# icyradio.net
KiCad netlist of a schematic drawn in EAGLE
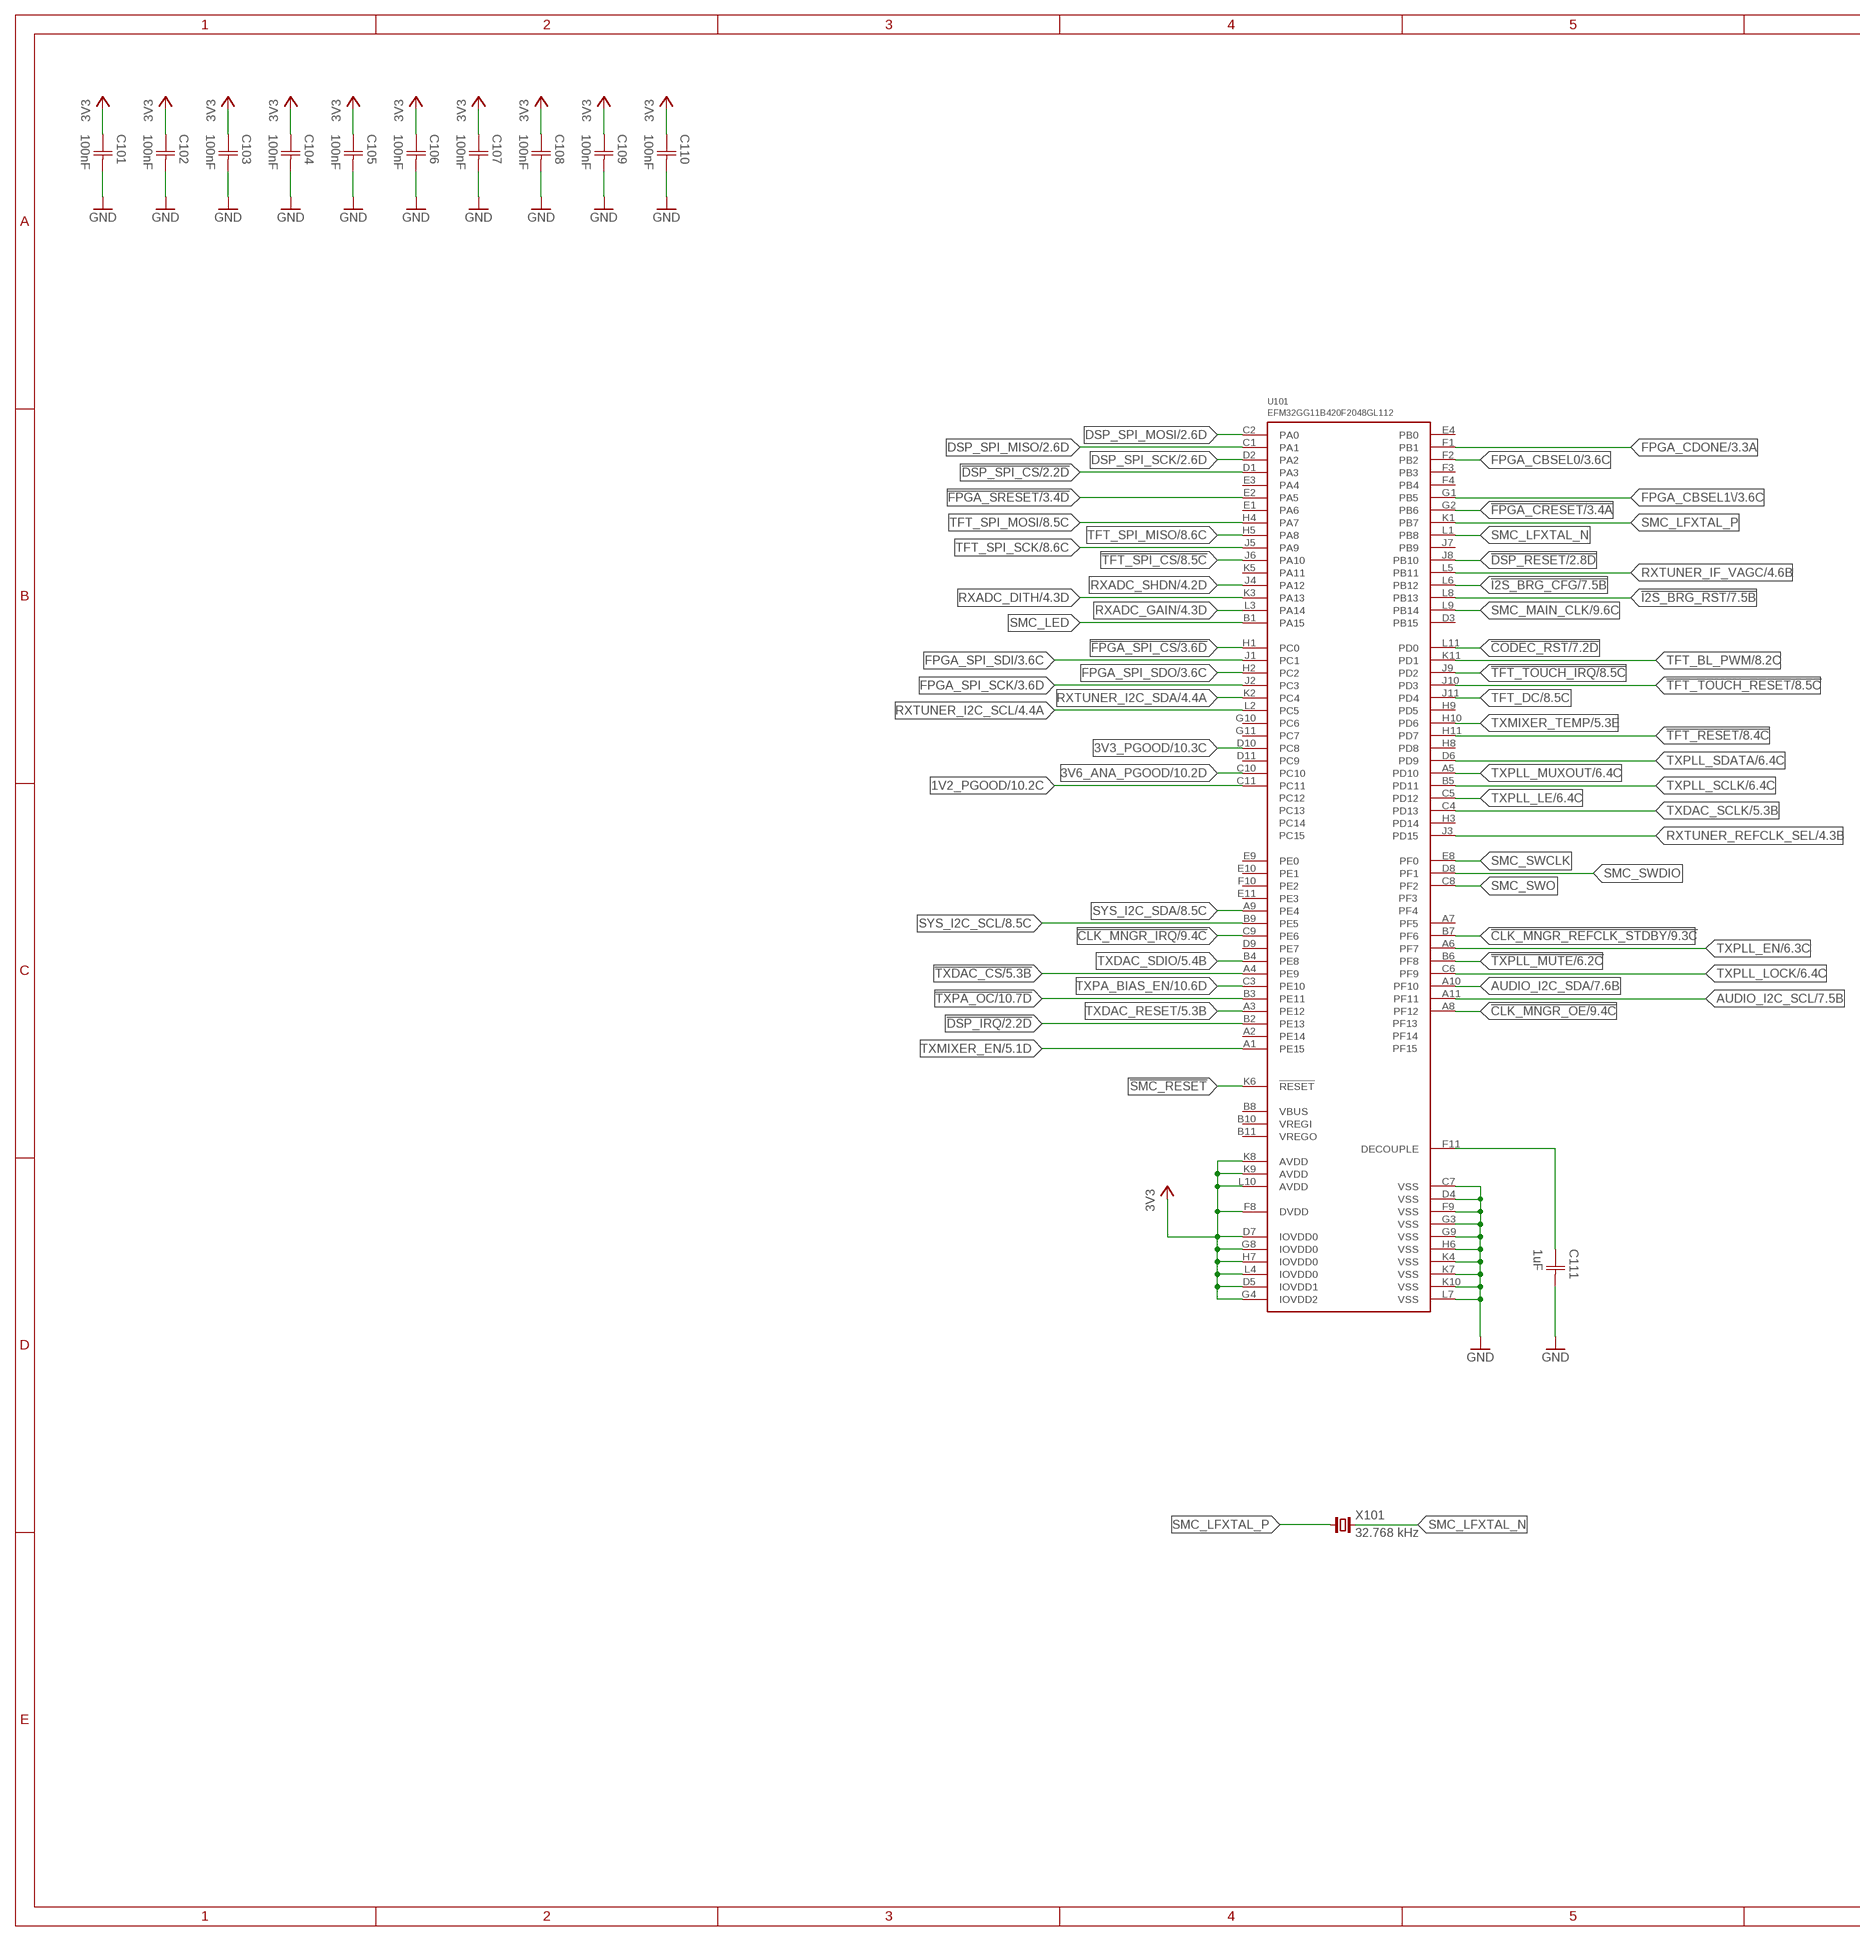
[diagram p0: schematic, sheet 1, part 1 of 2]
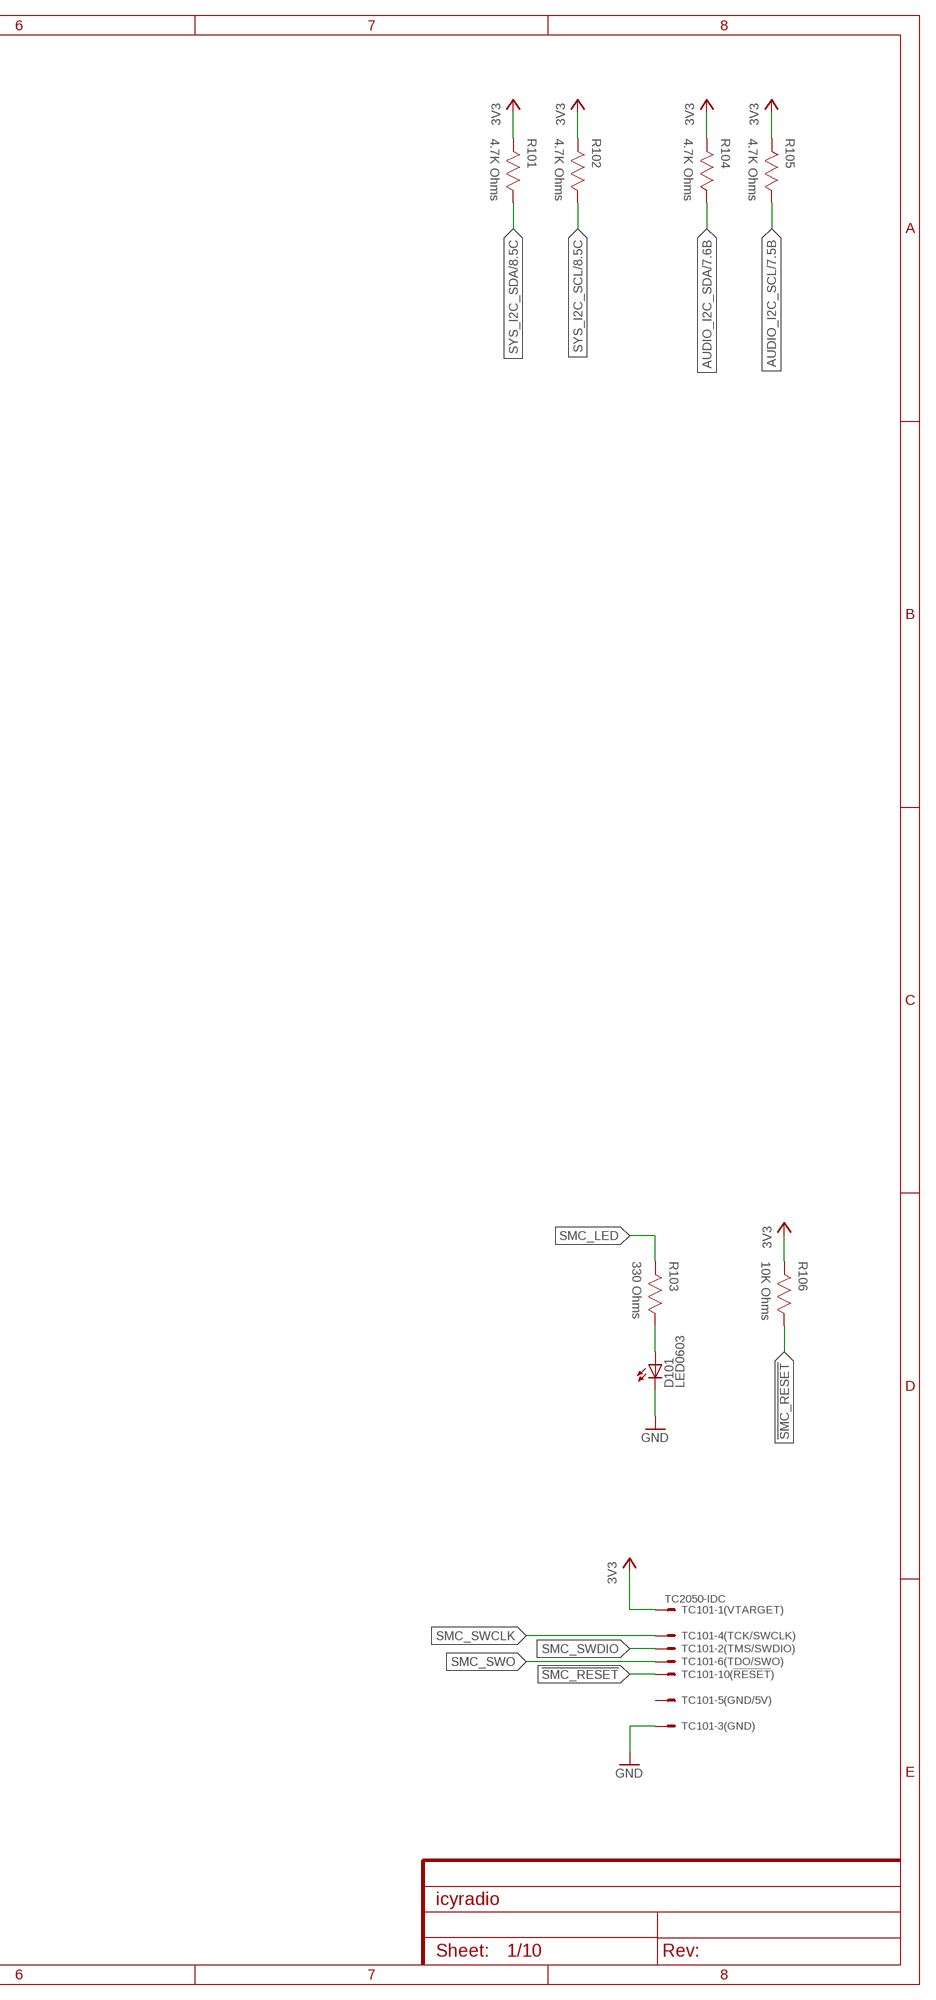
[diagram p1: schematic, sheet 1, part 2 of 2]
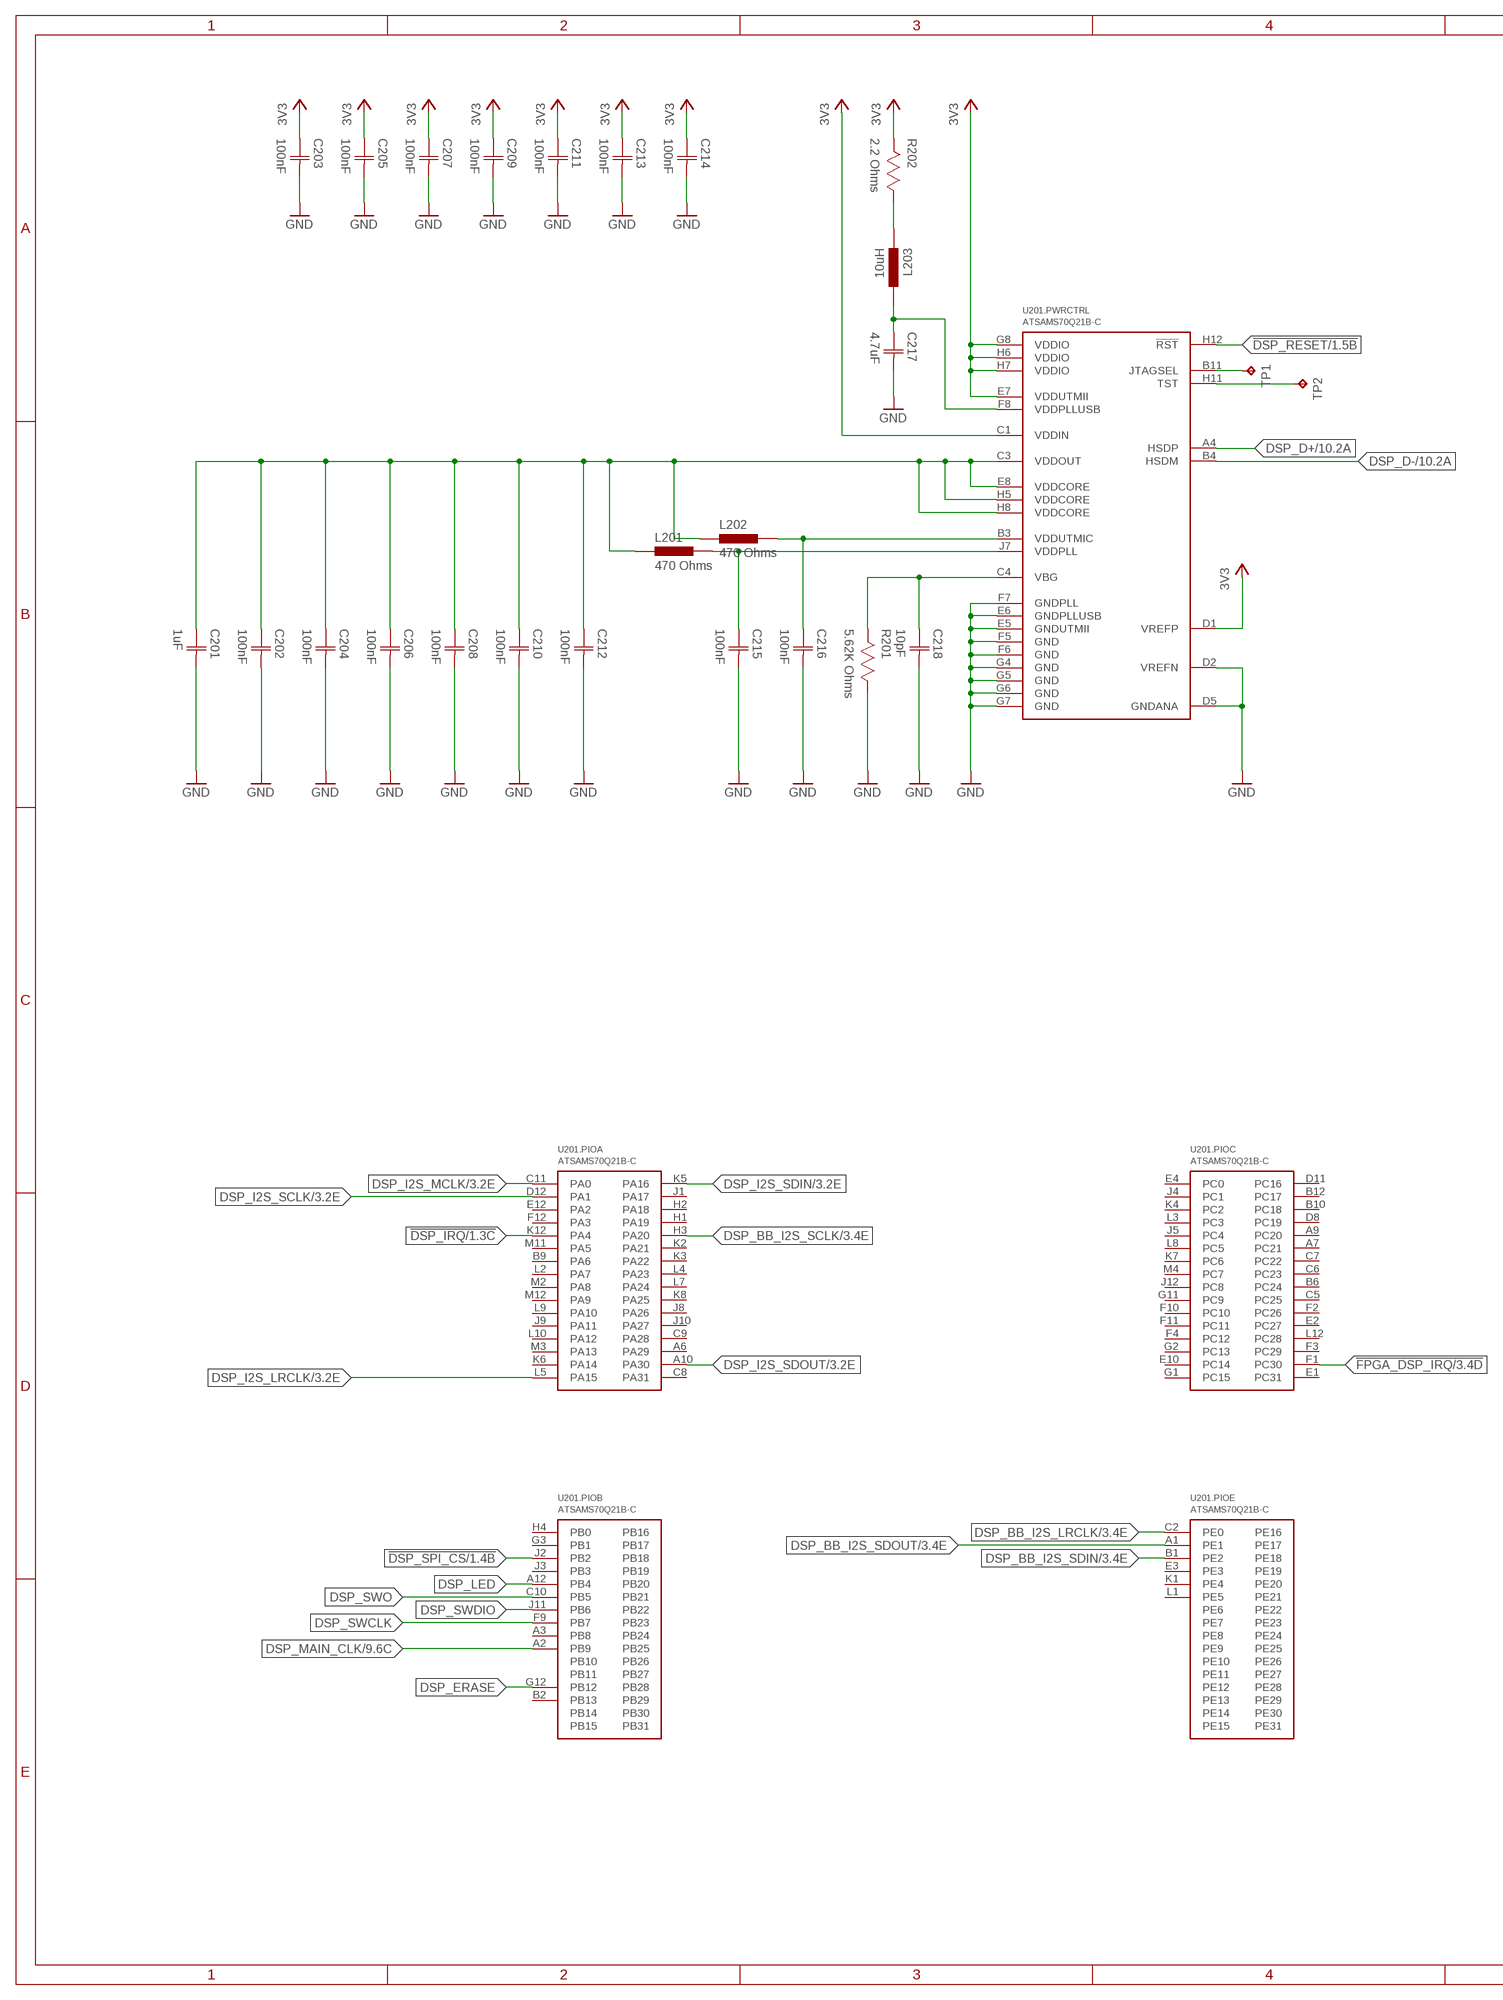
[diagram p2: schematic, sheet 2, part 1 of 2]
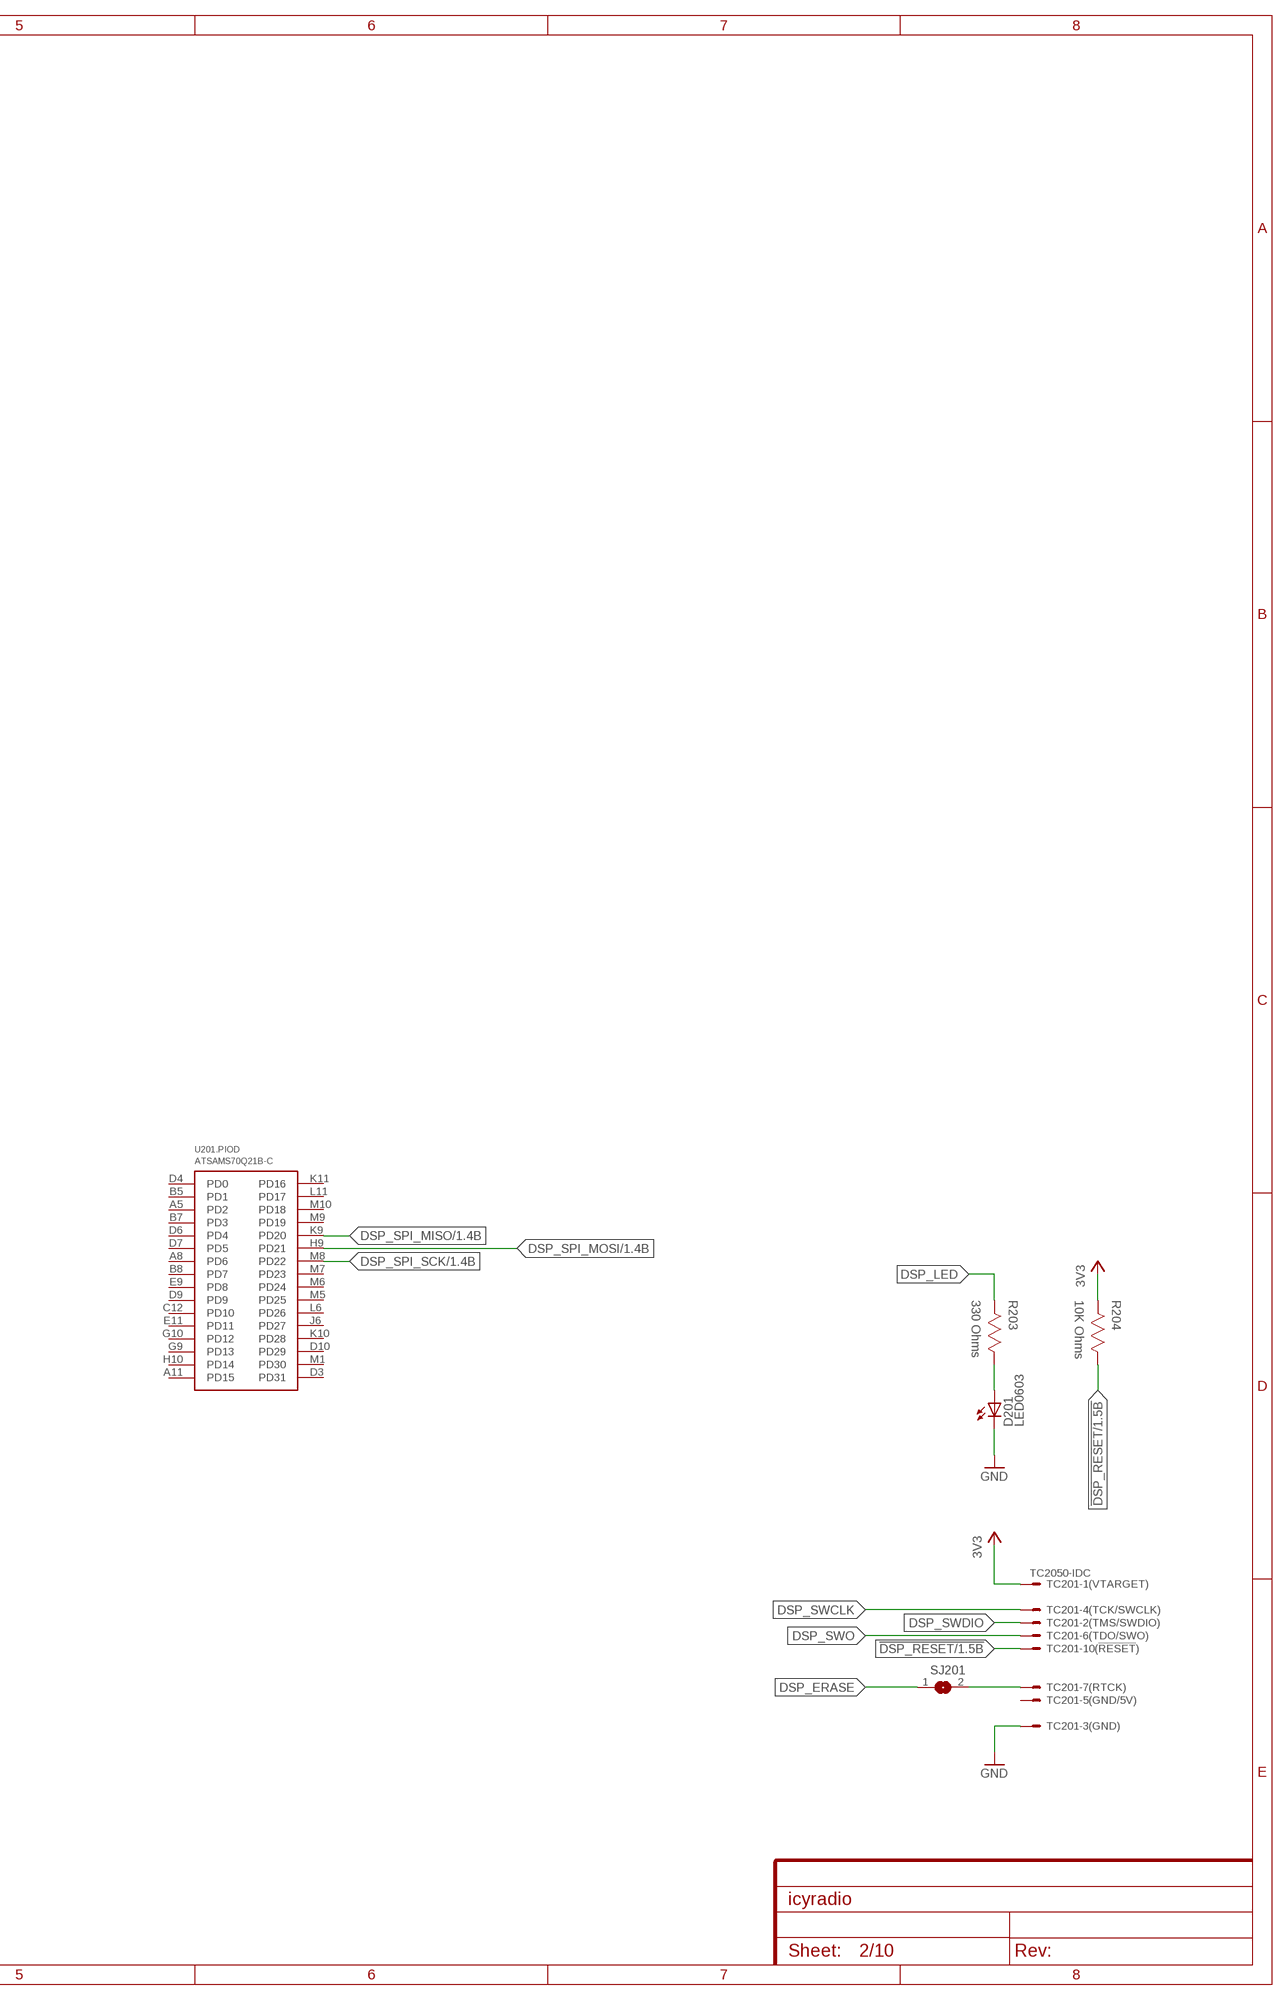
[diagram p3: schematic, sheet 2, part 2 of 2]
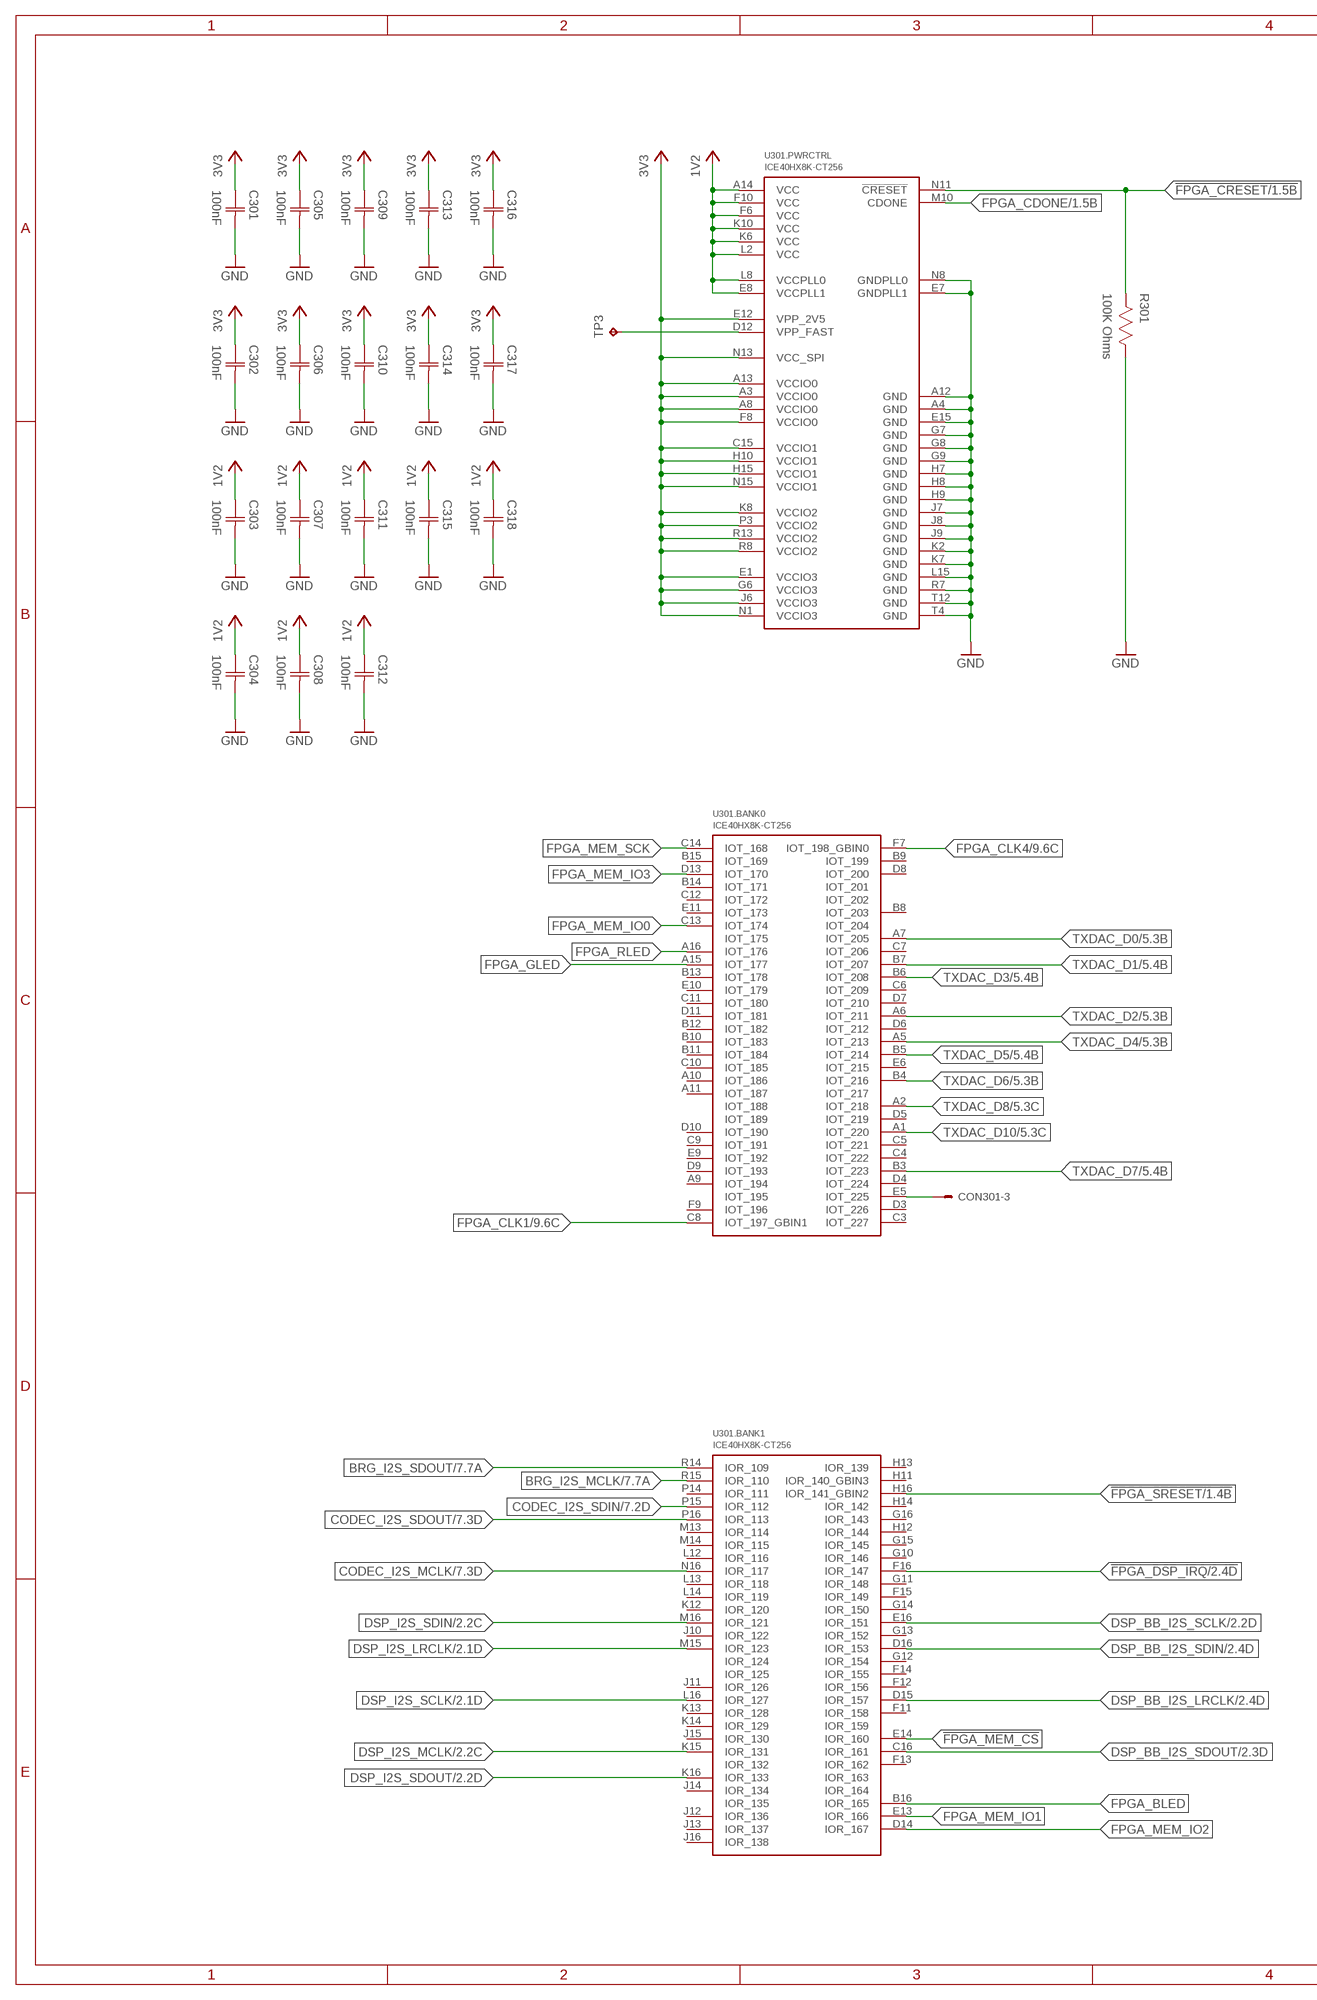
[diagram p4: schematic, sheet 3, part 1 of 2]
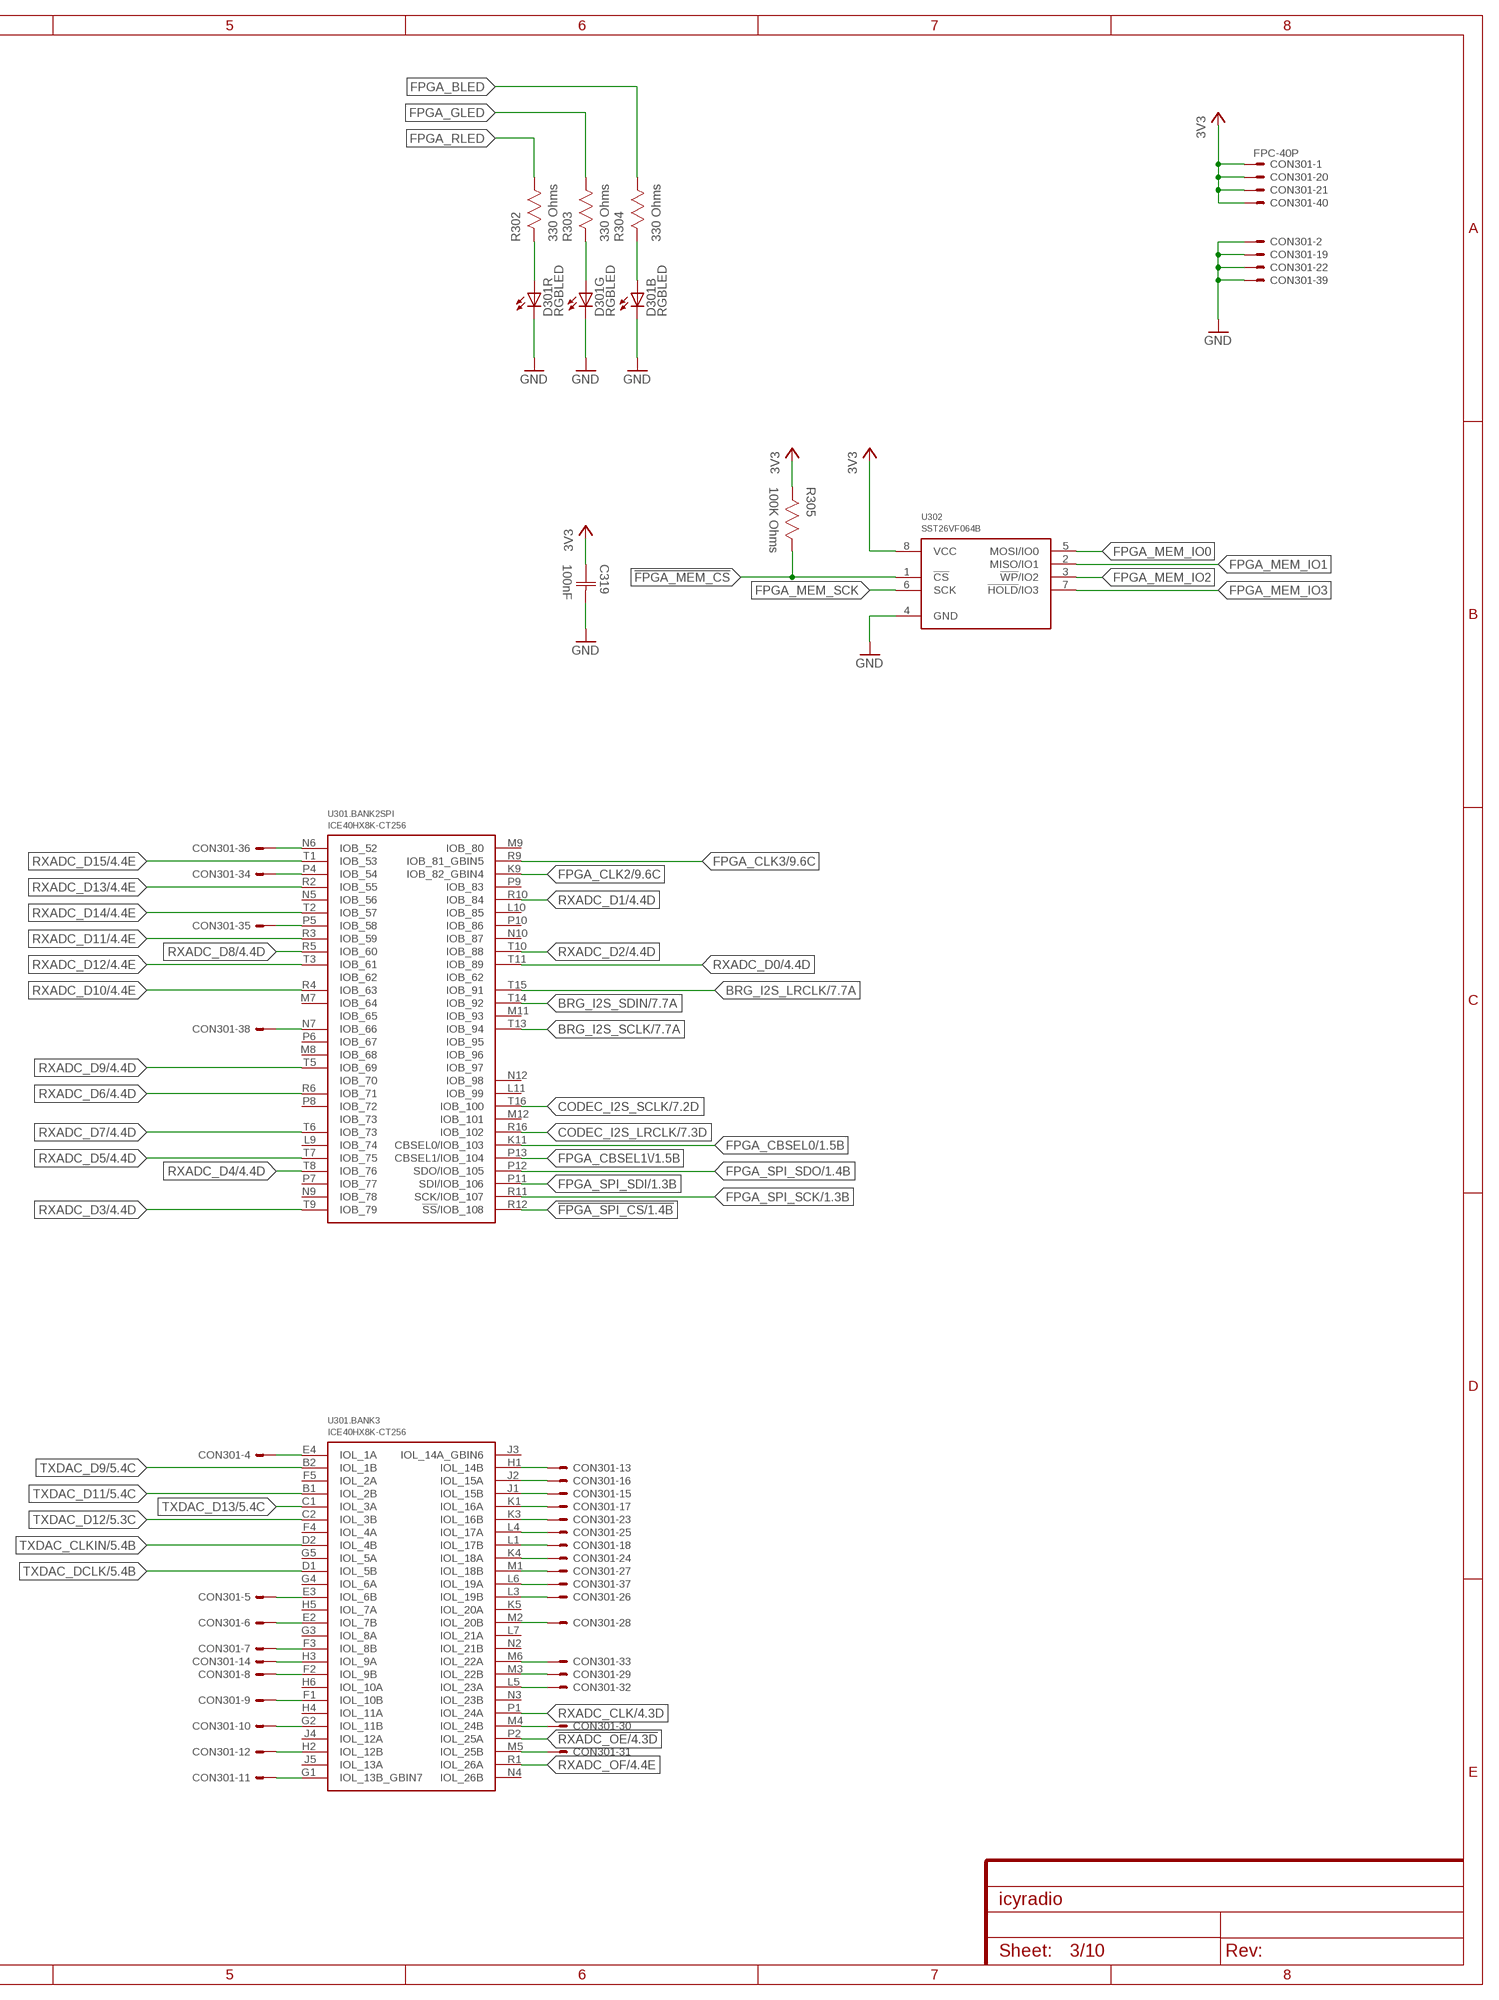
[diagram p5: schematic, sheet 3, part 2 of 2]
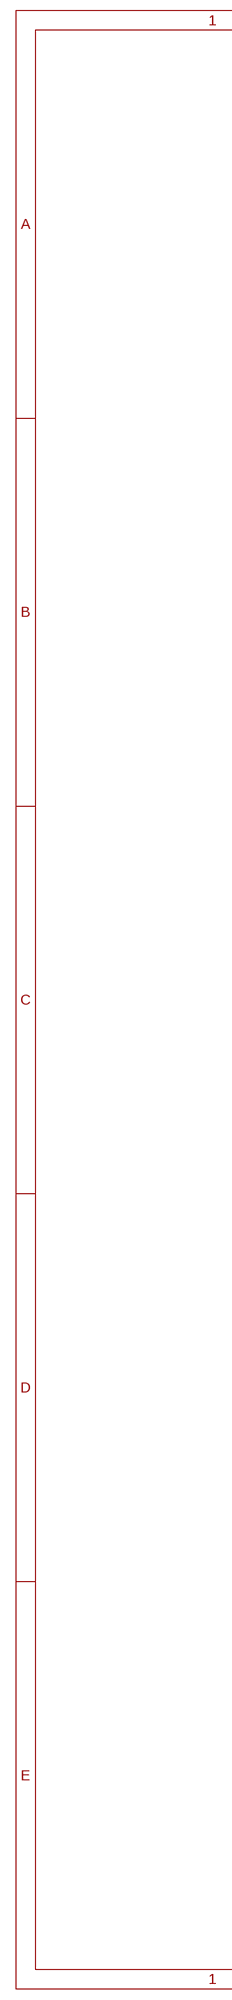
[diagram p6: schematic, sheet 4, part 1 of 2]
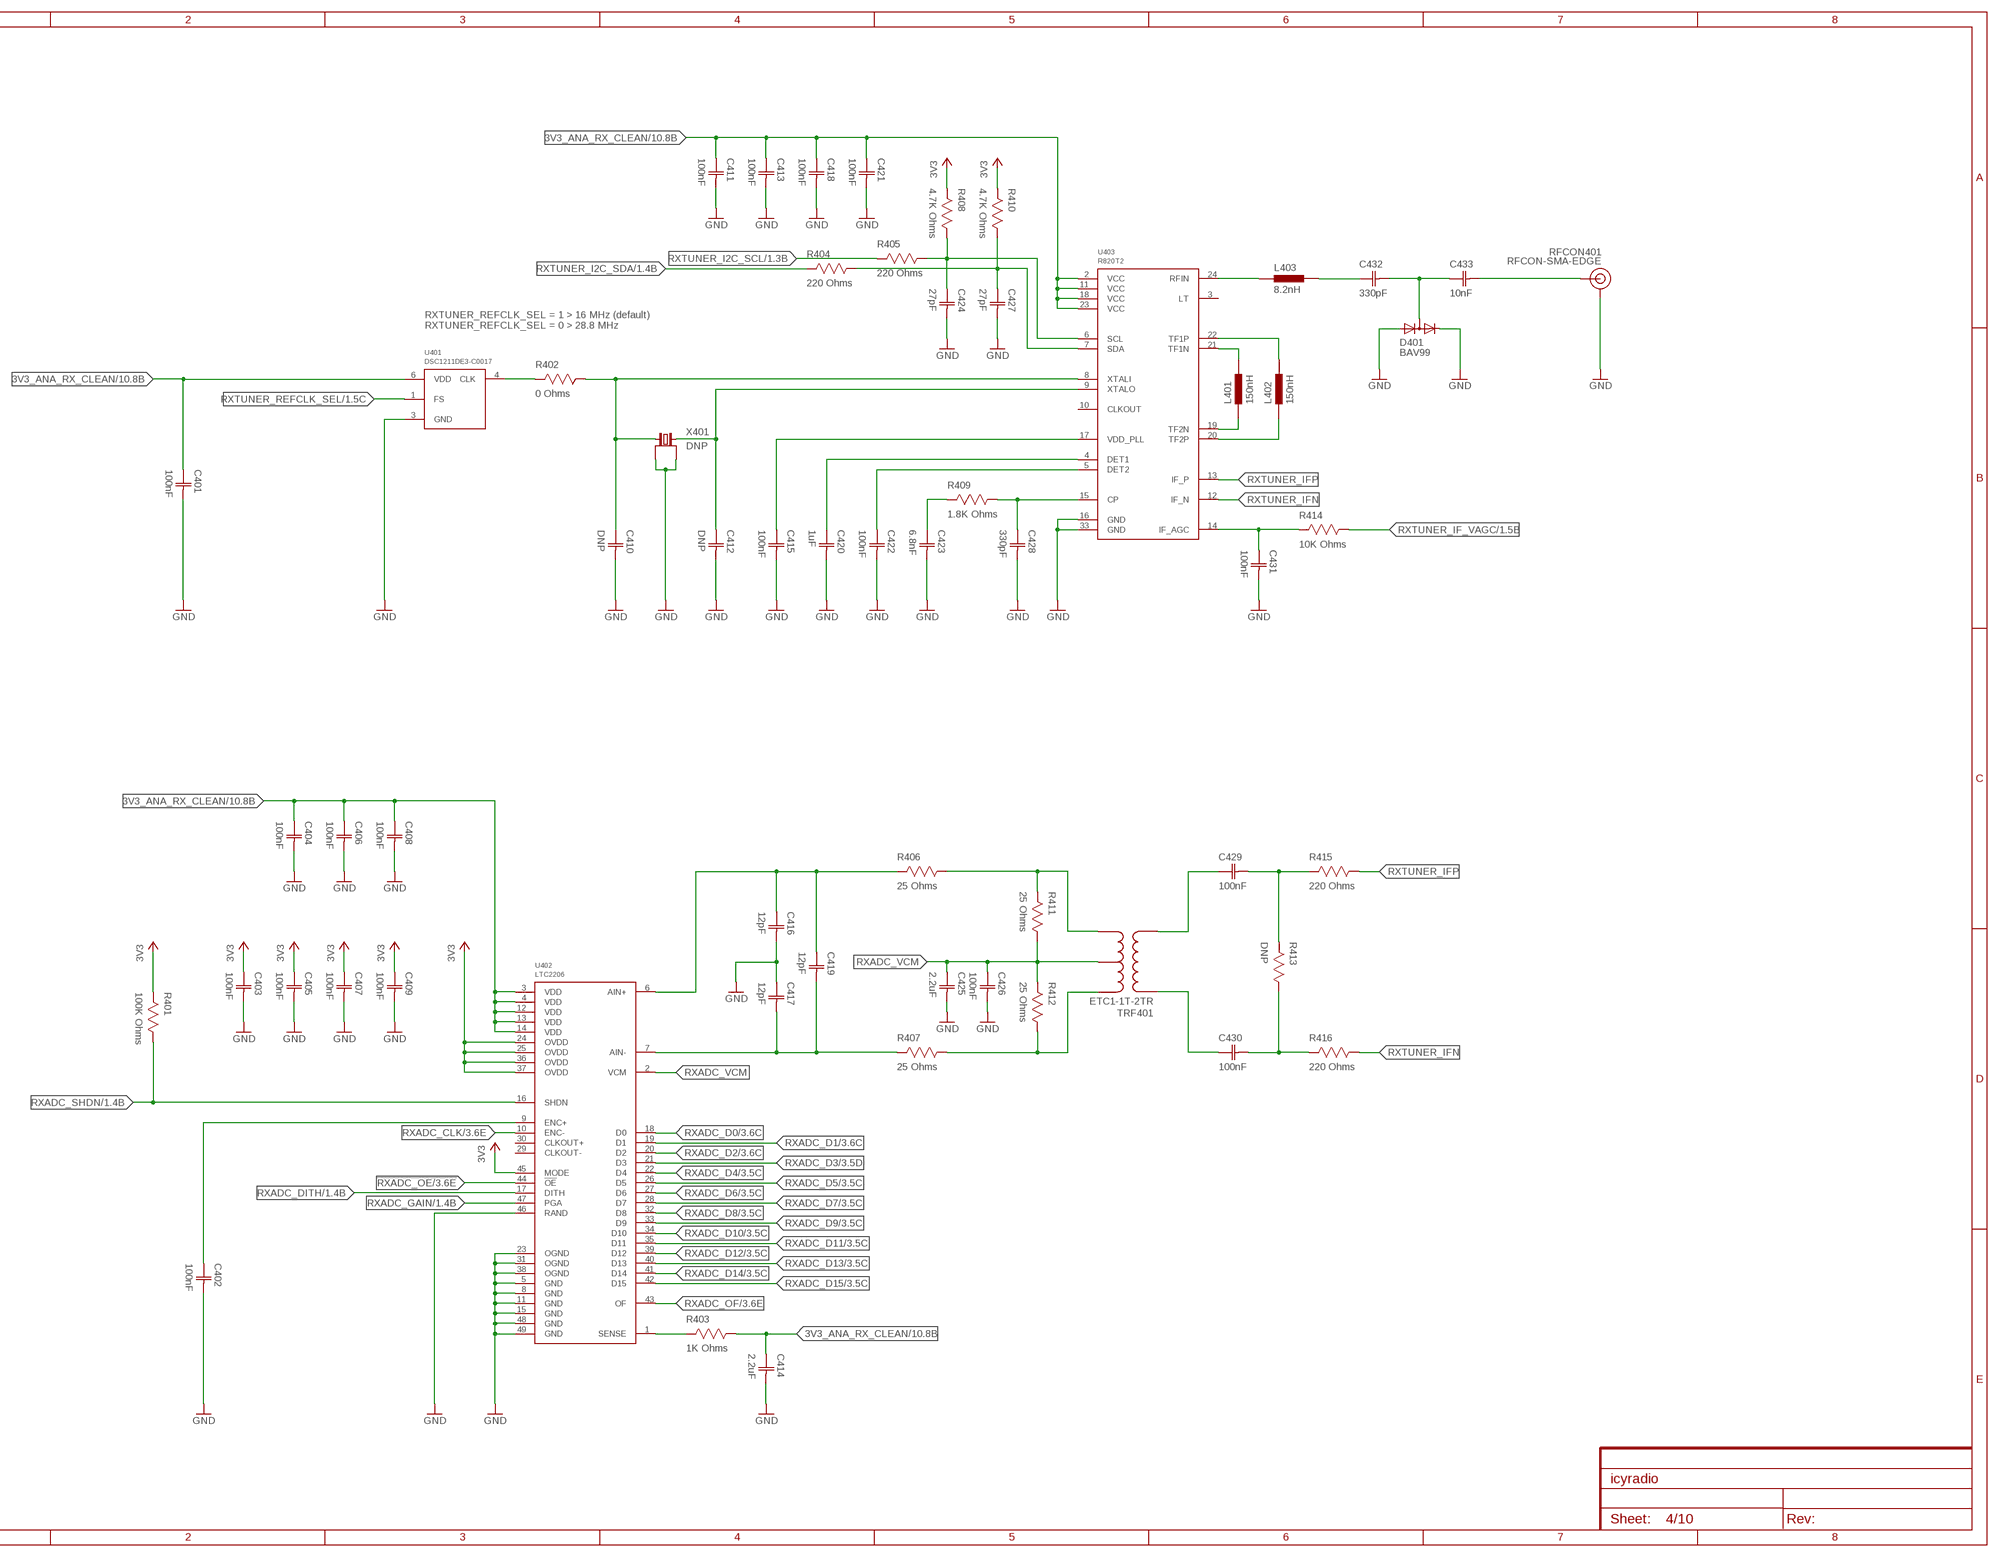
[diagram p7: schematic, sheet 4, part 2 of 2]
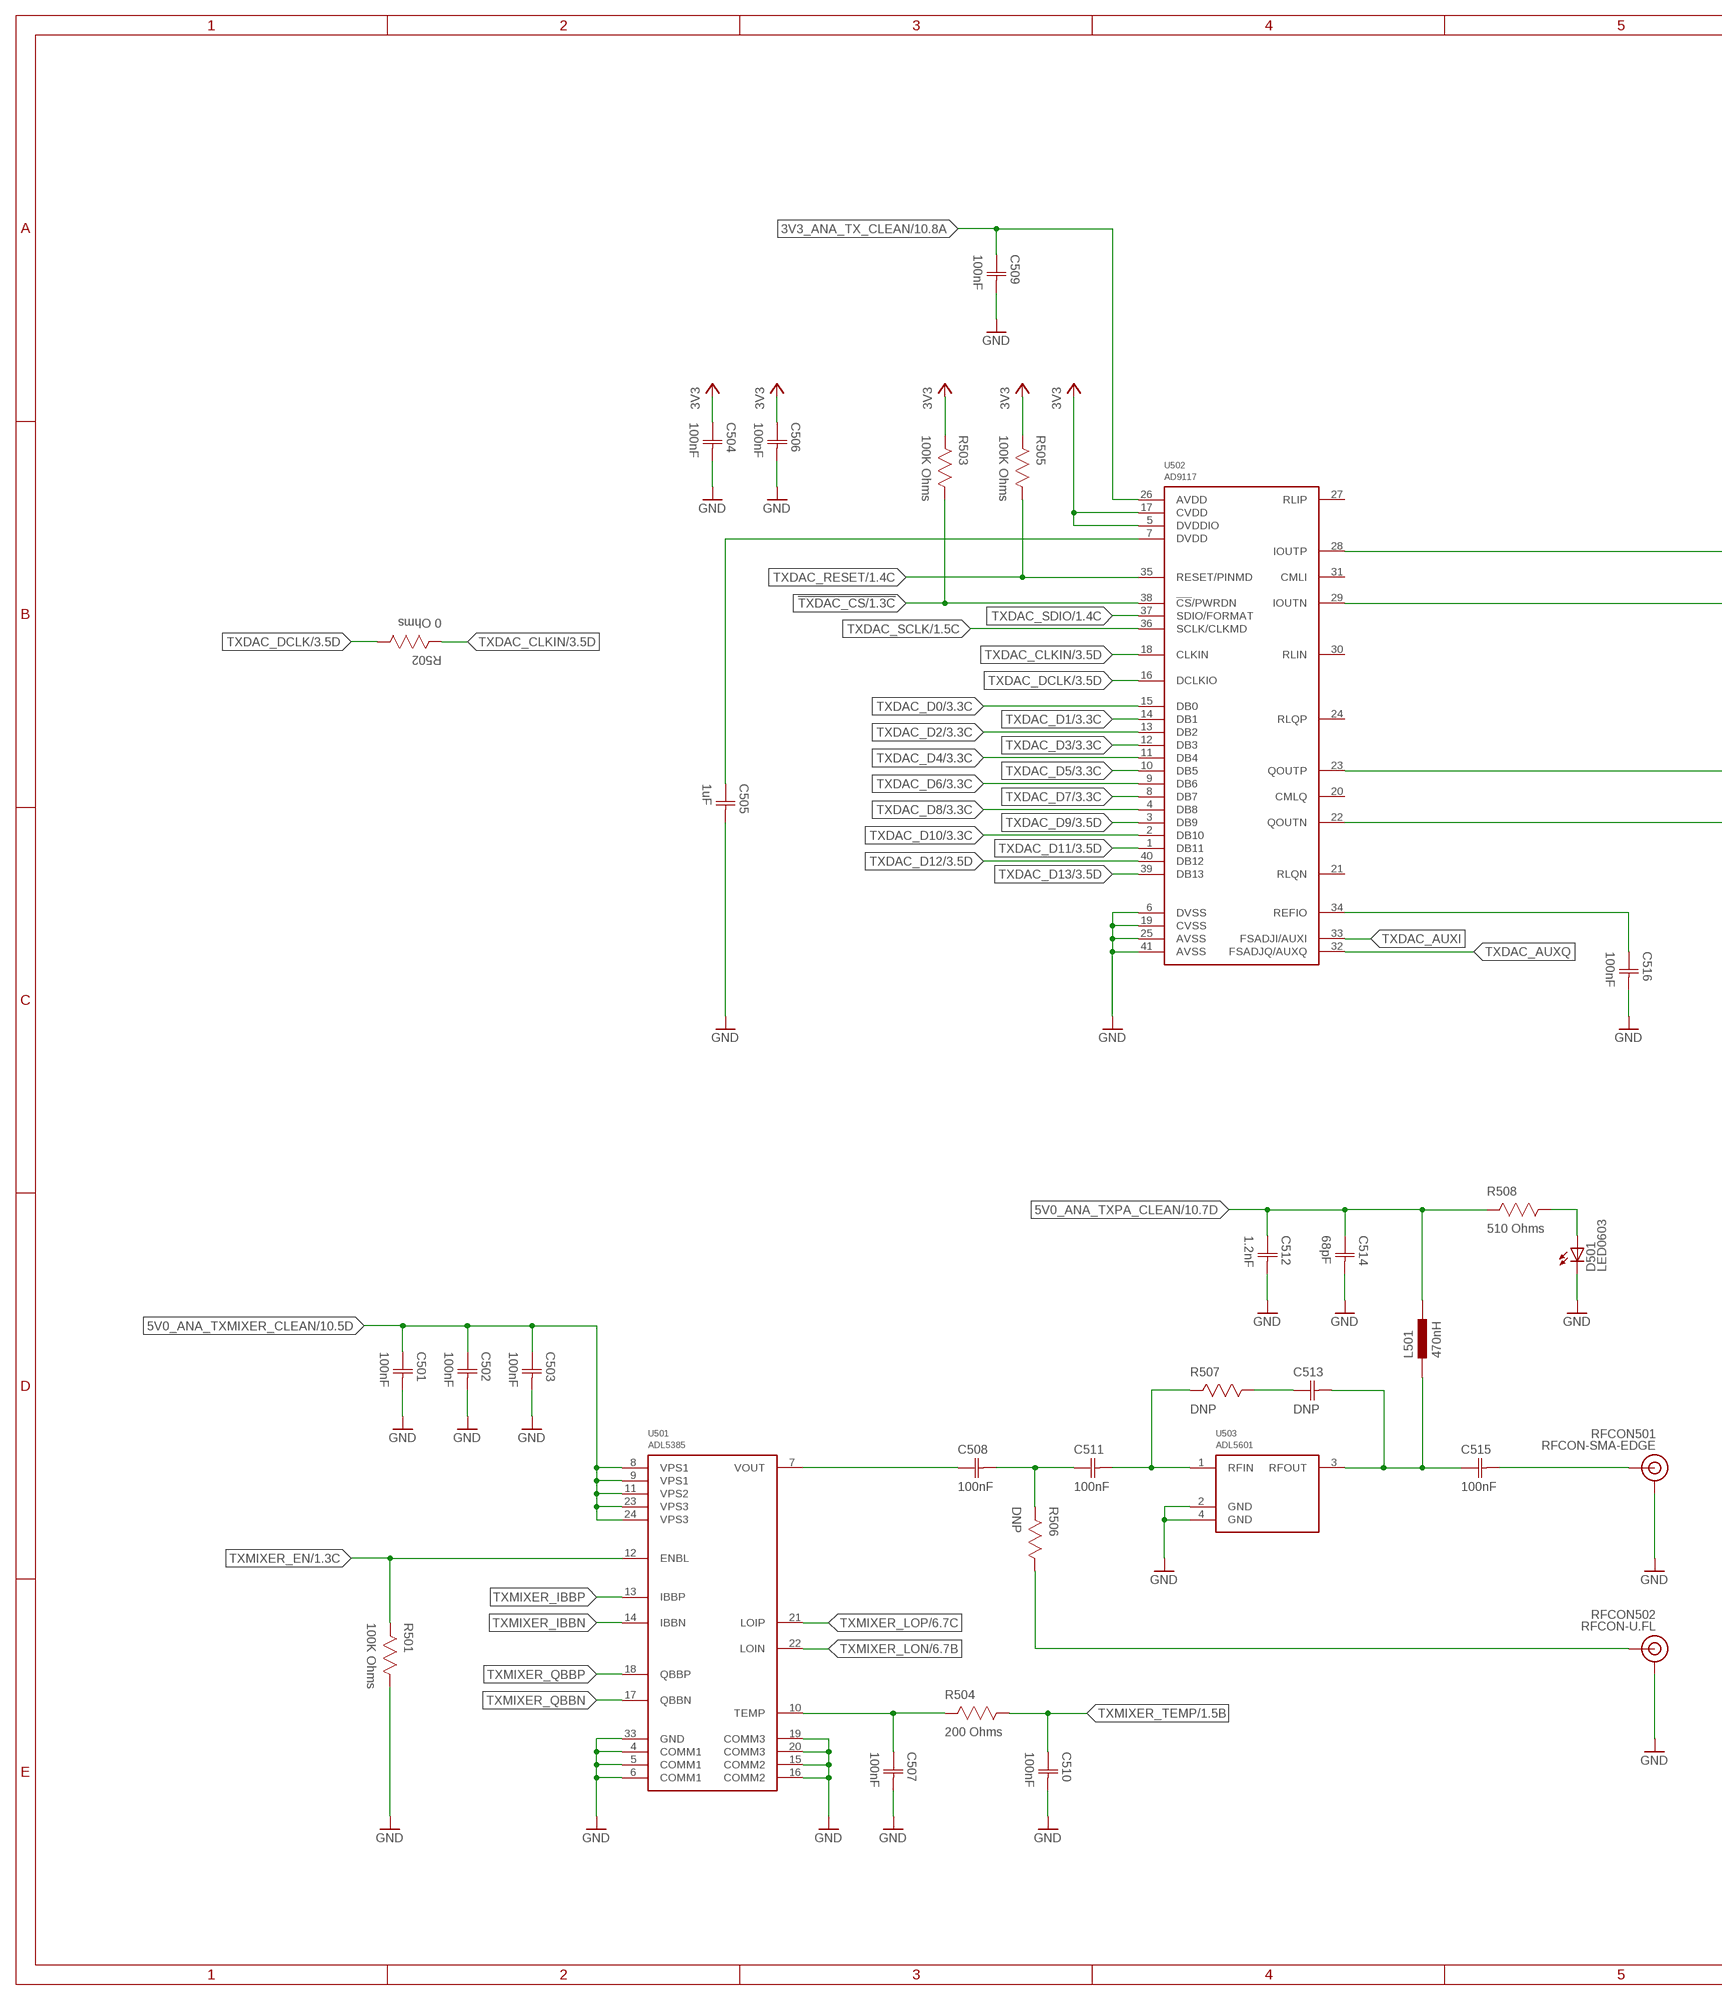
[diagram p8: schematic, sheet 5, part 1 of 2]
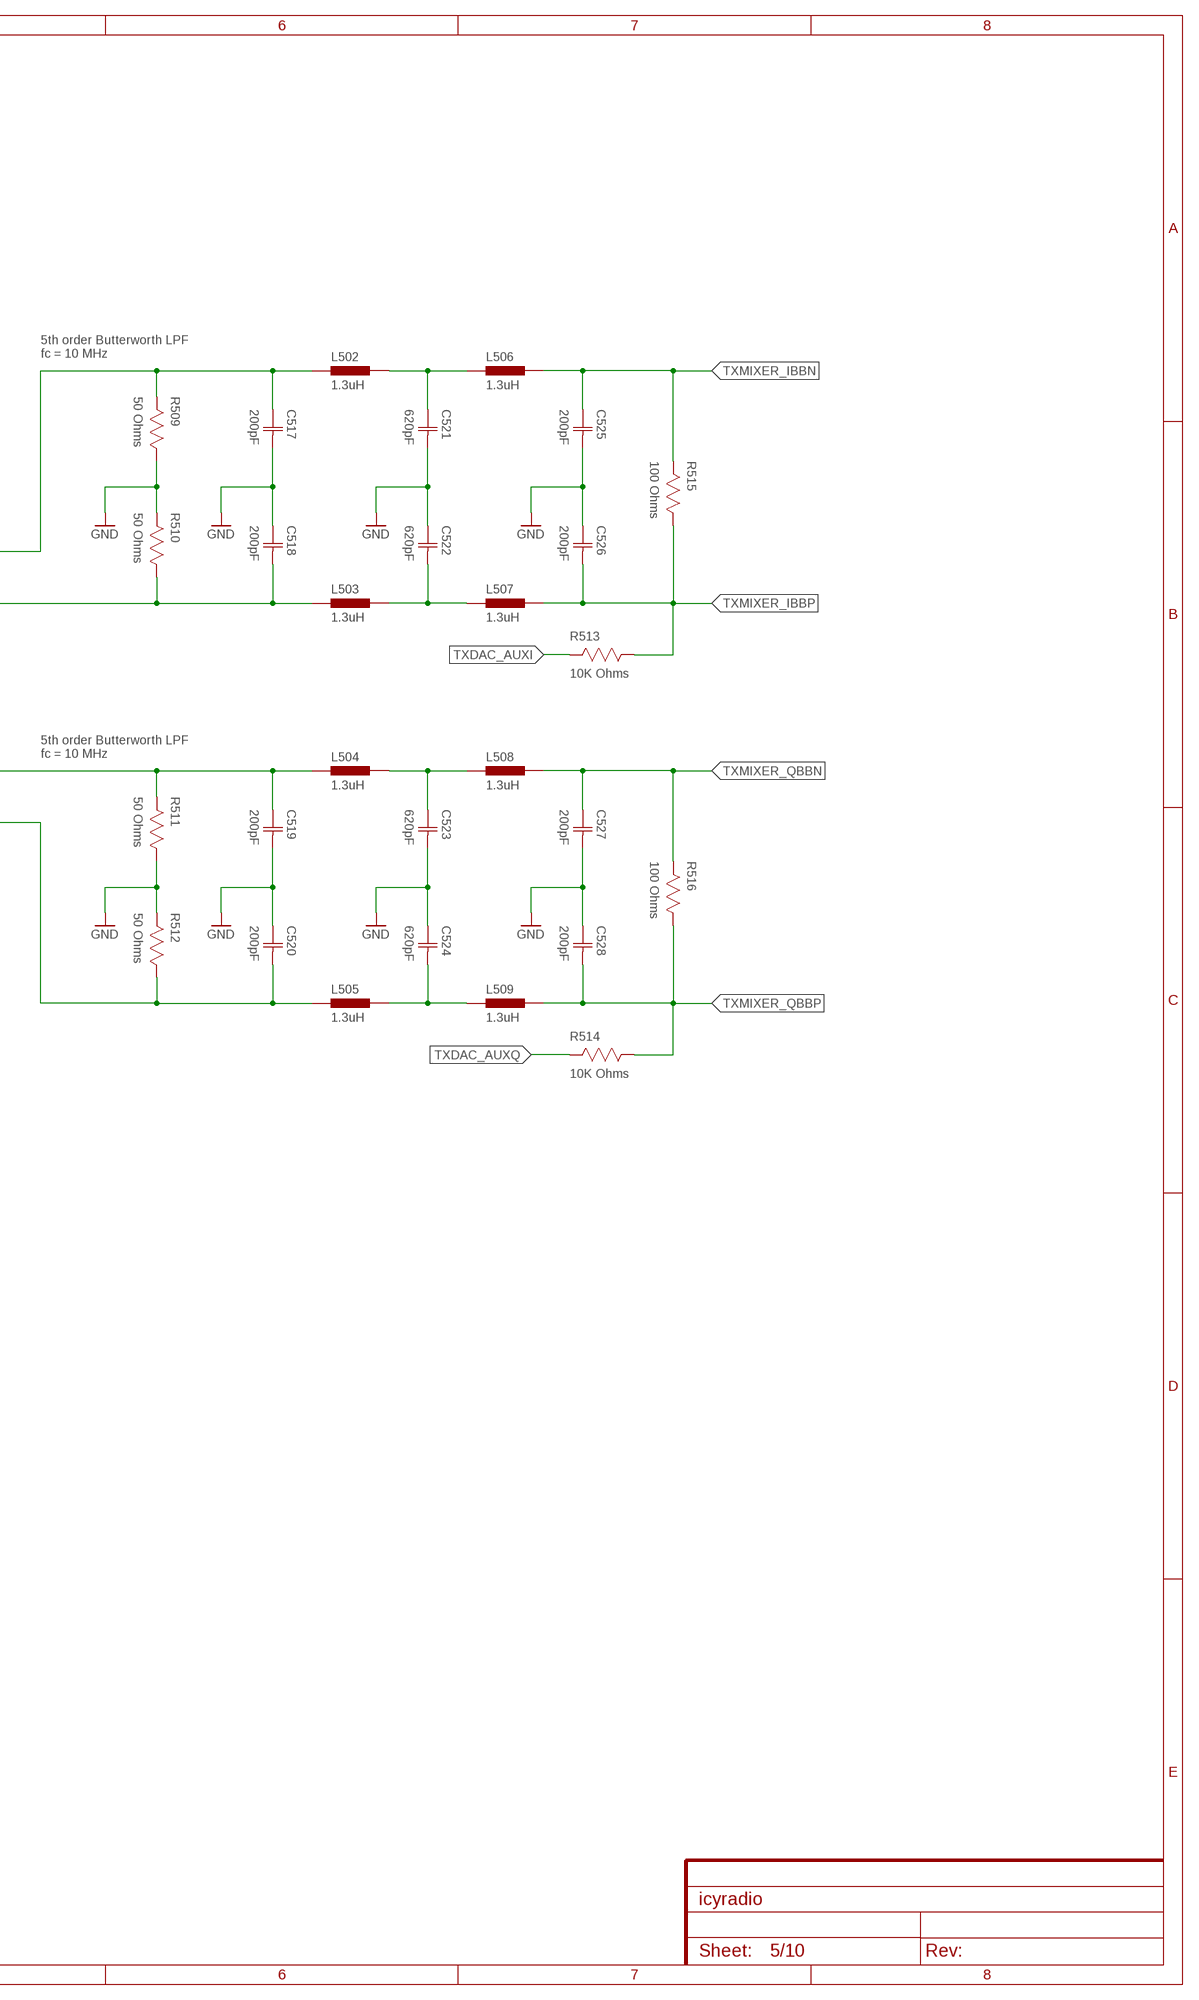
[diagram p9: schematic, sheet 5, part 2 of 2]
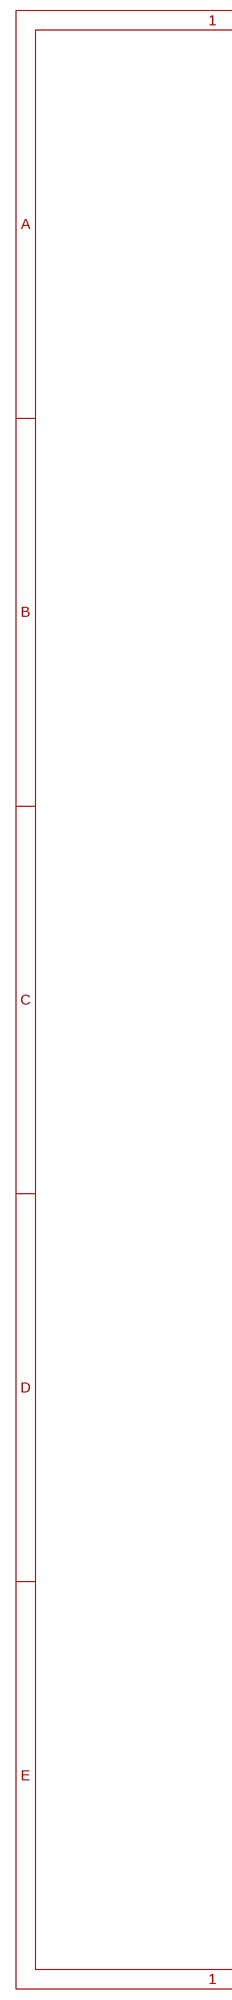
[diagram p10: schematic, sheet 6, part 1 of 2]
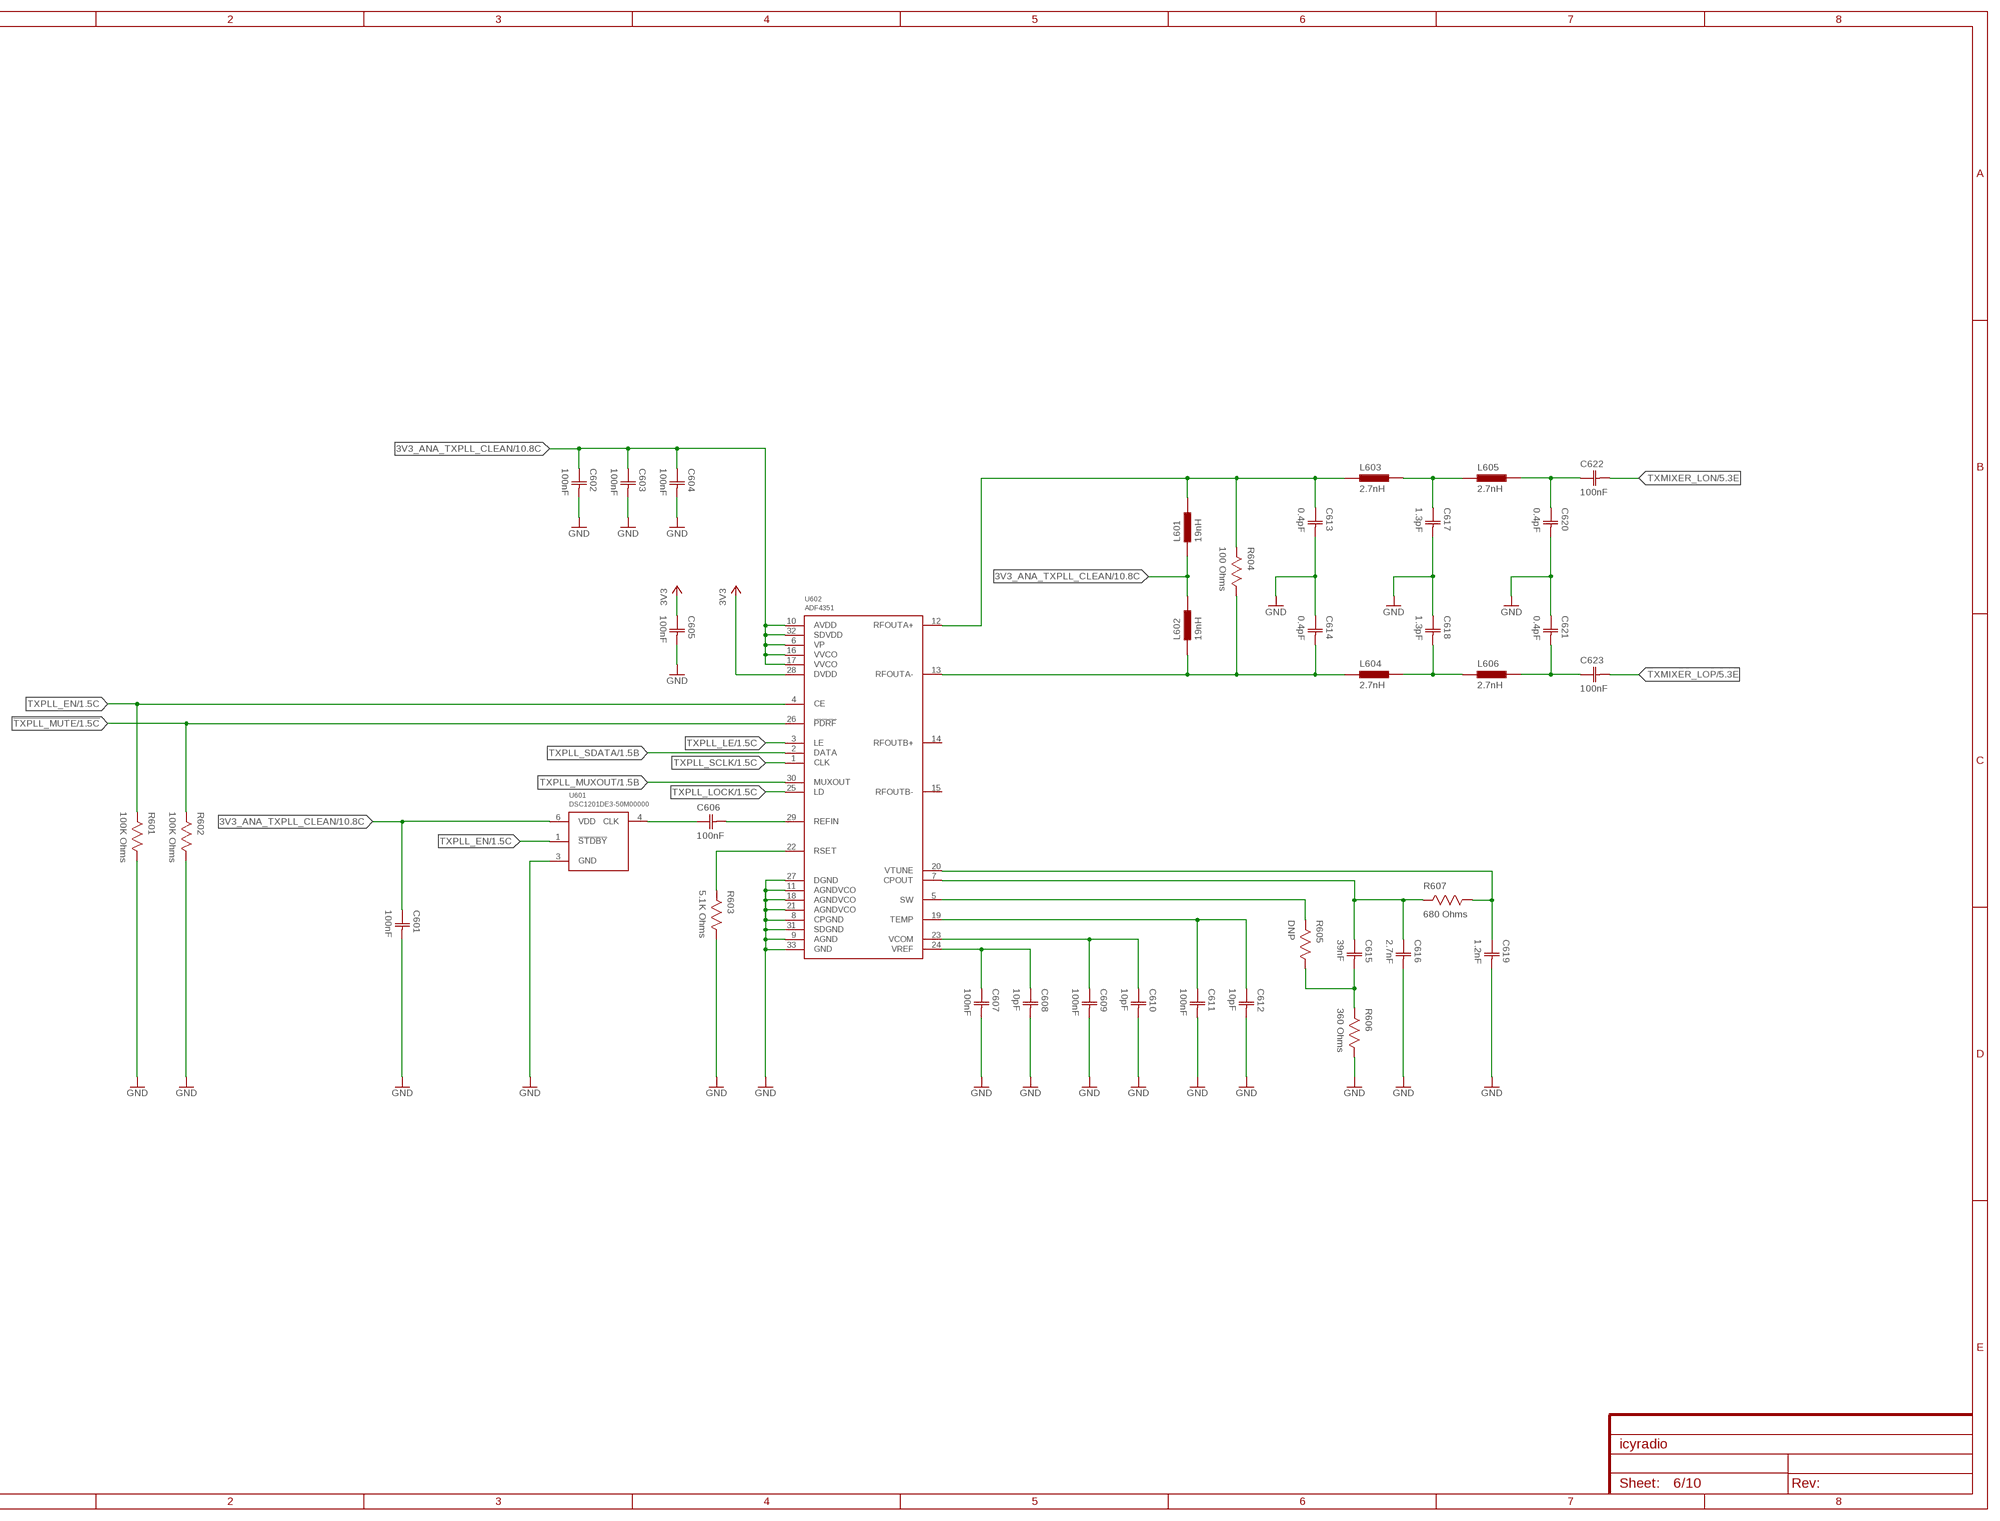
[diagram p11: schematic, sheet 6, part 2 of 2]
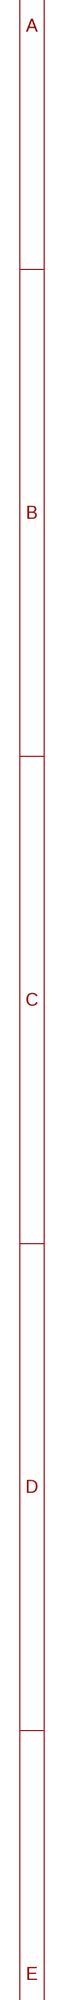
[diagram p12: schematic, sheet 7, part 1 of 2]
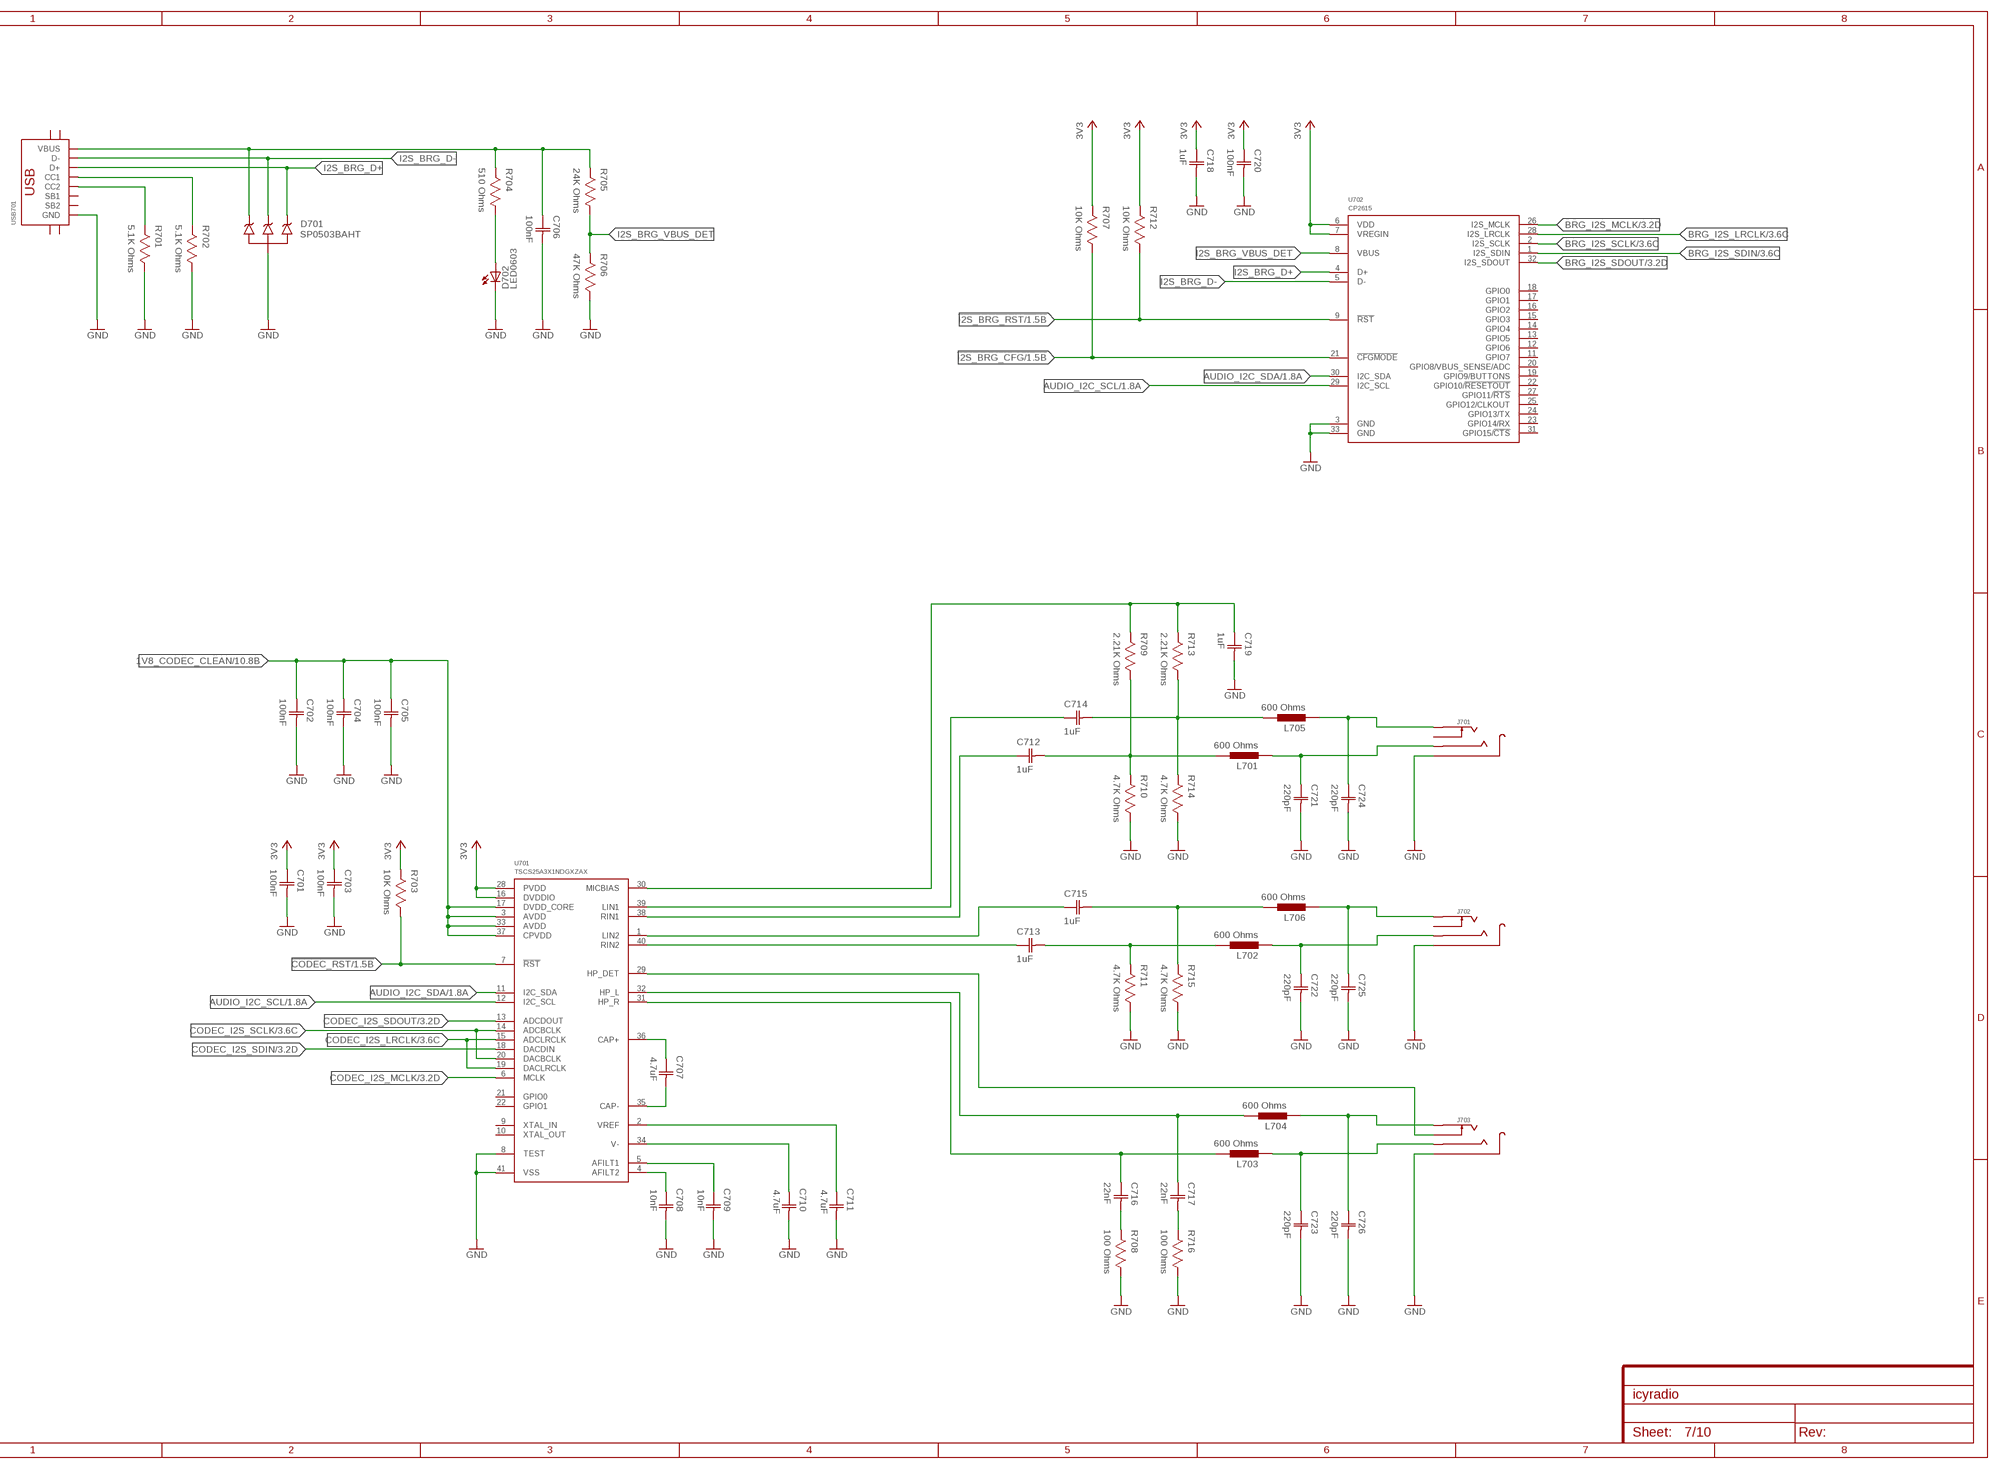
[diagram p13: schematic, sheet 7, part 2 of 2]
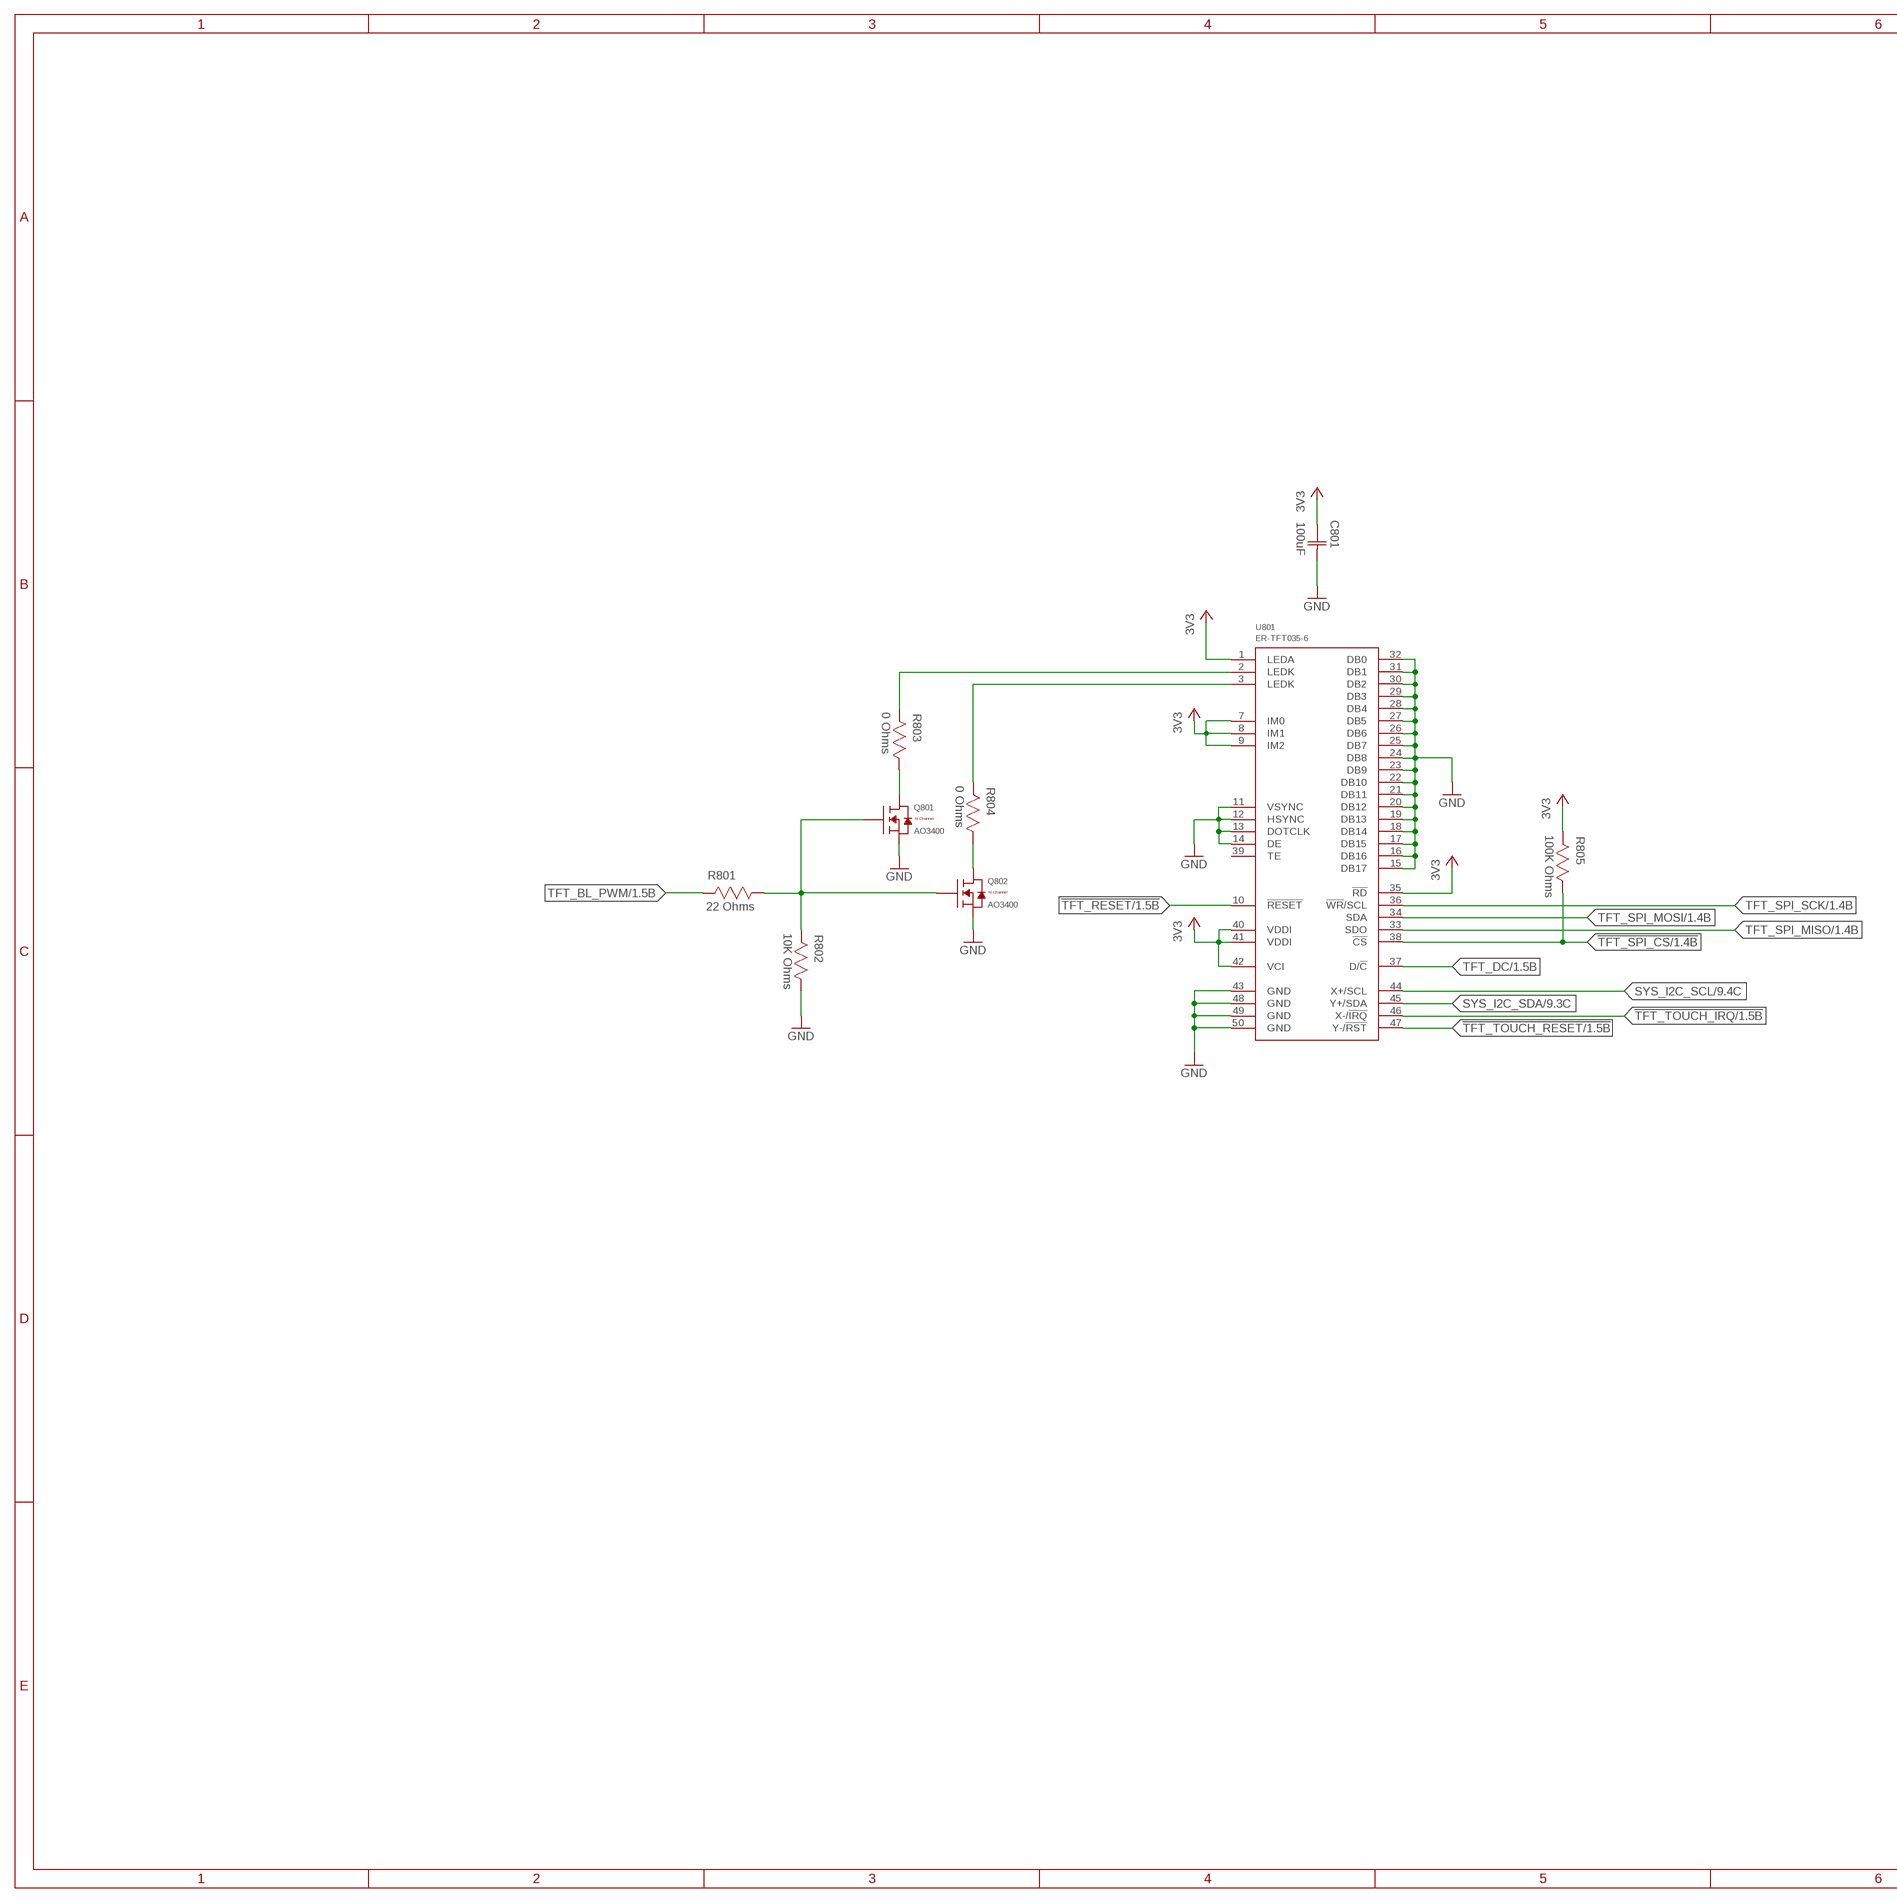
[diagram p14: schematic, sheet 8, part 1 of 2]
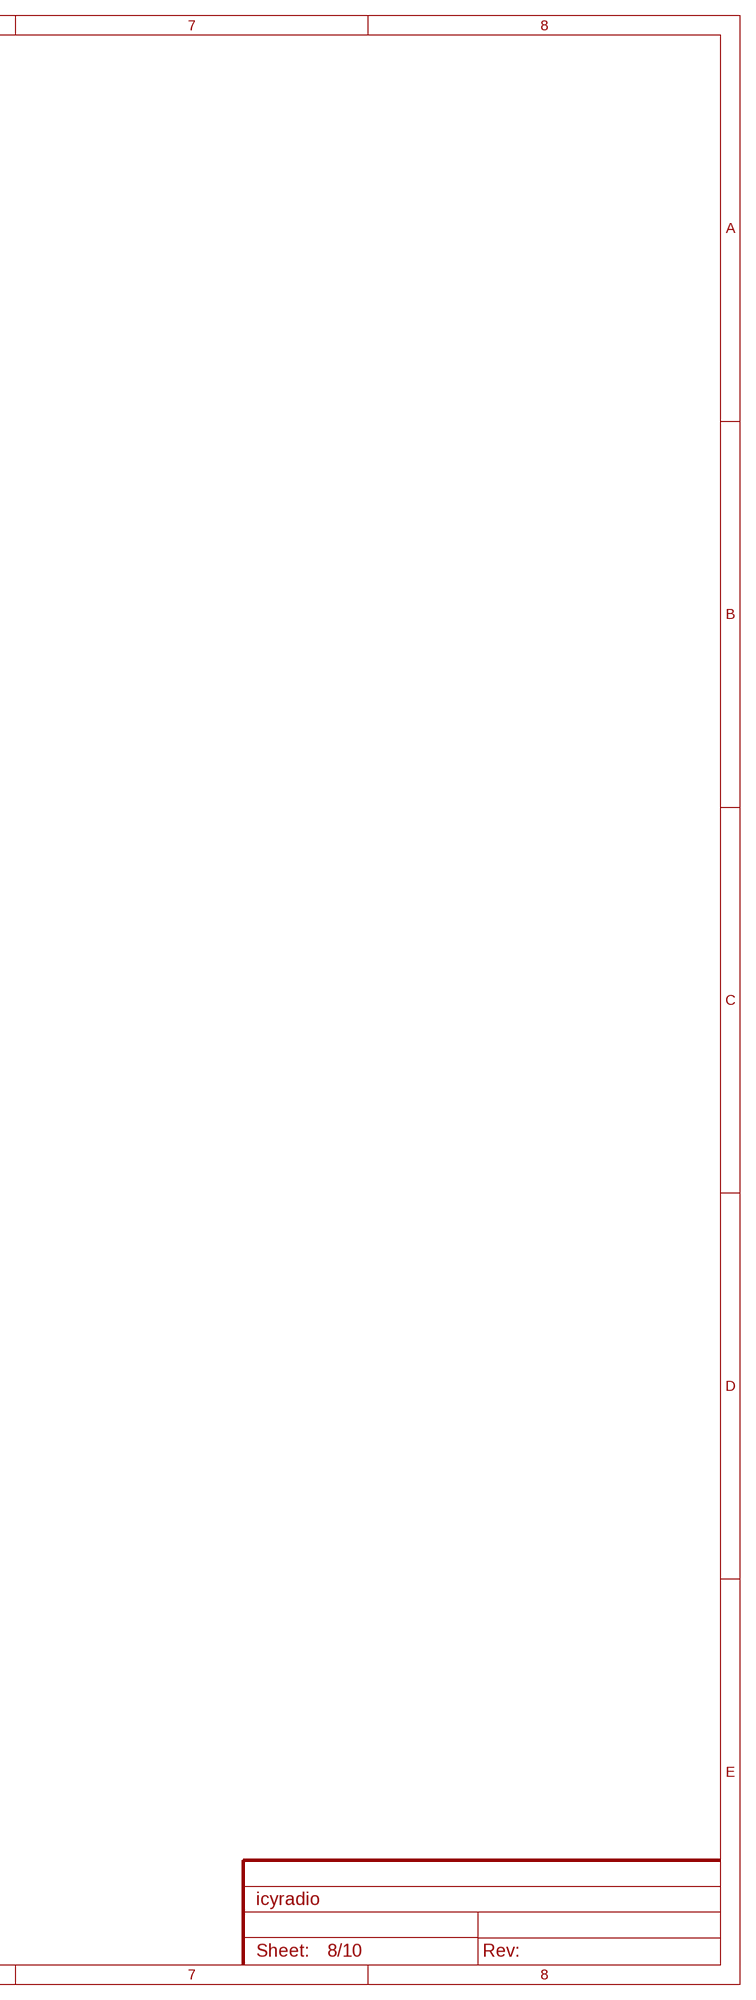
[diagram p15: schematic, sheet 8, part 2 of 2]
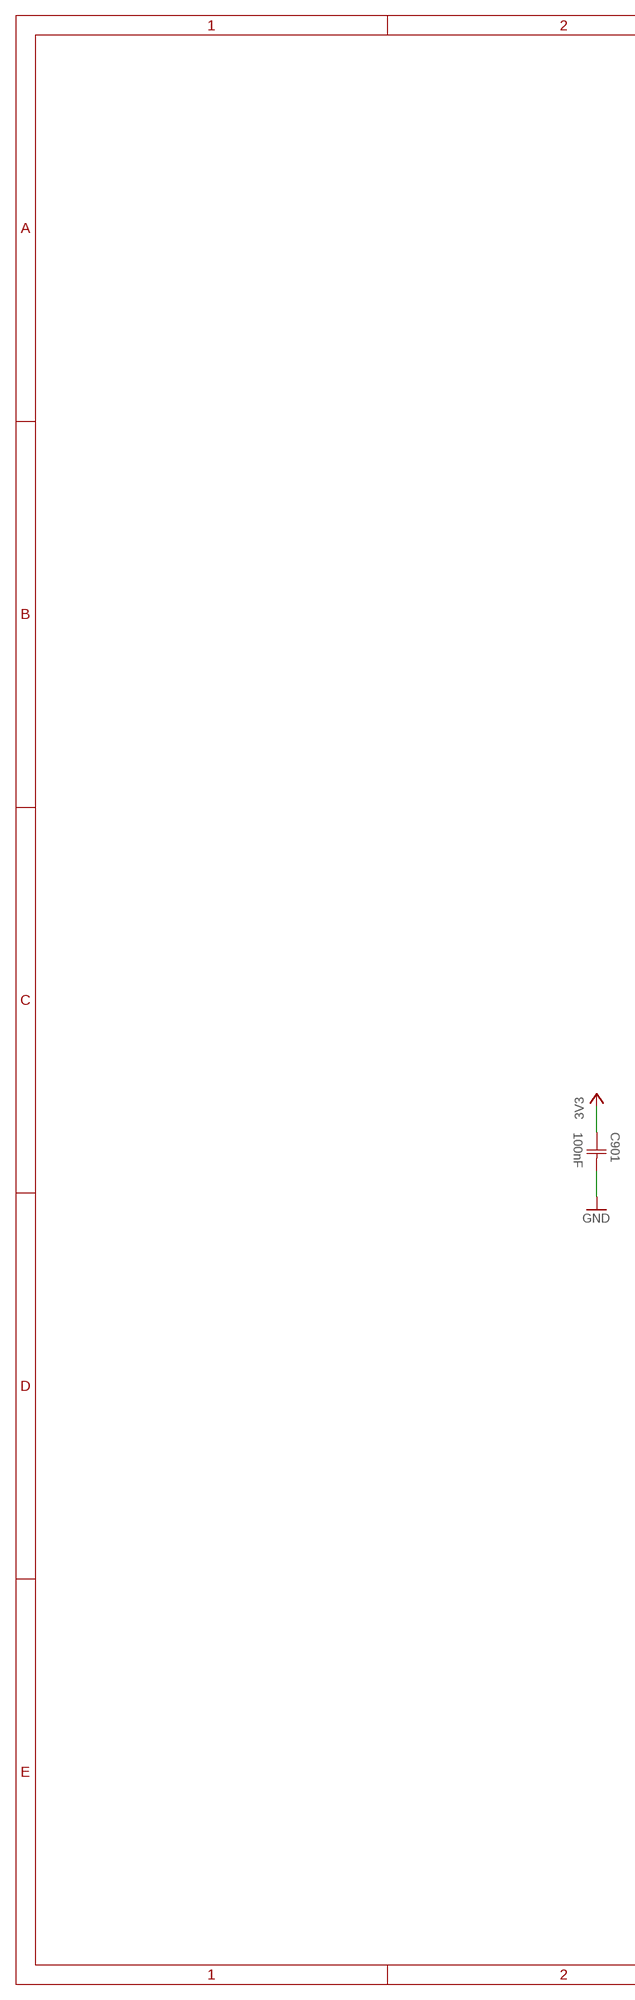
[diagram p16: schematic, sheet 9, part 1 of 2]
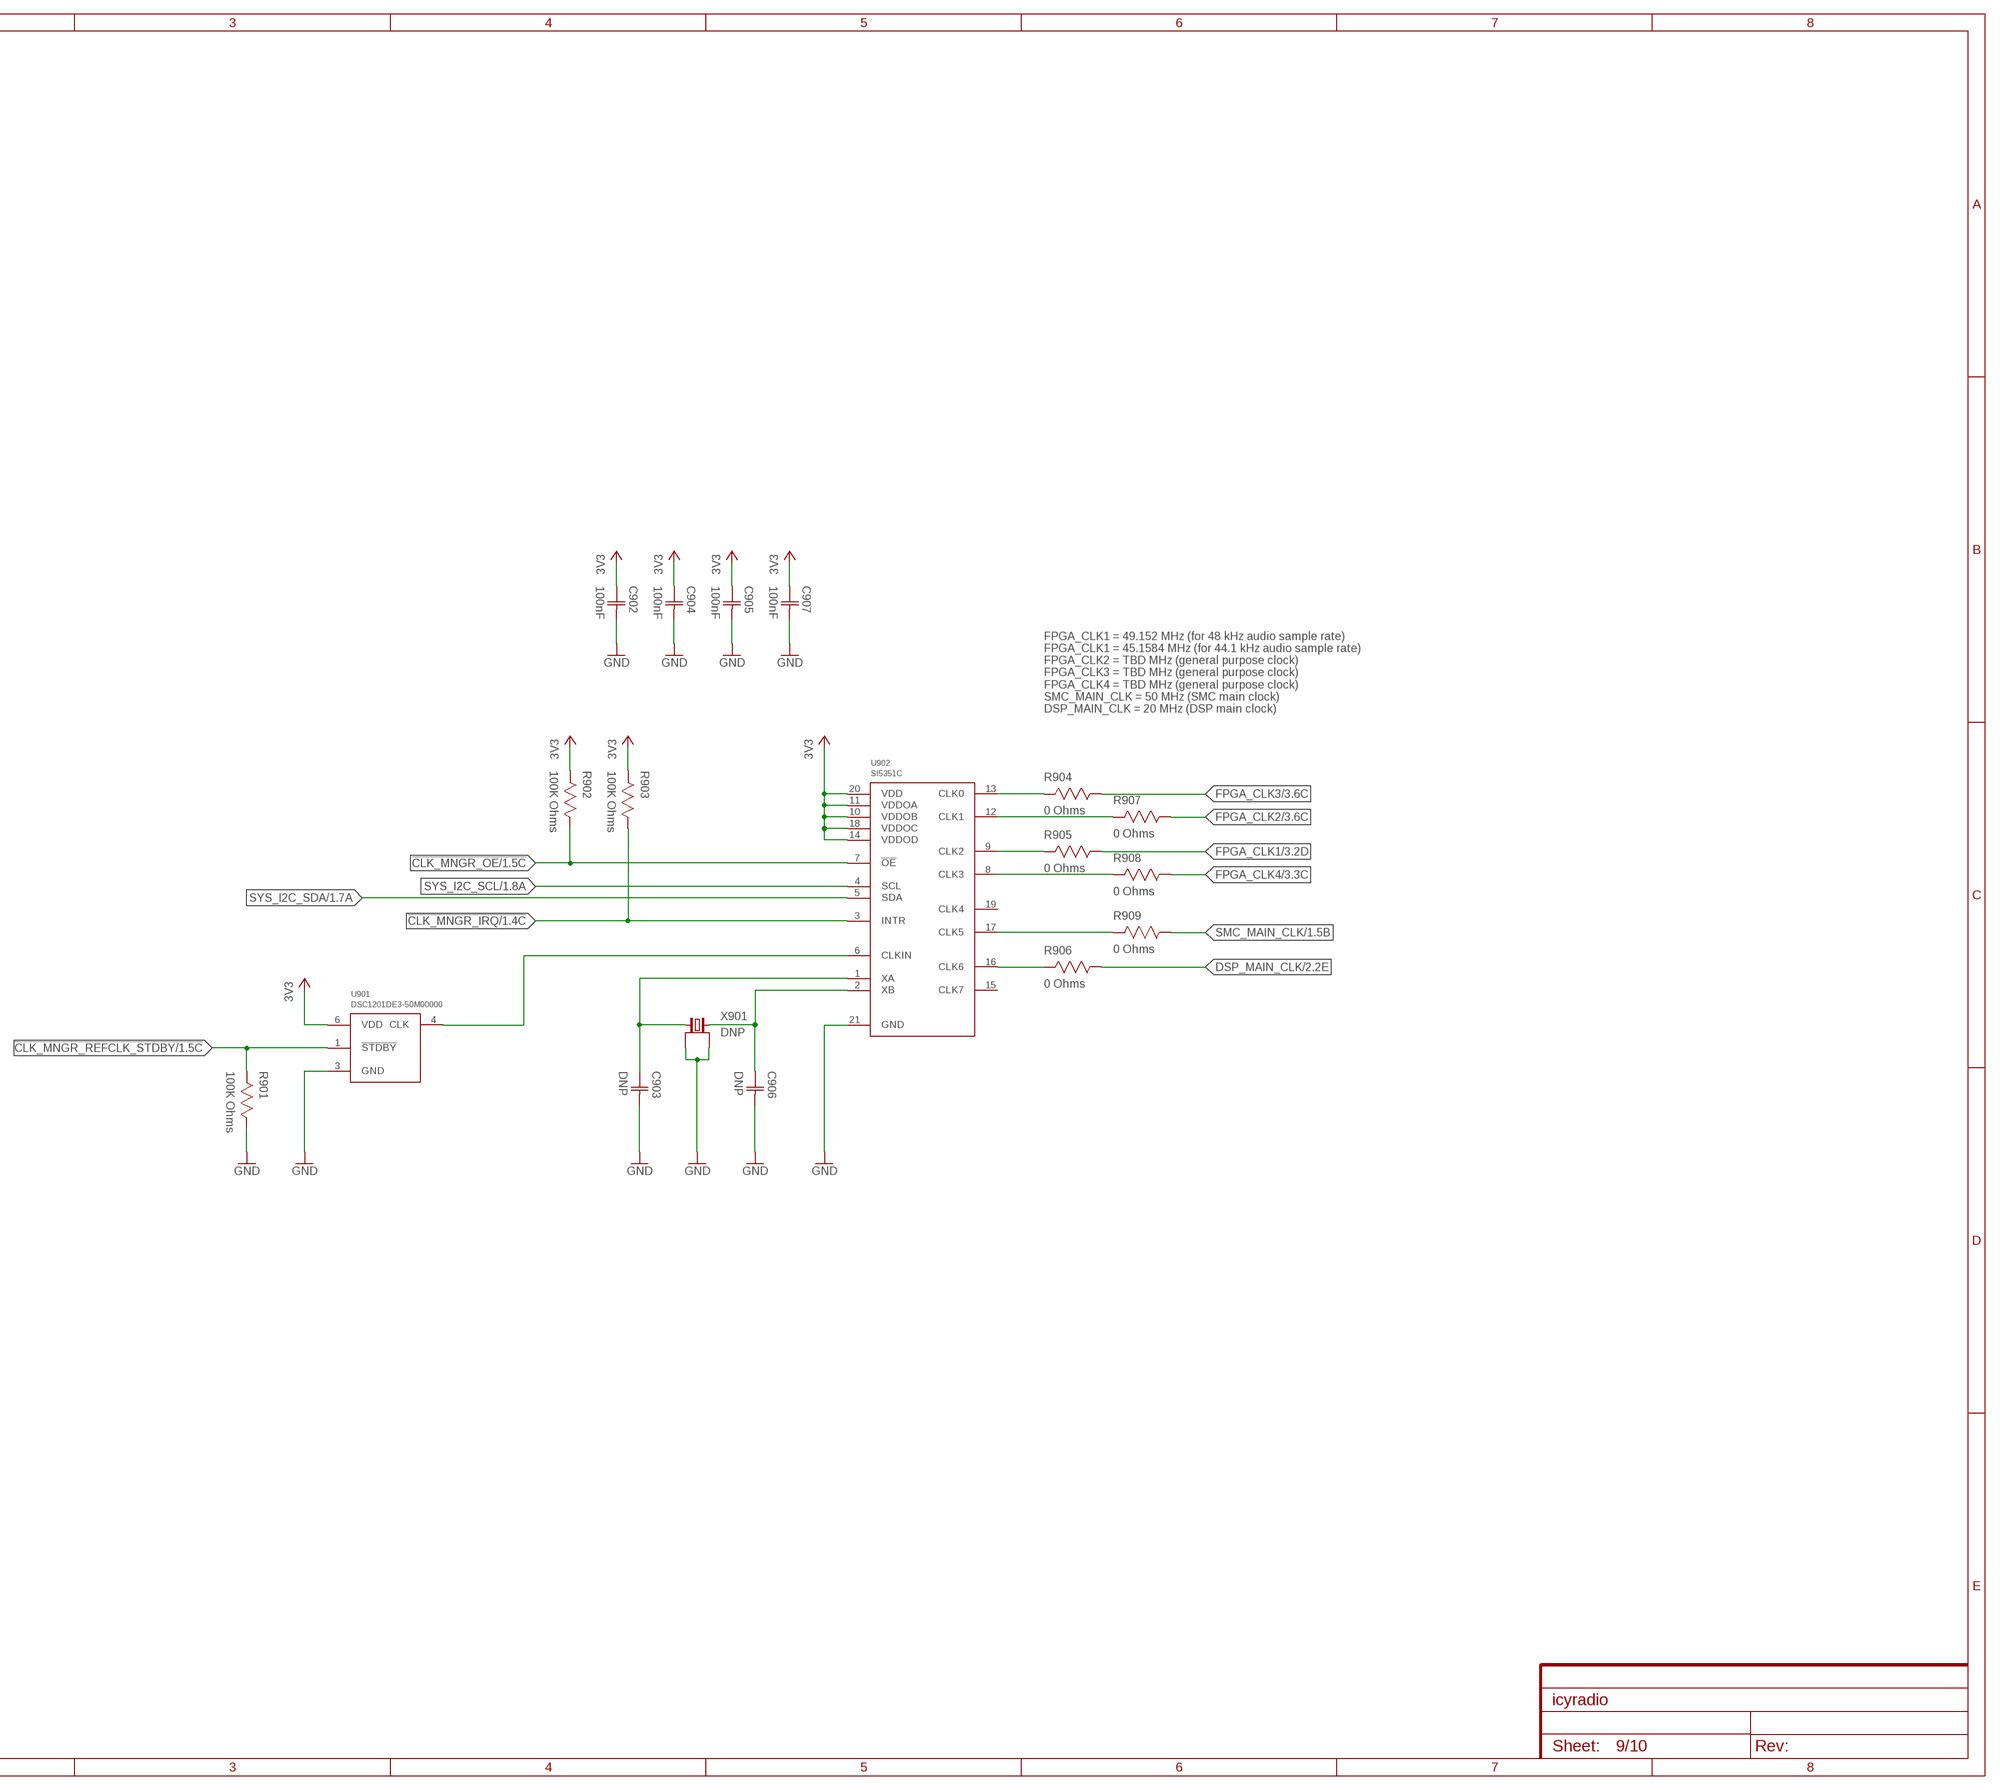
[diagram p17: schematic, sheet 9, part 2 of 2]
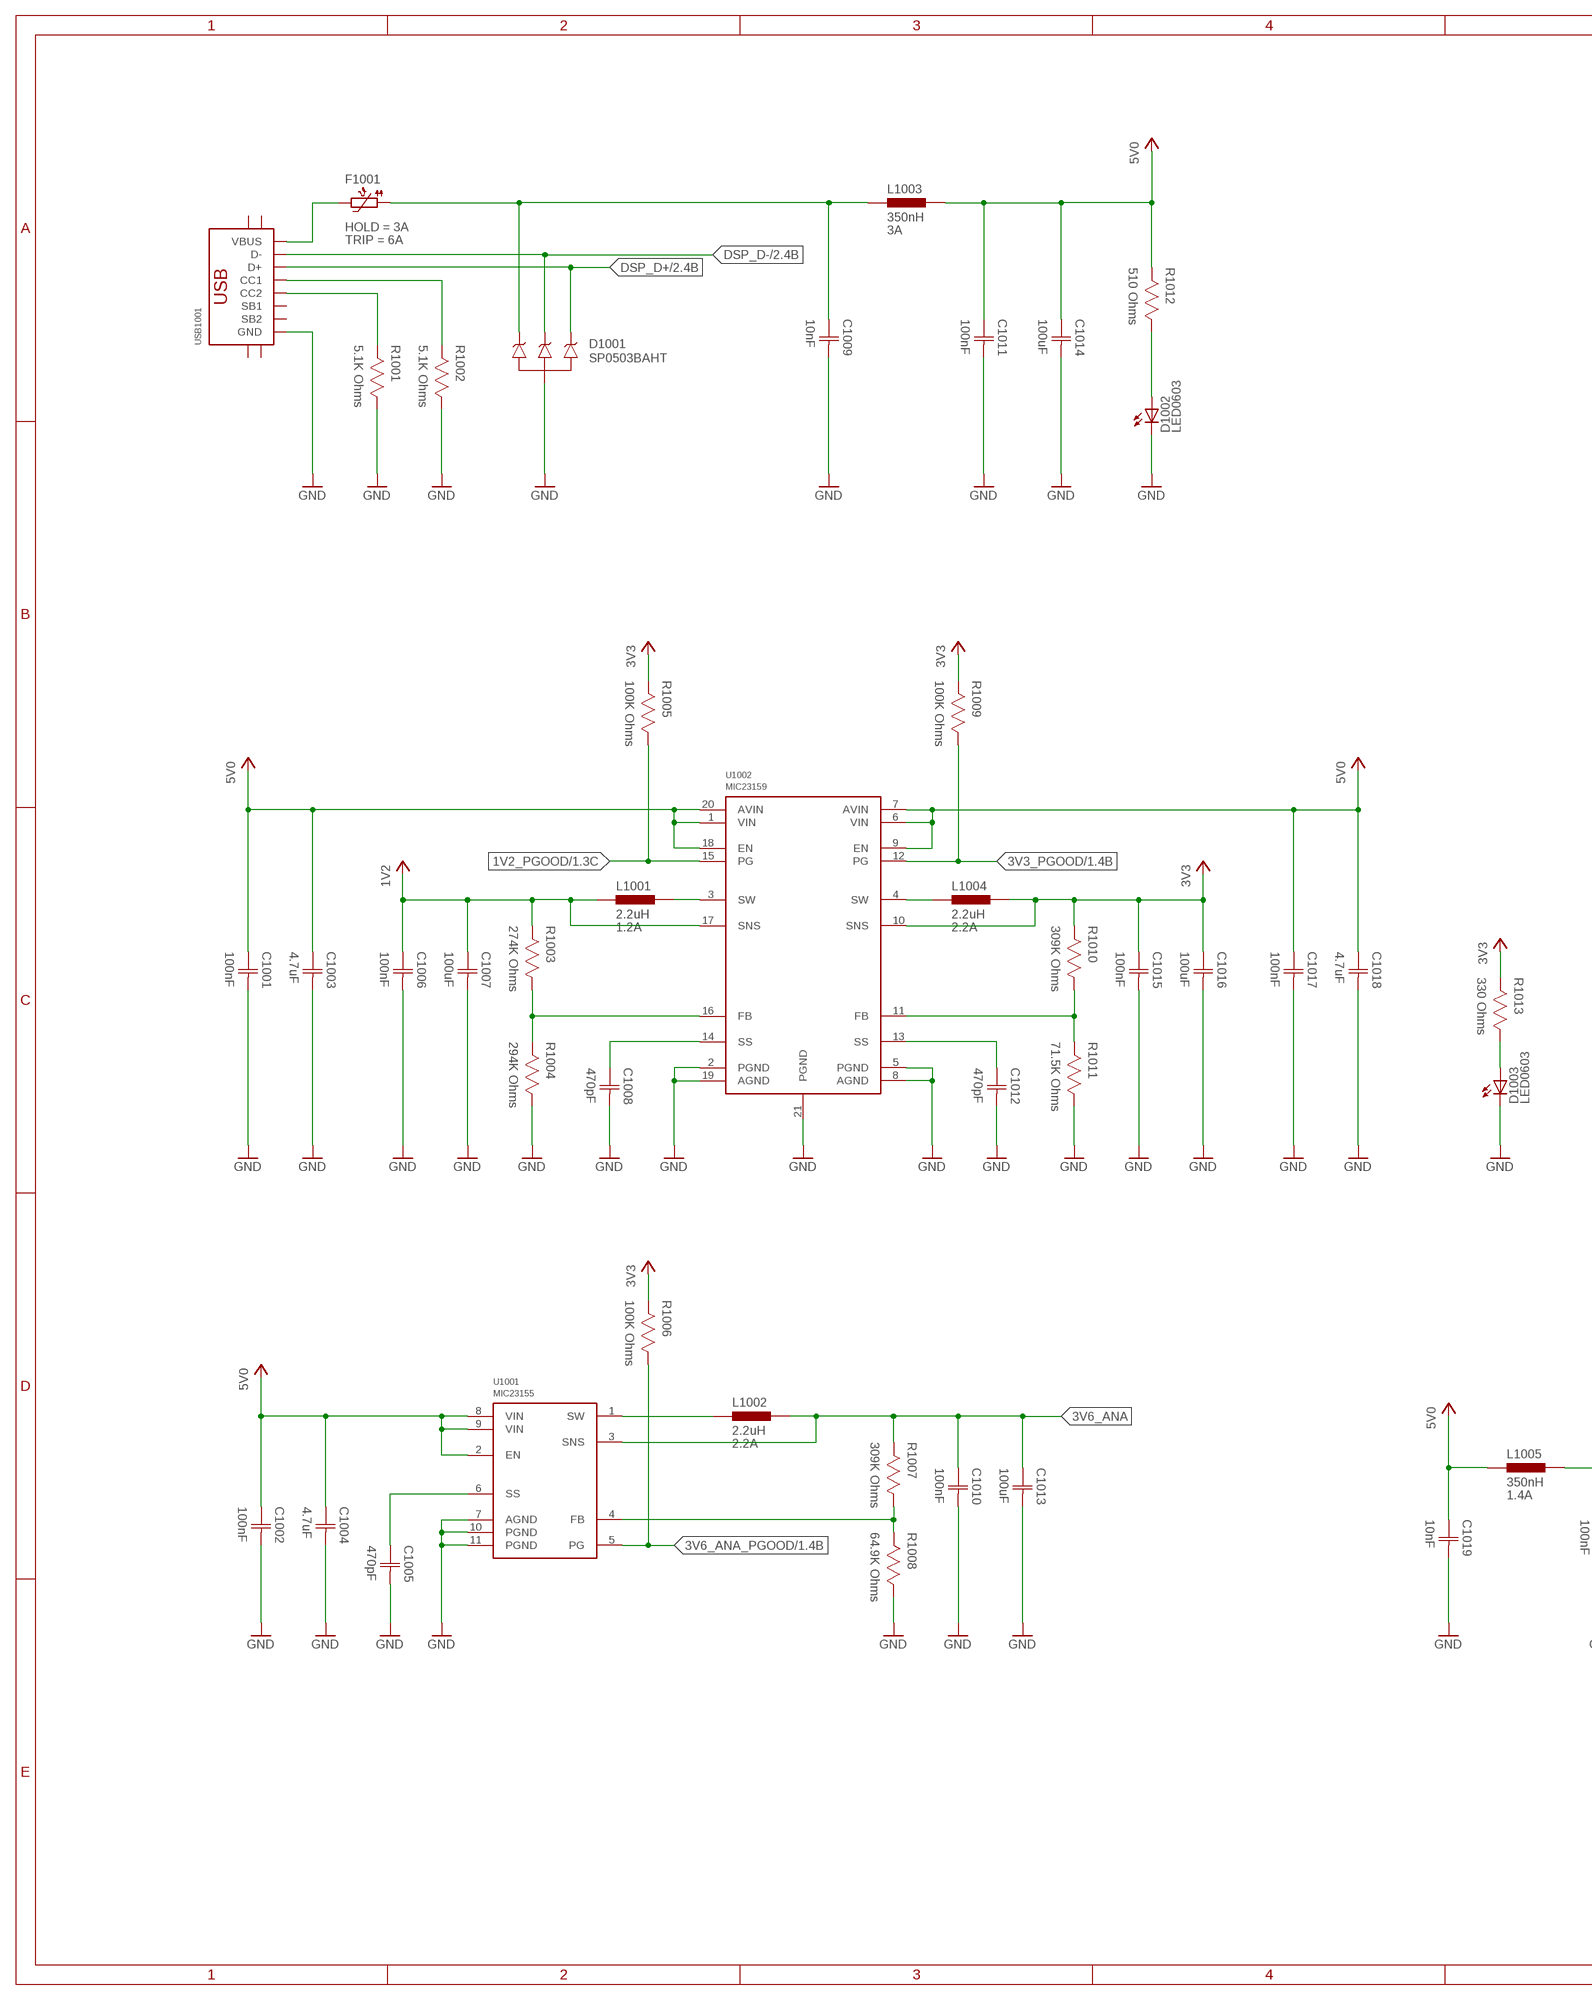
[diagram p18: schematic, sheet 10, part 1 of 2]
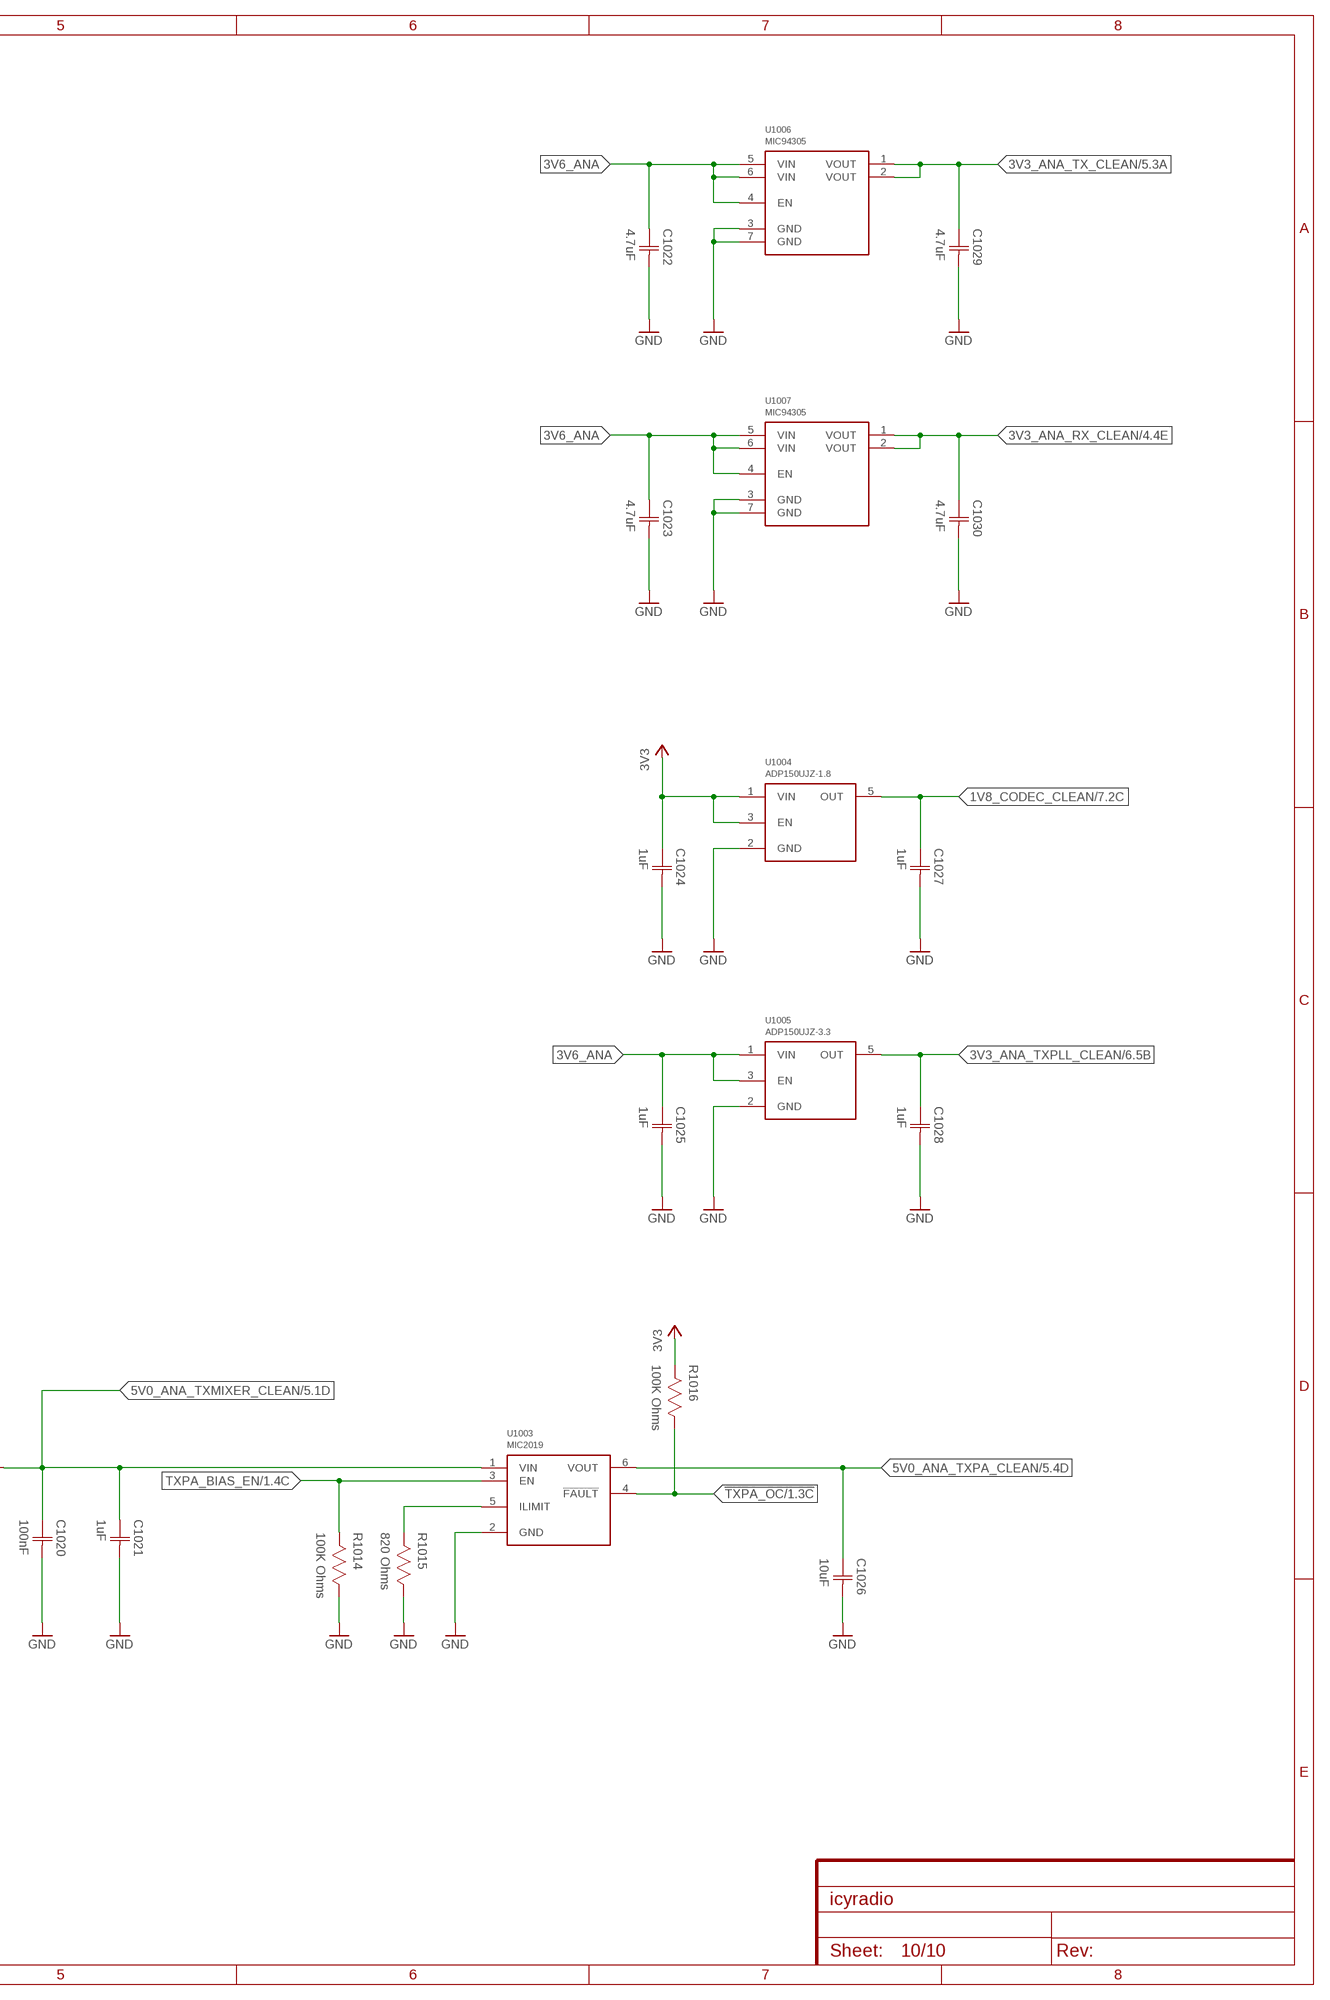
[diagram p19: schematic, sheet 10, part 2 of 2]

(export (version "E")
  (design (tool "Eeschema 10.0.6"))
  (components
    (comp (ref "C101")
      (value "100nF")
      (footprint "eagle-import:CAP0603")
      (libsource (lib "eagle-import") (part "CAPACITOR-0603"))
    )
    (comp (ref "C102")
      (value "100nF")
      (footprint "eagle-import:CAP0603")
      (libsource (lib "eagle-import") (part "CAPACITOR-0603"))
    )
    (comp (ref "C103")
      (value "100nF")
      (footprint "eagle-import:CAP0603")
      (libsource (lib "eagle-import") (part "CAPACITOR-0603"))
    )
    (comp (ref "C104")
      (value "100nF")
      (footprint "eagle-import:CAP0603")
      (libsource (lib "eagle-import") (part "CAPACITOR-0603"))
    )
    (comp (ref "C105")
      (value "100nF")
      (footprint "eagle-import:CAP0603")
      (libsource (lib "eagle-import") (part "CAPACITOR-0603"))
    )
    (comp (ref "C106")
      (value "100nF")
      (footprint "eagle-import:CAP0603")
      (libsource (lib "eagle-import") (part "CAPACITOR-0603"))
    )
    (comp (ref "C107")
      (value "100nF")
      (footprint "eagle-import:CAP0603")
      (libsource (lib "eagle-import") (part "CAPACITOR-0603"))
    )
    (comp (ref "C108")
      (value "100nF")
      (footprint "eagle-import:CAP0603")
      (libsource (lib "eagle-import") (part "CAPACITOR-0603"))
    )
    (comp (ref "C109")
      (value "100nF")
      (footprint "eagle-import:CAP0603")
      (libsource (lib "eagle-import") (part "CAPACITOR-0603"))
    )
    (comp (ref "C110")
      (value "100nF")
      (footprint "eagle-import:CAP0603")
      (libsource (lib "eagle-import") (part "CAPACITOR-0603"))
    )
    (comp (ref "C111")
      (value "1uF")
      (footprint "eagle-import:CAP0603")
      (libsource (lib "eagle-import") (part "CAPACITOR-0603"))
    )
    (comp (ref "D101")
      (value "LED0603")
      (footprint "eagle-import:0603")
      (libsource (lib "eagle-import") (part "LED0603"))
    )
    (comp (ref "R101")
      (value "4.7K Ohms")
      (footprint "eagle-import:RES0603")
      (libsource (lib "eagle-import") (part "RESISTOR-0603"))
    )
    (comp (ref "R102")
      (value "4.7K Ohms")
      (footprint "eagle-import:RES0603")
      (libsource (lib "eagle-import") (part "RESISTOR-0603"))
    )
    (comp (ref "R103")
      (value "330 Ohms")
      (footprint "eagle-import:RES0603")
      (libsource (lib "eagle-import") (part "RESISTOR-0603"))
    )
    (comp (ref "R104")
      (value "4.7K Ohms")
      (footprint "eagle-import:RES0603")
      (libsource (lib "eagle-import") (part "RESISTOR-0603"))
    )
    (comp (ref "R105")
      (value "4.7K Ohms")
      (footprint "eagle-import:RES0603")
      (libsource (lib "eagle-import") (part "RESISTOR-0603"))
    )
    (comp (ref "R106")
      (value "10K Ohms")
      (footprint "eagle-import:RES0603")
      (libsource (lib "eagle-import") (part "RESISTOR-0603"))
    )
    (comp (ref "TC101")
      (value "TC2050-IDC")
      (footprint "eagle-import:TC2050-IDC")
      (libsource (lib "eagle-import") (part "TC2050-IDC"))
    )
    (comp (ref "U101")
      (value "EFM32GG11B420F2048GL112")
      (footprint "eagle-import:BGA112")
      (libsource (lib "eagle-import") (part "EFM32GG11B4L11220F2048G"))
    )
    (comp (ref "X101")
      (value "32.768 kHz")
      (footprint "eagle-import:2-SMD-3215")
      (libsource (lib "eagle-import") (part "CRYSTAL2-SMD-3215"))
    )
    (comp (ref "C1001")
      (value "100nF")
      (footprint "eagle-import:CAP0603")
      (libsource (lib "eagle-import") (part "CAPACITOR-0603"))
    )
    (comp (ref "C1002")
      (value "100nF")
      (footprint "eagle-import:CAP0603")
      (libsource (lib "eagle-import") (part "CAPACITOR-0603"))
    )
    (comp (ref "C1003")
      (value "4.7uF")
      (footprint "eagle-import:CAP0603")
      (libsource (lib "eagle-import") (part "CAPACITOR-0603"))
    )
    (comp (ref "C1004")
      (value "4.7uF")
      (footprint "eagle-import:CAP0603")
      (libsource (lib "eagle-import") (part "CAPACITOR-0603"))
    )
    (comp (ref "C1005")
      (value "470pF")
      (footprint "eagle-import:CAP0603")
      (libsource (lib "eagle-import") (part "CAPACITOR-0603"))
    )
    (comp (ref "C1006")
      (value "100nF")
      (footprint "eagle-import:CAP0603")
      (libsource (lib "eagle-import") (part "CAPACITOR-0603"))
    )
    (comp (ref "C1007")
      (value "100uF")
      (footprint "eagle-import:CAP1206")
      (libsource (lib "eagle-import") (part "CAPACITOR-1206"))
    )
    (comp (ref "C1008")
      (value "470pF")
      (footprint "eagle-import:CAP0603")
      (libsource (lib "eagle-import") (part "CAPACITOR-0603"))
    )
    (comp (ref "C1009")
      (value "10nF")
      (footprint "eagle-import:CAP0603")
      (libsource (lib "eagle-import") (part "CAPACITOR-0603"))
    )
    (comp (ref "C1010")
      (value "100nF")
      (footprint "eagle-import:CAP0603")
      (libsource (lib "eagle-import") (part "CAPACITOR-0603"))
    )
    (comp (ref "C1011")
      (value "100nF")
      (footprint "eagle-import:CAP0603")
      (libsource (lib "eagle-import") (part "CAPACITOR-0603"))
    )
    (comp (ref "C1012")
      (value "470pF")
      (footprint "eagle-import:CAP0603")
      (libsource (lib "eagle-import") (part "CAPACITOR-0603"))
    )
    (comp (ref "C1013")
      (value "100uF")
      (footprint "eagle-import:CAP1206")
      (libsource (lib "eagle-import") (part "CAPACITOR-1206"))
    )
    (comp (ref "C1014")
      (value "100uF")
      (footprint "eagle-import:CAP1206")
      (libsource (lib "eagle-import") (part "CAPACITOR-1206"))
    )
    (comp (ref "C1015")
      (value "100nF")
      (footprint "eagle-import:CAP0603")
      (libsource (lib "eagle-import") (part "CAPACITOR-0603"))
    )
    (comp (ref "C1016")
      (value "100uF")
      (footprint "eagle-import:CAP1206")
      (libsource (lib "eagle-import") (part "CAPACITOR-1206"))
    )
    (comp (ref "C1017")
      (value "100nF")
      (footprint "eagle-import:CAP0603")
      (libsource (lib "eagle-import") (part "CAPACITOR-0603"))
    )
    (comp (ref "C1018")
      (value "4.7uF")
      (footprint "eagle-import:CAP0603")
      (libsource (lib "eagle-import") (part "CAPACITOR-0603"))
    )
    (comp (ref "C1019")
      (value "10nF")
      (footprint "eagle-import:CAP0603")
      (libsource (lib "eagle-import") (part "CAPACITOR-0603"))
    )
    (comp (ref "C1020")
      (value "100nF")
      (footprint "eagle-import:CAP0603")
      (libsource (lib "eagle-import") (part "CAPACITOR-0603"))
    )
    (comp (ref "C1021")
      (value "1uF")
      (footprint "eagle-import:CAP0603")
      (libsource (lib "eagle-import") (part "CAPACITOR-0603"))
    )
    (comp (ref "C1022")
      (value "4.7uF")
      (footprint "eagle-import:CAP0603")
      (libsource (lib "eagle-import") (part "CAPACITOR-0603"))
    )
    (comp (ref "C1023")
      (value "4.7uF")
      (footprint "eagle-import:CAP0603")
      (libsource (lib "eagle-import") (part "CAPACITOR-0603"))
    )
    (comp (ref "C1024")
      (value "1uF")
      (footprint "eagle-import:CAP0603")
      (libsource (lib "eagle-import") (part "CAPACITOR-0603"))
    )
    (comp (ref "C1025")
      (value "1uF")
      (footprint "eagle-import:CAP0603")
      (libsource (lib "eagle-import") (part "CAPACITOR-0603"))
    )
    (comp (ref "C1026")
      (value "10uF")
      (footprint "eagle-import:CAP0603")
      (libsource (lib "eagle-import") (part "CAPACITOR-0603"))
    )
    (comp (ref "C1027")
      (value "1uF")
      (footprint "eagle-import:CAP0603")
      (libsource (lib "eagle-import") (part "CAPACITOR-0603"))
    )
    (comp (ref "C1028")
      (value "1uF")
      (footprint "eagle-import:CAP0603")
      (libsource (lib "eagle-import") (part "CAPACITOR-0603"))
    )
    (comp (ref "C1029")
      (value "4.7uF")
      (footprint "eagle-import:CAP0603")
      (libsource (lib "eagle-import") (part "CAPACITOR-0603"))
    )
    (comp (ref "C1030")
      (value "4.7uF")
      (footprint "eagle-import:CAP0603")
      (libsource (lib "eagle-import") (part "CAPACITOR-0603"))
    )
    (comp (ref "D1001")
      (value "SP0503BAHT")
      (footprint "eagle-import:SOT143")
      (libsource (lib "eagle-import") (part "SP0503BAHT"))
    )
    (comp (ref "D1002")
      (value "LED0603")
      (footprint "eagle-import:0603")
      (libsource (lib "eagle-import") (part "LED0603"))
    )
    (comp (ref "D1003")
      (value "LED0603")
      (footprint "eagle-import:0603")
      (libsource (lib "eagle-import") (part "LED0603"))
    )
    (comp (ref "F1001")
      (value "PTC1206")
      (footprint "eagle-import:1206")
      (fields (field (name "HOLD") "3A") (field (name "TRIP") "6A"))
      (libsource (lib "eagle-import") (part "PTC1206"))
    )
    (comp (ref "L1001")
      (value "2.2uH")
      (footprint "eagle-import:IND0805")
      (fields (field (name "CURRENT") "1.2A"))
      (libsource (lib "eagle-import") (part "INDUCTOR-0805"))
    )
    (comp (ref "L1002")
      (value "2.2uH")
      (footprint "eagle-import:IND2520")
      (fields (field (name "CURRENT") "2.2A"))
      (libsource (lib "eagle-import") (part "INDUCTOR-2.5X2X1.2MM"))
    )
    (comp (ref "L1003")
      (value "350nH")
      (footprint "eagle-import:IND0805")
      (fields (field (name "CURRENT") "3A"))
      (libsource (lib "eagle-import") (part "INDUCTOR-0805"))
    )
    (comp (ref "L1004")
      (value "2.2uH")
      (footprint "eagle-import:IND2520")
      (fields (field (name "CURRENT") "2.2A"))
      (libsource (lib "eagle-import") (part "INDUCTOR-2.5X2X1.2MM"))
    )
    (comp (ref "L1005")
      (value "350nH")
      (footprint "eagle-import:IND0603")
      (fields (field (name "CURRENT") "1.4A"))
      (libsource (lib "eagle-import") (part "INDUCTOR-0603"))
    )
    (comp (ref "R1001")
      (value "5.1K Ohms")
      (footprint "eagle-import:RES0603")
      (libsource (lib "eagle-import") (part "RESISTOR-0603"))
    )
    (comp (ref "R1002")
      (value "5.1K Ohms")
      (footprint "eagle-import:RES0603")
      (libsource (lib "eagle-import") (part "RESISTOR-0603"))
    )
    (comp (ref "R1003")
      (value "274K Ohms")
      (footprint "eagle-import:RES0603")
      (libsource (lib "eagle-import") (part "RESISTOR-0603"))
    )
    (comp (ref "R1004")
      (value "294K Ohms")
      (footprint "eagle-import:RES0603")
      (libsource (lib "eagle-import") (part "RESISTOR-0603"))
    )
    (comp (ref "R1005")
      (value "100K Ohms")
      (footprint "eagle-import:RES0603")
      (libsource (lib "eagle-import") (part "RESISTOR-0603"))
    )
    (comp (ref "R1006")
      (value "100K Ohms")
      (footprint "eagle-import:RES0603")
      (libsource (lib "eagle-import") (part "RESISTOR-0603"))
    )
    (comp (ref "R1007")
      (value "309K Ohms")
      (footprint "eagle-import:RES0603")
      (libsource (lib "eagle-import") (part "RESISTOR-0603"))
    )
    (comp (ref "R1008")
      (value "64.9K Ohms")
      (footprint "eagle-import:RES0603")
      (libsource (lib "eagle-import") (part "RESISTOR-0603"))
    )
    (comp (ref "R1009")
      (value "100K Ohms")
      (footprint "eagle-import:RES0603")
      (libsource (lib "eagle-import") (part "RESISTOR-0603"))
    )
    (comp (ref "R1010")
      (value "309K Ohms")
      (footprint "eagle-import:RES0603")
      (libsource (lib "eagle-import") (part "RESISTOR-0603"))
    )
    (comp (ref "R1011")
      (value "71.5K Ohms")
      (footprint "eagle-import:RES0603")
      (libsource (lib "eagle-import") (part "RESISTOR-0603"))
    )
    (comp (ref "R1012")
      (value "510 Ohms")
      (footprint "eagle-import:RES0603")
      (libsource (lib "eagle-import") (part "RESISTOR-0603"))
    )
    (comp (ref "R1013")
      (value "330 Ohms")
      (footprint "eagle-import:RES0603")
      (libsource (lib "eagle-import") (part "RESISTOR-0603"))
    )
    (comp (ref "R1014")
      (value "100K Ohms")
      (footprint "eagle-import:RES0603")
      (libsource (lib "eagle-import") (part "RESISTOR-0603"))
    )
    (comp (ref "R1015")
      (value "820 Ohms")
      (footprint "eagle-import:RES0603")
      (libsource (lib "eagle-import") (part "RESISTOR-0603"))
    )
    (comp (ref "R1016")
      (value "100K Ohms")
      (footprint "eagle-import:RES0603")
      (libsource (lib "eagle-import") (part "RESISTOR-0603"))
    )
    (comp (ref "U1001")
      (value "MIC23155")
      (footprint "eagle-import:DFN10")
      (libsource (lib "eagle-import") (part "MIC23155"))
    )
    (comp (ref "U1002")
      (value "MIC23159")
      (footprint "eagle-import:VQFN20")
      (libsource (lib "eagle-import") (part "MIC23159"))
    )
    (comp (ref "U1003")
      (value "MIC2019")
      (footprint "eagle-import:SOT23-6")
      (libsource (lib "eagle-import") (part "MIC2091"))
    )
    (comp (ref "U1004")
      (value "ADP150UJZ-1.8")
      (footprint "eagle-import:SOT23-5")
      (libsource (lib "eagle-import") (part "ADP150UJZ-1.8"))
    )
    (comp (ref "U1005")
      (value "ADP150UJZ-3.3")
      (footprint "eagle-import:SOT23-5")
      (libsource (lib "eagle-import") (part "ADP150UJZ-3.3"))
    )
    (comp (ref "U1006")
      (value "MIC94305")
      (footprint "eagle-import:DFN6")
      (libsource (lib "eagle-import") (part "MIC94305"))
    )
    (comp (ref "U1007")
      (value "MIC94305")
      (footprint "eagle-import:DFN6")
      (libsource (lib "eagle-import") (part "MIC94305"))
    )
    (comp (ref "USB1001")
      (value "USB-C-16P-SMD-FLAT-SIDE-TYPE-2")
      (footprint "eagle-import:USB-C-16P-SMD-FLAT-SIDE-TYPE-2")
      (libsource (lib "eagle-import") (part "USB-C-16P-SMD-FLAT-SIDE-TYPE-2"))
    )
    (comp (ref "C501")
      (value "100nF")
      (footprint "eagle-import:CAP0603")
      (libsource (lib "eagle-import") (part "CAPACITOR-0603"))
    )
    (comp (ref "C502")
      (value "100nF")
      (footprint "eagle-import:CAP0603")
      (libsource (lib "eagle-import") (part "CAPACITOR-0603"))
    )
    (comp (ref "C503")
      (value "100nF")
      (footprint "eagle-import:CAP0603")
      (libsource (lib "eagle-import") (part "CAPACITOR-0603"))
    )
    (comp (ref "C504")
      (value "100nF")
      (footprint "eagle-import:CAP0603")
      (libsource (lib "eagle-import") (part "CAPACITOR-0603"))
    )
    (comp (ref "C505")
      (value "1uF")
      (footprint "eagle-import:CAP0603")
      (libsource (lib "eagle-import") (part "CAPACITOR-0603"))
    )
    (comp (ref "C506")
      (value "100nF")
      (footprint "eagle-import:CAP0603")
      (libsource (lib "eagle-import") (part "CAPACITOR-0603"))
    )
    (comp (ref "C507")
      (value "100nF")
      (footprint "eagle-import:CAP0603")
      (libsource (lib "eagle-import") (part "CAPACITOR-0603"))
    )
    (comp (ref "C508")
      (value "100nF")
      (footprint "eagle-import:CAP0603")
      (libsource (lib "eagle-import") (part "CAPACITOR-0603"))
    )
    (comp (ref "C509")
      (value "100nF")
      (footprint "eagle-import:CAP0603")
      (libsource (lib "eagle-import") (part "CAPACITOR-0603"))
    )
    (comp (ref "C510")
      (value "100nF")
      (footprint "eagle-import:CAP0603")
      (libsource (lib "eagle-import") (part "CAPACITOR-0603"))
    )
    (comp (ref "C511")
      (value "100nF")
      (footprint "eagle-import:CAP0603")
      (libsource (lib "eagle-import") (part "CAPACITOR-0603"))
    )
    (comp (ref "C512")
      (value "1.2nF")
      (footprint "eagle-import:CAP0603")
      (libsource (lib "eagle-import") (part "CAPACITOR-0603"))
    )
    (comp (ref "C513")
      (value "DNP")
      (footprint "eagle-import:CAP0603")
      (libsource (lib "eagle-import") (part "CAPACITOR-0603"))
    )
    (comp (ref "C514")
      (value "68pF")
      (footprint "eagle-import:CAP0603")
      (libsource (lib "eagle-import") (part "CAPACITOR-0603"))
    )
    (comp (ref "C515")
      (value "100nF")
      (footprint "eagle-import:CAP0603")
      (libsource (lib "eagle-import") (part "CAPACITOR-0603"))
    )
    (comp (ref "C516")
      (value "100nF")
      (footprint "eagle-import:CAP0603")
      (libsource (lib "eagle-import") (part "CAPACITOR-0603"))
    )
    (comp (ref "C517")
      (value "200pF")
      (footprint "eagle-import:CAP0603")
      (libsource (lib "eagle-import") (part "CAPACITOR-0603"))
    )
    (comp (ref "C518")
      (value "200pF")
      (footprint "eagle-import:CAP0603")
      (libsource (lib "eagle-import") (part "CAPACITOR-0603"))
    )
    (comp (ref "C519")
      (value "200pF")
      (footprint "eagle-import:CAP0603")
      (libsource (lib "eagle-import") (part "CAPACITOR-0603"))
    )
    (comp (ref "C520")
      (value "200pF")
      (footprint "eagle-import:CAP0603")
      (libsource (lib "eagle-import") (part "CAPACITOR-0603"))
    )
    (comp (ref "C521")
      (value "620pF")
      (footprint "eagle-import:CAP0603")
      (libsource (lib "eagle-import") (part "CAPACITOR-0603"))
    )
    (comp (ref "C522")
      (value "620pF")
      (footprint "eagle-import:CAP0603")
      (libsource (lib "eagle-import") (part "CAPACITOR-0603"))
    )
    (comp (ref "C523")
      (value "620pF")
      (footprint "eagle-import:CAP0603")
      (libsource (lib "eagle-import") (part "CAPACITOR-0603"))
    )
    (comp (ref "C524")
      (value "620pF")
      (footprint "eagle-import:CAP0603")
      (libsource (lib "eagle-import") (part "CAPACITOR-0603"))
    )
    (comp (ref "C525")
      (value "200pF")
      (footprint "eagle-import:CAP0603")
      (libsource (lib "eagle-import") (part "CAPACITOR-0603"))
    )
    (comp (ref "C526")
      (value "200pF")
      (footprint "eagle-import:CAP0603")
      (libsource (lib "eagle-import") (part "CAPACITOR-0603"))
    )
    (comp (ref "C527")
      (value "200pF")
      (footprint "eagle-import:CAP0603")
      (libsource (lib "eagle-import") (part "CAPACITOR-0603"))
    )
    (comp (ref "C528")
      (value "200pF")
      (footprint "eagle-import:CAP0603")
      (libsource (lib "eagle-import") (part "CAPACITOR-0603"))
    )
    (comp (ref "D501")
      (value "LED0603")
      (footprint "eagle-import:0603")
      (libsource (lib "eagle-import") (part "LED0603"))
    )
    (comp (ref "L501")
      (value "470nH")
      (footprint "eagle-import:IND0603")
      (libsource (lib "eagle-import") (part "INDUCTOR-0603"))
    )
    (comp (ref "L502")
      (value "1.3uH")
      (footprint "eagle-import:IND0603")
      (libsource (lib "eagle-import") (part "INDUCTOR-0603"))
    )
    (comp (ref "L503")
      (value "1.3uH")
      (footprint "eagle-import:IND0603")
      (libsource (lib "eagle-import") (part "INDUCTOR-0603"))
    )
    (comp (ref "L504")
      (value "1.3uH")
      (footprint "eagle-import:IND0603")
      (libsource (lib "eagle-import") (part "INDUCTOR-0603"))
    )
    (comp (ref "L505")
      (value "1.3uH")
      (footprint "eagle-import:IND0603")
      (libsource (lib "eagle-import") (part "INDUCTOR-0603"))
    )
    (comp (ref "L506")
      (value "1.3uH")
      (footprint "eagle-import:IND0603")
      (libsource (lib "eagle-import") (part "INDUCTOR-0603"))
    )
    (comp (ref "L507")
      (value "1.3uH")
      (footprint "eagle-import:IND0603")
      (libsource (lib "eagle-import") (part "INDUCTOR-0603"))
    )
    (comp (ref "L508")
      (value "1.3uH")
      (footprint "eagle-import:IND0603")
      (libsource (lib "eagle-import") (part "INDUCTOR-0603"))
    )
    (comp (ref "L509")
      (value "1.3uH")
      (footprint "eagle-import:IND0603")
      (libsource (lib "eagle-import") (part "INDUCTOR-0603"))
    )
    (comp (ref "R501")
      (value "100K Ohms")
      (footprint "eagle-import:RES0603")
      (libsource (lib "eagle-import") (part "RESISTOR-0603"))
    )
    (comp (ref "R502")
      (value "0 Ohms")
      (footprint "eagle-import:RES0603")
      (libsource (lib "eagle-import") (part "RESISTOR-0603"))
    )
    (comp (ref "R503")
      (value "100K Ohms")
      (footprint "eagle-import:RES0603")
      (libsource (lib "eagle-import") (part "RESISTOR-0603"))
    )
    (comp (ref "R504")
      (value "200 Ohms")
      (footprint "eagle-import:RES0603")
      (libsource (lib "eagle-import") (part "RESISTOR-0603"))
    )
    (comp (ref "R505")
      (value "100K Ohms")
      (footprint "eagle-import:RES0603")
      (libsource (lib "eagle-import") (part "RESISTOR-0603"))
    )
    (comp (ref "R506")
      (value "DNP")
      (footprint "eagle-import:RES0603")
      (libsource (lib "eagle-import") (part "RESISTOR-0603"))
    )
    (comp (ref "R507")
      (value "DNP")
      (footprint "eagle-import:RES0603")
      (libsource (lib "eagle-import") (part "RESISTOR-0603"))
    )
    (comp (ref "R508")
      (value "510 Ohms")
      (footprint "eagle-import:RES0603")
      (libsource (lib "eagle-import") (part "RESISTOR-0603"))
    )
    (comp (ref "R509")
      (value "50 Ohms")
      (footprint "eagle-import:RES0603")
      (libsource (lib "eagle-import") (part "RESISTOR-0603"))
    )
    (comp (ref "R510")
      (value "50 Ohms")
      (footprint "eagle-import:RES0603")
      (libsource (lib "eagle-import") (part "RESISTOR-0603"))
    )
    (comp (ref "R511")
      (value "50 Ohms")
      (footprint "eagle-import:RES0603")
      (libsource (lib "eagle-import") (part "RESISTOR-0603"))
    )
    (comp (ref "R512")
      (value "50 Ohms")
      (footprint "eagle-import:RES0603")
      (libsource (lib "eagle-import") (part "RESISTOR-0603"))
    )
    (comp (ref "R513")
      (value "10K Ohms")
      (footprint "eagle-import:RES0603")
      (libsource (lib "eagle-import") (part "RESISTOR-0603"))
    )
    (comp (ref "R514")
      (value "10K Ohms")
      (footprint "eagle-import:RES0603")
      (libsource (lib "eagle-import") (part "RESISTOR-0603"))
    )
    (comp (ref "R515")
      (value "100 Ohms")
      (footprint "eagle-import:RES0603")
      (libsource (lib "eagle-import") (part "RESISTOR-0603"))
    )
    (comp (ref "R516")
      (value "100 Ohms")
      (footprint "eagle-import:RES0603")
      (libsource (lib "eagle-import") (part "RESISTOR-0603"))
    )
    (comp (ref "RFCON501")
      (value "RFCON-SMA-EDGE")
      (footprint "eagle-import:SMA-EDGE")
      (libsource (lib "eagle-import") (part "RFCON-SMA-EDGE"))
    )
    (comp (ref "RFCON502")
      (value "RFCON-U.FL")
      (footprint "eagle-import:U.FL")
      (libsource (lib "eagle-import") (part "RFCON-U.FL"))
    )
    (comp (ref "U501")
      (value "ADL5385")
      (footprint "eagle-import:QFN24")
      (libsource (lib "eagle-import") (part "ADL5385"))
    )
    (comp (ref "U502")
      (value "AD9117")
      (footprint "eagle-import:QFN40")
      (libsource (lib "eagle-import") (part "AD9117"))
    )
    (comp (ref "U503")
      (value "ADL5601")
      (footprint "eagle-import:SOT89")
      (libsource (lib "eagle-import") (part "ADL5601"))
    )
    (comp (ref "C801")
      (value "100uF")
      (footprint "eagle-import:CAP1206")
      (libsource (lib "eagle-import") (part "CAPACITOR-1206"))
    )
    (comp (ref "Q801")
      (value "AO3400")
      (footprint "eagle-import:SOT23")
      (libsource (lib "eagle-import") (part "AO3400"))
    )
    (comp (ref "Q802")
      (value "AO3400")
      (footprint "eagle-import:SOT23")
      (libsource (lib "eagle-import") (part "AO3400"))
    )
    (comp (ref "R801")
      (value "22 Ohms")
      (footprint "eagle-import:RES0603")
      (libsource (lib "eagle-import") (part "RESISTOR-0603"))
    )
    (comp (ref "R802")
      (value "10K Ohms")
      (footprint "eagle-import:RES0603")
      (libsource (lib "eagle-import") (part "RESISTOR-0603"))
    )
    (comp (ref "R803")
      (value "0 Ohms")
      (footprint "eagle-import:RES0603")
      (libsource (lib "eagle-import") (part "RESISTOR-0603"))
    )
    (comp (ref "R804")
      (value "0 Ohms")
      (footprint "eagle-import:RES0603")
      (libsource (lib "eagle-import") (part "RESISTOR-0603"))
    )
    (comp (ref "R805")
      (value "100K Ohms")
      (footprint "eagle-import:RES0603")
      (libsource (lib "eagle-import") (part "RESISTOR-0603"))
    )
    (comp (ref "U801")
      (value "ER-TFT035-6")
      (footprint "eagle-import:FPC-50P")
      (libsource (lib "eagle-import") (part "ER-TFT035-6"))
    )
    (comp (ref "C601")
      (value "100nF")
      (footprint "eagle-import:CAP0603")
      (libsource (lib "eagle-import") (part "CAPACITOR-0603"))
    )
    (comp (ref "C602")
      (value "100nF")
      (footprint "eagle-import:CAP0603")
      (libsource (lib "eagle-import") (part "CAPACITOR-0603"))
    )
    (comp (ref "C603")
      (value "100nF")
      (footprint "eagle-import:CAP0603")
      (libsource (lib "eagle-import") (part "CAPACITOR-0603"))
    )
    (comp (ref "C604")
      (value "100nF")
      (footprint "eagle-import:CAP0603")
      (libsource (lib "eagle-import") (part "CAPACITOR-0603"))
    )
    (comp (ref "C605")
      (value "100nF")
      (footprint "eagle-import:CAP0603")
      (libsource (lib "eagle-import") (part "CAPACITOR-0603"))
    )
    (comp (ref "C606")
      (value "100nF")
      (footprint "eagle-import:CAP0603")
      (libsource (lib "eagle-import") (part "CAPACITOR-0603"))
    )
    (comp (ref "C607")
      (value "100nF")
      (footprint "eagle-import:CAP0603")
      (libsource (lib "eagle-import") (part "CAPACITOR-0603"))
    )
    (comp (ref "C608")
      (value "10pF")
      (footprint "eagle-import:CAP0603")
      (libsource (lib "eagle-import") (part "CAPACITOR-0603"))
    )
    (comp (ref "C609")
      (value "100nF")
      (footprint "eagle-import:CAP0603")
      (libsource (lib "eagle-import") (part "CAPACITOR-0603"))
    )
    (comp (ref "C610")
      (value "10pF")
      (footprint "eagle-import:CAP0603")
      (libsource (lib "eagle-import") (part "CAPACITOR-0603"))
    )
    (comp (ref "C611")
      (value "100nF")
      (footprint "eagle-import:CAP0603")
      (libsource (lib "eagle-import") (part "CAPACITOR-0603"))
    )
    (comp (ref "C612")
      (value "10pF")
      (footprint "eagle-import:CAP0603")
      (libsource (lib "eagle-import") (part "CAPACITOR-0603"))
    )
    (comp (ref "C613")
      (value "0.4pF")
      (footprint "eagle-import:CAP0603")
      (libsource (lib "eagle-import") (part "CAPACITOR-0603"))
    )
    (comp (ref "C614")
      (value "0.4pF")
      (footprint "eagle-import:CAP0603")
      (libsource (lib "eagle-import") (part "CAPACITOR-0603"))
    )
    (comp (ref "C615")
      (value "39nF")
      (footprint "eagle-import:CAP0603")
      (libsource (lib "eagle-import") (part "CAPACITOR-0603"))
    )
    (comp (ref "C616")
      (value "2.7nF")
      (footprint "eagle-import:CAP0603")
      (libsource (lib "eagle-import") (part "CAPACITOR-0603"))
    )
    (comp (ref "C617")
      (value "1.3pF")
      (footprint "eagle-import:CAP0603")
      (libsource (lib "eagle-import") (part "CAPACITOR-0603"))
    )
    (comp (ref "C618")
      (value "1.3pF")
      (footprint "eagle-import:CAP0603")
      (libsource (lib "eagle-import") (part "CAPACITOR-0603"))
    )
    (comp (ref "C619")
      (value "1.2nF")
      (footprint "eagle-import:CAP0603")
      (libsource (lib "eagle-import") (part "CAPACITOR-0603"))
    )
    (comp (ref "C620")
      (value "0.4pF")
      (footprint "eagle-import:CAP0603")
      (libsource (lib "eagle-import") (part "CAPACITOR-0603"))
    )
    (comp (ref "C621")
      (value "0.4pF")
      (footprint "eagle-import:CAP0603")
      (libsource (lib "eagle-import") (part "CAPACITOR-0603"))
    )
    (comp (ref "C622")
      (value "100nF")
      (footprint "eagle-import:CAP0603")
      (libsource (lib "eagle-import") (part "CAPACITOR-0603"))
    )
    (comp (ref "C623")
      (value "100nF")
      (footprint "eagle-import:CAP0603")
      (libsource (lib "eagle-import") (part "CAPACITOR-0603"))
    )
    (comp (ref "L601")
      (value "19nH")
      (footprint "eagle-import:IND0603")
      (libsource (lib "eagle-import") (part "INDUCTOR-0603"))
    )
    (comp (ref "L602")
      (value "19nH")
      (footprint "eagle-import:IND0603")
      (libsource (lib "eagle-import") (part "INDUCTOR-0603"))
    )
    (comp (ref "L603")
      (value "2.7nH")
      (footprint "eagle-import:IND0603")
      (libsource (lib "eagle-import") (part "INDUCTOR-0603"))
    )
    (comp (ref "L604")
      (value "2.7nH")
      (footprint "eagle-import:IND0603")
      (libsource (lib "eagle-import") (part "INDUCTOR-0603"))
    )
    (comp (ref "L605")
      (value "2.7nH")
      (footprint "eagle-import:IND0603")
      (libsource (lib "eagle-import") (part "INDUCTOR-0603"))
    )
    (comp (ref "L606")
      (value "2.7nH")
      (footprint "eagle-import:IND0603")
      (libsource (lib "eagle-import") (part "INDUCTOR-0603"))
    )
    (comp (ref "R601")
      (value "100K Ohms")
      (footprint "eagle-import:RES0603")
      (libsource (lib "eagle-import") (part "RESISTOR-0603"))
    )
    (comp (ref "R602")
      (value "100K Ohms")
      (footprint "eagle-import:RES0603")
      (libsource (lib "eagle-import") (part "RESISTOR-0603"))
    )
    (comp (ref "R603")
      (value "5.1K Ohms")
      (footprint "eagle-import:RES0603")
      (libsource (lib "eagle-import") (part "RESISTOR-0603"))
    )
    (comp (ref "R604")
      (value "100 Ohms")
      (footprint "eagle-import:RES0603")
      (libsource (lib "eagle-import") (part "RESISTOR-0603"))
    )
    (comp (ref "R605")
      (value "DNP")
      (footprint "eagle-import:RES0603")
      (libsource (lib "eagle-import") (part "RESISTOR-0603"))
    )
    (comp (ref "R606")
      (value "360 Ohms")
      (footprint "eagle-import:RES0603")
      (libsource (lib "eagle-import") (part "RESISTOR-0603"))
    )
    (comp (ref "R607")
      (value "680 Ohms")
      (footprint "eagle-import:RES0603")
      (libsource (lib "eagle-import") (part "RESISTOR-0603"))
    )
    (comp (ref "U601")
      (value "DSC1201DE3-50M00000")
      (footprint "eagle-import:VDFN6")
      (libsource (lib "eagle-import") (part "DSC1201DE3-50M00000"))
    )
    (comp (ref "U602")
      (value "ADF4351")
      (footprint "eagle-import:QFN32")
      (libsource (lib "eagle-import") (part "ADF4351"))
    )
    (comp (ref "C701")
      (value "100nF")
      (footprint "eagle-import:CAP0603")
      (libsource (lib "eagle-import") (part "CAPACITOR-0603"))
    )
    (comp (ref "C702")
      (value "100nF")
      (footprint "eagle-import:CAP0603")
      (libsource (lib "eagle-import") (part "CAPACITOR-0603"))
    )
    (comp (ref "C703")
      (value "100nF")
      (footprint "eagle-import:CAP0603")
      (libsource (lib "eagle-import") (part "CAPACITOR-0603"))
    )
    (comp (ref "C704")
      (value "100nF")
      (footprint "eagle-import:CAP0603")
      (libsource (lib "eagle-import") (part "CAPACITOR-0603"))
    )
    (comp (ref "C705")
      (value "100nF")
      (footprint "eagle-import:CAP0603")
      (libsource (lib "eagle-import") (part "CAPACITOR-0603"))
    )
    (comp (ref "C706")
      (value "100nF")
      (footprint "eagle-import:CAP0603")
      (libsource (lib "eagle-import") (part "CAPACITOR-0603"))
    )
    (comp (ref "C707")
      (value "4.7uF")
      (footprint "eagle-import:CAP0603")
      (libsource (lib "eagle-import") (part "CAPACITOR-0603"))
    )
    (comp (ref "C708")
      (value "10nF")
      (footprint "eagle-import:CAP0603")
      (libsource (lib "eagle-import") (part "CAPACITOR-0603"))
    )
    (comp (ref "C709")
      (value "10nF")
      (footprint "eagle-import:CAP0603")
      (libsource (lib "eagle-import") (part "CAPACITOR-0603"))
    )
    (comp (ref "C710")
      (value "4.7uF")
      (footprint "eagle-import:CAP0603")
      (libsource (lib "eagle-import") (part "CAPACITOR-0603"))
    )
    (comp (ref "C711")
      (value "4.7uF")
      (footprint "eagle-import:CAP0603")
      (libsource (lib "eagle-import") (part "CAPACITOR-0603"))
    )
    (comp (ref "C712")
      (value "1uF")
      (footprint "eagle-import:CAP0603")
      (libsource (lib "eagle-import") (part "CAPACITOR-0603"))
    )
    (comp (ref "C713")
      (value "1uF")
      (footprint "eagle-import:CAP0603")
      (libsource (lib "eagle-import") (part "CAPACITOR-0603"))
    )
    (comp (ref "C714")
      (value "1uF")
      (footprint "eagle-import:CAP0603")
      (libsource (lib "eagle-import") (part "CAPACITOR-0603"))
    )
    (comp (ref "C715")
      (value "1uF")
      (footprint "eagle-import:CAP0603")
      (libsource (lib "eagle-import") (part "CAPACITOR-0603"))
    )
    (comp (ref "C716")
      (value "22nF")
      (footprint "eagle-import:CAP0603")
      (libsource (lib "eagle-import") (part "CAPACITOR-0603"))
    )
    (comp (ref "C717")
      (value "22nF")
      (footprint "eagle-import:CAP0603")
      (libsource (lib "eagle-import") (part "CAPACITOR-0603"))
    )
    (comp (ref "C718")
      (value "1uF")
      (footprint "eagle-import:CAP0603")
      (libsource (lib "eagle-import") (part "CAPACITOR-0603"))
    )
    (comp (ref "C719")
      (value "1uF")
      (footprint "eagle-import:CAP0603")
      (libsource (lib "eagle-import") (part "CAPACITOR-0603"))
    )
    (comp (ref "C720")
      (value "100nF")
      (footprint "eagle-import:CAP0603")
      (libsource (lib "eagle-import") (part "CAPACITOR-0603"))
    )
    (comp (ref "C721")
      (value "220pF")
      (footprint "eagle-import:CAP0603")
      (libsource (lib "eagle-import") (part "CAPACITOR-0603"))
    )
    (comp (ref "C722")
      (value "220pF")
      (footprint "eagle-import:CAP0603")
      (libsource (lib "eagle-import") (part "CAPACITOR-0603"))
    )
    (comp (ref "C723")
      (value "220pF")
      (footprint "eagle-import:CAP0603")
      (libsource (lib "eagle-import") (part "CAPACITOR-0603"))
    )
    (comp (ref "C724")
      (value "220pF")
      (footprint "eagle-import:CAP0603")
      (libsource (lib "eagle-import") (part "CAPACITOR-0603"))
    )
    (comp (ref "C725")
      (value "220pF")
      (footprint "eagle-import:CAP0603")
      (libsource (lib "eagle-import") (part "CAPACITOR-0603"))
    )
    (comp (ref "C726")
      (value "220pF")
      (footprint "eagle-import:CAP0603")
      (libsource (lib "eagle-import") (part "CAPACITOR-0603"))
    )
    (comp (ref "D701")
      (value "SP0503BAHT")
      (footprint "eagle-import:SOT143")
      (libsource (lib "eagle-import") (part "SP0503BAHT"))
    )
    (comp (ref "D702")
      (value "LED0603")
      (footprint "eagle-import:0603")
      (libsource (lib "eagle-import") (part "LED0603"))
    )
    (comp (ref "J701")
      (value "TRSJACK")
      (footprint "eagle-import:3.5TRSJACK")
      (libsource (lib "eagle-import") (part "TRSJACK"))
    )
    (comp (ref "J702")
      (value "TRSJACK")
      (footprint "eagle-import:3.5TRSJACK")
      (libsource (lib "eagle-import") (part "TRSJACK"))
    )
    (comp (ref "J703")
      (value "TRSJACK")
      (footprint "eagle-import:3.5TRSJACK")
      (libsource (lib "eagle-import") (part "TRSJACK"))
    )
    (comp (ref "L701")
      (value "600 Ohms")
      (footprint "eagle-import:IND0603")
      (libsource (lib "eagle-import") (part "INDUCTOR-0603"))
    )
    (comp (ref "L702")
      (value "600 Ohms")
      (footprint "eagle-import:IND0603")
      (libsource (lib "eagle-import") (part "INDUCTOR-0603"))
    )
    (comp (ref "L703")
      (value "600 Ohms")
      (footprint "eagle-import:IND0603")
      (libsource (lib "eagle-import") (part "INDUCTOR-0603"))
    )
    (comp (ref "L704")
      (value "600 Ohms")
      (footprint "eagle-import:IND0603")
      (libsource (lib "eagle-import") (part "INDUCTOR-0603"))
    )
    (comp (ref "L705")
      (value "600 Ohms")
      (footprint "eagle-import:IND0603")
      (libsource (lib "eagle-import") (part "INDUCTOR-0603"))
    )
    (comp (ref "L706")
      (value "600 Ohms")
      (footprint "eagle-import:IND0603")
      (libsource (lib "eagle-import") (part "INDUCTOR-0603"))
    )
    (comp (ref "R701")
      (value "5.1K Ohms")
      (footprint "eagle-import:RES0603")
      (libsource (lib "eagle-import") (part "RESISTOR-0603"))
    )
    (comp (ref "R702")
      (value "5.1K Ohms")
      (footprint "eagle-import:RES0603")
      (libsource (lib "eagle-import") (part "RESISTOR-0603"))
    )
    (comp (ref "R703")
      (value "10K Ohms")
      (footprint "eagle-import:RES0603")
      (libsource (lib "eagle-import") (part "RESISTOR-0603"))
    )
    (comp (ref "R704")
      (value "510 Ohms")
      (footprint "eagle-import:RES0603")
      (libsource (lib "eagle-import") (part "RESISTOR-0603"))
    )
    (comp (ref "R705")
      (value "24K Ohms")
      (footprint "eagle-import:RES0603")
      (libsource (lib "eagle-import") (part "RESISTOR-0603"))
    )
    (comp (ref "R706")
      (value "47K Ohms")
      (footprint "eagle-import:RES0603")
      (libsource (lib "eagle-import") (part "RESISTOR-0603"))
    )
    (comp (ref "R707")
      (value "10K Ohms")
      (footprint "eagle-import:RES0603")
      (libsource (lib "eagle-import") (part "RESISTOR-0603"))
    )
    (comp (ref "R708")
      (value "100 Ohms")
      (footprint "eagle-import:RES0603")
      (libsource (lib "eagle-import") (part "RESISTOR-0603"))
    )
    (comp (ref "R709")
      (value "2.21K Ohms")
      (footprint "eagle-import:RES0603")
      (libsource (lib "eagle-import") (part "RESISTOR-0603"))
    )
    (comp (ref "R710")
      (value "4.7K Ohms")
      (footprint "eagle-import:RES0603")
      (libsource (lib "eagle-import") (part "RESISTOR-0603"))
    )
    (comp (ref "R711")
      (value "4.7K Ohms")
      (footprint "eagle-import:RES0603")
      (libsource (lib "eagle-import") (part "RESISTOR-0603"))
    )
    (comp (ref "R712")
      (value "10K Ohms")
      (footprint "eagle-import:RES0603")
      (libsource (lib "eagle-import") (part "RESISTOR-0603"))
    )
    (comp (ref "R713")
      (value "2.21K Ohms")
      (footprint "eagle-import:RES0603")
      (libsource (lib "eagle-import") (part "RESISTOR-0603"))
    )
    (comp (ref "R714")
      (value "4.7K Ohms")
      (footprint "eagle-import:RES0603")
      (libsource (lib "eagle-import") (part "RESISTOR-0603"))
    )
    (comp (ref "R715")
      (value "4.7K Ohms")
      (footprint "eagle-import:RES0603")
      (libsource (lib "eagle-import") (part "RESISTOR-0603"))
    )
    (comp (ref "R716")
      (value "100 Ohms")
      (footprint "eagle-import:RES0603")
      (libsource (lib "eagle-import") (part "RESISTOR-0603"))
    )
    (comp (ref "U701")
      (value "TSCS25A3X1NDGXZAX")
      (footprint "eagle-import:QFN40")
      (libsource (lib "eagle-import") (part "TSCS25A3X1NDGXZAX"))
    )
    (comp (ref "U702")
      (value "CP2615")
      (footprint "eagle-import:QFN32")
      (libsource (lib "eagle-import") (part "CP2615"))
    )
    (comp (ref "USB701")
      (value "USB-C-16P-SMD-FLAT-SIDE-TYPE-2")
      (footprint "eagle-import:USB-C-16P-SMD-FLAT-SIDE-TYPE-2")
      (libsource (lib "eagle-import") (part "USB-C-16P-SMD-FLAT-SIDE-TYPE-2"))
    )
    (comp (ref "C901")
      (value "100nF")
      (footprint "eagle-import:CAP0603")
      (libsource (lib "eagle-import") (part "CAPACITOR-0603"))
    )
    (comp (ref "C902")
      (value "100nF")
      (footprint "eagle-import:CAP0603")
      (libsource (lib "eagle-import") (part "CAPACITOR-0603"))
    )
    (comp (ref "C903")
      (value "DNP")
      (footprint "eagle-import:CAP0603")
      (libsource (lib "eagle-import") (part "CAPACITOR-0603"))
    )
    (comp (ref "C904")
      (value "100nF")
      (footprint "eagle-import:CAP0603")
      (libsource (lib "eagle-import") (part "CAPACITOR-0603"))
    )
    (comp (ref "C905")
      (value "100nF")
      (footprint "eagle-import:CAP0603")
      (libsource (lib "eagle-import") (part "CAPACITOR-0603"))
    )
    (comp (ref "C906")
      (value "DNP")
      (footprint "eagle-import:CAP0603")
      (libsource (lib "eagle-import") (part "CAPACITOR-0603"))
    )
    (comp (ref "C907")
      (value "100nF")
      (footprint "eagle-import:CAP0603")
      (libsource (lib "eagle-import") (part "CAPACITOR-0603"))
    )
    (comp (ref "R901")
      (value "100K Ohms")
      (footprint "eagle-import:RES0603")
      (libsource (lib "eagle-import") (part "RESISTOR-0603"))
    )
    (comp (ref "R902")
      (value "100K Ohms")
      (footprint "eagle-import:RES0603")
      (libsource (lib "eagle-import") (part "RESISTOR-0603"))
    )
    (comp (ref "R903")
      (value "100K Ohms")
      (footprint "eagle-import:RES0603")
      (libsource (lib "eagle-import") (part "RESISTOR-0603"))
    )
    (comp (ref "R904")
      (value "0 Ohms")
      (footprint "eagle-import:RES0603")
      (libsource (lib "eagle-import") (part "RESISTOR-0603"))
    )
    (comp (ref "R905")
      (value "0 Ohms")
      (footprint "eagle-import:RES0603")
      (libsource (lib "eagle-import") (part "RESISTOR-0603"))
    )
    (comp (ref "R906")
      (value "0 Ohms")
      (footprint "eagle-import:RES0603")
      (libsource (lib "eagle-import") (part "RESISTOR-0603"))
    )
    (comp (ref "R907")
      (value "0 Ohms")
      (footprint "eagle-import:RES0603")
      (libsource (lib "eagle-import") (part "RESISTOR-0603"))
    )
    (comp (ref "R908")
      (value "0 Ohms")
      (footprint "eagle-import:RES0603")
      (libsource (lib "eagle-import") (part "RESISTOR-0603"))
    )
    (comp (ref "R909")
      (value "0 Ohms")
      (footprint "eagle-import:RES0603")
      (libsource (lib "eagle-import") (part "RESISTOR-0603"))
    )
    (comp (ref "U901")
      (value "DSC1201DE3-50M00000")
      (footprint "eagle-import:VDFN6")
      (libsource (lib "eagle-import") (part "DSC1201DE3-50M00000"))
    )
    (comp (ref "U902")
      (value "SI5351C")
      (footprint "eagle-import:QFN20")
      (libsource (lib "eagle-import") (part "SI5351C"))
    )
    (comp (ref "X901")
      (value "DNP")
      (footprint "eagle-import:4-SMD-3225")
      (libsource (lib "eagle-import") (part "CRYSTAL_4P"))
    )
    (comp (ref "C201")
      (value "1uF")
      (footprint "eagle-import:CAP0603")
      (libsource (lib "eagle-import") (part "CAPACITOR-0603"))
    )
    (comp (ref "C202")
      (value "100nF")
      (footprint "eagle-import:CAP0603")
      (libsource (lib "eagle-import") (part "CAPACITOR-0603"))
    )
    (comp (ref "C203")
      (value "100nF")
      (footprint "eagle-import:CAP0603")
      (libsource (lib "eagle-import") (part "CAPACITOR-0603"))
    )
    (comp (ref "C204")
      (value "100nF")
      (footprint "eagle-import:CAP0603")
      (libsource (lib "eagle-import") (part "CAPACITOR-0603"))
    )
    (comp (ref "C205")
      (value "100nF")
      (footprint "eagle-import:CAP0603")
      (libsource (lib "eagle-import") (part "CAPACITOR-0603"))
    )
    (comp (ref "C206")
      (value "100nF")
      (footprint "eagle-import:CAP0603")
      (libsource (lib "eagle-import") (part "CAPACITOR-0603"))
    )
    (comp (ref "C207")
      (value "100nF")
      (footprint "eagle-import:CAP0603")
      (libsource (lib "eagle-import") (part "CAPACITOR-0603"))
    )
    (comp (ref "C208")
      (value "100nF")
      (footprint "eagle-import:CAP0603")
      (libsource (lib "eagle-import") (part "CAPACITOR-0603"))
    )
    (comp (ref "C209")
      (value "100nF")
      (footprint "eagle-import:CAP0603")
      (libsource (lib "eagle-import") (part "CAPACITOR-0603"))
    )
    (comp (ref "C210")
      (value "100nF")
      (footprint "eagle-import:CAP0603")
      (libsource (lib "eagle-import") (part "CAPACITOR-0603"))
    )
    (comp (ref "C211")
      (value "100nF")
      (footprint "eagle-import:CAP0603")
      (libsource (lib "eagle-import") (part "CAPACITOR-0603"))
    )
    (comp (ref "C212")
      (value "100nF")
      (footprint "eagle-import:CAP0603")
      (libsource (lib "eagle-import") (part "CAPACITOR-0603"))
    )
    (comp (ref "C213")
      (value "100nF")
      (footprint "eagle-import:CAP0603")
      (libsource (lib "eagle-import") (part "CAPACITOR-0603"))
    )
    (comp (ref "C214")
      (value "100nF")
      (footprint "eagle-import:CAP0603")
      (libsource (lib "eagle-import") (part "CAPACITOR-0603"))
    )
    (comp (ref "C215")
      (value "100nF")
      (footprint "eagle-import:CAP0603")
      (libsource (lib "eagle-import") (part "CAPACITOR-0603"))
    )
    (comp (ref "C216")
      (value "100nF")
      (footprint "eagle-import:CAP0603")
      (libsource (lib "eagle-import") (part "CAPACITOR-0603"))
    )
    (comp (ref "C217")
      (value "4.7uF")
      (footprint "eagle-import:CAP0603")
      (libsource (lib "eagle-import") (part "CAPACITOR-0603"))
    )
    (comp (ref "C218")
      (value "10pF")
      (footprint "eagle-import:CAP0603")
      (libsource (lib "eagle-import") (part "CAPACITOR-0603"))
    )
    (comp (ref "D201")
      (value "LED0603")
      (footprint "eagle-import:0603")
      (libsource (lib "eagle-import") (part "LED0603"))
    )
    (comp (ref "L201")
      (value "470 Ohms")
      (footprint "eagle-import:IND0603")
      (libsource (lib "eagle-import") (part "INDUCTOR-0603"))
    )
    (comp (ref "L202")
      (value "470 Ohms")
      (footprint "eagle-import:IND0603")
      (libsource (lib "eagle-import") (part "INDUCTOR-0603"))
    )
    (comp (ref "L203")
      (value "10uH")
      (footprint "eagle-import:IND0603")
      (libsource (lib "eagle-import") (part "INDUCTOR-0603"))
    )
    (comp (ref "R201")
      (value "5.62K Ohms")
      (footprint "eagle-import:RES0603")
      (libsource (lib "eagle-import") (part "RESISTOR-0603"))
    )
    (comp (ref "R202")
      (value "2.2 Ohms")
      (footprint "eagle-import:RES0603")
      (libsource (lib "eagle-import") (part "RESISTOR-0603"))
    )
    (comp (ref "R203")
      (value "330 Ohms")
      (footprint "eagle-import:RES0603")
      (libsource (lib "eagle-import") (part "RESISTOR-0603"))
    )
    (comp (ref "R204")
      (value "10K Ohms")
      (footprint "eagle-import:RES0603")
      (libsource (lib "eagle-import") (part "RESISTOR-0603"))
    )
    (comp (ref "SJ201")
      (value "SJS")
      (footprint "eagle-import:SJ_S")
      (libsource (lib "eagle-import") (part "SJS"))
    )
    (comp (ref "TC201")
      (value "TC2050-IDC")
      (footprint "eagle-import:TC2050-IDC")
      (libsource (lib "eagle-import") (part "TC2050-IDC"))
    )
    (comp (ref "TP1")
      (value "TESTPOINT-0.7MM")
      (footprint "eagle-import:PAD0.7MM")
      (libsource (lib "eagle-import") (part "TESTPOINT-0.7MM"))
    )
    (comp (ref "TP2")
      (value "TESTPOINT-0.7MM")
      (footprint "eagle-import:PAD0.7MM")
      (libsource (lib "eagle-import") (part "TESTPOINT-0.7MM"))
    )
    (comp (ref "U201")
      (value "ATSAMS70Q21B-C")
      (footprint "eagle-import:LFBGA144")
      (libsource (lib "eagle-import") (part "ATSAMCS70Q21B-"))
    )
    (comp (ref "C301")
      (value "100nF")
      (footprint "eagle-import:CAP0603")
      (libsource (lib "eagle-import") (part "CAPACITOR-0603"))
    )
    (comp (ref "C302")
      (value "100nF")
      (footprint "eagle-import:CAP0603")
      (libsource (lib "eagle-import") (part "CAPACITOR-0603"))
    )
    (comp (ref "C303")
      (value "100nF")
      (footprint "eagle-import:CAP0603")
      (libsource (lib "eagle-import") (part "CAPACITOR-0603"))
    )
    (comp (ref "C304")
      (value "100nF")
      (footprint "eagle-import:CAP0603")
      (libsource (lib "eagle-import") (part "CAPACITOR-0603"))
    )
    (comp (ref "C305")
      (value "100nF")
      (footprint "eagle-import:CAP0603")
      (libsource (lib "eagle-import") (part "CAPACITOR-0603"))
    )
    (comp (ref "C306")
      (value "100nF")
      (footprint "eagle-import:CAP0603")
      (libsource (lib "eagle-import") (part "CAPACITOR-0603"))
    )
    (comp (ref "C307")
      (value "100nF")
      (footprint "eagle-import:CAP0603")
      (libsource (lib "eagle-import") (part "CAPACITOR-0603"))
    )
    (comp (ref "C308")
      (value "100nF")
      (footprint "eagle-import:CAP0603")
      (libsource (lib "eagle-import") (part "CAPACITOR-0603"))
    )
    (comp (ref "C309")
      (value "100nF")
      (footprint "eagle-import:CAP0603")
      (libsource (lib "eagle-import") (part "CAPACITOR-0603"))
    )
    (comp (ref "C310")
      (value "100nF")
      (footprint "eagle-import:CAP0603")
      (libsource (lib "eagle-import") (part "CAPACITOR-0603"))
    )
    (comp (ref "C311")
      (value "100nF")
      (footprint "eagle-import:CAP0603")
      (libsource (lib "eagle-import") (part "CAPACITOR-0603"))
    )
    (comp (ref "C312")
      (value "100nF")
      (footprint "eagle-import:CAP0603")
      (libsource (lib "eagle-import") (part "CAPACITOR-0603"))
    )
    (comp (ref "C313")
      (value "100nF")
      (footprint "eagle-import:CAP0603")
      (libsource (lib "eagle-import") (part "CAPACITOR-0603"))
    )
    (comp (ref "C314")
      (value "100nF")
      (footprint "eagle-import:CAP0603")
      (libsource (lib "eagle-import") (part "CAPACITOR-0603"))
    )
    (comp (ref "C315")
      (value "100nF")
      (footprint "eagle-import:CAP0603")
      (libsource (lib "eagle-import") (part "CAPACITOR-0603"))
    )
    (comp (ref "C316")
      (value "100nF")
      (footprint "eagle-import:CAP0603")
      (libsource (lib "eagle-import") (part "CAPACITOR-0603"))
    )
    (comp (ref "C317")
      (value "100nF")
      (footprint "eagle-import:CAP0603")
      (libsource (lib "eagle-import") (part "CAPACITOR-0603"))
    )
    (comp (ref "C318")
      (value "100nF")
      (footprint "eagle-import:CAP0603")
      (libsource (lib "eagle-import") (part "CAPACITOR-0603"))
    )
    (comp (ref "C319")
      (value "100nF")
      (footprint "eagle-import:CAP0603")
      (libsource (lib "eagle-import") (part "CAPACITOR-0603"))
    )
    (comp (ref "CON301")
      (value "FPC-40P")
      (footprint "eagle-import:FPC-40P")
      (libsource (lib "eagle-import") (part "FPC-40P"))
    )
    (comp (ref "D301")
      (value "RGBLED")
      (footprint "eagle-import:5050")
      (libsource (lib "eagle-import") (part "RGBLED"))
    )
    (comp (ref "R301")
      (value "100K Ohms")
      (footprint "eagle-import:RES0603")
      (libsource (lib "eagle-import") (part "RESISTOR-0603"))
    )
    (comp (ref "R302")
      (value "330 Ohms")
      (footprint "eagle-import:RES0603")
      (libsource (lib "eagle-import") (part "RESISTOR-0603"))
    )
    (comp (ref "R303")
      (value "330 Ohms")
      (footprint "eagle-import:RES0603")
      (libsource (lib "eagle-import") (part "RESISTOR-0603"))
    )
    (comp (ref "R304")
      (value "330 Ohms")
      (footprint "eagle-import:RES0603")
      (libsource (lib "eagle-import") (part "RESISTOR-0603"))
    )
    (comp (ref "R305")
      (value "100K Ohms")
      (footprint "eagle-import:RES0603")
      (libsource (lib "eagle-import") (part "RESISTOR-0603"))
    )
    (comp (ref "TP3")
      (value "TESTPOINT-0.7MM")
      (footprint "eagle-import:PAD0.7MM")
      (libsource (lib "eagle-import") (part "TESTPOINT-0.7MM"))
    )
    (comp (ref "U301")
      (value "ICE40HX8K-CT256")
      (footprint "eagle-import:CABGA256")
      (libsource (lib "eagle-import") (part "ICE40HX8K-CT256"))
    )
    (comp (ref "U302")
      (value "SST26VF064B")
      (footprint "eagle-import:WSOIC8")
      (libsource (lib "eagle-import") (part "SST26VF064B"))
    )
    (comp (ref "C401")
      (value "100nF")
      (footprint "eagle-import:CAP0603")
      (libsource (lib "eagle-import") (part "CAPACITOR-0603"))
    )
    (comp (ref "C402")
      (value "100nF")
      (footprint "eagle-import:CAP0603")
      (libsource (lib "eagle-import") (part "CAPACITOR-0603"))
    )
    (comp (ref "C403")
      (value "100nF")
      (footprint "eagle-import:CAP0603")
      (libsource (lib "eagle-import") (part "CAPACITOR-0603"))
    )
    (comp (ref "C404")
      (value "100nF")
      (footprint "eagle-import:CAP0603")
      (libsource (lib "eagle-import") (part "CAPACITOR-0603"))
    )
    (comp (ref "C405")
      (value "100nF")
      (footprint "eagle-import:CAP0603")
      (libsource (lib "eagle-import") (part "CAPACITOR-0603"))
    )
    (comp (ref "C406")
      (value "100nF")
      (footprint "eagle-import:CAP0603")
      (libsource (lib "eagle-import") (part "CAPACITOR-0603"))
    )
    (comp (ref "C407")
      (value "100nF")
      (footprint "eagle-import:CAP0603")
      (libsource (lib "eagle-import") (part "CAPACITOR-0603"))
    )
    (comp (ref "C408")
      (value "100nF")
      (footprint "eagle-import:CAP0603")
      (libsource (lib "eagle-import") (part "CAPACITOR-0603"))
    )
    (comp (ref "C409")
      (value "100nF")
      (footprint "eagle-import:CAP0603")
      (libsource (lib "eagle-import") (part "CAPACITOR-0603"))
    )
    (comp (ref "C410")
      (value "DNP")
      (footprint "eagle-import:CAP0603")
      (libsource (lib "eagle-import") (part "CAPACITOR-0603"))
    )
    (comp (ref "C411")
      (value "100nF")
      (footprint "eagle-import:CAP0603")
      (libsource (lib "eagle-import") (part "CAPACITOR-0603"))
    )
    (comp (ref "C412")
      (value "DNP")
      (footprint "eagle-import:CAP0603")
      (libsource (lib "eagle-import") (part "CAPACITOR-0603"))
    )
    (comp (ref "C413")
      (value "100nF")
      (footprint "eagle-import:CAP0603")
      (libsource (lib "eagle-import") (part "CAPACITOR-0603"))
    )
    (comp (ref "C414")
      (value "2.2uF")
      (footprint "eagle-import:CAP0603")
      (libsource (lib "eagle-import") (part "CAPACITOR-0603"))
    )
    (comp (ref "C415")
      (value "100nF")
      (footprint "eagle-import:CAP0603")
      (libsource (lib "eagle-import") (part "CAPACITOR-0603"))
    )
    (comp (ref "C416")
      (value "12pF")
      (footprint "eagle-import:CAP0603")
      (libsource (lib "eagle-import") (part "CAPACITOR-0603"))
    )
    (comp (ref "C417")
      (value "12pF")
      (footprint "eagle-import:CAP0603")
      (libsource (lib "eagle-import") (part "CAPACITOR-0603"))
    )
    (comp (ref "C418")
      (value "100nF")
      (footprint "eagle-import:CAP0603")
      (libsource (lib "eagle-import") (part "CAPACITOR-0603"))
    )
    (comp (ref "C419")
      (value "12pF")
      (footprint "eagle-import:CAP0603")
      (libsource (lib "eagle-import") (part "CAPACITOR-0603"))
    )
    (comp (ref "C420")
      (value "1uF")
      (footprint "eagle-import:CAP0603")
      (libsource (lib "eagle-import") (part "CAPACITOR-0603"))
    )
    (comp (ref "C421")
      (value "100nF")
      (footprint "eagle-import:CAP0603")
      (libsource (lib "eagle-import") (part "CAPACITOR-0603"))
    )
    (comp (ref "C422")
      (value "100nF")
      (footprint "eagle-import:CAP0603")
      (libsource (lib "eagle-import") (part "CAPACITOR-0603"))
    )
    (comp (ref "C423")
      (value "6.8nF")
      (footprint "eagle-import:CAP0603")
      (libsource (lib "eagle-import") (part "CAPACITOR-0603"))
    )
    (comp (ref "C424")
      (value "27pF")
      (footprint "eagle-import:CAP0603")
      (libsource (lib "eagle-import") (part "CAPACITOR-0603"))
    )
    (comp (ref "C425")
      (value "2.2uF")
      (footprint "eagle-import:CAP0603")
      (libsource (lib "eagle-import") (part "CAPACITOR-0603"))
    )
    (comp (ref "C426")
      (value "100nF")
      (footprint "eagle-import:CAP0603")
      (libsource (lib "eagle-import") (part "CAPACITOR-0603"))
    )
    (comp (ref "C427")
      (value "27pF")
      (footprint "eagle-import:CAP0603")
      (libsource (lib "eagle-import") (part "CAPACITOR-0603"))
    )
    (comp (ref "C428")
      (value "330pF")
      (footprint "eagle-import:CAP0603")
      (libsource (lib "eagle-import") (part "CAPACITOR-0603"))
    )
    (comp (ref "C429")
      (value "100nF")
      (footprint "eagle-import:CAP0603")
      (libsource (lib "eagle-import") (part "CAPACITOR-0603"))
    )
    (comp (ref "C430")
      (value "100nF")
      (footprint "eagle-import:CAP0603")
      (libsource (lib "eagle-import") (part "CAPACITOR-0603"))
    )
    (comp (ref "C431")
      (value "100nF")
      (footprint "eagle-import:CAP0603")
      (libsource (lib "eagle-import") (part "CAPACITOR-0603"))
    )
    (comp (ref "C432")
      (value "330pF")
      (footprint "eagle-import:CAP0603")
      (libsource (lib "eagle-import") (part "CAPACITOR-0603"))
    )
    (comp (ref "C433")
      (value "10nF")
      (footprint "eagle-import:CAP0603")
      (libsource (lib "eagle-import") (part "CAPACITOR-0603"))
    )
    (comp (ref "D401")
      (value "BAV99")
      (footprint "eagle-import:SOT23")
      (libsource (lib "eagle-import") (part "BAV99"))
    )
    (comp (ref "L401")
      (value "150nH")
      (footprint "eagle-import:IND0603")
      (libsource (lib "eagle-import") (part "INDUCTOR-0603"))
    )
    (comp (ref "L402")
      (value "150nH")
      (footprint "eagle-import:IND0603")
      (libsource (lib "eagle-import") (part "INDUCTOR-0603"))
    )
    (comp (ref "L403")
      (value "8.2nH")
      (footprint "eagle-import:IND0603")
      (libsource (lib "eagle-import") (part "INDUCTOR-0603"))
    )
    (comp (ref "R401")
      (value "100K Ohms")
      (footprint "eagle-import:RES0603")
      (libsource (lib "eagle-import") (part "RESISTOR-0603"))
    )
    (comp (ref "R402")
      (value "0 Ohms")
      (footprint "eagle-import:RES0603")
      (libsource (lib "eagle-import") (part "RESISTOR-0603"))
    )
    (comp (ref "R403")
      (value "1K Ohms")
      (footprint "eagle-import:RES0603")
      (libsource (lib "eagle-import") (part "RESISTOR-0603"))
    )
    (comp (ref "R404")
      (value "220 Ohms")
      (footprint "eagle-import:RES0603")
      (libsource (lib "eagle-import") (part "RESISTOR-0603"))
    )
    (comp (ref "R405")
      (value "220 Ohms")
      (footprint "eagle-import:RES0603")
      (libsource (lib "eagle-import") (part "RESISTOR-0603"))
    )
    (comp (ref "R406")
      (value "25 Ohms")
      (footprint "eagle-import:RES0603")
      (libsource (lib "eagle-import") (part "RESISTOR-0603"))
    )
    (comp (ref "R407")
      (value "25 Ohms")
      (footprint "eagle-import:RES0603")
      (libsource (lib "eagle-import") (part "RESISTOR-0603"))
    )
    (comp (ref "R408")
      (value "4.7K Ohms")
      (footprint "eagle-import:RES0603")
      (libsource (lib "eagle-import") (part "RESISTOR-0603"))
    )
    (comp (ref "R409")
      (value "1.8K Ohms")
      (footprint "eagle-import:RES0603")
      (libsource (lib "eagle-import") (part "RESISTOR-0603"))
    )
    (comp (ref "R410")
      (value "4.7K Ohms")
      (footprint "eagle-import:RES0603")
      (libsource (lib "eagle-import") (part "RESISTOR-0603"))
    )
    (comp (ref "R411")
      (value "25 Ohms")
      (footprint "eagle-import:RES0603")
      (libsource (lib "eagle-import") (part "RESISTOR-0603"))
    )
    (comp (ref "R412")
      (value "25 Ohms")
      (footprint "eagle-import:RES0603")
      (libsource (lib "eagle-import") (part "RESISTOR-0603"))
    )
    (comp (ref "R413")
      (value "DNP")
      (footprint "eagle-import:RES0603")
      (libsource (lib "eagle-import") (part "RESISTOR-0603"))
    )
    (comp (ref "R414")
      (value "10K Ohms")
      (footprint "eagle-import:RES0603")
      (libsource (lib "eagle-import") (part "RESISTOR-0603"))
    )
    (comp (ref "R415")
      (value "220 Ohms")
      (footprint "eagle-import:RES0603")
      (libsource (lib "eagle-import") (part "RESISTOR-0603"))
    )
    (comp (ref "R416")
      (value "220 Ohms")
      (footprint "eagle-import:RES0603")
      (libsource (lib "eagle-import") (part "RESISTOR-0603"))
    )
    (comp (ref "RFCON401")
      (value "RFCON-SMA-EDGE")
      (footprint "eagle-import:SMA-EDGE")
      (libsource (lib "eagle-import") (part "RFCON-SMA-EDGE"))
    )
    (comp (ref "TRF401")
      (value "ETC1-1T-2TR")
      (footprint "eagle-import:TRF-SM-22")
      (libsource (lib "eagle-import") (part "ETC1-1T-2TR"))
    )
    (comp (ref "U401")
      (value "DSC1211DE3-C0017")
      (footprint "eagle-import:VDFN6")
      (libsource (lib "eagle-import") (part "DSC1211DE3-C0017"))
    )
    (comp (ref "U402")
      (value "LTC2206")
      (footprint "eagle-import:QFN48")
      (libsource (lib "eagle-import") (part "LTC2206"))
    )
    (comp (ref "U403")
      (value "R820T2")
      (footprint "eagle-import:QFN24")
      (libsource (lib "eagle-import") (part "R820T2"))
    )
    (comp (ref "X401")
      (value "DNP")
      (footprint "eagle-import:4-SMD-3225")
      (libsource (lib "eagle-import") (part "CRYSTAL_4P"))
    )
  )
  (nets
    (net (code "1") (name "1V2") (class "Default")
      (node (ref "C1006") (pin "1") (pinfunction "C1_1") (pintype "passive"))
      (node (ref "C1007") (pin "1") (pinfunction "C1_1") (pintype "passive"))
      (node (ref "C303") (pin "1") (pinfunction "C1_1") (pintype "passive"))
      (node (ref "C304") (pin "1") (pinfunction "C1_1") (pintype "passive"))
      (node (ref "C307") (pin "1") (pinfunction "C1_1") (pintype "passive"))
      (node (ref "C308") (pin "1") (pinfunction "C1_1") (pintype "passive"))
      (node (ref "C311") (pin "1") (pinfunction "C1_1") (pintype "passive"))
      (node (ref "C312") (pin "1") (pinfunction "C1_1") (pintype "passive"))
      (node (ref "C315") (pin "1") (pinfunction "C1_1") (pintype "passive"))
      (node (ref "C318") (pin "1") (pinfunction "C1_1") (pintype "passive"))
      (node (ref "L1001") (pin "1") (pinfunction "1_1") (pintype "passive"))
      (node (ref "R1003") (pin "2") (pinfunction "2_2") (pintype "passive"))
      (node (ref "U1002") (pin "17") (pinfunction "SNS_17") (pintype "bidirectional"))
      (node (ref "U301") (pin "A14") (pinfunction "VCC_A14") (pintype "power_in"))
      (node (ref "U301") (pin "E8") (pinfunction "VCCPLL1_E8") (pintype "power_in"))
      (node (ref "U301") (pin "F10") (pinfunction "VCC_F10") (pintype "power_in"))
      (node (ref "U301") (pin "F6") (pinfunction "VCC_F6") (pintype "power_in"))
      (node (ref "U301") (pin "K10") (pinfunction "VCC_K10") (pintype "power_in"))
      (node (ref "U301") (pin "K6") (pinfunction "VCC_K6") (pintype "power_in"))
      (node (ref "U301") (pin "L2") (pinfunction "VCC_L2") (pintype "power_in"))
      (node (ref "U301") (pin "L8") (pinfunction "VCCPLL0_L8") (pintype "power_in"))
    )
    (net (code "2") (name "1V2_PGOOD") (class "Default")
      (node (ref "R1005") (pin "1") (pinfunction "1_1") (pintype "passive"))
      (node (ref "U1002") (pin "15") (pinfunction "PG_15") (pintype "bidirectional"))
      (node (ref "U101") (pin "C11") (pinfunction "PC11_C11") (pintype "bidirectional"))
    )
    (net (code "3") (name "1V8_CODEC_CLEAN") (class "Default")
      (node (ref "C1027") (pin "1") (pinfunction "C1_1") (pintype "passive"))
      (node (ref "C702") (pin "1") (pinfunction "C1_1") (pintype "passive"))
      (node (ref "C704") (pin "1") (pinfunction "C1_1") (pintype "passive"))
      (node (ref "C705") (pin "1") (pinfunction "C1_1") (pintype "passive"))
      (node (ref "U1004") (pin "5") (pinfunction "OUT_5") (pintype "bidirectional"))
      (node (ref "U701") (pin "17") (pinfunction "DVDD_CORE_17") (pintype "bidirectional"))
      (node (ref "U701") (pin "3") (pinfunction "AVDD_3") (pintype "bidirectional"))
      (node (ref "U701") (pin "33") (pinfunction "AVDD_33") (pintype "bidirectional"))
      (node (ref "U701") (pin "37") (pinfunction "CPVDD_37") (pintype "bidirectional"))
    )
    (net (code "4") (name "3V3") (class "Default")
      (node (ref "C101") (pin "1") (pinfunction "C1_1") (pintype "passive"))
      (node (ref "C1015") (pin "1") (pinfunction "C1_1") (pintype "passive"))
      (node (ref "C1016") (pin "1") (pinfunction "C1_1") (pintype "passive"))
      (node (ref "C102") (pin "1") (pinfunction "C1_1") (pintype "passive"))
      (node (ref "C1024") (pin "1") (pinfunction "C1_1") (pintype "passive"))
      (node (ref "C103") (pin "1") (pinfunction "C1_1") (pintype "passive"))
      (node (ref "C104") (pin "1") (pinfunction "C1_1") (pintype "passive"))
      (node (ref "C105") (pin "1") (pinfunction "C1_1") (pintype "passive"))
      (node (ref "C106") (pin "1") (pinfunction "C1_1") (pintype "passive"))
      (node (ref "C107") (pin "1") (pinfunction "C1_1") (pintype "passive"))
      (node (ref "C108") (pin "1") (pinfunction "C1_1") (pintype "passive"))
      (node (ref "C109") (pin "1") (pinfunction "C1_1") (pintype "passive"))
      (node (ref "C110") (pin "1") (pinfunction "C1_1") (pintype "passive"))
      (node (ref "C203") (pin "1") (pinfunction "C1_1") (pintype "passive"))
      (node (ref "C205") (pin "1") (pinfunction "C1_1") (pintype "passive"))
      (node (ref "C207") (pin "1") (pinfunction "C1_1") (pintype "passive"))
      (node (ref "C209") (pin "1") (pinfunction "C1_1") (pintype "passive"))
      (node (ref "C211") (pin "1") (pinfunction "C1_1") (pintype "passive"))
      (node (ref "C213") (pin "1") (pinfunction "C1_1") (pintype "passive"))
      (node (ref "C214") (pin "1") (pinfunction "C1_1") (pintype "passive"))
      (node (ref "C301") (pin "1") (pinfunction "C1_1") (pintype "passive"))
      (node (ref "C302") (pin "1") (pinfunction "C1_1") (pintype "passive"))
      (node (ref "C305") (pin "1") (pinfunction "C1_1") (pintype "passive"))
      (node (ref "C306") (pin "1") (pinfunction "C1_1") (pintype "passive"))
      (node (ref "C309") (pin "1") (pinfunction "C1_1") (pintype "passive"))
      (node (ref "C310") (pin "1") (pinfunction "C1_1") (pintype "passive"))
      (node (ref "C313") (pin "1") (pinfunction "C1_1") (pintype "passive"))
      (node (ref "C314") (pin "1") (pinfunction "C1_1") (pintype "passive"))
      (node (ref "C316") (pin "1") (pinfunction "C1_1") (pintype "passive"))
      (node (ref "C317") (pin "1") (pinfunction "C1_1") (pintype "passive"))
      (node (ref "C319") (pin "1") (pinfunction "C1_1") (pintype "passive"))
      (node (ref "C403") (pin "1") (pinfunction "C1_1") (pintype "passive"))
      (node (ref "C405") (pin "1") (pinfunction "C1_1") (pintype "passive"))
      (node (ref "C407") (pin "1") (pinfunction "C1_1") (pintype "passive"))
      (node (ref "C409") (pin "1") (pinfunction "C1_1") (pintype "passive"))
      (node (ref "C504") (pin "1") (pinfunction "C1_1") (pintype "passive"))
      (node (ref "C506") (pin "1") (pinfunction "C1_1") (pintype "passive"))
      (node (ref "C605") (pin "1") (pinfunction "C1_1") (pintype "passive"))
      (node (ref "C701") (pin "1") (pinfunction "C1_1") (pintype "passive"))
      (node (ref "C703") (pin "1") (pinfunction "C1_1") (pintype "passive"))
      (node (ref "C718") (pin "1") (pinfunction "C1_1") (pintype "passive"))
      (node (ref "C720") (pin "1") (pinfunction "C1_1") (pintype "passive"))
      (node (ref "C801") (pin "1") (pinfunction "C1_1") (pintype "passive"))
      (node (ref "C901") (pin "1") (pinfunction "C1_1") (pintype "passive"))
      (node (ref "C902") (pin "1") (pinfunction "C1_1") (pintype "passive"))
      (node (ref "C904") (pin "1") (pinfunction "C1_1") (pintype "passive"))
      (node (ref "C905") (pin "1") (pinfunction "C1_1") (pintype "passive"))
      (node (ref "C907") (pin "1") (pinfunction "C1_1") (pintype "passive"))
      (node (ref "CON301") (pin "1") (pinfunction "S_1") (pintype "passive"))
      (node (ref "CON301") (pin "20") (pinfunction "S_20") (pintype "passive"))
      (node (ref "CON301") (pin "21") (pinfunction "S_21") (pintype "passive"))
      (node (ref "CON301") (pin "40") (pinfunction "S_40") (pintype "passive"))
      (node (ref "L1004") (pin "2") (pinfunction "2_2") (pintype "passive"))
      (node (ref "R1005") (pin "2") (pinfunction "2_2") (pintype "passive"))
      (node (ref "R1006") (pin "2") (pinfunction "2_2") (pintype "passive"))
      (node (ref "R1009") (pin "2") (pinfunction "2_2") (pintype "passive"))
      (node (ref "R101") (pin "2") (pinfunction "2_2") (pintype "passive"))
      (node (ref "R1010") (pin "2") (pinfunction "2_2") (pintype "passive"))
      (node (ref "R1013") (pin "2") (pinfunction "2_2") (pintype "passive"))
      (node (ref "R1016") (pin "2") (pinfunction "2_2") (pintype "passive"))
      (node (ref "R102") (pin "2") (pinfunction "2_2") (pintype "passive"))
      (node (ref "R104") (pin "2") (pinfunction "2_2") (pintype "passive"))
      (node (ref "R105") (pin "2") (pinfunction "2_2") (pintype "passive"))
      (node (ref "R106") (pin "2") (pinfunction "2_2") (pintype "passive"))
      (node (ref "R202") (pin "2") (pinfunction "2_2") (pintype "passive"))
      (node (ref "R204") (pin "2") (pinfunction "2_2") (pintype "passive"))
      (node (ref "R305") (pin "2") (pinfunction "2_2") (pintype "passive"))
      (node (ref "R401") (pin "2") (pinfunction "2_2") (pintype "passive"))
      (node (ref "R408") (pin "2") (pinfunction "2_2") (pintype "passive"))
      (node (ref "R410") (pin "2") (pinfunction "2_2") (pintype "passive"))
      (node (ref "R503") (pin "2") (pinfunction "2_2") (pintype "passive"))
      (node (ref "R505") (pin "2") (pinfunction "2_2") (pintype "passive"))
      (node (ref "R703") (pin "2") (pinfunction "2_2") (pintype "passive"))
      (node (ref "R707") (pin "2") (pinfunction "2_2") (pintype "passive"))
      (node (ref "R712") (pin "2") (pinfunction "2_2") (pintype "passive"))
      (node (ref "R805") (pin "2") (pinfunction "2_2") (pintype "passive"))
      (node (ref "R902") (pin "2") (pinfunction "2_2") (pintype "passive"))
      (node (ref "R903") (pin "2") (pinfunction "2_2") (pintype "passive"))
      (node (ref "TC101") (pin "1") (pinfunction "S_1") (pintype "passive"))
      (node (ref "TC201") (pin "1") (pinfunction "S_1") (pintype "passive"))
      (node (ref "U1002") (pin "10") (pinfunction "SNS_10") (pintype "bidirectional"))
      (node (ref "U1004") (pin "1") (pinfunction "VIN_1") (pintype "bidirectional"))
      (node (ref "U1004") (pin "3") (pinfunction "EN_3") (pintype "bidirectional"))
      (node (ref "U101") (pin "D5") (pinfunction "IOVDD1_D5") (pintype "bidirectional"))
      (node (ref "U101") (pin "D7") (pinfunction "IOVDD0_D7") (pintype "bidirectional"))
      (node (ref "U101") (pin "F8") (pinfunction "DVDD_F8") (pintype "bidirectional"))
      (node (ref "U101") (pin "G4") (pinfunction "IOVDD2_G4") (pintype "bidirectional"))
      (node (ref "U101") (pin "G8") (pinfunction "IOVDD0_G8") (pintype "bidirectional"))
      (node (ref "U101") (pin "H7") (pinfunction "IOVDD0_H7") (pintype "bidirectional"))
      (node (ref "U101") (pin "K8") (pinfunction "AVDD_K8") (pintype "bidirectional"))
      (node (ref "U101") (pin "K9") (pinfunction "AVDD_K9") (pintype "bidirectional"))
      (node (ref "U101") (pin "L10") (pinfunction "AVDD_L10") (pintype "bidirectional"))
      (node (ref "U101") (pin "L4") (pinfunction "IOVDD0_L4") (pintype "bidirectional"))
      (node (ref "U201") (pin "C1") (pinfunction "VDDIN_C1") (pintype "bidirectional"))
      (node (ref "U201") (pin "D1") (pinfunction "VREFP_D1") (pintype "bidirectional"))
      (node (ref "U201") (pin "E7") (pinfunction "VDDUTMII_E7") (pintype "bidirectional"))
      (node (ref "U201") (pin "G8") (pinfunction "VDDIO_G8") (pintype "bidirectional"))
      (node (ref "U201") (pin "H6") (pinfunction "VDDIO_H6") (pintype "bidirectional"))
      (node (ref "U201") (pin "H7") (pinfunction "VDDIO_H7") (pintype "bidirectional"))
      (node (ref "U301") (pin "A13") (pinfunction "VCCIO0_A13") (pintype "power_in"))
      (node (ref "U301") (pin "A3") (pinfunction "VCCIO0_A3") (pintype "power_in"))
      (node (ref "U301") (pin "A8") (pinfunction "VCCIO0_A8") (pintype "power_in"))
      (node (ref "U301") (pin "C15") (pinfunction "VCCIO1_C15") (pintype "power_in"))
      (node (ref "U301") (pin "E1") (pinfunction "VCCIO3_E1") (pintype "power_in"))
      (node (ref "U301") (pin "E12") (pinfunction "VPP_2V5_E12") (pintype "power_in"))
      (node (ref "U301") (pin "F8") (pinfunction "VCCIO0_F8") (pintype "power_in"))
      (node (ref "U301") (pin "G6") (pinfunction "VCCIO3_G6") (pintype "power_in"))
      (node (ref "U301") (pin "H10") (pinfunction "VCCIO1_H10") (pintype "power_in"))
      (node (ref "U301") (pin "H15") (pinfunction "VCCIO1_H15") (pintype "power_in"))
      (node (ref "U301") (pin "J6") (pinfunction "VCCIO3_J6") (pintype "power_in"))
      (node (ref "U301") (pin "K8") (pinfunction "VCCIO2_K8") (pintype "power_in"))
      (node (ref "U301") (pin "N1") (pinfunction "VCCIO3_N1") (pintype "power_in"))
      (node (ref "U301") (pin "N13") (pinfunction "VCC_SPI_N13") (pintype "power_in"))
      (node (ref "U301") (pin "N15") (pinfunction "VCCIO1_N15") (pintype "power_in"))
      (node (ref "U301") (pin "P3") (pinfunction "VCCIO2_P3") (pintype "power_in"))
      (node (ref "U301") (pin "R13") (pinfunction "VCCIO2_R13") (pintype "power_in"))
      (node (ref "U301") (pin "R8") (pinfunction "VCCIO2_R8") (pintype "power_in"))
      (node (ref "U302") (pin "8") (pinfunction "VCC_8") (pintype "power_in"))
      (node (ref "U402") (pin "24") (pinfunction "OVDD_24") (pintype "bidirectional"))
      (node (ref "U402") (pin "25") (pinfunction "OVDD_25") (pintype "bidirectional"))
      (node (ref "U402") (pin "36") (pinfunction "OVDD_36") (pintype "bidirectional"))
      (node (ref "U402") (pin "37") (pinfunction "OVDD_37") (pintype "bidirectional"))
      (node (ref "U402") (pin "45") (pinfunction "MODE_45") (pintype "bidirectional"))
      (node (ref "U502") (pin "17") (pinfunction "CVDD_17") (pintype "bidirectional"))
      (node (ref "U502") (pin "5") (pinfunction "DVDDIO_5") (pintype "bidirectional"))
      (node (ref "U602") (pin "28") (pinfunction "DVDD_28") (pintype "bidirectional"))
      (node (ref "U701") (pin "16") (pinfunction "DVDDIO_16") (pintype "bidirectional"))
      (node (ref "U701") (pin "28") (pinfunction "PVDD_28") (pintype "bidirectional"))
      (node (ref "U702") (pin "6") (pinfunction "VDD_6") (pintype "bidirectional"))
      (node (ref "U702") (pin "7") (pinfunction "VREGIN_7") (pintype "bidirectional"))
      (node (ref "U801") (pin "1") (pinfunction "LEDA_1") (pintype "bidirectional"))
      (node (ref "U801") (pin "35") (pinfunction "~{RD}_35") (pintype "bidirectional"))
      (node (ref "U801") (pin "40") (pinfunction "VDDI_40") (pintype "bidirectional"))
      (node (ref "U801") (pin "41") (pinfunction "VDDI_41") (pintype "bidirectional"))
      (node (ref "U801") (pin "42") (pinfunction "VCI_42") (pintype "bidirectional"))
      (node (ref "U801") (pin "7") (pinfunction "IM0_7") (pintype "bidirectional"))
      (node (ref "U801") (pin "8") (pinfunction "IM1_8") (pintype "bidirectional"))
      (node (ref "U801") (pin "9") (pinfunction "IM2_9") (pintype "bidirectional"))
      (node (ref "U901") (pin "6") (pinfunction "VDD_6") (pintype "power_in"))
      (node (ref "U902") (pin "10") (pinfunction "VDDOB_10") (pintype "bidirectional"))
      (node (ref "U902") (pin "11") (pinfunction "VDDOA_11") (pintype "bidirectional"))
      (node (ref "U902") (pin "14") (pinfunction "VDDOD_14") (pintype "bidirectional"))
      (node (ref "U902") (pin "18") (pinfunction "VDDOC_18") (pintype "bidirectional"))
      (node (ref "U902") (pin "20") (pinfunction "VDD_20") (pintype "bidirectional"))
    )
    (net (code "5") (name "3V3_ANA_RX_CLEAN") (class "Default")
      (node (ref "C1030") (pin "1") (pinfunction "C1_1") (pintype "passive"))
      (node (ref "C401") (pin "1") (pinfunction "C1_1") (pintype "passive"))
      (node (ref "C404") (pin "1") (pinfunction "C1_1") (pintype "passive"))
      (node (ref "C406") (pin "1") (pinfunction "C1_1") (pintype "passive"))
      (node (ref "C408") (pin "1") (pinfunction "C1_1") (pintype "passive"))
      (node (ref "C411") (pin "1") (pinfunction "C1_1") (pintype "passive"))
      (node (ref "C413") (pin "1") (pinfunction "C1_1") (pintype "passive"))
      (node (ref "C414") (pin "1") (pinfunction "C1_1") (pintype "passive"))
      (node (ref "C418") (pin "1") (pinfunction "C1_1") (pintype "passive"))
      (node (ref "C421") (pin "1") (pinfunction "C1_1") (pintype "passive"))
      (node (ref "R403") (pin "1") (pinfunction "1_1") (pintype "passive"))
      (node (ref "U1007") (pin "1") (pinfunction "VOUT_1") (pintype "bidirectional"))
      (node (ref "U1007") (pin "2") (pinfunction "VOUT_2") (pintype "bidirectional"))
      (node (ref "U401") (pin "6") (pinfunction "VDD_6") (pintype "power_in"))
      (node (ref "U402") (pin "12") (pinfunction "VDD_12") (pintype "bidirectional"))
      (node (ref "U402") (pin "13") (pinfunction "VDD_13") (pintype "bidirectional"))
      (node (ref "U402") (pin "14") (pinfunction "VDD_14") (pintype "bidirectional"))
      (node (ref "U402") (pin "3") (pinfunction "VDD_3") (pintype "bidirectional"))
      (node (ref "U402") (pin "4") (pinfunction "VDD_4") (pintype "bidirectional"))
      (node (ref "U403") (pin "11") (pinfunction "VCC_11") (pintype "bidirectional"))
      (node (ref "U403") (pin "18") (pinfunction "VCC_18") (pintype "bidirectional"))
      (node (ref "U403") (pin "2") (pinfunction "VCC_2") (pintype "bidirectional"))
      (node (ref "U403") (pin "23") (pinfunction "VCC_23") (pintype "bidirectional"))
    )
    (net (code "6") (name "3V3_ANA_TXPLL_CLEAN") (class "Default")
      (node (ref "C1028") (pin "1") (pinfunction "C1_1") (pintype "passive"))
      (node (ref "C601") (pin "1") (pinfunction "C1_1") (pintype "passive"))
      (node (ref "C602") (pin "1") (pinfunction "C1_1") (pintype "passive"))
      (node (ref "C603") (pin "1") (pinfunction "C1_1") (pintype "passive"))
      (node (ref "C604") (pin "1") (pinfunction "C1_1") (pintype "passive"))
      (node (ref "L601") (pin "1") (pinfunction "1_1") (pintype "passive"))
      (node (ref "L602") (pin "2") (pinfunction "2_2") (pintype "passive"))
      (node (ref "U1005") (pin "5") (pinfunction "OUT_5") (pintype "bidirectional"))
      (node (ref "U601") (pin "6") (pinfunction "VDD_6") (pintype "power_in"))
      (node (ref "U602") (pin "10") (pinfunction "AVDD_10") (pintype "bidirectional"))
      (node (ref "U602") (pin "16") (pinfunction "VVCO_16") (pintype "bidirectional"))
      (node (ref "U602") (pin "17") (pinfunction "VVCO_17") (pintype "bidirectional"))
      (node (ref "U602") (pin "32") (pinfunction "SDVDD_32") (pintype "bidirectional"))
      (node (ref "U602") (pin "6") (pinfunction "VP_6") (pintype "bidirectional"))
    )
    (net (code "7") (name "3V3_ANA_TX_CLEAN") (class "Default")
      (node (ref "C1029") (pin "1") (pinfunction "C1_1") (pintype "passive"))
      (node (ref "C509") (pin "1") (pinfunction "C1_1") (pintype "passive"))
      (node (ref "U1006") (pin "1") (pinfunction "VOUT_1") (pintype "bidirectional"))
      (node (ref "U1006") (pin "2") (pinfunction "VOUT_2") (pintype "bidirectional"))
      (node (ref "U502") (pin "26") (pinfunction "AVDD_26") (pintype "bidirectional"))
    )
    (net (code "8") (name "3V3_PGOOD") (class "Default")
      (node (ref "R1009") (pin "1") (pinfunction "1_1") (pintype "passive"))
      (node (ref "U1002") (pin "12") (pinfunction "PG_12") (pintype "bidirectional"))
      (node (ref "U101") (pin "D10") (pinfunction "PC8_D10") (pintype "bidirectional"))
    )
    (net (code "9") (name "3V6_ANA") (class "Default")
      (node (ref "C1010") (pin "1") (pinfunction "C1_1") (pintype "passive"))
      (node (ref "C1013") (pin "1") (pinfunction "C1_1") (pintype "passive"))
      (node (ref "C1022") (pin "1") (pinfunction "C1_1") (pintype "passive"))
      (node (ref "C1023") (pin "1") (pinfunction "C1_1") (pintype "passive"))
      (node (ref "C1025") (pin "1") (pinfunction "C1_1") (pintype "passive"))
      (node (ref "L1002") (pin "2") (pinfunction "2_2") (pintype "passive"))
      (node (ref "R1007") (pin "2") (pinfunction "2_2") (pintype "passive"))
      (node (ref "U1001") (pin "3") (pinfunction "SNS_3") (pintype "bidirectional"))
      (node (ref "U1005") (pin "1") (pinfunction "VIN_1") (pintype "bidirectional"))
      (node (ref "U1005") (pin "3") (pinfunction "EN_3") (pintype "bidirectional"))
      (node (ref "U1006") (pin "4") (pinfunction "EN_4") (pintype "bidirectional"))
      (node (ref "U1006") (pin "5") (pinfunction "VIN_5") (pintype "bidirectional"))
      (node (ref "U1006") (pin "6") (pinfunction "VIN_6") (pintype "bidirectional"))
      (node (ref "U1007") (pin "4") (pinfunction "EN_4") (pintype "bidirectional"))
      (node (ref "U1007") (pin "5") (pinfunction "VIN_5") (pintype "bidirectional"))
      (node (ref "U1007") (pin "6") (pinfunction "VIN_6") (pintype "bidirectional"))
    )
    (net (code "10") (name "3V6_ANA_PGOOD") (class "Default")
      (node (ref "R1006") (pin "1") (pinfunction "1_1") (pintype "passive"))
      (node (ref "U1001") (pin "5") (pinfunction "PG_5") (pintype "bidirectional"))
      (node (ref "U101") (pin "C10") (pinfunction "PC10_C10") (pintype "bidirectional"))
    )
    (net (code "11") (name "5V0") (class "Default")
      (node (ref "C1001") (pin "1") (pinfunction "C1_1") (pintype "passive"))
      (node (ref "C1002") (pin "1") (pinfunction "C1_1") (pintype "passive"))
      (node (ref "C1003") (pin "1") (pinfunction "C1_1") (pintype "passive"))
      (node (ref "C1004") (pin "1") (pinfunction "C1_1") (pintype "passive"))
      (node (ref "C1011") (pin "1") (pinfunction "C1_1") (pintype "passive"))
      (node (ref "C1014") (pin "1") (pinfunction "C1_1") (pintype "passive"))
      (node (ref "C1017") (pin "1") (pinfunction "C1_1") (pintype "passive"))
      (node (ref "C1018") (pin "1") (pinfunction "C1_1") (pintype "passive"))
      (node (ref "C1019") (pin "1") (pinfunction "C1_1") (pintype "passive"))
      (node (ref "L1003") (pin "2") (pinfunction "2_2") (pintype "passive"))
      (node (ref "L1005") (pin "1") (pinfunction "1_1") (pintype "passive"))
      (node (ref "R1012") (pin "2") (pinfunction "2_2") (pintype "passive"))
      (node (ref "U1001") (pin "2") (pinfunction "EN_2") (pintype "bidirectional"))
      (node (ref "U1001") (pin "8") (pinfunction "VIN_8") (pintype "bidirectional"))
      (node (ref "U1001") (pin "9") (pinfunction "VIN_9") (pintype "bidirectional"))
      (node (ref "U1002") (pin "1") (pinfunction "VIN_1") (pintype "bidirectional"))
      (node (ref "U1002") (pin "18") (pinfunction "EN_18") (pintype "bidirectional"))
      (node (ref "U1002") (pin "20") (pinfunction "AVIN_20") (pintype "bidirectional"))
      (node (ref "U1002") (pin "6") (pinfunction "VIN_6") (pintype "bidirectional"))
      (node (ref "U1002") (pin "7") (pinfunction "AVIN_7") (pintype "bidirectional"))
      (node (ref "U1002") (pin "9") (pinfunction "EN_9") (pintype "bidirectional"))
    )
    (net (code "12") (name "5V0_ANA_TXMIXER_CLEAN") (class "Default")
      (node (ref "C1020") (pin "1") (pinfunction "C1_1") (pintype "passive"))
      (node (ref "C1021") (pin "1") (pinfunction "C1_1") (pintype "passive"))
      (node (ref "C501") (pin "1") (pinfunction "C1_1") (pintype "passive"))
      (node (ref "C502") (pin "1") (pinfunction "C1_1") (pintype "passive"))
      (node (ref "C503") (pin "1") (pinfunction "C1_1") (pintype "passive"))
      (node (ref "L1005") (pin "2") (pinfunction "2_2") (pintype "passive"))
      (node (ref "U1003") (pin "1") (pinfunction "VIN_1") (pintype "bidirectional"))
      (node (ref "U501") (pin "11") (pinfunction "VPS2_11") (pintype "bidirectional"))
      (node (ref "U501") (pin "23") (pinfunction "VPS3_23") (pintype "bidirectional"))
      (node (ref "U501") (pin "24") (pinfunction "VPS3_24") (pintype "bidirectional"))
      (node (ref "U501") (pin "8") (pinfunction "VPS1_8") (pintype "bidirectional"))
      (node (ref "U501") (pin "9") (pinfunction "VPS1_9") (pintype "bidirectional"))
    )
    (net (code "13") (name "5V0_ANA_TXPA_CLEAN") (class "Default")
      (node (ref "C1026") (pin "1") (pinfunction "C1_1") (pintype "passive"))
      (node (ref "C512") (pin "1") (pinfunction "C1_1") (pintype "passive"))
      (node (ref "C514") (pin "1") (pinfunction "C1_1") (pintype "passive"))
      (node (ref "L501") (pin "2") (pinfunction "2_2") (pintype "passive"))
      (node (ref "R508") (pin "2") (pinfunction "2_2") (pintype "passive"))
      (node (ref "U1003") (pin "6") (pinfunction "VOUT_6") (pintype "bidirectional"))
    )
    (net (code "14") (name "AUDIO_I2C_SCL") (class "Default")
      (node (ref "R105") (pin "1") (pinfunction "1_1") (pintype "passive"))
      (node (ref "U101") (pin "A11") (pinfunction "PF11_A11") (pintype "bidirectional"))
      (node (ref "U701") (pin "12") (pinfunction "I2C_SCL_12") (pintype "bidirectional"))
      (node (ref "U702") (pin "29") (pinfunction "I2C_SCL_29") (pintype "bidirectional"))
    )
    (net (code "15") (name "AUDIO_I2C_SDA") (class "Default")
      (node (ref "R104") (pin "1") (pinfunction "1_1") (pintype "passive"))
      (node (ref "U101") (pin "A10") (pinfunction "PF10_A10") (pintype "bidirectional"))
      (node (ref "U701") (pin "11") (pinfunction "I2C_SDA_11") (pintype "bidirectional"))
      (node (ref "U702") (pin "30") (pinfunction "I2C_SDA_30") (pintype "bidirectional"))
    )
    (net (code "16") (name "BRG_I2S_LRCLK") (class "Default")
      (node (ref "U301") (pin "T15") (pinfunction "IOB_91_T15") (pintype "bidirectional"))
      (node (ref "U702") (pin "28") (pinfunction "I2S_LRCLK_28") (pintype "bidirectional"))
    )
    (net (code "17") (name "BRG_I2S_MCLK") (class "Default")
      (node (ref "U301") (pin "R15") (pinfunction "IOR_110_R15") (pintype "bidirectional"))
      (node (ref "U702") (pin "26") (pinfunction "I2S_MCLK_26") (pintype "bidirectional"))
    )
    (net (code "18") (name "BRG_I2S_SCLK") (class "Default")
      (node (ref "U301") (pin "T13") (pinfunction "IOB_94_T13") (pintype "bidirectional"))
      (node (ref "U702") (pin "2") (pinfunction "I2S_SCLK_2") (pintype "bidirectional"))
    )
    (net (code "19") (name "BRG_I2S_SDIN") (class "Default")
      (node (ref "U301") (pin "T14") (pinfunction "IOB_92_T14") (pintype "bidirectional"))
      (node (ref "U702") (pin "1") (pinfunction "I2S_SDIN_1") (pintype "bidirectional"))
    )
    (net (code "20") (name "BRG_I2S_SDOUT") (class "Default")
      (node (ref "U301") (pin "R14") (pinfunction "IOR_109_R14") (pintype "bidirectional"))
      (node (ref "U702") (pin "32") (pinfunction "I2S_SDOUT_32") (pintype "bidirectional"))
    )
    (net (code "21") (name "CODEC_I2S_LRCLK") (class "Default")
      (node (ref "U301") (pin "R16") (pinfunction "IOB_102_R16") (pintype "bidirectional"))
      (node (ref "U701") (pin "15") (pinfunction "ADCLRCLK_15") (pintype "bidirectional"))
      (node (ref "U701") (pin "19") (pinfunction "DACLRCLK_19") (pintype "bidirectional"))
    )
    (net (code "22") (name "CODEC_I2S_MCLK") (class "Default")
      (node (ref "U301") (pin "N16") (pinfunction "IOR_117_N16") (pintype "bidirectional"))
      (node (ref "U701") (pin "6") (pinfunction "MCLK_6") (pintype "bidirectional"))
    )
    (net (code "23") (name "CODEC_I2S_SCLK") (class "Default")
      (node (ref "U301") (pin "T16") (pinfunction "IOB_100_T16") (pintype "bidirectional"))
      (node (ref "U701") (pin "14") (pinfunction "ADCBCLK_14") (pintype "bidirectional"))
      (node (ref "U701") (pin "20") (pinfunction "DACBCLK_20") (pintype "bidirectional"))
    )
    (net (code "24") (name "CODEC_I2S_SDIN") (class "Default")
      (node (ref "U301") (pin "P15") (pinfunction "IOR_112_P15") (pintype "bidirectional"))
      (node (ref "U701") (pin "18") (pinfunction "DACDIN_18") (pintype "bidirectional"))
    )
    (net (code "25") (name "CODEC_I2S_SDOUT") (class "Default")
      (node (ref "U301") (pin "P16") (pinfunction "IOR_113_P16") (pintype "bidirectional"))
      (node (ref "U701") (pin "13") (pinfunction "ADCDOUT_13") (pintype "bidirectional"))
    )
    (net (code "26") (name "DSP_BB_I2S_LRCLK") (class "Default")
      (node (ref "U201") (pin "C2") (pinfunction "PE0_C2") (pintype "bidirectional"))
      (node (ref "U301") (pin "D15") (pinfunction "IOR_157_D15") (pintype "bidirectional"))
    )
    (net (code "27") (name "DSP_BB_I2S_SCLK") (class "Default")
      (node (ref "U201") (pin "H3") (pinfunction "PA20_H3") (pintype "bidirectional"))
      (node (ref "U301") (pin "E16") (pinfunction "IOR_151_E16") (pintype "bidirectional"))
    )
    (net (code "28") (name "DSP_BB_I2S_SDIN") (class "Default")
      (node (ref "U201") (pin "B1") (pinfunction "PE2_B1") (pintype "bidirectional"))
      (node (ref "U301") (pin "D16") (pinfunction "IOR_153_D16") (pintype "bidirectional"))
    )
    (net (code "29") (name "DSP_BB_I2S_SDOUT") (class "Default")
      (node (ref "U201") (pin "A1") (pinfunction "PE1_A1") (pintype "bidirectional"))
      (node (ref "U301") (pin "C16") (pinfunction "IOR_161_C16") (pintype "bidirectional"))
    )
    (net (code "30") (name "DSP_D+") (class "Default")
      (node (ref "D1001") (pin "4") (pinfunction "4_4") (pintype "bidirectional"))
      (node (ref "U201") (pin "A4") (pinfunction "HSDP_A4") (pintype "bidirectional"))
      (node (ref "USB1001") (pin "A6") (pinfunction "D+_A6") (pintype "bidirectional"))
      (node (ref "USB1001") (pin "B6") (pinfunction "D+_B6") (pintype "bidirectional"))
    )
    (net (code "31") (name "DSP_D-") (class "Default")
      (node (ref "D1001") (pin "3") (pinfunction "3_3") (pintype "bidirectional"))
      (node (ref "U201") (pin "B4") (pinfunction "HSDM_B4") (pintype "bidirectional"))
      (node (ref "USB1001") (pin "A7") (pinfunction "D-_A7") (pintype "bidirectional"))
      (node (ref "USB1001") (pin "B7") (pinfunction "D-_B7") (pintype "bidirectional"))
    )
    (net (code "32") (name "DSP_ERASE") (class "Default")
      (node (ref "SJ201") (pin "1") (pinfunction "1_1") (pintype "passive"))
      (node (ref "U201") (pin "G12") (pinfunction "PB12_G12") (pintype "bidirectional"))
    )
    (net (code "33") (name "DSP_I2S_LRCLK") (class "Default")
      (node (ref "U201") (pin "L5") (pinfunction "PA15_L5") (pintype "bidirectional"))
      (node (ref "U301") (pin "M15") (pinfunction "IOR_123_M15") (pintype "bidirectional"))
    )
    (net (code "34") (name "DSP_I2S_MCLK") (class "Default")
      (node (ref "U201") (pin "C11") (pinfunction "PA0_C11") (pintype "bidirectional"))
      (node (ref "U301") (pin "K15") (pinfunction "IOR_131_K15") (pintype "bidirectional"))
    )
    (net (code "35") (name "DSP_I2S_SCLK") (class "Default")
      (node (ref "U201") (pin "D12") (pinfunction "PA1_D12") (pintype "bidirectional"))
      (node (ref "U301") (pin "L16") (pinfunction "IOR_127_L16") (pintype "bidirectional"))
    )
    (net (code "36") (name "DSP_I2S_SDIN") (class "Default")
      (node (ref "U201") (pin "K5") (pinfunction "PA16_K5") (pintype "bidirectional"))
      (node (ref "U301") (pin "M16") (pinfunction "IOR_121_M16") (pintype "bidirectional"))
    )
    (net (code "37") (name "DSP_I2S_SDOUT") (class "Default")
      (node (ref "U201") (pin "A10") (pinfunction "PA30_A10") (pintype "bidirectional"))
      (node (ref "U301") (pin "K16") (pinfunction "IOR_133_K16") (pintype "bidirectional"))
    )
    (net (code "38") (name "DSP_LED") (class "Default")
      (node (ref "R203") (pin "2") (pinfunction "2_2") (pintype "passive"))
      (node (ref "U201") (pin "A12") (pinfunction "PB4_A12") (pintype "bidirectional"))
    )
    (net (code "39") (name "DSP_MAIN_CLK") (class "Default")
      (node (ref "R906") (pin "1") (pinfunction "1_1") (pintype "passive"))
      (node (ref "U201") (pin "A2") (pinfunction "PB9_A2") (pintype "bidirectional"))
    )
    (net (code "40") (name "DSP_SPI_MISO") (class "Default")
      (node (ref "U101") (pin "C1") (pinfunction "PA1_C1") (pintype "bidirectional"))
      (node (ref "U201") (pin "K9") (pinfunction "PD20_K9") (pintype "bidirectional"))
    )
    (net (code "41") (name "DSP_SPI_MOSI") (class "Default")
      (node (ref "U101") (pin "C2") (pinfunction "PA0_C2") (pintype "bidirectional"))
      (node (ref "U201") (pin "H9") (pinfunction "PD21_H9") (pintype "bidirectional"))
    )
    (net (code "42") (name "DSP_SPI_SCK") (class "Default")
      (node (ref "U101") (pin "D2") (pinfunction "PA2_D2") (pintype "bidirectional"))
      (node (ref "U201") (pin "M8") (pinfunction "PD22_M8") (pintype "bidirectional"))
    )
    (net (code "43") (name "DSP_SWCLK") (class "Default")
      (node (ref "TC201") (pin "4") (pinfunction "S_4") (pintype "passive"))
      (node (ref "U201") (pin "F9") (pinfunction "PB7_F9") (pintype "bidirectional"))
    )
    (net (code "44") (name "DSP_SWDIO") (class "Default")
      (node (ref "TC201") (pin "2") (pinfunction "S_2") (pintype "passive"))
      (node (ref "U201") (pin "J11") (pinfunction "PB6_J11") (pintype "bidirectional"))
    )
    (net (code "45") (name "DSP_SWO") (class "Default")
      (node (ref "TC201") (pin "6") (pinfunction "S_6") (pintype "passive"))
      (node (ref "U201") (pin "C10") (pinfunction "PB5_C10") (pintype "bidirectional"))
    )
    (net (code "46") (name "FPGA_BLED") (class "Default")
      (node (ref "R304") (pin "1") (pinfunction "1_1") (pintype "passive"))
      (node (ref "U301") (pin "B16") (pinfunction "IOR_165_B16") (pintype "bidirectional"))
    )
    (net (code "47") (name "FPGA_CBSEL0") (class "Default")
      (node (ref "U101") (pin "F2") (pinfunction "PB2_F2") (pintype "bidirectional"))
      (node (ref "U301") (pin "K11") (pinfunction "CBSEL0/IOB_103_K11") (pintype "bidirectional"))
    )
    (net (code "48") (name "FPGA_CBSEL1\\") (class "Default")
      (node (ref "U101") (pin "G1") (pinfunction "PB5_G1") (pintype "bidirectional"))
      (node (ref "U301") (pin "P13") (pinfunction "CBSEL1/IOB_104_P13") (pintype "bidirectional"))
    )
    (net (code "49") (name "FPGA_CDONE") (class "Default")
      (node (ref "U101") (pin "F1") (pinfunction "PB1_F1") (pintype "bidirectional"))
      (node (ref "U301") (pin "M10") (pinfunction "CDONE_M10") (pintype "passive"))
    )
    (net (code "50") (name "FPGA_CLK1") (class "Default")
      (node (ref "R905") (pin "1") (pinfunction "1_1") (pintype "passive"))
      (node (ref "U301") (pin "C8") (pinfunction "IOT_197_GBIN1_C8") (pintype "bidirectional"))
    )
    (net (code "51") (name "FPGA_CLK2") (class "Default")
      (node (ref "R907") (pin "1") (pinfunction "1_1") (pintype "passive"))
      (node (ref "U301") (pin "K9") (pinfunction "IOB_82_GBIN4_K9") (pintype "bidirectional"))
    )
    (net (code "52") (name "FPGA_CLK3") (class "Default")
      (node (ref "R904") (pin "1") (pinfunction "1_1") (pintype "passive"))
      (node (ref "U301") (pin "R9") (pinfunction "IOB_81_GBIN5_R9") (pintype "bidirectional"))
    )
    (net (code "53") (name "FPGA_CLK4") (class "Default")
      (node (ref "R908") (pin "1") (pinfunction "1_1") (pintype "passive"))
      (node (ref "U301") (pin "F7") (pinfunction "IOT_198_GBIN0_F7") (pintype "bidirectional"))
    )
    (net (code "54") (name "FPGA_GLED") (class "Default")
      (node (ref "R303") (pin "1") (pinfunction "1_1") (pintype "passive"))
      (node (ref "U301") (pin "A15") (pinfunction "IOT_177_A15") (pintype "bidirectional"))
    )
    (net (code "55") (name "FPGA_MEM_IO0") (class "Default")
      (node (ref "U301") (pin "C13") (pinfunction "IOT_174_C13") (pintype "bidirectional"))
      (node (ref "U302") (pin "5") (pinfunction "MOSI/IO0_5") (pintype "input"))
    )
    (net (code "56") (name "FPGA_MEM_IO1") (class "Default")
      (node (ref "U301") (pin "E13") (pinfunction "IOR_166_E13") (pintype "bidirectional"))
      (node (ref "U302") (pin "2") (pinfunction "MISO/IO1_2") (pintype "output"))
    )
    (net (code "57") (name "FPGA_MEM_IO2") (class "Default")
      (node (ref "U301") (pin "D14") (pinfunction "IOR_167_D14") (pintype "bidirectional"))
      (node (ref "U302") (pin "3") (pinfunction "~{WP}/IO2_3") (pintype "input"))
    )
    (net (code "58") (name "FPGA_MEM_IO3") (class "Default")
      (node (ref "U301") (pin "D13") (pinfunction "IOT_170_D13") (pintype "bidirectional"))
      (node (ref "U302") (pin "7") (pinfunction "~{HOLD}/IO3_7") (pintype "input"))
    )
    (net (code "59") (name "FPGA_MEM_SCK") (class "Default")
      (node (ref "U301") (pin "C14") (pinfunction "IOT_168_C14") (pintype "bidirectional"))
      (node (ref "U302") (pin "6") (pinfunction "SCK_6") (pintype "input"))
    )
    (net (code "60") (name "FPGA_RLED") (class "Default")
      (node (ref "R302") (pin "1") (pinfunction "1_1") (pintype "passive"))
      (node (ref "U301") (pin "A16") (pinfunction "IOT_176_A16") (pintype "bidirectional"))
    )
    (net (code "61") (name "FPGA_SPI_SCK") (class "Default")
      (node (ref "U101") (pin "J2") (pinfunction "PC3_J2") (pintype "bidirectional"))
      (node (ref "U301") (pin "R11") (pinfunction "SCK/IOB_107_R11") (pintype "bidirectional"))
    )
    (net (code "62") (name "FPGA_SPI_SDI") (class "Default")
      (node (ref "U101") (pin "J1") (pinfunction "PC1_J1") (pintype "bidirectional"))
      (node (ref "U301") (pin "P11") (pinfunction "SDI/IOB_106_P11") (pintype "bidirectional"))
    )
    (net (code "63") (name "FPGA_SPI_SDO") (class "Default")
      (node (ref "U101") (pin "H2") (pinfunction "PC2_H2") (pintype "bidirectional"))
      (node (ref "U301") (pin "P12") (pinfunction "SDO/IOB_105_P12") (pintype "bidirectional"))
    )
    (net (code "64") (name "GND") (class "Default")
      (node (ref "C1001") (pin "2") (pinfunction "C2_2") (pintype "passive"))
      (node (ref "C1002") (pin "2") (pinfunction "C2_2") (pintype "passive"))
      (node (ref "C1003") (pin "2") (pinfunction "C2_2") (pintype "passive"))
      (node (ref "C1004") (pin "2") (pinfunction "C2_2") (pintype "passive"))
      (node (ref "C1005") (pin "2") (pinfunction "C2_2") (pintype "passive"))
      (node (ref "C1006") (pin "2") (pinfunction "C2_2") (pintype "passive"))
      (node (ref "C1007") (pin "2") (pinfunction "C2_2") (pintype "passive"))
      (node (ref "C1008") (pin "2") (pinfunction "C2_2") (pintype "passive"))
      (node (ref "C1009") (pin "2") (pinfunction "C2_2") (pintype "passive"))
      (node (ref "C101") (pin "2") (pinfunction "C2_2") (pintype "passive"))
      (node (ref "C1010") (pin "2") (pinfunction "C2_2") (pintype "passive"))
      (node (ref "C1011") (pin "2") (pinfunction "C2_2") (pintype "passive"))
      (node (ref "C1012") (pin "2") (pinfunction "C2_2") (pintype "passive"))
      (node (ref "C1013") (pin "2") (pinfunction "C2_2") (pintype "passive"))
      (node (ref "C1014") (pin "2") (pinfunction "C2_2") (pintype "passive"))
      (node (ref "C1015") (pin "2") (pinfunction "C2_2") (pintype "passive"))
      (node (ref "C1016") (pin "2") (pinfunction "C2_2") (pintype "passive"))
      (node (ref "C1017") (pin "2") (pinfunction "C2_2") (pintype "passive"))
      (node (ref "C1018") (pin "2") (pinfunction "C2_2") (pintype "passive"))
      (node (ref "C1019") (pin "2") (pinfunction "C2_2") (pintype "passive"))
      (node (ref "C102") (pin "2") (pinfunction "C2_2") (pintype "passive"))
      (node (ref "C1020") (pin "2") (pinfunction "C2_2") (pintype "passive"))
      (node (ref "C1021") (pin "2") (pinfunction "C2_2") (pintype "passive"))
      (node (ref "C1022") (pin "2") (pinfunction "C2_2") (pintype "passive"))
      (node (ref "C1023") (pin "2") (pinfunction "C2_2") (pintype "passive"))
      (node (ref "C1024") (pin "2") (pinfunction "C2_2") (pintype "passive"))
      (node (ref "C1025") (pin "2") (pinfunction "C2_2") (pintype "passive"))
      (node (ref "C1026") (pin "2") (pinfunction "C2_2") (pintype "passive"))
      (node (ref "C1027") (pin "2") (pinfunction "C2_2") (pintype "passive"))
      (node (ref "C1028") (pin "2") (pinfunction "C2_2") (pintype "passive"))
      (node (ref "C1029") (pin "2") (pinfunction "C2_2") (pintype "passive"))
      (node (ref "C103") (pin "2") (pinfunction "C2_2") (pintype "passive"))
      (node (ref "C1030") (pin "2") (pinfunction "C2_2") (pintype "passive"))
      (node (ref "C104") (pin "2") (pinfunction "C2_2") (pintype "passive"))
      (node (ref "C105") (pin "2") (pinfunction "C2_2") (pintype "passive"))
      (node (ref "C106") (pin "2") (pinfunction "C2_2") (pintype "passive"))
      (node (ref "C107") (pin "2") (pinfunction "C2_2") (pintype "passive"))
      (node (ref "C108") (pin "2") (pinfunction "C2_2") (pintype "passive"))
      (node (ref "C109") (pin "2") (pinfunction "C2_2") (pintype "passive"))
      (node (ref "C110") (pin "2") (pinfunction "C2_2") (pintype "passive"))
      (node (ref "C111") (pin "2") (pinfunction "C2_2") (pintype "passive"))
      (node (ref "C201") (pin "2") (pinfunction "C2_2") (pintype "passive"))
      (node (ref "C202") (pin "2") (pinfunction "C2_2") (pintype "passive"))
      (node (ref "C203") (pin "2") (pinfunction "C2_2") (pintype "passive"))
      (node (ref "C204") (pin "2") (pinfunction "C2_2") (pintype "passive"))
      (node (ref "C205") (pin "2") (pinfunction "C2_2") (pintype "passive"))
      (node (ref "C206") (pin "2") (pinfunction "C2_2") (pintype "passive"))
      (node (ref "C207") (pin "2") (pinfunction "C2_2") (pintype "passive"))
      (node (ref "C208") (pin "2") (pinfunction "C2_2") (pintype "passive"))
      (node (ref "C209") (pin "2") (pinfunction "C2_2") (pintype "passive"))
      (node (ref "C210") (pin "2") (pinfunction "C2_2") (pintype "passive"))
      (node (ref "C211") (pin "2") (pinfunction "C2_2") (pintype "passive"))
      (node (ref "C212") (pin "2") (pinfunction "C2_2") (pintype "passive"))
      (node (ref "C213") (pin "2") (pinfunction "C2_2") (pintype "passive"))
      (node (ref "C214") (pin "2") (pinfunction "C2_2") (pintype "passive"))
      (node (ref "C215") (pin "2") (pinfunction "C2_2") (pintype "passive"))
      (node (ref "C216") (pin "2") (pinfunction "C2_2") (pintype "passive"))
      (node (ref "C217") (pin "2") (pinfunction "C2_2") (pintype "passive"))
      (node (ref "C218") (pin "2") (pinfunction "C2_2") (pintype "passive"))
      (node (ref "C301") (pin "2") (pinfunction "C2_2") (pintype "passive"))
      (node (ref "C302") (pin "2") (pinfunction "C2_2") (pintype "passive"))
      (node (ref "C303") (pin "2") (pinfunction "C2_2") (pintype "passive"))
      (node (ref "C304") (pin "2") (pinfunction "C2_2") (pintype "passive"))
      (node (ref "C305") (pin "2") (pinfunction "C2_2") (pintype "passive"))
      (node (ref "C306") (pin "2") (pinfunction "C2_2") (pintype "passive"))
      (node (ref "C307") (pin "2") (pinfunction "C2_2") (pintype "passive"))
      (node (ref "C308") (pin "2") (pinfunction "C2_2") (pintype "passive"))
      (node (ref "C309") (pin "2") (pinfunction "C2_2") (pintype "passive"))
      (node (ref "C310") (pin "2") (pinfunction "C2_2") (pintype "passive"))
      (node (ref "C311") (pin "2") (pinfunction "C2_2") (pintype "passive"))
      (node (ref "C312") (pin "2") (pinfunction "C2_2") (pintype "passive"))
      (node (ref "C313") (pin "2") (pinfunction "C2_2") (pintype "passive"))
      (node (ref "C314") (pin "2") (pinfunction "C2_2") (pintype "passive"))
      (node (ref "C315") (pin "2") (pinfunction "C2_2") (pintype "passive"))
      (node (ref "C316") (pin "2") (pinfunction "C2_2") (pintype "passive"))
      (node (ref "C317") (pin "2") (pinfunction "C2_2") (pintype "passive"))
      (node (ref "C318") (pin "2") (pinfunction "C2_2") (pintype "passive"))
      (node (ref "C319") (pin "2") (pinfunction "C2_2") (pintype "passive"))
      (node (ref "C401") (pin "2") (pinfunction "C2_2") (pintype "passive"))
      (node (ref "C402") (pin "2") (pinfunction "C2_2") (pintype "passive"))
      (node (ref "C403") (pin "2") (pinfunction "C2_2") (pintype "passive"))
      (node (ref "C404") (pin "2") (pinfunction "C2_2") (pintype "passive"))
      (node (ref "C405") (pin "2") (pinfunction "C2_2") (pintype "passive"))
      (node (ref "C406") (pin "2") (pinfunction "C2_2") (pintype "passive"))
      (node (ref "C407") (pin "2") (pinfunction "C2_2") (pintype "passive"))
      (node (ref "C408") (pin "2") (pinfunction "C2_2") (pintype "passive"))
      (node (ref "C409") (pin "2") (pinfunction "C2_2") (pintype "passive"))
      (node (ref "C410") (pin "2") (pinfunction "C2_2") (pintype "passive"))
      (node (ref "C411") (pin "2") (pinfunction "C2_2") (pintype "passive"))
      (node (ref "C412") (pin "2") (pinfunction "C2_2") (pintype "passive"))
      (node (ref "C413") (pin "2") (pinfunction "C2_2") (pintype "passive"))
      (node (ref "C414") (pin "2") (pinfunction "C2_2") (pintype "passive"))
      (node (ref "C415") (pin "2") (pinfunction "C2_2") (pintype "passive"))
      (node (ref "C416") (pin "2") (pinfunction "C2_2") (pintype "passive"))
      (node (ref "C417") (pin "1") (pinfunction "C1_1") (pintype "passive"))
      (node (ref "C418") (pin "2") (pinfunction "C2_2") (pintype "passive"))
      (node (ref "C420") (pin "2") (pinfunction "C2_2") (pintype "passive"))
      (node (ref "C421") (pin "2") (pinfunction "C2_2") (pintype "passive"))
      (node (ref "C422") (pin "2") (pinfunction "C2_2") (pintype "passive"))
      (node (ref "C423") (pin "2") (pinfunction "C2_2") (pintype "passive"))
      (node (ref "C424") (pin "2") (pinfunction "C2_2") (pintype "passive"))
      (node (ref "C425") (pin "2") (pinfunction "C2_2") (pintype "passive"))
      (node (ref "C426") (pin "2") (pinfunction "C2_2") (pintype "passive"))
      (node (ref "C427") (pin "2") (pinfunction "C2_2") (pintype "passive"))
      (node (ref "C428") (pin "2") (pinfunction "C2_2") (pintype "passive"))
      (node (ref "C431") (pin "2") (pinfunction "C2_2") (pintype "passive"))
      (node (ref "C501") (pin "2") (pinfunction "C2_2") (pintype "passive"))
      (node (ref "C502") (pin "2") (pinfunction "C2_2") (pintype "passive"))
      (node (ref "C503") (pin "2") (pinfunction "C2_2") (pintype "passive"))
      (node (ref "C504") (pin "2") (pinfunction "C2_2") (pintype "passive"))
      (node (ref "C505") (pin "2") (pinfunction "C2_2") (pintype "passive"))
      (node (ref "C506") (pin "2") (pinfunction "C2_2") (pintype "passive"))
      (node (ref "C507") (pin "2") (pinfunction "C2_2") (pintype "passive"))
      (node (ref "C509") (pin "2") (pinfunction "C2_2") (pintype "passive"))
      (node (ref "C510") (pin "2") (pinfunction "C2_2") (pintype "passive"))
      (node (ref "C512") (pin "2") (pinfunction "C2_2") (pintype "passive"))
      (node (ref "C514") (pin "2") (pinfunction "C2_2") (pintype "passive"))
      (node (ref "C516") (pin "2") (pinfunction "C2_2") (pintype "passive"))
      (node (ref "C517") (pin "2") (pinfunction "C2_2") (pintype "passive"))
      (node (ref "C518") (pin "1") (pinfunction "C1_1") (pintype "passive"))
      (node (ref "C519") (pin "2") (pinfunction "C2_2") (pintype "passive"))
      (node (ref "C520") (pin "1") (pinfunction "C1_1") (pintype "passive"))
      (node (ref "C521") (pin "2") (pinfunction "C2_2") (pintype "passive"))
      (node (ref "C522") (pin "1") (pinfunction "C1_1") (pintype "passive"))
      (node (ref "C523") (pin "2") (pinfunction "C2_2") (pintype "passive"))
      (node (ref "C524") (pin "1") (pinfunction "C1_1") (pintype "passive"))
      (node (ref "C525") (pin "2") (pinfunction "C2_2") (pintype "passive"))
      (node (ref "C526") (pin "1") (pinfunction "C1_1") (pintype "passive"))
      (node (ref "C527") (pin "2") (pinfunction "C2_2") (pintype "passive"))
      (node (ref "C528") (pin "1") (pinfunction "C1_1") (pintype "passive"))
      (node (ref "C601") (pin "2") (pinfunction "C2_2") (pintype "passive"))
      (node (ref "C602") (pin "2") (pinfunction "C2_2") (pintype "passive"))
      (node (ref "C603") (pin "2") (pinfunction "C2_2") (pintype "passive"))
      (node (ref "C604") (pin "2") (pinfunction "C2_2") (pintype "passive"))
      (node (ref "C605") (pin "2") (pinfunction "C2_2") (pintype "passive"))
      (node (ref "C607") (pin "2") (pinfunction "C2_2") (pintype "passive"))
      (node (ref "C608") (pin "2") (pinfunction "C2_2") (pintype "passive"))
      (node (ref "C609") (pin "2") (pinfunction "C2_2") (pintype "passive"))
      (node (ref "C610") (pin "2") (pinfunction "C2_2") (pintype "passive"))
      (node (ref "C611") (pin "2") (pinfunction "C2_2") (pintype "passive"))
      (node (ref "C612") (pin "2") (pinfunction "C2_2") (pintype "passive"))
      (node (ref "C613") (pin "2") (pinfunction "C2_2") (pintype "passive"))
      (node (ref "C614") (pin "1") (pinfunction "C1_1") (pintype "passive"))
      (node (ref "C616") (pin "2") (pinfunction "C2_2") (pintype "passive"))
      (node (ref "C617") (pin "2") (pinfunction "C2_2") (pintype "passive"))
      (node (ref "C618") (pin "1") (pinfunction "C1_1") (pintype "passive"))
      (node (ref "C619") (pin "2") (pinfunction "C2_2") (pintype "passive"))
      (node (ref "C620") (pin "2") (pinfunction "C2_2") (pintype "passive"))
      (node (ref "C621") (pin "1") (pinfunction "C1_1") (pintype "passive"))
      (node (ref "C701") (pin "2") (pinfunction "C2_2") (pintype "passive"))
      (node (ref "C702") (pin "2") (pinfunction "C2_2") (pintype "passive"))
      (node (ref "C703") (pin "2") (pinfunction "C2_2") (pintype "passive"))
      (node (ref "C704") (pin "2") (pinfunction "C2_2") (pintype "passive"))
      (node (ref "C705") (pin "2") (pinfunction "C2_2") (pintype "passive"))
      (node (ref "C706") (pin "2") (pinfunction "C2_2") (pintype "passive"))
      (node (ref "C708") (pin "2") (pinfunction "C2_2") (pintype "passive"))
      (node (ref "C709") (pin "2") (pinfunction "C2_2") (pintype "passive"))
      (node (ref "C710") (pin "2") (pinfunction "C2_2") (pintype "passive"))
      (node (ref "C711") (pin "2") (pinfunction "C2_2") (pintype "passive"))
      (node (ref "C718") (pin "2") (pinfunction "C2_2") (pintype "passive"))
      (node (ref "C719") (pin "2") (pinfunction "C2_2") (pintype "passive"))
      (node (ref "C720") (pin "2") (pinfunction "C2_2") (pintype "passive"))
      (node (ref "C721") (pin "2") (pinfunction "C2_2") (pintype "passive"))
      (node (ref "C722") (pin "2") (pinfunction "C2_2") (pintype "passive"))
      (node (ref "C723") (pin "2") (pinfunction "C2_2") (pintype "passive"))
      (node (ref "C724") (pin "2") (pinfunction "C2_2") (pintype "passive"))
      (node (ref "C725") (pin "2") (pinfunction "C2_2") (pintype "passive"))
      (node (ref "C726") (pin "2") (pinfunction "C2_2") (pintype "passive"))
      (node (ref "C801") (pin "2") (pinfunction "C2_2") (pintype "passive"))
      (node (ref "C901") (pin "2") (pinfunction "C2_2") (pintype "passive"))
      (node (ref "C902") (pin "2") (pinfunction "C2_2") (pintype "passive"))
      (node (ref "C903") (pin "2") (pinfunction "C2_2") (pintype "passive"))
      (node (ref "C904") (pin "2") (pinfunction "C2_2") (pintype "passive"))
      (node (ref "C905") (pin "2") (pinfunction "C2_2") (pintype "passive"))
      (node (ref "C906") (pin "2") (pinfunction "C2_2") (pintype "passive"))
      (node (ref "C907") (pin "2") (pinfunction "C2_2") (pintype "passive"))
      (node (ref "CON301") (pin "19") (pinfunction "S_19") (pintype "passive"))
      (node (ref "CON301") (pin "2") (pinfunction "S_2") (pintype "passive"))
      (node (ref "CON301") (pin "22") (pinfunction "S_22") (pintype "passive"))
      (node (ref "CON301") (pin "39") (pinfunction "S_39") (pintype "passive"))
      (node (ref "D1001") (pin "1") (pinfunction "1_1") (pintype "bidirectional"))
      (node (ref "D1002") (pin "1") (pinfunction "C_1") (pintype "passive"))
      (node (ref "D1003") (pin "1") (pinfunction "C_1") (pintype "passive"))
      (node (ref "D101") (pin "1") (pinfunction "C_1") (pintype "passive"))
      (node (ref "D201") (pin "1") (pinfunction "C_1") (pintype "passive"))
      (node (ref "D301") (pin "4") (pinfunction "C_4") (pintype "passive"))
      (node (ref "D301") (pin "5") (pinfunction "C_5") (pintype "passive"))
      (node (ref "D301") (pin "6") (pinfunction "C_6") (pintype "passive"))
      (node (ref "D401") (pin "1") (pinfunction "A_1") (pintype "passive"))
      (node (ref "D401") (pin "2") (pinfunction "C_2") (pintype "passive"))
      (node (ref "D501") (pin "1") (pinfunction "C_1") (pintype "passive"))
      (node (ref "D701") (pin "1") (pinfunction "1_1") (pintype "bidirectional"))
      (node (ref "D702") (pin "1") (pinfunction "C_1") (pintype "passive"))
      (node (ref "J701") (pin "1") (pinfunction "S_1") (pintype "bidirectional"))
      (node (ref "J702") (pin "1") (pinfunction "S_1") (pintype "bidirectional"))
      (node (ref "J703") (pin "1") (pinfunction "S_1") (pintype "bidirectional"))
      (node (ref "Q801") (pin "2") (pinfunction "S_2") (pintype "passive"))
      (node (ref "Q802") (pin "2") (pinfunction "S_2") (pintype "passive"))
      (node (ref "R1001") (pin "1") (pinfunction "1_1") (pintype "passive"))
      (node (ref "R1002") (pin "1") (pinfunction "1_1") (pintype "passive"))
      (node (ref "R1004") (pin "1") (pinfunction "1_1") (pintype "passive"))
      (node (ref "R1008") (pin "1") (pinfunction "1_1") (pintype "passive"))
      (node (ref "R1011") (pin "1") (pinfunction "1_1") (pintype "passive"))
      (node (ref "R1014") (pin "1") (pinfunction "1_1") (pintype "passive"))
      (node (ref "R1015") (pin "1") (pinfunction "1_1") (pintype "passive"))
      (node (ref "R201") (pin "1") (pinfunction "1_1") (pintype "passive"))
      (node (ref "R301") (pin "1") (pinfunction "1_1") (pintype "passive"))
      (node (ref "R501") (pin "1") (pinfunction "1_1") (pintype "passive"))
      (node (ref "R509") (pin "1") (pinfunction "1_1") (pintype "passive"))
      (node (ref "R510") (pin "2") (pinfunction "2_2") (pintype "passive"))
      (node (ref "R511") (pin "1") (pinfunction "1_1") (pintype "passive"))
      (node (ref "R512") (pin "2") (pinfunction "2_2") (pintype "passive"))
      (node (ref "R601") (pin "1") (pinfunction "1_1") (pintype "passive"))
      (node (ref "R602") (pin "1") (pinfunction "1_1") (pintype "passive"))
      (node (ref "R603") (pin "1") (pinfunction "1_1") (pintype "passive"))
      (node (ref "R606") (pin "1") (pinfunction "1_1") (pintype "passive"))
      (node (ref "R701") (pin "1") (pinfunction "1_1") (pintype "passive"))
      (node (ref "R702") (pin "1") (pinfunction "1_1") (pintype "passive"))
      (node (ref "R706") (pin "1") (pinfunction "1_1") (pintype "passive"))
      (node (ref "R708") (pin "1") (pinfunction "1_1") (pintype "passive"))
      (node (ref "R710") (pin "1") (pinfunction "1_1") (pintype "passive"))
      (node (ref "R711") (pin "1") (pinfunction "1_1") (pintype "passive"))
      (node (ref "R714") (pin "1") (pinfunction "1_1") (pintype "passive"))
      (node (ref "R715") (pin "1") (pinfunction "1_1") (pintype "passive"))
      (node (ref "R716") (pin "1") (pinfunction "1_1") (pintype "passive"))
      (node (ref "R802") (pin "1") (pinfunction "1_1") (pintype "passive"))
      (node (ref "R901") (pin "1") (pinfunction "1_1") (pintype "passive"))
      (node (ref "RFCON401") (pin "GND@0") (pinfunction "GND_GND@0") (pintype "bidirectional"))
      (node (ref "RFCON401") (pin "GND@1") (pinfunction "GND_GND@1") (pintype "bidirectional"))
      (node (ref "RFCON401") (pin "GND@2") (pinfunction "GND_GND@2") (pintype "bidirectional"))
      (node (ref "RFCON401") (pin "GND@3") (pinfunction "GND_GND@3") (pintype "bidirectional"))
      (node (ref "RFCON501") (pin "GND@0") (pinfunction "GND_GND@0") (pintype "bidirectional"))
      (node (ref "RFCON501") (pin "GND@1") (pinfunction "GND_GND@1") (pintype "bidirectional"))
      (node (ref "RFCON501") (pin "GND@2") (pinfunction "GND_GND@2") (pintype "bidirectional"))
      (node (ref "RFCON501") (pin "GND@3") (pinfunction "GND_GND@3") (pintype "bidirectional"))
      (node (ref "RFCON502") (pin "P$1") (pinfunction "GND_P$1") (pintype "bidirectional"))
      (node (ref "RFCON502") (pin "P$2") (pinfunction "GND_P$2") (pintype "bidirectional"))
      (node (ref "TC101") (pin "3") (pinfunction "S_3") (pintype "passive"))
      (node (ref "TC201") (pin "3") (pinfunction "S_3") (pintype "passive"))
      (node (ref "U1001") (pin "10") (pinfunction "PGND_10") (pintype "bidirectional"))
      (node (ref "U1001") (pin "11") (pinfunction "PGND_11") (pintype "bidirectional"))
      (node (ref "U1001") (pin "7") (pinfunction "AGND_7") (pintype "bidirectional"))
      (node (ref "U1002") (pin "19") (pinfunction "AGND_19") (pintype "bidirectional"))
      (node (ref "U1002") (pin "2") (pinfunction "PGND_2") (pintype "bidirectional"))
      (node (ref "U1002") (pin "21") (pinfunction "PGND_21") (pintype "bidirectional"))
      (node (ref "U1002") (pin "5") (pinfunction "PGND_5") (pintype "bidirectional"))
      (node (ref "U1002") (pin "8") (pinfunction "AGND_8") (pintype "bidirectional"))
      (node (ref "U1003") (pin "2") (pinfunction "GND_2") (pintype "bidirectional"))
      (node (ref "U1004") (pin "2") (pinfunction "GND_2") (pintype "bidirectional"))
      (node (ref "U1005") (pin "2") (pinfunction "GND_2") (pintype "bidirectional"))
      (node (ref "U1006") (pin "3") (pinfunction "GND_3") (pintype "bidirectional"))
      (node (ref "U1006") (pin "7") (pinfunction "GND_7") (pintype "bidirectional"))
      (node (ref "U1007") (pin "3") (pinfunction "GND_3") (pintype "bidirectional"))
      (node (ref "U1007") (pin "7") (pinfunction "GND_7") (pintype "bidirectional"))
      (node (ref "U101") (pin "C7") (pinfunction "VSS_C7") (pintype "bidirectional"))
      (node (ref "U101") (pin "D4") (pinfunction "VSS_D4") (pintype "bidirectional"))
      (node (ref "U101") (pin "F9") (pinfunction "VSS_F9") (pintype "bidirectional"))
      (node (ref "U101") (pin "G3") (pinfunction "VSS_G3") (pintype "bidirectional"))
      (node (ref "U101") (pin "G9") (pinfunction "VSS_G9") (pintype "bidirectional"))
      (node (ref "U101") (pin "H6") (pinfunction "VSS_H6") (pintype "bidirectional"))
      (node (ref "U101") (pin "K10") (pinfunction "VSS_K10") (pintype "bidirectional"))
      (node (ref "U101") (pin "K4") (pinfunction "VSS_K4") (pintype "bidirectional"))
      (node (ref "U101") (pin "K7") (pinfunction "VSS_K7") (pintype "bidirectional"))
      (node (ref "U101") (pin "L7") (pinfunction "VSS_L7") (pintype "bidirectional"))
      (node (ref "U201") (pin "D2") (pinfunction "VREFN_D2") (pintype "bidirectional"))
      (node (ref "U201") (pin "D5") (pinfunction "GNDANA_D5") (pintype "bidirectional"))
      (node (ref "U201") (pin "E5") (pinfunction "GNDUTMII_E5") (pintype "bidirectional"))
      (node (ref "U201") (pin "E6") (pinfunction "GNDPLLUSB_E6") (pintype "bidirectional"))
      (node (ref "U201") (pin "F5") (pinfunction "GND_F5") (pintype "bidirectional"))
      (node (ref "U201") (pin "F6") (pinfunction "GND_F6") (pintype "bidirectional"))
      (node (ref "U201") (pin "F7") (pinfunction "GNDPLL_F7") (pintype "bidirectional"))
      (node (ref "U201") (pin "G4") (pinfunction "GND_G4") (pintype "bidirectional"))
      (node (ref "U201") (pin "G5") (pinfunction "GND_G5") (pintype "bidirectional"))
      (node (ref "U201") (pin "G6") (pinfunction "GND_G6") (pintype "bidirectional"))
      (node (ref "U201") (pin "G7") (pinfunction "GND_G7") (pintype "bidirectional"))
      (node (ref "U301") (pin "A12") (pinfunction "GND_A12") (pintype "power_in"))
      (node (ref "U301") (pin "A4") (pinfunction "GND_A4") (pintype "power_in"))
      (node (ref "U301") (pin "E15") (pinfunction "GND_E15") (pintype "power_in"))
      (node (ref "U301") (pin "E7") (pinfunction "GNDPLL1_E7") (pintype "power_in"))
      (node (ref "U301") (pin "G7") (pinfunction "GND_G7") (pintype "power_in"))
      (node (ref "U301") (pin "G8") (pinfunction "GND_G8") (pintype "power_in"))
      (node (ref "U301") (pin "G9") (pinfunction "GND_G9") (pintype "power_in"))
      (node (ref "U301") (pin "H7") (pinfunction "GND_H7") (pintype "power_in"))
      (node (ref "U301") (pin "H8") (pinfunction "GND_H8") (pintype "power_in"))
      (node (ref "U301") (pin "H9") (pinfunction "GND_H9") (pintype "power_in"))
      (node (ref "U301") (pin "J7") (pinfunction "GND_J7") (pintype "power_in"))
      (node (ref "U301") (pin "J8") (pinfunction "GND_J8") (pintype "power_in"))
      (node (ref "U301") (pin "J9") (pinfunction "GND_J9") (pintype "power_in"))
      (node (ref "U301") (pin "K2") (pinfunction "GND_K2") (pintype "power_in"))
      (node (ref "U301") (pin "K7") (pinfunction "GND_K7") (pintype "power_in"))
      (node (ref "U301") (pin "L15") (pinfunction "GND_L15") (pintype "power_in"))
      (node (ref "U301") (pin "N8") (pinfunction "GNDPLL0_N8") (pintype "power_in"))
      (node (ref "U301") (pin "R7") (pinfunction "GND_R7") (pintype "power_in"))
      (node (ref "U301") (pin "T12") (pinfunction "GND_T12") (pintype "power_in"))
      (node (ref "U301") (pin "T4") (pinfunction "GND_T4") (pintype "power_in"))
      (node (ref "U302") (pin "4") (pinfunction "GND_4") (pintype "power_in"))
      (node (ref "U401") (pin "3") (pinfunction "GND_3") (pintype "power_in"))
      (node (ref "U402") (pin "11") (pinfunction "GND_11") (pintype "bidirectional"))
      (node (ref "U402") (pin "15") (pinfunction "GND_15") (pintype "bidirectional"))
      (node (ref "U402") (pin "23") (pinfunction "OGND_23") (pintype "bidirectional"))
      (node (ref "U402") (pin "31") (pinfunction "OGND_31") (pintype "bidirectional"))
      (node (ref "U402") (pin "38") (pinfunction "OGND_38") (pintype "bidirectional"))
      (node (ref "U402") (pin "46") (pinfunction "RAND_46") (pintype "bidirectional"))
      (node (ref "U402") (pin "48") (pinfunction "GND_48") (pintype "bidirectional"))
      (node (ref "U402") (pin "49") (pinfunction "GND_49") (pintype "bidirectional"))
      (node (ref "U402") (pin "5") (pinfunction "GND_5") (pintype "bidirectional"))
      (node (ref "U402") (pin "8") (pinfunction "GND_8") (pintype "bidirectional"))
      (node (ref "U403") (pin "16") (pinfunction "GND_16") (pintype "bidirectional"))
      (node (ref "U403") (pin "33") (pinfunction "GND_33") (pintype "bidirectional"))
      (node (ref "U501") (pin "15") (pinfunction "COMM2_15") (pintype "bidirectional"))
      (node (ref "U501") (pin "16") (pinfunction "COMM2_16") (pintype "bidirectional"))
      (node (ref "U501") (pin "19") (pinfunction "COMM3_19") (pintype "bidirectional"))
      (node (ref "U501") (pin "20") (pinfunction "COMM3_20") (pintype "bidirectional"))
      (node (ref "U501") (pin "33") (pinfunction "GND_33") (pintype "bidirectional"))
      (node (ref "U501") (pin "4") (pinfunction "COMM1_4") (pintype "bidirectional"))
      (node (ref "U501") (pin "5") (pinfunction "COMM1_5") (pintype "bidirectional"))
      (node (ref "U501") (pin "6") (pinfunction "COMM1_6") (pintype "bidirectional"))
      (node (ref "U502") (pin "19") (pinfunction "CVSS_19") (pintype "bidirectional"))
      (node (ref "U502") (pin "25") (pinfunction "AVSS_25") (pintype "bidirectional"))
      (node (ref "U502") (pin "41") (pinfunction "AVSS_41") (pintype "bidirectional"))
      (node (ref "U502") (pin "6") (pinfunction "DVSS_6") (pintype "bidirectional"))
      (node (ref "U503") (pin "2") (pinfunction "GND_2") (pintype "bidirectional"))
      (node (ref "U503") (pin "4") (pinfunction "GND_4") (pintype "bidirectional"))
      (node (ref "U601") (pin "3") (pinfunction "GND_3") (pintype "power_in"))
      (node (ref "U602") (pin "11") (pinfunction "AGNDVCO_11") (pintype "bidirectional"))
      (node (ref "U602") (pin "18") (pinfunction "AGNDVCO_18") (pintype "bidirectional"))
      (node (ref "U602") (pin "21") (pinfunction "AGNDVCO_21") (pintype "bidirectional"))
      (node (ref "U602") (pin "27") (pinfunction "DGND_27") (pintype "bidirectional"))
      (node (ref "U602") (pin "31") (pinfunction "SDGND_31") (pintype "bidirectional"))
      (node (ref "U602") (pin "33") (pinfunction "GND_33") (pintype "bidirectional"))
      (node (ref "U602") (pin "8") (pinfunction "CPGND_8") (pintype "bidirectional"))
      (node (ref "U602") (pin "9") (pinfunction "AGND_9") (pintype "bidirectional"))
      (node (ref "U701") (pin "41") (pinfunction "VSS_41") (pintype "bidirectional"))
      (node (ref "U701") (pin "8") (pinfunction "TEST_8") (pintype "bidirectional"))
      (node (ref "U702") (pin "3") (pinfunction "GND_3") (pintype "bidirectional"))
      (node (ref "U702") (pin "33") (pinfunction "GND_33") (pintype "bidirectional"))
      (node (ref "U801") (pin "11") (pinfunction "VSYNC_11") (pintype "bidirectional"))
      (node (ref "U801") (pin "12") (pinfunction "HSYNC_12") (pintype "bidirectional"))
      (node (ref "U801") (pin "13") (pinfunction "DOTCLK_13") (pintype "bidirectional"))
      (node (ref "U801") (pin "14") (pinfunction "DE_14") (pintype "bidirectional"))
      (node (ref "U801") (pin "15") (pinfunction "DB17_15") (pintype "bidirectional"))
      (node (ref "U801") (pin "16") (pinfunction "DB16_16") (pintype "bidirectional"))
      (node (ref "U801") (pin "17") (pinfunction "DB15_17") (pintype "bidirectional"))
      (node (ref "U801") (pin "18") (pinfunction "DB14_18") (pintype "bidirectional"))
      (node (ref "U801") (pin "19") (pinfunction "DB13_19") (pintype "bidirectional"))
      (node (ref "U801") (pin "20") (pinfunction "DB12_20") (pintype "bidirectional"))
      (node (ref "U801") (pin "21") (pinfunction "DB11_21") (pintype "bidirectional"))
      (node (ref "U801") (pin "22") (pinfunction "DB10_22") (pintype "bidirectional"))
      (node (ref "U801") (pin "23") (pinfunction "DB9_23") (pintype "bidirectional"))
      (node (ref "U801") (pin "24") (pinfunction "DB8_24") (pintype "bidirectional"))
      (node (ref "U801") (pin "25") (pinfunction "DB7_25") (pintype "bidirectional"))
      (node (ref "U801") (pin "26") (pinfunction "DB6_26") (pintype "bidirectional"))
      (node (ref "U801") (pin "27") (pinfunction "DB5_27") (pintype "bidirectional"))
      (node (ref "U801") (pin "28") (pinfunction "DB4_28") (pintype "bidirectional"))
      (node (ref "U801") (pin "29") (pinfunction "DB3_29") (pintype "bidirectional"))
      (node (ref "U801") (pin "30") (pinfunction "DB2_30") (pintype "bidirectional"))
      (node (ref "U801") (pin "31") (pinfunction "DB1_31") (pintype "bidirectional"))
      (node (ref "U801") (pin "32") (pinfunction "DB0_32") (pintype "bidirectional"))
      (node (ref "U801") (pin "43") (pinfunction "GND_43") (pintype "bidirectional"))
      (node (ref "U801") (pin "48") (pinfunction "GND_48") (pintype "bidirectional"))
      (node (ref "U801") (pin "49") (pinfunction "GND_49") (pintype "bidirectional"))
      (node (ref "U801") (pin "50") (pinfunction "GND_50") (pintype "bidirectional"))
      (node (ref "U901") (pin "3") (pinfunction "GND_3") (pintype "power_in"))
      (node (ref "U902") (pin "21") (pinfunction "GND_21") (pintype "bidirectional"))
      (node (ref "USB1001") (pin "A1/B12") (pinfunction "GND_A1/B12") (pintype "bidirectional"))
      (node (ref "USB1001") (pin "B1/A12") (pinfunction "GND_B1/A12") (pintype "bidirectional"))
      (node (ref "USB701") (pin "A1/B12") (pinfunction "GND_A1/B12") (pintype "bidirectional"))
      (node (ref "USB701") (pin "B1/A12") (pinfunction "GND_B1/A12") (pintype "bidirectional"))
      (node (ref "X401") (pin "1") (pinfunction "GND_1") (pintype "passive"))
      (node (ref "X401") (pin "3") (pinfunction "GND_3") (pintype "passive"))
      (node (ref "X901") (pin "1") (pinfunction "GND_1") (pintype "passive"))
      (node (ref "X901") (pin "3") (pinfunction "GND_3") (pintype "passive"))
    )
    (net (code "65") (name "I2S_BRG_D+") (class "Default")
      (node (ref "D701") (pin "4") (pinfunction "4_4") (pintype "bidirectional"))
      (node (ref "U702") (pin "4") (pinfunction "D+_4") (pintype "bidirectional"))
      (node (ref "USB701") (pin "A6") (pinfunction "D+_A6") (pintype "bidirectional"))
      (node (ref "USB701") (pin "B6") (pinfunction "D+_B6") (pintype "bidirectional"))
    )
    (net (code "66") (name "I2S_BRG_D-") (class "Default")
      (node (ref "D701") (pin "3") (pinfunction "3_3") (pintype "bidirectional"))
      (node (ref "U702") (pin "5") (pinfunction "D-_5") (pintype "bidirectional"))
      (node (ref "USB701") (pin "A7") (pinfunction "D-_A7") (pintype "bidirectional"))
      (node (ref "USB701") (pin "B7") (pinfunction "D-_B7") (pintype "bidirectional"))
    )
    (net (code "67") (name "I2S_BRG_VBUS_DET") (class "Default")
      (node (ref "R705") (pin "1") (pinfunction "1_1") (pintype "passive"))
      (node (ref "R706") (pin "2") (pinfunction "2_2") (pintype "passive"))
      (node (ref "U702") (pin "8") (pinfunction "VBUS_8") (pintype "bidirectional"))
    )
    (net (code "68") (name "Net-(C111-C1)") (class "Default")
      (node (ref "C111") (pin "1") (pinfunction "C1_1") (pintype "passive"))
      (node (ref "U101") (pin "F11") (pinfunction "DECOUPLE_F11") (pintype "bidirectional"))
    )
    (net (code "69") (name "Net-(C201-C1)") (class "Default")
      (node (ref "C201") (pin "1") (pinfunction "C1_1") (pintype "passive"))
      (node (ref "C202") (pin "1") (pinfunction "C1_1") (pintype "passive"))
      (node (ref "C204") (pin "1") (pinfunction "C1_1") (pintype "passive"))
      (node (ref "C206") (pin "1") (pinfunction "C1_1") (pintype "passive"))
      (node (ref "C208") (pin "1") (pinfunction "C1_1") (pintype "passive"))
      (node (ref "C210") (pin "1") (pinfunction "C1_1") (pintype "passive"))
      (node (ref "C212") (pin "1") (pinfunction "C1_1") (pintype "passive"))
      (node (ref "L201") (pin "1") (pinfunction "1_1") (pintype "passive"))
      (node (ref "L202") (pin "1") (pinfunction "1_1") (pintype "passive"))
      (node (ref "U201") (pin "C3") (pinfunction "VDDOUT_C3") (pintype "bidirectional"))
      (node (ref "U201") (pin "E8") (pinfunction "VDDCORE_E8") (pintype "bidirectional"))
      (node (ref "U201") (pin "H5") (pinfunction "VDDCORE_H5") (pintype "bidirectional"))
      (node (ref "U201") (pin "H8") (pinfunction "VDDCORE_H8") (pintype "bidirectional"))
    )
    (net (code "70") (name "Net-(C215-C1)") (class "Default")
      (node (ref "C215") (pin "1") (pinfunction "C1_1") (pintype "passive"))
      (node (ref "L201") (pin "2") (pinfunction "2_2") (pintype "passive"))
      (node (ref "U201") (pin "J7") (pinfunction "VDDPLL_J7") (pintype "bidirectional"))
    )
    (net (code "71") (name "Net-(C216-C1)") (class "Default")
      (node (ref "C216") (pin "1") (pinfunction "C1_1") (pintype "passive"))
      (node (ref "L202") (pin "2") (pinfunction "2_2") (pintype "passive"))
      (node (ref "U201") (pin "B3") (pinfunction "VDDUTMIC_B3") (pintype "bidirectional"))
    )
    (net (code "72") (name "Net-(C217-C1)") (class "Default")
      (node (ref "C217") (pin "1") (pinfunction "C1_1") (pintype "passive"))
      (node (ref "L203") (pin "2") (pinfunction "2_2") (pintype "passive"))
      (node (ref "U201") (pin "F8") (pinfunction "VDDPLLUSB_F8") (pintype "bidirectional"))
    )
    (net (code "73") (name "Net-(C218-C1)") (class "Default")
      (node (ref "C218") (pin "1") (pinfunction "C1_1") (pintype "passive"))
      (node (ref "R201") (pin "2") (pinfunction "2_2") (pintype "passive"))
      (node (ref "U201") (pin "C4") (pinfunction "VBG_C4") (pintype "bidirectional"))
    )
    (net (code "74") (name "Net-(C402-C1)") (class "Default")
      (node (ref "C402") (pin "1") (pinfunction "C1_1") (pintype "passive"))
      (node (ref "U402") (pin "9") (pinfunction "ENC+_9") (pintype "bidirectional"))
    )
    (net (code "75") (name "Net-(C410-C1)") (class "Default")
      (node (ref "C410") (pin "1") (pinfunction "C1_1") (pintype "passive"))
      (node (ref "R402") (pin "1") (pinfunction "1_1") (pintype "passive"))
      (node (ref "U403") (pin "8") (pinfunction "XTALI_8") (pintype "bidirectional"))
      (node (ref "X401") (pin "2") (pinfunction "1_2") (pintype "passive"))
    )
    (net (code "76") (name "Net-(C412-C1)") (class "Default")
      (node (ref "C412") (pin "1") (pinfunction "C1_1") (pintype "passive"))
      (node (ref "U403") (pin "9") (pinfunction "XTALO_9") (pintype "bidirectional"))
      (node (ref "X401") (pin "4") (pinfunction "2_4") (pintype "passive"))
    )
    (net (code "77") (name "Net-(C415-C1)") (class "Default")
      (node (ref "C415") (pin "1") (pinfunction "C1_1") (pintype "passive"))
      (node (ref "U403") (pin "17") (pinfunction "VDD_PLL_17") (pintype "bidirectional"))
    )
    (net (code "78") (name "Net-(C416-C1)") (class "Default")
      (node (ref "C416") (pin "1") (pinfunction "C1_1") (pintype "passive"))
      (node (ref "C419") (pin "1") (pinfunction "C1_1") (pintype "passive"))
      (node (ref "R406") (pin "2") (pinfunction "2_2") (pintype "passive"))
      (node (ref "U402") (pin "6") (pinfunction "AIN+_6") (pintype "bidirectional"))
    )
    (net (code "79") (name "Net-(C417-C2)") (class "Default")
      (node (ref "C417") (pin "2") (pinfunction "C2_2") (pintype "passive"))
      (node (ref "C419") (pin "2") (pinfunction "C2_2") (pintype "passive"))
      (node (ref "R407") (pin "2") (pinfunction "2_2") (pintype "passive"))
      (node (ref "U402") (pin "7") (pinfunction "AIN-_7") (pintype "bidirectional"))
    )
    (net (code "80") (name "Net-(C420-C1)") (class "Default")
      (node (ref "C420") (pin "1") (pinfunction "C1_1") (pintype "passive"))
      (node (ref "U403") (pin "4") (pinfunction "DET1_4") (pintype "bidirectional"))
    )
    (net (code "81") (name "Net-(C422-C1)") (class "Default")
      (node (ref "C422") (pin "1") (pinfunction "C1_1") (pintype "passive"))
      (node (ref "U403") (pin "5") (pinfunction "DET2_5") (pintype "bidirectional"))
    )
    (net (code "82") (name "Net-(C423-C1)") (class "Default")
      (node (ref "C423") (pin "1") (pinfunction "C1_1") (pintype "passive"))
      (node (ref "R409") (pin "2") (pinfunction "2_2") (pintype "passive"))
    )
    (net (code "83") (name "Net-(C424-C1)") (class "Default")
      (node (ref "C424") (pin "1") (pinfunction "C1_1") (pintype "passive"))
      (node (ref "R405") (pin "1") (pinfunction "1_1") (pintype "passive"))
      (node (ref "R408") (pin "1") (pinfunction "1_1") (pintype "passive"))
      (node (ref "U403") (pin "6") (pinfunction "SCL_6") (pintype "bidirectional"))
    )
    (net (code "84") (name "Net-(C427-C1)") (class "Default")
      (node (ref "C427") (pin "1") (pinfunction "C1_1") (pintype "passive"))
      (node (ref "R404") (pin "1") (pinfunction "1_1") (pintype "passive"))
      (node (ref "R410") (pin "1") (pinfunction "1_1") (pintype "passive"))
      (node (ref "U403") (pin "7") (pinfunction "SDA_7") (pintype "bidirectional"))
    )
    (net (code "85") (name "Net-(C428-C1)") (class "Default")
      (node (ref "C428") (pin "1") (pinfunction "C1_1") (pintype "passive"))
      (node (ref "R409") (pin "1") (pinfunction "1_1") (pintype "passive"))
      (node (ref "U403") (pin "15") (pinfunction "CP_15") (pintype "bidirectional"))
    )
    (net (code "86") (name "Net-(C429-C1)") (class "Default")
      (node (ref "C429") (pin "1") (pinfunction "C1_1") (pintype "passive"))
      (node (ref "TRF401") (pin "5") (pinfunction "PRI2_5") (pintype "passive"))
    )
    (net (code "87") (name "Net-(C429-C2)") (class "Default")
      (node (ref "C429") (pin "2") (pinfunction "C2_2") (pintype "passive"))
      (node (ref "R413") (pin "2") (pinfunction "2_2") (pintype "passive"))
      (node (ref "R415") (pin "2") (pinfunction "2_2") (pintype "passive"))
    )
    (net (code "88") (name "Net-(C430-C1)") (class "Default")
      (node (ref "C430") (pin "1") (pinfunction "C1_1") (pintype "passive"))
      (node (ref "TRF401") (pin "4") (pinfunction "PRI1_4") (pintype "passive"))
    )
    (net (code "89") (name "Net-(C430-C2)") (class "Default")
      (node (ref "C430") (pin "2") (pinfunction "C2_2") (pintype "passive"))
      (node (ref "R413") (pin "1") (pinfunction "1_1") (pintype "passive"))
      (node (ref "R416") (pin "2") (pinfunction "2_2") (pintype "passive"))
    )
    (net (code "90") (name "Net-(C431-C1)") (class "Default")
      (node (ref "C431") (pin "1") (pinfunction "C1_1") (pintype "passive"))
      (node (ref "R414") (pin "2") (pinfunction "2_2") (pintype "passive"))
      (node (ref "U403") (pin "14") (pinfunction "IF_AGC_14") (pintype "bidirectional"))
    )
    (net (code "91") (name "Net-(C432-C1)") (class "Default")
      (node (ref "C432") (pin "1") (pinfunction "C1_1") (pintype "passive"))
      (node (ref "L403") (pin "2") (pinfunction "2_2") (pintype "passive"))
    )
    (net (code "92") (name "Net-(C432-C2)") (class "Default")
      (node (ref "C432") (pin "2") (pinfunction "C2_2") (pintype "passive"))
      (node (ref "C433") (pin "1") (pinfunction "C1_1") (pintype "passive"))
      (node (ref "D401") (pin "3") (pinfunction "MID_3") (pintype "passive"))
    )
    (net (code "93") (name "Net-(C433-C2)") (class "Default")
      (node (ref "C433") (pin "2") (pinfunction "C2_2") (pintype "passive"))
      (node (ref "RFCON401") (pin "SIG") (pinfunction "SIGNAL_SIG") (pintype "bidirectional"))
    )
    (net (code "94") (name "Net-(C505-C1)") (class "Default")
      (node (ref "C505") (pin "1") (pinfunction "C1_1") (pintype "passive"))
      (node (ref "U502") (pin "7") (pinfunction "DVDD_7") (pintype "bidirectional"))
    )
    (net (code "95") (name "Net-(C507-C1)") (class "Default")
      (node (ref "C507") (pin "1") (pinfunction "C1_1") (pintype "passive"))
      (node (ref "R504") (pin "2") (pinfunction "2_2") (pintype "passive"))
      (node (ref "U501") (pin "10") (pinfunction "TEMP_10") (pintype "bidirectional"))
    )
    (net (code "96") (name "Net-(C508-C1)") (class "Default")
      (node (ref "C508") (pin "1") (pinfunction "C1_1") (pintype "passive"))
      (node (ref "U501") (pin "7") (pinfunction "VOUT_7") (pintype "bidirectional"))
    )
    (net (code "97") (name "Net-(C508-C2)") (class "Default")
      (node (ref "C508") (pin "2") (pinfunction "C2_2") (pintype "passive"))
      (node (ref "C511") (pin "1") (pinfunction "C1_1") (pintype "passive"))
      (node (ref "R506") (pin "2") (pinfunction "2_2") (pintype "passive"))
    )
    (net (code "98") (name "Net-(C511-C2)") (class "Default")
      (node (ref "C511") (pin "2") (pinfunction "C2_2") (pintype "passive"))
      (node (ref "R507") (pin "2") (pinfunction "2_2") (pintype "passive"))
      (node (ref "U503") (pin "1") (pinfunction "RFIN_1") (pintype "bidirectional"))
    )
    (net (code "99") (name "Net-(C513-C1)") (class "Default")
      (node (ref "C513") (pin "1") (pinfunction "C1_1") (pintype "passive"))
      (node (ref "R507") (pin "1") (pinfunction "1_1") (pintype "passive"))
    )
    (net (code "100") (name "Net-(C513-C2)") (class "Default")
      (node (ref "C513") (pin "2") (pinfunction "C2_2") (pintype "passive"))
      (node (ref "C515") (pin "1") (pinfunction "C1_1") (pintype "passive"))
      (node (ref "L501") (pin "1") (pinfunction "1_1") (pintype "passive"))
      (node (ref "U503") (pin "3") (pinfunction "RFOUT_3") (pintype "bidirectional"))
    )
    (net (code "101") (name "Net-(C515-C2)") (class "Default")
      (node (ref "C515") (pin "2") (pinfunction "C2_2") (pintype "passive"))
      (node (ref "RFCON501") (pin "SIG") (pinfunction "SIGNAL_SIG") (pintype "bidirectional"))
    )
    (net (code "102") (name "Net-(C516-C1)") (class "Default")
      (node (ref "C516") (pin "1") (pinfunction "C1_1") (pintype "passive"))
      (node (ref "U502") (pin "34") (pinfunction "REFIO_34") (pintype "bidirectional"))
    )
    (net (code "103") (name "Net-(C517-C1)") (class "Default")
      (node (ref "C517") (pin "1") (pinfunction "C1_1") (pintype "passive"))
      (node (ref "L502") (pin "1") (pinfunction "1_1") (pintype "passive"))
      (node (ref "R509") (pin "2") (pinfunction "2_2") (pintype "passive"))
      (node (ref "U502") (pin "28") (pinfunction "IOUTP_28") (pintype "bidirectional"))
    )
    (net (code "104") (name "Net-(C518-C2)") (class "Default")
      (node (ref "C518") (pin "2") (pinfunction "C2_2") (pintype "passive"))
      (node (ref "L503") (pin "1") (pinfunction "1_1") (pintype "passive"))
      (node (ref "R510") (pin "1") (pinfunction "1_1") (pintype "passive"))
      (node (ref "U502") (pin "29") (pinfunction "IOUTN_29") (pintype "bidirectional"))
    )
    (net (code "105") (name "Net-(C519-C1)") (class "Default")
      (node (ref "C519") (pin "1") (pinfunction "C1_1") (pintype "passive"))
      (node (ref "L504") (pin "1") (pinfunction "1_1") (pintype "passive"))
      (node (ref "R511") (pin "2") (pinfunction "2_2") (pintype "passive"))
      (node (ref "U502") (pin "23") (pinfunction "QOUTP_23") (pintype "bidirectional"))
    )
    (net (code "106") (name "Net-(C520-C2)") (class "Default")
      (node (ref "C520") (pin "2") (pinfunction "C2_2") (pintype "passive"))
      (node (ref "L505") (pin "1") (pinfunction "1_1") (pintype "passive"))
      (node (ref "R512") (pin "1") (pinfunction "1_1") (pintype "passive"))
      (node (ref "U502") (pin "22") (pinfunction "QOUTN_22") (pintype "bidirectional"))
    )
    (net (code "107") (name "Net-(C521-C1)") (class "Default")
      (node (ref "C521") (pin "1") (pinfunction "C1_1") (pintype "passive"))
      (node (ref "L502") (pin "2") (pinfunction "2_2") (pintype "passive"))
      (node (ref "L506") (pin "1") (pinfunction "1_1") (pintype "passive"))
    )
    (net (code "108") (name "Net-(C522-C2)") (class "Default")
      (node (ref "C522") (pin "2") (pinfunction "C2_2") (pintype "passive"))
      (node (ref "L503") (pin "2") (pinfunction "2_2") (pintype "passive"))
      (node (ref "L507") (pin "1") (pinfunction "1_1") (pintype "passive"))
    )
    (net (code "109") (name "Net-(C523-C1)") (class "Default")
      (node (ref "C523") (pin "1") (pinfunction "C1_1") (pintype "passive"))
      (node (ref "L504") (pin "2") (pinfunction "2_2") (pintype "passive"))
      (node (ref "L508") (pin "1") (pinfunction "1_1") (pintype "passive"))
    )
    (net (code "110") (name "Net-(C524-C2)") (class "Default")
      (node (ref "C524") (pin "2") (pinfunction "C2_2") (pintype "passive"))
      (node (ref "L505") (pin "2") (pinfunction "2_2") (pintype "passive"))
      (node (ref "L509") (pin "1") (pinfunction "1_1") (pintype "passive"))
    )
    (net (code "111") (name "Net-(C606-C1)") (class "Default")
      (node (ref "C606") (pin "1") (pinfunction "C1_1") (pintype "passive"))
      (node (ref "U601") (pin "4") (pinfunction "CLK_4") (pintype "output"))
    )
    (net (code "112") (name "Net-(C606-C2)") (class "Default")
      (node (ref "C606") (pin "2") (pinfunction "C2_2") (pintype "passive"))
      (node (ref "U602") (pin "29") (pinfunction "REFIN_29") (pintype "bidirectional"))
    )
    (net (code "113") (name "Net-(C607-C1)") (class "Default")
      (node (ref "C607") (pin "1") (pinfunction "C1_1") (pintype "passive"))
      (node (ref "C608") (pin "1") (pinfunction "C1_1") (pintype "passive"))
      (node (ref "U602") (pin "24") (pinfunction "VREF_24") (pintype "bidirectional"))
    )
    (net (code "114") (name "Net-(C609-C1)") (class "Default")
      (node (ref "C609") (pin "1") (pinfunction "C1_1") (pintype "passive"))
      (node (ref "C610") (pin "1") (pinfunction "C1_1") (pintype "passive"))
      (node (ref "U602") (pin "23") (pinfunction "VCOM_23") (pintype "bidirectional"))
    )
    (net (code "115") (name "Net-(C611-C1)") (class "Default")
      (node (ref "C611") (pin "1") (pinfunction "C1_1") (pintype "passive"))
      (node (ref "C612") (pin "1") (pinfunction "C1_1") (pintype "passive"))
      (node (ref "U602") (pin "19") (pinfunction "TEMP_19") (pintype "bidirectional"))
    )
    (net (code "116") (name "Net-(C613-C1)") (class "Default")
      (node (ref "C613") (pin "1") (pinfunction "C1_1") (pintype "passive"))
      (node (ref "L601") (pin "2") (pinfunction "2_2") (pintype "passive"))
      (node (ref "L603") (pin "1") (pinfunction "1_1") (pintype "passive"))
      (node (ref "R604") (pin "2") (pinfunction "2_2") (pintype "passive"))
      (node (ref "U602") (pin "12") (pinfunction "RFOUTA+_12") (pintype "bidirectional"))
    )
    (net (code "117") (name "Net-(C614-C2)") (class "Default")
      (node (ref "C614") (pin "2") (pinfunction "C2_2") (pintype "passive"))
      (node (ref "L602") (pin "1") (pinfunction "1_1") (pintype "passive"))
      (node (ref "L604") (pin "1") (pinfunction "1_1") (pintype "passive"))
      (node (ref "R604") (pin "1") (pinfunction "1_1") (pintype "passive"))
      (node (ref "U602") (pin "13") (pinfunction "RFOUTA-_13") (pintype "bidirectional"))
    )
    (net (code "118") (name "Net-(C615-C1)") (class "Default")
      (node (ref "C615") (pin "1") (pinfunction "C1_1") (pintype "passive"))
      (node (ref "C616") (pin "1") (pinfunction "C1_1") (pintype "passive"))
      (node (ref "R607") (pin "2") (pinfunction "2_2") (pintype "passive"))
      (node (ref "U602") (pin "7") (pinfunction "CPOUT_7") (pintype "bidirectional"))
    )
    (net (code "119") (name "Net-(C615-C2)") (class "Default")
      (node (ref "C615") (pin "2") (pinfunction "C2_2") (pintype "passive"))
      (node (ref "R605") (pin "1") (pinfunction "1_1") (pintype "passive"))
      (node (ref "R606") (pin "2") (pinfunction "2_2") (pintype "passive"))
    )
    (net (code "120") (name "Net-(C617-C1)") (class "Default")
      (node (ref "C617") (pin "1") (pinfunction "C1_1") (pintype "passive"))
      (node (ref "L603") (pin "2") (pinfunction "2_2") (pintype "passive"))
      (node (ref "L605") (pin "1") (pinfunction "1_1") (pintype "passive"))
    )
    (net (code "121") (name "Net-(C618-C2)") (class "Default")
      (node (ref "C618") (pin "2") (pinfunction "C2_2") (pintype "passive"))
      (node (ref "L604") (pin "2") (pinfunction "2_2") (pintype "passive"))
      (node (ref "L606") (pin "1") (pinfunction "1_1") (pintype "passive"))
    )
    (net (code "122") (name "Net-(C619-C1)") (class "Default")
      (node (ref "C619") (pin "1") (pinfunction "C1_1") (pintype "passive"))
      (node (ref "R607") (pin "1") (pinfunction "1_1") (pintype "passive"))
      (node (ref "U602") (pin "20") (pinfunction "VTUNE_20") (pintype "bidirectional"))
    )
    (net (code "123") (name "Net-(C620-C1)") (class "Default")
      (node (ref "C620") (pin "1") (pinfunction "C1_1") (pintype "passive"))
      (node (ref "C622") (pin "1") (pinfunction "C1_1") (pintype "passive"))
      (node (ref "L605") (pin "2") (pinfunction "2_2") (pintype "passive"))
    )
    (net (code "124") (name "Net-(C621-C2)") (class "Default")
      (node (ref "C621") (pin "2") (pinfunction "C2_2") (pintype "passive"))
      (node (ref "C623") (pin "1") (pinfunction "C1_1") (pintype "passive"))
      (node (ref "L606") (pin "2") (pinfunction "2_2") (pintype "passive"))
    )
    (net (code "125") (name "Net-(C706-C1)") (class "Default")
      (node (ref "C706") (pin "1") (pinfunction "C1_1") (pintype "passive"))
      (node (ref "D701") (pin "2") (pinfunction "2_2") (pintype "bidirectional"))
      (node (ref "R704") (pin "2") (pinfunction "2_2") (pintype "passive"))
      (node (ref "R705") (pin "2") (pinfunction "2_2") (pintype "passive"))
      (node (ref "USB701") (pin "A4/B9") (pinfunction "VBUS_A4/B9") (pintype "bidirectional"))
      (node (ref "USB701") (pin "B4/A9") (pinfunction "VBUS_B4/A9") (pintype "bidirectional"))
    )
    (net (code "126") (name "Net-(C707-C1)") (class "Default")
      (node (ref "C707") (pin "1") (pinfunction "C1_1") (pintype "passive"))
      (node (ref "U701") (pin "36") (pinfunction "CAP+_36") (pintype "bidirectional"))
    )
    (net (code "127") (name "Net-(C707-C2)") (class "Default")
      (node (ref "C707") (pin "2") (pinfunction "C2_2") (pintype "passive"))
      (node (ref "U701") (pin "35") (pinfunction "CAP-_35") (pintype "bidirectional"))
    )
    (net (code "128") (name "Net-(C708-C1)") (class "Default")
      (node (ref "C708") (pin "1") (pinfunction "C1_1") (pintype "passive"))
      (node (ref "U701") (pin "4") (pinfunction "AFILT2_4") (pintype "bidirectional"))
    )
    (net (code "129") (name "Net-(C709-C1)") (class "Default")
      (node (ref "C709") (pin "1") (pinfunction "C1_1") (pintype "passive"))
      (node (ref "U701") (pin "5") (pinfunction "AFILT1_5") (pintype "bidirectional"))
    )
    (net (code "130") (name "Net-(C710-C1)") (class "Default")
      (node (ref "C710") (pin "1") (pinfunction "C1_1") (pintype "passive"))
      (node (ref "U701") (pin "34") (pinfunction "V-_34") (pintype "bidirectional"))
    )
    (net (code "131") (name "Net-(C711-C1)") (class "Default")
      (node (ref "C711") (pin "1") (pinfunction "C1_1") (pintype "passive"))
      (node (ref "U701") (pin "2") (pinfunction "VREF_2") (pintype "bidirectional"))
    )
    (net (code "132") (name "Net-(C712-C1)") (class "Default")
      (node (ref "C712") (pin "1") (pinfunction "C1_1") (pintype "passive"))
      (node (ref "U701") (pin "38") (pinfunction "RIN1_38") (pintype "bidirectional"))
    )
    (net (code "133") (name "Net-(C712-C2)") (class "Default")
      (node (ref "C712") (pin "2") (pinfunction "C2_2") (pintype "passive"))
      (node (ref "L701") (pin "2") (pinfunction "2_2") (pintype "passive"))
      (node (ref "R709") (pin "1") (pinfunction "1_1") (pintype "passive"))
      (node (ref "R710") (pin "2") (pinfunction "2_2") (pintype "passive"))
    )
    (net (code "134") (name "Net-(C713-C1)") (class "Default")
      (node (ref "C713") (pin "1") (pinfunction "C1_1") (pintype "passive"))
      (node (ref "U701") (pin "40") (pinfunction "RIN2_40") (pintype "bidirectional"))
    )
    (net (code "135") (name "Net-(C713-C2)") (class "Default")
      (node (ref "C713") (pin "2") (pinfunction "C2_2") (pintype "passive"))
      (node (ref "L702") (pin "2") (pinfunction "2_2") (pintype "passive"))
      (node (ref "R711") (pin "2") (pinfunction "2_2") (pintype "passive"))
    )
    (net (code "136") (name "Net-(C714-C1)") (class "Default")
      (node (ref "C714") (pin "1") (pinfunction "C1_1") (pintype "passive"))
      (node (ref "U701") (pin "39") (pinfunction "LIN1_39") (pintype "bidirectional"))
    )
    (net (code "137") (name "Net-(C714-C2)") (class "Default")
      (node (ref "C714") (pin "2") (pinfunction "C2_2") (pintype "passive"))
      (node (ref "L705") (pin "2") (pinfunction "2_2") (pintype "passive"))
      (node (ref "R713") (pin "1") (pinfunction "1_1") (pintype "passive"))
      (node (ref "R714") (pin "2") (pinfunction "2_2") (pintype "passive"))
    )
    (net (code "138") (name "Net-(C715-C1)") (class "Default")
      (node (ref "C715") (pin "1") (pinfunction "C1_1") (pintype "passive"))
      (node (ref "U701") (pin "1") (pinfunction "LIN2_1") (pintype "bidirectional"))
    )
    (net (code "139") (name "Net-(C715-C2)") (class "Default")
      (node (ref "C715") (pin "2") (pinfunction "C2_2") (pintype "passive"))
      (node (ref "L706") (pin "2") (pinfunction "2_2") (pintype "passive"))
      (node (ref "R715") (pin "2") (pinfunction "2_2") (pintype "passive"))
    )
    (net (code "140") (name "Net-(C716-C1)") (class "Default")
      (node (ref "C716") (pin "1") (pinfunction "C1_1") (pintype "passive"))
      (node (ref "L703") (pin "2") (pinfunction "2_2") (pintype "passive"))
      (node (ref "U701") (pin "31") (pinfunction "HP_R_31") (pintype "bidirectional"))
    )
    (net (code "141") (name "Net-(C716-C2)") (class "Default")
      (node (ref "C716") (pin "2") (pinfunction "C2_2") (pintype "passive"))
      (node (ref "R708") (pin "2") (pinfunction "2_2") (pintype "passive"))
    )
    (net (code "142") (name "Net-(C717-C1)") (class "Default")
      (node (ref "C717") (pin "1") (pinfunction "C1_1") (pintype "passive"))
      (node (ref "L704") (pin "2") (pinfunction "2_2") (pintype "passive"))
      (node (ref "U701") (pin "32") (pinfunction "HP_L_32") (pintype "bidirectional"))
    )
    (net (code "143") (name "Net-(C717-C2)") (class "Default")
      (node (ref "C717") (pin "2") (pinfunction "C2_2") (pintype "passive"))
      (node (ref "R716") (pin "2") (pinfunction "2_2") (pintype "passive"))
    )
    (net (code "144") (name "Net-(C719-C1)") (class "Default")
      (node (ref "C719") (pin "1") (pinfunction "C1_1") (pintype "passive"))
      (node (ref "R709") (pin "2") (pinfunction "2_2") (pintype "passive"))
      (node (ref "R713") (pin "2") (pinfunction "2_2") (pintype "passive"))
      (node (ref "U701") (pin "30") (pinfunction "MICBIAS_30") (pintype "bidirectional"))
    )
    (net (code "145") (name "Net-(C721-C1)") (class "Default")
      (node (ref "C721") (pin "1") (pinfunction "C1_1") (pintype "passive"))
      (node (ref "J701") (pin "3") (pinfunction "R_3") (pintype "bidirectional"))
      (node (ref "L701") (pin "1") (pinfunction "1_1") (pintype "passive"))
    )
    (net (code "146") (name "Net-(C722-C1)") (class "Default")
      (node (ref "C722") (pin "1") (pinfunction "C1_1") (pintype "passive"))
      (node (ref "J702") (pin "3") (pinfunction "R_3") (pintype "bidirectional"))
      (node (ref "L702") (pin "1") (pinfunction "1_1") (pintype "passive"))
    )
    (net (code "147") (name "Net-(C723-C1)") (class "Default")
      (node (ref "C723") (pin "1") (pinfunction "C1_1") (pintype "passive"))
      (node (ref "J703") (pin "3") (pinfunction "R_3") (pintype "bidirectional"))
      (node (ref "L703") (pin "1") (pinfunction "1_1") (pintype "passive"))
    )
    (net (code "148") (name "Net-(C724-C1)") (class "Default")
      (node (ref "C724") (pin "1") (pinfunction "C1_1") (pintype "passive"))
      (node (ref "J701") (pin "2") (pinfunction "T_2") (pintype "bidirectional"))
      (node (ref "L705") (pin "1") (pinfunction "1_1") (pintype "passive"))
    )
    (net (code "149") (name "Net-(C725-C1)") (class "Default")
      (node (ref "C725") (pin "1") (pinfunction "C1_1") (pintype "passive"))
      (node (ref "J702") (pin "2") (pinfunction "T_2") (pintype "bidirectional"))
      (node (ref "L706") (pin "1") (pinfunction "1_1") (pintype "passive"))
    )
    (net (code "150") (name "Net-(C726-C1)") (class "Default")
      (node (ref "C726") (pin "1") (pinfunction "C1_1") (pintype "passive"))
      (node (ref "J703") (pin "2") (pinfunction "T_2") (pintype "bidirectional"))
      (node (ref "L704") (pin "1") (pinfunction "1_1") (pintype "passive"))
    )
    (net (code "151") (name "Net-(C903-C1)") (class "Default")
      (node (ref "C903") (pin "1") (pinfunction "C1_1") (pintype "passive"))
      (node (ref "U902") (pin "1") (pinfunction "XA_1") (pintype "bidirectional"))
      (node (ref "X901") (pin "2") (pinfunction "1_2") (pintype "passive"))
    )
    (net (code "152") (name "Net-(C906-C1)") (class "Default")
      (node (ref "C906") (pin "1") (pinfunction "C1_1") (pintype "passive"))
      (node (ref "U902") (pin "2") (pinfunction "XB_2") (pintype "bidirectional"))
      (node (ref "X901") (pin "4") (pinfunction "2_4") (pintype "passive"))
    )
    (net (code "153") (name "Net-(C1005-C1)") (class "Default")
      (node (ref "C1005") (pin "1") (pinfunction "C1_1") (pintype "passive"))
      (node (ref "U1001") (pin "6") (pinfunction "SS_6") (pintype "bidirectional"))
    )
    (net (code "154") (name "Net-(C1008-C1)") (class "Default")
      (node (ref "C1008") (pin "1") (pinfunction "C1_1") (pintype "passive"))
      (node (ref "U1002") (pin "14") (pinfunction "SS_14") (pintype "bidirectional"))
    )
    (net (code "155") (name "Net-(C1009-C1)") (class "Default")
      (node (ref "C1009") (pin "1") (pinfunction "C1_1") (pintype "passive"))
      (node (ref "D1001") (pin "2") (pinfunction "2_2") (pintype "bidirectional"))
      (node (ref "F1001") (pin "1") (pinfunction "1_1") (pintype "passive"))
      (node (ref "L1003") (pin "1") (pinfunction "1_1") (pintype "passive"))
    )
    (net (code "156") (name "Net-(C1012-C1)") (class "Default")
      (node (ref "C1012") (pin "1") (pinfunction "C1_1") (pintype "passive"))
      (node (ref "U1002") (pin "13") (pinfunction "SS_13") (pintype "bidirectional"))
    )
    (net (code "157") (name "Net-(CON301AA-S)") (class "Default")
      (node (ref "CON301") (pin "33") (pinfunction "S_33") (pintype "passive"))
      (node (ref "U301") (pin "M6") (pinfunction "IOL_22A_M6") (pintype "bidirectional"))
    )
    (net (code "158") (name "Net-(CON301AB-S)") (class "Default")
      (node (ref "CON301") (pin "34") (pinfunction "S_34") (pintype "passive"))
      (node (ref "U301") (pin "P4") (pinfunction "IOB_54_P4") (pintype "bidirectional"))
    )
    (net (code "159") (name "Net-(CON301AC-S)") (class "Default")
      (node (ref "CON301") (pin "35") (pinfunction "S_35") (pintype "passive"))
      (node (ref "U301") (pin "P5") (pinfunction "IOB_58_P5") (pintype "bidirectional"))
    )
    (net (code "160") (name "Net-(CON301AD-S)") (class "Default")
      (node (ref "CON301") (pin "36") (pinfunction "S_36") (pintype "passive"))
      (node (ref "U301") (pin "N6") (pinfunction "IOB_52_N6") (pintype "bidirectional"))
    )
    (net (code "161") (name "Net-(CON301AE-S)") (class "Default")
      (node (ref "CON301") (pin "37") (pinfunction "S_37") (pintype "passive"))
      (node (ref "U301") (pin "L6") (pinfunction "IOL_19A_L6") (pintype "bidirectional"))
    )
    (net (code "162") (name "Net-(CON301AF-S)") (class "Default")
      (node (ref "CON301") (pin "38") (pinfunction "S_38") (pintype "passive"))
      (node (ref "U301") (pin "N7") (pinfunction "IOB_66_N7") (pintype "bidirectional"))
    )
    (net (code "163") (name "Net-(CON301AH-S)") (class "Default")
      (node (ref "CON301") (pin "4") (pinfunction "S_4") (pintype "passive"))
      (node (ref "U301") (pin "E4") (pinfunction "IOL_1A_E4") (pintype "bidirectional"))
    )
    (net (code "164") (name "Net-(CON301AJ-S)") (class "Default")
      (node (ref "CON301") (pin "5") (pinfunction "S_5") (pintype "passive"))
      (node (ref "U301") (pin "E3") (pinfunction "IOL_6B_E3") (pintype "bidirectional"))
    )
    (net (code "165") (name "Net-(CON301AK-S)") (class "Default")
      (node (ref "CON301") (pin "6") (pinfunction "S_6") (pintype "passive"))
      (node (ref "U301") (pin "E2") (pinfunction "IOL_7B_E2") (pintype "bidirectional"))
    )
    (net (code "166") (name "Net-(CON301AL-S)") (class "Default")
      (node (ref "CON301") (pin "7") (pinfunction "S_7") (pintype "passive"))
      (node (ref "U301") (pin "F3") (pinfunction "IOL_8B_F3") (pintype "bidirectional"))
    )
    (net (code "167") (name "Net-(CON301AM-S)") (class "Default")
      (node (ref "CON301") (pin "8") (pinfunction "S_8") (pintype "passive"))
      (node (ref "U301") (pin "F2") (pinfunction "IOL_9B_F2") (pintype "bidirectional"))
    )
    (net (code "168") (name "Net-(CON301AN-S)") (class "Default")
      (node (ref "CON301") (pin "9") (pinfunction "S_9") (pintype "passive"))
      (node (ref "U301") (pin "F1") (pinfunction "IOL_10B_F1") (pintype "bidirectional"))
    )
    (net (code "169") (name "Net-(CON301B-S)") (class "Default")
      (node (ref "CON301") (pin "10") (pinfunction "S_10") (pintype "passive"))
      (node (ref "U301") (pin "G2") (pinfunction "IOL_11B_G2") (pintype "bidirectional"))
    )
    (net (code "170") (name "Net-(CON301C-S)") (class "Default")
      (node (ref "CON301") (pin "11") (pinfunction "S_11") (pintype "passive"))
      (node (ref "U301") (pin "G1") (pinfunction "IOL_13B_GBIN7_G1") (pintype "bidirectional"))
    )
    (net (code "171") (name "Net-(CON301D-S)") (class "Default")
      (node (ref "CON301") (pin "12") (pinfunction "S_12") (pintype "passive"))
      (node (ref "U301") (pin "H2") (pinfunction "IOL_12B_H2") (pintype "bidirectional"))
    )
    (net (code "172") (name "Net-(CON301E-S)") (class "Default")
      (node (ref "CON301") (pin "13") (pinfunction "S_13") (pintype "passive"))
      (node (ref "U301") (pin "H1") (pinfunction "IOL_14B_H1") (pintype "bidirectional"))
    )
    (net (code "173") (name "Net-(CON301F-S)") (class "Default")
      (node (ref "CON301") (pin "14") (pinfunction "S_14") (pintype "passive"))
      (node (ref "U301") (pin "H3") (pinfunction "IOL_9A_H3") (pintype "bidirectional"))
    )
    (net (code "174") (name "Net-(CON301G-S)") (class "Default")
      (node (ref "CON301") (pin "15") (pinfunction "S_15") (pintype "passive"))
      (node (ref "U301") (pin "J1") (pinfunction "IOL_15B_J1") (pintype "bidirectional"))
    )
    (net (code "175") (name "Net-(CON301H-S)") (class "Default")
      (node (ref "CON301") (pin "16") (pinfunction "S_16") (pintype "passive"))
      (node (ref "U301") (pin "J2") (pinfunction "IOL_15A_J2") (pintype "bidirectional"))
    )
    (net (code "176") (name "Net-(CON301I-S)") (class "Default")
      (node (ref "CON301") (pin "17") (pinfunction "S_17") (pintype "passive"))
      (node (ref "U301") (pin "K1") (pinfunction "IOL_16A_K1") (pintype "bidirectional"))
    )
    (net (code "177") (name "Net-(CON301J-S)") (class "Default")
      (node (ref "CON301") (pin "18") (pinfunction "S_18") (pintype "passive"))
      (node (ref "U301") (pin "L1") (pinfunction "IOL_17B_L1") (pintype "bidirectional"))
    )
    (net (code "178") (name "Net-(CON301P-S)") (class "Default")
      (node (ref "CON301") (pin "23") (pinfunction "S_23") (pintype "passive"))
      (node (ref "U301") (pin "K3") (pinfunction "IOL_16B_K3") (pintype "bidirectional"))
    )
    (net (code "179") (name "Net-(CON301Q-S)") (class "Default")
      (node (ref "CON301") (pin "24") (pinfunction "S_24") (pintype "passive"))
      (node (ref "U301") (pin "K4") (pinfunction "IOL_18A_K4") (pintype "bidirectional"))
    )
    (net (code "180") (name "Net-(CON301R-S)") (class "Default")
      (node (ref "CON301") (pin "25") (pinfunction "S_25") (pintype "passive"))
      (node (ref "U301") (pin "L4") (pinfunction "IOL_17A_L4") (pintype "bidirectional"))
    )
    (net (code "181") (name "Net-(CON301S-S)") (class "Default")
      (node (ref "CON301") (pin "26") (pinfunction "S_26") (pintype "passive"))
      (node (ref "U301") (pin "L3") (pinfunction "IOL_19B_L3") (pintype "bidirectional"))
    )
    (net (code "182") (name "Net-(CON301T-S)") (class "Default")
      (node (ref "CON301") (pin "27") (pinfunction "S_27") (pintype "passive"))
      (node (ref "U301") (pin "M1") (pinfunction "IOL_18B_M1") (pintype "bidirectional"))
    )
    (net (code "183") (name "Net-(CON301U-S)") (class "Default")
      (node (ref "CON301") (pin "28") (pinfunction "S_28") (pintype "passive"))
      (node (ref "U301") (pin "M2") (pinfunction "IOL_20B_M2") (pintype "bidirectional"))
    )
    (net (code "184") (name "Net-(CON301V-S)") (class "Default")
      (node (ref "CON301") (pin "29") (pinfunction "S_29") (pintype "passive"))
      (node (ref "U301") (pin "M3") (pinfunction "IOL_22B_M3") (pintype "bidirectional"))
    )
    (net (code "185") (name "Net-(CON301W-S)") (class "Default")
      (node (ref "CON301") (pin "3") (pinfunction "S_3") (pintype "passive"))
      (node (ref "U301") (pin "E5") (pinfunction "IOT_225_E5") (pintype "bidirectional"))
    )
    (net (code "186") (name "Net-(CON301X-S)") (class "Default")
      (node (ref "CON301") (pin "30") (pinfunction "S_30") (pintype "passive"))
      (node (ref "U301") (pin "M4") (pinfunction "IOL_24B_M4") (pintype "bidirectional"))
    )
    (net (code "187") (name "Net-(CON301Y-S)") (class "Default")
      (node (ref "CON301") (pin "31") (pinfunction "S_31") (pintype "passive"))
      (node (ref "U301") (pin "M5") (pinfunction "IOL_25B_M5") (pintype "bidirectional"))
    )
    (net (code "188") (name "Net-(CON301Z-S)") (class "Default")
      (node (ref "CON301") (pin "32") (pinfunction "S_32") (pintype "passive"))
      (node (ref "U301") (pin "L5") (pinfunction "IOL_23A_L5") (pintype "bidirectional"))
    )
    (net (code "189") (name "Net-(D101-A)") (class "Default")
      (node (ref "D101") (pin "2") (pinfunction "A_2") (pintype "passive"))
      (node (ref "R103") (pin "1") (pinfunction "1_1") (pintype "passive"))
    )
    (net (code "190") (name "Net-(D201-A)") (class "Default")
      (node (ref "D201") (pin "2") (pinfunction "A_2") (pintype "passive"))
      (node (ref "R203") (pin "1") (pinfunction "1_1") (pintype "passive"))
    )
    (net (code "191") (name "Net-(D301A-A)") (class "Default")
      (node (ref "D301") (pin "3") (pinfunction "A_3") (pintype "passive"))
      (node (ref "R304") (pin "2") (pinfunction "2_2") (pintype "passive"))
    )
    (net (code "192") (name "Net-(D301B-A)") (class "Default")
      (node (ref "D301") (pin "1") (pinfunction "A_1") (pintype "passive"))
      (node (ref "R303") (pin "2") (pinfunction "2_2") (pintype "passive"))
    )
    (net (code "193") (name "Net-(D301C-A)") (class "Default")
      (node (ref "D301") (pin "2") (pinfunction "A_2") (pintype "passive"))
      (node (ref "R302") (pin "2") (pinfunction "2_2") (pintype "passive"))
    )
    (net (code "194") (name "Net-(D501-A)") (class "Default")
      (node (ref "D501") (pin "2") (pinfunction "A_2") (pintype "passive"))
      (node (ref "R508") (pin "1") (pinfunction "1_1") (pintype "passive"))
    )
    (net (code "195") (name "Net-(D702-A)") (class "Default")
      (node (ref "D702") (pin "2") (pinfunction "A_2") (pintype "passive"))
      (node (ref "R704") (pin "1") (pinfunction "1_1") (pintype "passive"))
    )
    (net (code "196") (name "Net-(D1002-A)") (class "Default")
      (node (ref "D1002") (pin "2") (pinfunction "A_2") (pintype "passive"))
      (node (ref "R1012") (pin "1") (pinfunction "1_1") (pintype "passive"))
    )
    (net (code "197") (name "Net-(D1003-A)") (class "Default")
      (node (ref "D1003") (pin "2") (pinfunction "A_2") (pintype "passive"))
      (node (ref "R1013") (pin "1") (pinfunction "1_1") (pintype "passive"))
    )
    (net (code "198") (name "Net-(F1001-Pad2)") (class "Default")
      (node (ref "F1001") (pin "2") (pinfunction "2_2") (pintype "passive"))
      (node (ref "USB1001") (pin "A4/B9") (pinfunction "VBUS_A4/B9") (pintype "bidirectional"))
      (node (ref "USB1001") (pin "B4/A9") (pinfunction "VBUS_B4/A9") (pintype "bidirectional"))
    )
    (net (code "199") (name "Net-(J703-DT)") (class "Default")
      (node (ref "J703") (pin "4") (pinfunction "DT_4") (pintype "bidirectional"))
      (node (ref "U701") (pin "29") (pinfunction "HP_DET_29") (pintype "bidirectional"))
    )
    (net (code "200") (name "Net-(L203-Pad1)") (class "Default")
      (node (ref "L203") (pin "1") (pinfunction "1_1") (pintype "passive"))
      (node (ref "R202") (pin "1") (pinfunction "1_1") (pintype "passive"))
    )
    (net (code "201") (name "Net-(L1001-Pad2)") (class "Default")
      (node (ref "L1001") (pin "2") (pinfunction "2_2") (pintype "passive"))
      (node (ref "U1002") (pin "3") (pinfunction "SW_3") (pintype "bidirectional"))
    )
    (net (code "202") (name "Net-(L1004-Pad1)") (class "Default")
      (node (ref "L1004") (pin "1") (pinfunction "1_1") (pintype "passive"))
      (node (ref "U1002") (pin "4") (pinfunction "SW_4") (pintype "bidirectional"))
    )
    (net (code "203") (name "Net-(Q801-D)") (class "Default")
      (node (ref "Q801") (pin "3") (pinfunction "D_3") (pintype "passive"))
      (node (ref "R803") (pin "1") (pinfunction "1_1") (pintype "passive"))
    )
    (net (code "204") (name "Net-(Q801-G)") (class "Default")
      (node (ref "Q801") (pin "1") (pinfunction "G_1") (pintype "passive"))
      (node (ref "Q802") (pin "1") (pinfunction "G_1") (pintype "passive"))
      (node (ref "R801") (pin "1") (pinfunction "1_1") (pintype "passive"))
      (node (ref "R802") (pin "2") (pinfunction "2_2") (pintype "passive"))
    )
    (net (code "205") (name "Net-(Q802-D)") (class "Default")
      (node (ref "Q802") (pin "3") (pinfunction "D_3") (pintype "passive"))
      (node (ref "R804") (pin "1") (pinfunction "1_1") (pintype "passive"))
    )
    (net (code "206") (name "Net-(R803-Pad2)") (class "Default")
      (node (ref "R803") (pin "2") (pinfunction "2_2") (pintype "passive"))
      (node (ref "U801") (pin "2") (pinfunction "LEDK_2") (pintype "bidirectional"))
    )
    (net (code "207") (name "Net-(R804-Pad2)") (class "Default")
      (node (ref "R804") (pin "2") (pinfunction "2_2") (pintype "passive"))
      (node (ref "U801") (pin "3") (pinfunction "LEDK_3") (pintype "bidirectional"))
    )
    (net (code "208") (name "Net-(R1003-Pad1)") (class "Default")
      (node (ref "R1003") (pin "1") (pinfunction "1_1") (pintype "passive"))
      (node (ref "R1004") (pin "2") (pinfunction "2_2") (pintype "passive"))
      (node (ref "U1002") (pin "16") (pinfunction "FB_16") (pintype "bidirectional"))
    )
    (net (code "209") (name "Net-(R1010-Pad1)") (class "Default")
      (node (ref "R1010") (pin "1") (pinfunction "1_1") (pintype "passive"))
      (node (ref "R1011") (pin "2") (pinfunction "2_2") (pintype "passive"))
      (node (ref "U1002") (pin "11") (pinfunction "FB_11") (pintype "bidirectional"))
    )
    (net (code "210") (name "Net-(RFCON502-SIGNAL)") (class "Default")
      (node (ref "R506") (pin "1") (pinfunction "1_1") (pintype "passive"))
      (node (ref "RFCON502") (pin "P$3") (pinfunction "SIGNAL_P$3") (pintype "bidirectional"))
    )
    (net (code "211") (name "Net-(TC201H-S)") (class "Default")
      (node (ref "SJ201") (pin "2") (pinfunction "2_2") (pintype "passive"))
      (node (ref "TC201") (pin "7") (pinfunction "S_7") (pintype "passive"))
    )
    (net (code "212") (name "Net-(TRF401-SEC1)") (class "Default")
      (node (ref "R407") (pin "1") (pinfunction "1_1") (pintype "passive"))
      (node (ref "R412") (pin "1") (pinfunction "1_1") (pintype "passive"))
      (node (ref "TRF401") (pin "3") (pinfunction "SEC1_3") (pintype "passive"))
    )
    (net (code "213") (name "Net-(TRF401-SEC2)") (class "Default")
      (node (ref "R406") (pin "1") (pinfunction "1_1") (pintype "passive"))
      (node (ref "R411") (pin "2") (pinfunction "2_2") (pintype "passive"))
      (node (ref "TRF401") (pin "1") (pinfunction "SEC2_1") (pintype "passive"))
    )
    (net (code "214") (name "Net-(U201F-JTAGSEL)") (class "Default")
      (node (ref "TP1") (pin "TP") (pinfunction "TP_TP") (pintype "input"))
      (node (ref "U201") (pin "B11") (pinfunction "JTAGSEL_B11") (pintype "bidirectional"))
    )
    (net (code "215") (name "Net-(U201F-TST)") (class "Default")
      (node (ref "TP2") (pin "TP") (pinfunction "TP_TP") (pintype "input"))
      (node (ref "U201") (pin "H11") (pinfunction "TST_H11") (pintype "bidirectional"))
    )
    (net (code "216") (name "Net-(U301E-VPP_FAST)") (class "Default")
      (node (ref "TP3") (pin "TP") (pinfunction "TP_TP") (pintype "input"))
      (node (ref "U301") (pin "D12") (pinfunction "VPP_FAST_D12") (pintype "power_in"))
    )
    (net (code "217") (name "Net-(U401-CLK)") (class "Default")
      (node (ref "R402") (pin "2") (pinfunction "2_2") (pintype "passive"))
      (node (ref "U401") (pin "4") (pinfunction "CLK_4") (pintype "output"))
    )
    (net (code "218") (name "Net-(U402-SENSE)") (class "Default")
      (node (ref "R403") (pin "2") (pinfunction "2_2") (pintype "passive"))
      (node (ref "U402") (pin "1") (pinfunction "SENSE_1") (pintype "bidirectional"))
    )
    (net (code "219") (name "Net-(U403-RFIN)") (class "Default")
      (node (ref "L403") (pin "1") (pinfunction "1_1") (pintype "passive"))
      (node (ref "U403") (pin "24") (pinfunction "RFIN_24") (pintype "bidirectional"))
    )
    (net (code "220") (name "Net-(U403-TF1N)") (class "Default")
      (node (ref "L401") (pin "2") (pinfunction "2_2") (pintype "passive"))
      (node (ref "U403") (pin "21") (pinfunction "TF1N_21") (pintype "bidirectional"))
    )
    (net (code "221") (name "Net-(U403-TF1P)") (class "Default")
      (node (ref "L402") (pin "2") (pinfunction "2_2") (pintype "passive"))
      (node (ref "U403") (pin "22") (pinfunction "TF1P_22") (pintype "bidirectional"))
    )
    (net (code "222") (name "Net-(U403-TF2N)") (class "Default")
      (node (ref "L401") (pin "1") (pinfunction "1_1") (pintype "passive"))
      (node (ref "U403") (pin "19") (pinfunction "TF2N_19") (pintype "bidirectional"))
    )
    (net (code "223") (name "Net-(U403-TF2P)") (class "Default")
      (node (ref "L402") (pin "1") (pinfunction "1_1") (pintype "passive"))
      (node (ref "U403") (pin "20") (pinfunction "TF2P_20") (pintype "bidirectional"))
    )
    (net (code "224") (name "Net-(U602-RSET)") (class "Default")
      (node (ref "R603") (pin "2") (pinfunction "2_2") (pintype "passive"))
      (node (ref "U602") (pin "22") (pinfunction "RSET_22") (pintype "bidirectional"))
    )
    (net (code "225") (name "Net-(U602-SW)") (class "Default")
      (node (ref "R605") (pin "2") (pinfunction "2_2") (pintype "passive"))
      (node (ref "U602") (pin "5") (pinfunction "SW_5") (pintype "bidirectional"))
    )
    (net (code "226") (name "Net-(U901-CLK)") (class "Default")
      (node (ref "U901") (pin "4") (pinfunction "CLK_4") (pintype "output"))
      (node (ref "U902") (pin "6") (pinfunction "CLKIN_6") (pintype "bidirectional"))
    )
    (net (code "227") (name "Net-(U902-CLK0)") (class "Default")
      (node (ref "R904") (pin "2") (pinfunction "2_2") (pintype "passive"))
      (node (ref "U902") (pin "13") (pinfunction "CLK0_13") (pintype "bidirectional"))
    )
    (net (code "228") (name "Net-(U902-CLK1)") (class "Default")
      (node (ref "R907") (pin "2") (pinfunction "2_2") (pintype "passive"))
      (node (ref "U902") (pin "12") (pinfunction "CLK1_12") (pintype "bidirectional"))
    )
    (net (code "229") (name "Net-(U902-CLK2)") (class "Default")
      (node (ref "R905") (pin "2") (pinfunction "2_2") (pintype "passive"))
      (node (ref "U902") (pin "9") (pinfunction "CLK2_9") (pintype "bidirectional"))
    )
    (net (code "230") (name "Net-(U902-CLK3)") (class "Default")
      (node (ref "R908") (pin "2") (pinfunction "2_2") (pintype "passive"))
      (node (ref "U902") (pin "8") (pinfunction "CLK3_8") (pintype "bidirectional"))
    )
    (net (code "231") (name "Net-(U902-CLK5)") (class "Default")
      (node (ref "R909") (pin "2") (pinfunction "2_2") (pintype "passive"))
      (node (ref "U902") (pin "17") (pinfunction "CLK5_17") (pintype "bidirectional"))
    )
    (net (code "232") (name "Net-(U902-CLK6)") (class "Default")
      (node (ref "R906") (pin "2") (pinfunction "2_2") (pintype "passive"))
      (node (ref "U902") (pin "16") (pinfunction "CLK6_16") (pintype "bidirectional"))
    )
    (net (code "233") (name "Net-(U1001-FB)") (class "Default")
      (node (ref "R1007") (pin "1") (pinfunction "1_1") (pintype "passive"))
      (node (ref "R1008") (pin "2") (pinfunction "2_2") (pintype "passive"))
      (node (ref "U1001") (pin "4") (pinfunction "FB_4") (pintype "bidirectional"))
    )
    (net (code "234") (name "Net-(U1001-SW)") (class "Default")
      (node (ref "L1002") (pin "1") (pinfunction "1_1") (pintype "passive"))
      (node (ref "U1001") (pin "1") (pinfunction "SW_1") (pintype "bidirectional"))
    )
    (net (code "235") (name "Net-(U1003-ILIMIT)") (class "Default")
      (node (ref "R1015") (pin "2") (pinfunction "2_2") (pintype "passive"))
      (node (ref "U1003") (pin "5") (pinfunction "ILIMIT_5") (pintype "bidirectional"))
    )
    (net (code "236") (name "Net-(USB701-CC1)") (class "Default")
      (node (ref "R702") (pin "2") (pinfunction "2_2") (pintype "passive"))
      (node (ref "USB701") (pin "A5") (pinfunction "CC1_A5") (pintype "bidirectional"))
    )
    (net (code "237") (name "Net-(USB701-CC2)") (class "Default")
      (node (ref "R701") (pin "2") (pinfunction "2_2") (pintype "passive"))
      (node (ref "USB701") (pin "B5") (pinfunction "CC2_B5") (pintype "bidirectional"))
    )
    (net (code "238") (name "Net-(USB1001-CC1)") (class "Default")
      (node (ref "R1002") (pin "2") (pinfunction "2_2") (pintype "passive"))
      (node (ref "USB1001") (pin "A5") (pinfunction "CC1_A5") (pintype "bidirectional"))
    )
    (net (code "239") (name "Net-(USB1001-CC2)") (class "Default")
      (node (ref "R1001") (pin "2") (pinfunction "2_2") (pintype "passive"))
      (node (ref "USB1001") (pin "B5") (pinfunction "CC2_B5") (pintype "bidirectional"))
    )
    (net (code "240") (name "RXADC_CLK") (class "Default")
      (node (ref "U301") (pin "P1") (pinfunction "IOL_24A_P1") (pintype "bidirectional"))
      (node (ref "U402") (pin "10") (pinfunction "ENC-_10") (pintype "bidirectional"))
    )
    (net (code "241") (name "RXADC_D0") (class "Default")
      (node (ref "U301") (pin "T11") (pinfunction "IOB_89_T11") (pintype "bidirectional"))
      (node (ref "U402") (pin "18") (pinfunction "D0_18") (pintype "bidirectional"))
    )
    (net (code "242") (name "RXADC_D1") (class "Default")
      (node (ref "U301") (pin "R10") (pinfunction "IOB_84_R10") (pintype "bidirectional"))
      (node (ref "U402") (pin "19") (pinfunction "D1_19") (pintype "bidirectional"))
    )
    (net (code "243") (name "RXADC_D2") (class "Default")
      (node (ref "U301") (pin "T10") (pinfunction "IOB_88_T10") (pintype "bidirectional"))
      (node (ref "U402") (pin "20") (pinfunction "D2_20") (pintype "bidirectional"))
    )
    (net (code "244") (name "RXADC_D3") (class "Default")
      (node (ref "U301") (pin "T9") (pinfunction "IOB_79_T9") (pintype "bidirectional"))
      (node (ref "U402") (pin "21") (pinfunction "D3_21") (pintype "bidirectional"))
    )
    (net (code "245") (name "RXADC_D4") (class "Default")
      (node (ref "U301") (pin "T8") (pinfunction "IOB_76_T8") (pintype "bidirectional"))
      (node (ref "U402") (pin "22") (pinfunction "D4_22") (pintype "bidirectional"))
    )
    (net (code "246") (name "RXADC_D5") (class "Default")
      (node (ref "U301") (pin "T7") (pinfunction "IOB_75_T7") (pintype "bidirectional"))
      (node (ref "U402") (pin "26") (pinfunction "D5_26") (pintype "bidirectional"))
    )
    (net (code "247") (name "RXADC_D6") (class "Default")
      (node (ref "U301") (pin "R6") (pinfunction "IOB_71_R6") (pintype "bidirectional"))
      (node (ref "U402") (pin "27") (pinfunction "D6_27") (pintype "bidirectional"))
    )
    (net (code "248") (name "RXADC_D7") (class "Default")
      (node (ref "U301") (pin "T6") (pinfunction "IOB_73_T6") (pintype "bidirectional"))
      (node (ref "U402") (pin "28") (pinfunction "D7_28") (pintype "bidirectional"))
    )
    (net (code "249") (name "RXADC_D8") (class "Default")
      (node (ref "U301") (pin "R5") (pinfunction "IOB_60_R5") (pintype "bidirectional"))
      (node (ref "U402") (pin "32") (pinfunction "D8_32") (pintype "bidirectional"))
    )
    (net (code "250") (name "RXADC_D9") (class "Default")
      (node (ref "U301") (pin "T5") (pinfunction "IOB_69_T5") (pintype "bidirectional"))
      (node (ref "U402") (pin "33") (pinfunction "D9_33") (pintype "bidirectional"))
    )
    (net (code "251") (name "RXADC_D10") (class "Default")
      (node (ref "U301") (pin "R4") (pinfunction "IOB_63_R4") (pintype "bidirectional"))
      (node (ref "U402") (pin "34") (pinfunction "D10_34") (pintype "bidirectional"))
    )
    (net (code "252") (name "RXADC_D11") (class "Default")
      (node (ref "U301") (pin "R3") (pinfunction "IOB_59_R3") (pintype "bidirectional"))
      (node (ref "U402") (pin "35") (pinfunction "D11_35") (pintype "bidirectional"))
    )
    (net (code "253") (name "RXADC_D12") (class "Default")
      (node (ref "U301") (pin "T3") (pinfunction "IOB_61_T3") (pintype "bidirectional"))
      (node (ref "U402") (pin "39") (pinfunction "D12_39") (pintype "bidirectional"))
    )
    (net (code "254") (name "RXADC_D13") (class "Default")
      (node (ref "U301") (pin "R2") (pinfunction "IOB_55_R2") (pintype "bidirectional"))
      (node (ref "U402") (pin "40") (pinfunction "D13_40") (pintype "bidirectional"))
    )
    (net (code "255") (name "RXADC_D14") (class "Default")
      (node (ref "U301") (pin "T2") (pinfunction "IOB_57_T2") (pintype "bidirectional"))
      (node (ref "U402") (pin "41") (pinfunction "D14_41") (pintype "bidirectional"))
    )
    (net (code "256") (name "RXADC_D15") (class "Default")
      (node (ref "U301") (pin "T1") (pinfunction "IOB_53_T1") (pintype "bidirectional"))
      (node (ref "U402") (pin "42") (pinfunction "D15_42") (pintype "bidirectional"))
    )
    (net (code "257") (name "RXADC_DITH") (class "Default")
      (node (ref "U101") (pin "K3") (pinfunction "PA13_K3") (pintype "bidirectional"))
      (node (ref "U402") (pin "17") (pinfunction "DITH_17") (pintype "bidirectional"))
    )
    (net (code "258") (name "RXADC_GAIN") (class "Default")
      (node (ref "U101") (pin "L3") (pinfunction "PA14_L3") (pintype "bidirectional"))
      (node (ref "U402") (pin "47") (pinfunction "PGA_47") (pintype "bidirectional"))
    )
    (net (code "259") (name "RXADC_OF") (class "Default")
      (node (ref "U301") (pin "R1") (pinfunction "IOL_26A_R1") (pintype "bidirectional"))
      (node (ref "U402") (pin "43") (pinfunction "OF_43") (pintype "bidirectional"))
    )
    (net (code "260") (name "RXADC_SHDN") (class "Default")
      (node (ref "R401") (pin "1") (pinfunction "1_1") (pintype "passive"))
      (node (ref "U101") (pin "J4") (pinfunction "PA12_J4") (pintype "bidirectional"))
      (node (ref "U402") (pin "16") (pinfunction "SHDN_16") (pintype "bidirectional"))
    )
    (net (code "261") (name "RXADC_VCM") (class "Default")
      (node (ref "C425") (pin "1") (pinfunction "C1_1") (pintype "passive"))
      (node (ref "C426") (pin "1") (pinfunction "C1_1") (pintype "passive"))
      (node (ref "R411") (pin "1") (pinfunction "1_1") (pintype "passive"))
      (node (ref "R412") (pin "2") (pinfunction "2_2") (pintype "passive"))
      (node (ref "TRF401") (pin "2") (pinfunction "CT_2") (pintype "passive"))
      (node (ref "U402") (pin "2") (pinfunction "VCM_2") (pintype "bidirectional"))
    )
    (net (code "262") (name "RXTUNER_I2C_SCL") (class "Default")
      (node (ref "R405") (pin "2") (pinfunction "2_2") (pintype "passive"))
      (node (ref "U101") (pin "L2") (pinfunction "PC5_L2") (pintype "bidirectional"))
    )
    (net (code "263") (name "RXTUNER_I2C_SDA") (class "Default")
      (node (ref "R404") (pin "2") (pinfunction "2_2") (pintype "passive"))
      (node (ref "U101") (pin "K2") (pinfunction "PC4_K2") (pintype "bidirectional"))
    )
    (net (code "264") (name "RXTUNER_IFN") (class "Default")
      (node (ref "R416") (pin "1") (pinfunction "1_1") (pintype "passive"))
      (node (ref "U403") (pin "12") (pinfunction "IF_N_12") (pintype "bidirectional"))
    )
    (net (code "265") (name "RXTUNER_IFP") (class "Default")
      (node (ref "R415") (pin "1") (pinfunction "1_1") (pintype "passive"))
      (node (ref "U403") (pin "13") (pinfunction "IF_P_13") (pintype "bidirectional"))
    )
    (net (code "266") (name "RXTUNER_IF_VAGC") (class "Default")
      (node (ref "R414") (pin "1") (pinfunction "1_1") (pintype "passive"))
      (node (ref "U101") (pin "L5") (pinfunction "PB11_L5") (pintype "bidirectional"))
    )
    (net (code "267") (name "RXTUNER_REFCLK_SEL") (class "Default")
      (node (ref "U101") (pin "J3") (pinfunction "PD15_J3") (pintype "bidirectional"))
      (node (ref "U401") (pin "1") (pinfunction "FS_1") (pintype "input"))
    )
    (net (code "268") (name "SMC_LED") (class "Default")
      (node (ref "R103") (pin "2") (pinfunction "2_2") (pintype "passive"))
      (node (ref "U101") (pin "B1") (pinfunction "PA15_B1") (pintype "bidirectional"))
    )
    (net (code "269") (name "SMC_LFXTAL_N") (class "Default")
      (node (ref "U101") (pin "L1") (pinfunction "PB8_L1") (pintype "bidirectional"))
      (node (ref "X101") (pin "2") (pinfunction "2_2") (pintype "passive"))
    )
    (net (code "270") (name "SMC_LFXTAL_P") (class "Default")
      (node (ref "U101") (pin "K1") (pinfunction "PB7_K1") (pintype "bidirectional"))
      (node (ref "X101") (pin "1") (pinfunction "1_1") (pintype "passive"))
    )
    (net (code "271") (name "SMC_MAIN_CLK") (class "Default")
      (node (ref "R909") (pin "1") (pinfunction "1_1") (pintype "passive"))
      (node (ref "U101") (pin "L9") (pinfunction "PB14_L9") (pintype "bidirectional"))
    )
    (net (code "272") (name "SMC_SWCLK") (class "Default")
      (node (ref "TC101") (pin "4") (pinfunction "S_4") (pintype "passive"))
      (node (ref "U101") (pin "E8") (pinfunction "PF0_E8") (pintype "bidirectional"))
    )
    (net (code "273") (name "SMC_SWDIO") (class "Default")
      (node (ref "TC101") (pin "2") (pinfunction "S_2") (pintype "passive"))
      (node (ref "U101") (pin "D8") (pinfunction "PF1_D8") (pintype "bidirectional"))
    )
    (net (code "274") (name "SMC_SWO") (class "Default")
      (node (ref "TC101") (pin "6") (pinfunction "S_6") (pintype "passive"))
      (node (ref "U101") (pin "C8") (pinfunction "PF2_C8") (pintype "bidirectional"))
    )
    (net (code "275") (name "SYS_I2C_SCL") (class "Default")
      (node (ref "R102") (pin "1") (pinfunction "1_1") (pintype "passive"))
      (node (ref "U101") (pin "B9") (pinfunction "PE5_B9") (pintype "bidirectional"))
      (node (ref "U801") (pin "44") (pinfunction "X+/SCL_44") (pintype "bidirectional"))
      (node (ref "U902") (pin "4") (pinfunction "SCL_4") (pintype "bidirectional"))
    )
    (net (code "276") (name "SYS_I2C_SDA") (class "Default")
      (node (ref "R101") (pin "1") (pinfunction "1_1") (pintype "passive"))
      (node (ref "U101") (pin "A9") (pinfunction "PE4_A9") (pintype "bidirectional"))
      (node (ref "U801") (pin "45") (pinfunction "Y+/SDA_45") (pintype "bidirectional"))
      (node (ref "U902") (pin "5") (pinfunction "SDA_5") (pintype "bidirectional"))
    )
    (net (code "277") (name "TFT_BL_PWM") (class "Default")
      (node (ref "R801") (pin "2") (pinfunction "2_2") (pintype "passive"))
      (node (ref "U101") (pin "K11") (pinfunction "PD1_K11") (pintype "bidirectional"))
    )
    (net (code "278") (name "TFT_DC") (class "Default")
      (node (ref "U101") (pin "J11") (pinfunction "PD4_J11") (pintype "bidirectional"))
      (node (ref "U801") (pin "37") (pinfunction "D/~{C}_37") (pintype "bidirectional"))
    )
    (net (code "279") (name "TFT_SPI_MISO") (class "Default")
      (node (ref "U101") (pin "H5") (pinfunction "PA8_H5") (pintype "bidirectional"))
      (node (ref "U801") (pin "33") (pinfunction "SDO_33") (pintype "bidirectional"))
    )
    (net (code "280") (name "TFT_SPI_MOSI") (class "Default")
      (node (ref "U101") (pin "H4") (pinfunction "PA7_H4") (pintype "bidirectional"))
      (node (ref "U801") (pin "34") (pinfunction "SDA_34") (pintype "bidirectional"))
    )
    (net (code "281") (name "TFT_SPI_SCK") (class "Default")
      (node (ref "U101") (pin "J5") (pinfunction "PA9_J5") (pintype "bidirectional"))
      (node (ref "U801") (pin "36") (pinfunction "~{WR}/SCL_36") (pintype "bidirectional"))
    )
    (net (code "282") (name "TXDAC_AUXI") (class "Default")
      (node (ref "R513") (pin "2") (pinfunction "2_2") (pintype "passive"))
      (node (ref "U502") (pin "33") (pinfunction "FSADJI/AUXI_33") (pintype "bidirectional"))
    )
    (net (code "283") (name "TXDAC_AUXQ") (class "Default")
      (node (ref "R514") (pin "2") (pinfunction "2_2") (pintype "passive"))
      (node (ref "U502") (pin "32") (pinfunction "FSADJQ/AUXQ_32") (pintype "bidirectional"))
    )
    (net (code "284") (name "TXDAC_CLKIN") (class "Default")
      (node (ref "R502") (pin "2") (pinfunction "2_2") (pintype "passive"))
      (node (ref "U301") (pin "D2") (pinfunction "IOL_4B_D2") (pintype "bidirectional"))
      (node (ref "U502") (pin "18") (pinfunction "CLKIN_18") (pintype "bidirectional"))
    )
    (net (code "285") (name "TXDAC_D0") (class "Default")
      (node (ref "U301") (pin "A7") (pinfunction "IOT_205_A7") (pintype "bidirectional"))
      (node (ref "U502") (pin "15") (pinfunction "DB0_15") (pintype "bidirectional"))
    )
    (net (code "286") (name "TXDAC_D1") (class "Default")
      (node (ref "U301") (pin "B7") (pinfunction "IOT_207_B7") (pintype "bidirectional"))
      (node (ref "U502") (pin "14") (pinfunction "DB1_14") (pintype "bidirectional"))
    )
    (net (code "287") (name "TXDAC_D2") (class "Default")
      (node (ref "U301") (pin "A6") (pinfunction "IOT_211_A6") (pintype "bidirectional"))
      (node (ref "U502") (pin "13") (pinfunction "DB2_13") (pintype "bidirectional"))
    )
    (net (code "288") (name "TXDAC_D3") (class "Default")
      (node (ref "U301") (pin "B6") (pinfunction "IOT_208_B6") (pintype "bidirectional"))
      (node (ref "U502") (pin "12") (pinfunction "DB3_12") (pintype "bidirectional"))
    )
    (net (code "289") (name "TXDAC_D4") (class "Default")
      (node (ref "U301") (pin "A5") (pinfunction "IOT_213_A5") (pintype "bidirectional"))
      (node (ref "U502") (pin "11") (pinfunction "DB4_11") (pintype "bidirectional"))
    )
    (net (code "290") (name "TXDAC_D5") (class "Default")
      (node (ref "U301") (pin "B5") (pinfunction "IOT_214_B5") (pintype "bidirectional"))
      (node (ref "U502") (pin "10") (pinfunction "DB5_10") (pintype "bidirectional"))
    )
    (net (code "291") (name "TXDAC_D6") (class "Default")
      (node (ref "U301") (pin "B4") (pinfunction "IOT_216_B4") (pintype "bidirectional"))
      (node (ref "U502") (pin "9") (pinfunction "DB6_9") (pintype "bidirectional"))
    )
    (net (code "292") (name "TXDAC_D7") (class "Default")
      (node (ref "U301") (pin "B3") (pinfunction "IOT_223_B3") (pintype "bidirectional"))
      (node (ref "U502") (pin "8") (pinfunction "DB7_8") (pintype "bidirectional"))
    )
    (net (code "293") (name "TXDAC_D8") (class "Default")
      (node (ref "U301") (pin "A2") (pinfunction "IOT_218_A2") (pintype "bidirectional"))
      (node (ref "U502") (pin "4") (pinfunction "DB8_4") (pintype "bidirectional"))
    )
    (net (code "294") (name "TXDAC_D9") (class "Default")
      (node (ref "U301") (pin "B2") (pinfunction "IOL_1B_B2") (pintype "bidirectional"))
      (node (ref "U502") (pin "3") (pinfunction "DB9_3") (pintype "bidirectional"))
    )
    (net (code "295") (name "TXDAC_D10") (class "Default")
      (node (ref "U301") (pin "A1") (pinfunction "IOT_220_A1") (pintype "bidirectional"))
      (node (ref "U502") (pin "2") (pinfunction "DB10_2") (pintype "bidirectional"))
    )
    (net (code "296") (name "TXDAC_D11") (class "Default")
      (node (ref "U301") (pin "B1") (pinfunction "IOL_2B_B1") (pintype "bidirectional"))
      (node (ref "U502") (pin "1") (pinfunction "DB11_1") (pintype "bidirectional"))
    )
    (net (code "297") (name "TXDAC_D12") (class "Default")
      (node (ref "U301") (pin "C2") (pinfunction "IOL_3B_C2") (pintype "bidirectional"))
      (node (ref "U502") (pin "40") (pinfunction "DB12_40") (pintype "bidirectional"))
    )
    (net (code "298") (name "TXDAC_D13") (class "Default")
      (node (ref "U301") (pin "C1") (pinfunction "IOL_3A_C1") (pintype "bidirectional"))
      (node (ref "U502") (pin "39") (pinfunction "DB13_39") (pintype "bidirectional"))
    )
    (net (code "299") (name "TXDAC_DCLK") (class "Default")
      (node (ref "R502") (pin "1") (pinfunction "1_1") (pintype "passive"))
      (node (ref "U301") (pin "D1") (pinfunction "IOL_5B_D1") (pintype "bidirectional"))
      (node (ref "U502") (pin "16") (pinfunction "DCLKIO_16") (pintype "bidirectional"))
    )
    (net (code "300") (name "TXDAC_RESET") (class "Default")
      (node (ref "R505") (pin "1") (pinfunction "1_1") (pintype "passive"))
      (node (ref "U101") (pin "A3") (pinfunction "PE12_A3") (pintype "bidirectional"))
      (node (ref "U502") (pin "35") (pinfunction "RESET/PINMD_35") (pintype "bidirectional"))
    )
    (net (code "301") (name "TXDAC_SCLK") (class "Default")
      (node (ref "U101") (pin "C4") (pinfunction "PD13_C4") (pintype "bidirectional"))
      (node (ref "U502") (pin "36") (pinfunction "SCLK/CLKMD_36") (pintype "bidirectional"))
    )
    (net (code "302") (name "TXDAC_SDIO") (class "Default")
      (node (ref "U101") (pin "B4") (pinfunction "PE8_B4") (pintype "bidirectional"))
      (node (ref "U502") (pin "37") (pinfunction "SDIO/FORMAT_37") (pintype "bidirectional"))
    )
    (net (code "303") (name "TXMIXER_EN") (class "Default")
      (node (ref "R501") (pin "2") (pinfunction "2_2") (pintype "passive"))
      (node (ref "U101") (pin "A1") (pinfunction "PE15_A1") (pintype "bidirectional"))
      (node (ref "U501") (pin "12") (pinfunction "ENBL_12") (pintype "bidirectional"))
    )
    (net (code "304") (name "TXMIXER_IBBN") (class "Default")
      (node (ref "C525") (pin "1") (pinfunction "C1_1") (pintype "passive"))
      (node (ref "L506") (pin "2") (pinfunction "2_2") (pintype "passive"))
      (node (ref "R515") (pin "2") (pinfunction "2_2") (pintype "passive"))
      (node (ref "U501") (pin "14") (pinfunction "IBBN_14") (pintype "bidirectional"))
    )
    (net (code "305") (name "TXMIXER_IBBP") (class "Default")
      (node (ref "C526") (pin "2") (pinfunction "C2_2") (pintype "passive"))
      (node (ref "L507") (pin "2") (pinfunction "2_2") (pintype "passive"))
      (node (ref "R513") (pin "1") (pinfunction "1_1") (pintype "passive"))
      (node (ref "R515") (pin "1") (pinfunction "1_1") (pintype "passive"))
      (node (ref "U501") (pin "13") (pinfunction "IBBP_13") (pintype "bidirectional"))
    )
    (net (code "306") (name "TXMIXER_LON") (class "Default")
      (node (ref "C622") (pin "2") (pinfunction "C2_2") (pintype "passive"))
      (node (ref "U501") (pin "22") (pinfunction "LOIN_22") (pintype "bidirectional"))
    )
    (net (code "307") (name "TXMIXER_LOP") (class "Default")
      (node (ref "C623") (pin "2") (pinfunction "C2_2") (pintype "passive"))
      (node (ref "U501") (pin "21") (pinfunction "LOIP_21") (pintype "bidirectional"))
    )
    (net (code "308") (name "TXMIXER_QBBN") (class "Default")
      (node (ref "C527") (pin "1") (pinfunction "C1_1") (pintype "passive"))
      (node (ref "L508") (pin "2") (pinfunction "2_2") (pintype "passive"))
      (node (ref "R516") (pin "2") (pinfunction "2_2") (pintype "passive"))
      (node (ref "U501") (pin "17") (pinfunction "QBBN_17") (pintype "bidirectional"))
    )
    (net (code "309") (name "TXMIXER_QBBP") (class "Default")
      (node (ref "C528") (pin "2") (pinfunction "C2_2") (pintype "passive"))
      (node (ref "L509") (pin "2") (pinfunction "2_2") (pintype "passive"))
      (node (ref "R514") (pin "1") (pinfunction "1_1") (pintype "passive"))
      (node (ref "R516") (pin "1") (pinfunction "1_1") (pintype "passive"))
      (node (ref "U501") (pin "18") (pinfunction "QBBP_18") (pintype "bidirectional"))
    )
    (net (code "310") (name "TXMIXER_TEMP") (class "Default")
      (node (ref "C510") (pin "1") (pinfunction "C1_1") (pintype "passive"))
      (node (ref "R504") (pin "1") (pinfunction "1_1") (pintype "passive"))
      (node (ref "U101") (pin "H10") (pinfunction "PD6_H10") (pintype "bidirectional"))
    )
    (net (code "311") (name "TXPA_BIAS_EN") (class "Default")
      (node (ref "R1014") (pin "2") (pinfunction "2_2") (pintype "passive"))
      (node (ref "U1003") (pin "3") (pinfunction "EN_3") (pintype "bidirectional"))
      (node (ref "U101") (pin "C3") (pinfunction "PE10_C3") (pintype "bidirectional"))
    )
    (net (code "312") (name "TXPLL_EN") (class "Default")
      (node (ref "R601") (pin "2") (pinfunction "2_2") (pintype "passive"))
      (node (ref "U101") (pin "A6") (pinfunction "PF7_A6") (pintype "bidirectional"))
      (node (ref "U601") (pin "1") (pinfunction "~{STDBY}_1") (pintype "input"))
      (node (ref "U602") (pin "4") (pinfunction "CE_4") (pintype "bidirectional"))
    )
    (net (code "313") (name "TXPLL_LE") (class "Default")
      (node (ref "U101") (pin "C5") (pinfunction "PD12_C5") (pintype "bidirectional"))
      (node (ref "U602") (pin "3") (pinfunction "LE_3") (pintype "bidirectional"))
    )
    (net (code "314") (name "TXPLL_LOCK") (class "Default")
      (node (ref "U101") (pin "C6") (pinfunction "PF9_C6") (pintype "bidirectional"))
      (node (ref "U602") (pin "25") (pinfunction "LD_25") (pintype "bidirectional"))
    )
    (net (code "315") (name "TXPLL_MUXOUT") (class "Default")
      (node (ref "U101") (pin "A5") (pinfunction "PD10_A5") (pintype "bidirectional"))
      (node (ref "U602") (pin "30") (pinfunction "MUXOUT_30") (pintype "bidirectional"))
    )
    (net (code "316") (name "TXPLL_SCLK") (class "Default")
      (node (ref "U101") (pin "B5") (pinfunction "PD11_B5") (pintype "bidirectional"))
      (node (ref "U602") (pin "1") (pinfunction "CLK_1") (pintype "bidirectional"))
    )
    (net (code "317") (name "TXPLL_SDATA") (class "Default")
      (node (ref "U101") (pin "D6") (pinfunction "PD9_D6") (pintype "bidirectional"))
      (node (ref "U602") (pin "2") (pinfunction "DATA_2") (pintype "bidirectional"))
    )
    (net (code "318") (name "unconnected-(J701-DT-Pad4)") (class "Default")
      (node (ref "J701") (pin "4") (pinfunction "DT_4") (pintype "bidirectional"))
    )
    (net (code "319") (name "unconnected-(J702-DT-Pad4)") (class "Default")
      (node (ref "J702") (pin "4") (pinfunction "DT_4") (pintype "bidirectional"))
    )
    (net (code "320") (name "unconnected-(TC101F-S-Pad5)") (class "Default")
      (node (ref "TC101") (pin "5") (pinfunction "S_5") (pintype "passive"))
    )
    (net (code "321") (name "unconnected-(TC201F-S-Pad5)") (class "Default")
      (node (ref "TC201") (pin "5") (pinfunction "S_5") (pintype "passive"))
    )
    (net (code "322") (name "unconnected-(U101-PA4-PadE3)") (class "Default")
      (node (ref "U101") (pin "E3") (pinfunction "PA4_E3") (pintype "bidirectional"))
    )
    (net (code "323") (name "unconnected-(U101-PA6-PadE1)") (class "Default")
      (node (ref "U101") (pin "E1") (pinfunction "PA6_E1") (pintype "bidirectional"))
    )
    (net (code "324") (name "unconnected-(U101-PA11-PadK5)") (class "Default")
      (node (ref "U101") (pin "K5") (pinfunction "PA11_K5") (pintype "bidirectional"))
    )
    (net (code "325") (name "unconnected-(U101-PB0-PadE4)") (class "Default")
      (node (ref "U101") (pin "E4") (pinfunction "PB0_E4") (pintype "bidirectional"))
    )
    (net (code "326") (name "unconnected-(U101-PB3-PadF3)") (class "Default")
      (node (ref "U101") (pin "F3") (pinfunction "PB3_F3") (pintype "bidirectional"))
    )
    (net (code "327") (name "unconnected-(U101-PB4-PadF4)") (class "Default")
      (node (ref "U101") (pin "F4") (pinfunction "PB4_F4") (pintype "bidirectional"))
    )
    (net (code "328") (name "unconnected-(U101-PB9-PadJ7)") (class "Default")
      (node (ref "U101") (pin "J7") (pinfunction "PB9_J7") (pintype "bidirectional"))
    )
    (net (code "329") (name "unconnected-(U101-PB15-PadD3)") (class "Default")
      (node (ref "U101") (pin "D3") (pinfunction "PB15_D3") (pintype "bidirectional"))
    )
    (net (code "330") (name "unconnected-(U101-PC6-PadG10)") (class "Default")
      (node (ref "U101") (pin "G10") (pinfunction "PC6_G10") (pintype "bidirectional"))
    )
    (net (code "331") (name "unconnected-(U101-PC7-PadG11)") (class "Default")
      (node (ref "U101") (pin "G11") (pinfunction "PC7_G11") (pintype "bidirectional"))
    )
    (net (code "332") (name "unconnected-(U101-PC9-PadD11)") (class "Default")
      (node (ref "U101") (pin "D11") (pinfunction "PC9_D11") (pintype "bidirectional"))
    )
    (net (code "333") (name "unconnected-(U101-PD5-PadH9)") (class "Default")
      (node (ref "U101") (pin "H9") (pinfunction "PD5_H9") (pintype "bidirectional"))
    )
    (net (code "334") (name "unconnected-(U101-PD8-PadH8)") (class "Default")
      (node (ref "U101") (pin "H8") (pinfunction "PD8_H8") (pintype "bidirectional"))
    )
    (net (code "335") (name "unconnected-(U101-PD14-PadH3)") (class "Default")
      (node (ref "U101") (pin "H3") (pinfunction "PD14_H3") (pintype "bidirectional"))
    )
    (net (code "336") (name "unconnected-(U101-PE0-PadE9)") (class "Default")
      (node (ref "U101") (pin "E9") (pinfunction "PE0_E9") (pintype "bidirectional"))
    )
    (net (code "337") (name "unconnected-(U101-PE1-PadE10)") (class "Default")
      (node (ref "U101") (pin "E10") (pinfunction "PE1_E10") (pintype "bidirectional"))
    )
    (net (code "338") (name "unconnected-(U101-PE2-PadF10)") (class "Default")
      (node (ref "U101") (pin "F10") (pinfunction "PE2_F10") (pintype "bidirectional"))
    )
    (net (code "339") (name "unconnected-(U101-PE3-PadE11)") (class "Default")
      (node (ref "U101") (pin "E11") (pinfunction "PE3_E11") (pintype "bidirectional"))
    )
    (net (code "340") (name "unconnected-(U101-PE7-PadD9)") (class "Default")
      (node (ref "U101") (pin "D9") (pinfunction "PE7_D9") (pintype "bidirectional"))
    )
    (net (code "341") (name "unconnected-(U101-PE14-PadA2)") (class "Default")
      (node (ref "U101") (pin "A2") (pinfunction "PE14_A2") (pintype "bidirectional"))
    )
    (net (code "342") (name "unconnected-(U101-PF5-PadA7)") (class "Default")
      (node (ref "U101") (pin "A7") (pinfunction "PF5_A7") (pintype "bidirectional"))
    )
    (net (code "343") (name "unconnected-(U101-VBUS-PadB8)") (class "Default")
      (node (ref "U101") (pin "B8") (pinfunction "VBUS_B8") (pintype "bidirectional"))
    )
    (net (code "344") (name "unconnected-(U101-VREGI-PadB10)") (class "Default")
      (node (ref "U101") (pin "B10") (pinfunction "VREGI_B10") (pintype "bidirectional"))
    )
    (net (code "345") (name "unconnected-(U101-VREGO-PadB11)") (class "Default")
      (node (ref "U101") (pin "B11") (pinfunction "VREGO_B11") (pintype "bidirectional"))
    )
    (net (code "346") (name "unconnected-(U201A-PA2-PadE12)") (class "Default")
      (node (ref "U201") (pin "E12") (pinfunction "PA2_E12") (pintype "bidirectional"))
    )
    (net (code "347") (name "unconnected-(U201A-PA3-PadF12)") (class "Default")
      (node (ref "U201") (pin "F12") (pinfunction "PA3_F12") (pintype "bidirectional"))
    )
    (net (code "348") (name "unconnected-(U201A-PA5-PadM11)") (class "Default")
      (node (ref "U201") (pin "M11") (pinfunction "PA5_M11") (pintype "bidirectional"))
    )
    (net (code "349") (name "unconnected-(U201A-PA6-PadB9)") (class "Default")
      (node (ref "U201") (pin "B9") (pinfunction "PA6_B9") (pintype "bidirectional"))
    )
    (net (code "350") (name "unconnected-(U201A-PA7-PadL2)") (class "Default")
      (node (ref "U201") (pin "L2") (pinfunction "PA7_L2") (pintype "bidirectional"))
    )
    (net (code "351") (name "unconnected-(U201A-PA8-PadM2)") (class "Default")
      (node (ref "U201") (pin "M2") (pinfunction "PA8_M2") (pintype "bidirectional"))
    )
    (net (code "352") (name "unconnected-(U201A-PA9-PadM12)") (class "Default")
      (node (ref "U201") (pin "M12") (pinfunction "PA9_M12") (pintype "bidirectional"))
    )
    (net (code "353") (name "unconnected-(U201A-PA10-PadL9)") (class "Default")
      (node (ref "U201") (pin "L9") (pinfunction "PA10_L9") (pintype "bidirectional"))
    )
    (net (code "354") (name "unconnected-(U201A-PA11-PadJ9)") (class "Default")
      (node (ref "U201") (pin "J9") (pinfunction "PA11_J9") (pintype "bidirectional"))
    )
    (net (code "355") (name "unconnected-(U201A-PA12-PadL10)") (class "Default")
      (node (ref "U201") (pin "L10") (pinfunction "PA12_L10") (pintype "bidirectional"))
    )
    (net (code "356") (name "unconnected-(U201A-PA13-PadM3)") (class "Default")
      (node (ref "U201") (pin "M3") (pinfunction "PA13_M3") (pintype "bidirectional"))
    )
    (net (code "357") (name "unconnected-(U201A-PA14-PadK6)") (class "Default")
      (node (ref "U201") (pin "K6") (pinfunction "PA14_K6") (pintype "bidirectional"))
    )
    (net (code "358") (name "unconnected-(U201A-PA17-PadJ1)") (class "Default")
      (node (ref "U201") (pin "J1") (pinfunction "PA17_J1") (pintype "bidirectional"))
    )
    (net (code "359") (name "unconnected-(U201A-PA18-PadH2)") (class "Default")
      (node (ref "U201") (pin "H2") (pinfunction "PA18_H2") (pintype "bidirectional"))
    )
    (net (code "360") (name "unconnected-(U201A-PA19-PadH1)") (class "Default")
      (node (ref "U201") (pin "H1") (pinfunction "PA19_H1") (pintype "bidirectional"))
    )
    (net (code "361") (name "unconnected-(U201A-PA21-PadK2)") (class "Default")
      (node (ref "U201") (pin "K2") (pinfunction "PA21_K2") (pintype "bidirectional"))
    )
    (net (code "362") (name "unconnected-(U201A-PA22-PadK3)") (class "Default")
      (node (ref "U201") (pin "K3") (pinfunction "PA22_K3") (pintype "bidirectional"))
    )
    (net (code "363") (name "unconnected-(U201A-PA23-PadL4)") (class "Default")
      (node (ref "U201") (pin "L4") (pinfunction "PA23_L4") (pintype "bidirectional"))
    )
    (net (code "364") (name "unconnected-(U201A-PA24-PadL7)") (class "Default")
      (node (ref "U201") (pin "L7") (pinfunction "PA24_L7") (pintype "bidirectional"))
    )
    (net (code "365") (name "unconnected-(U201A-PA25-PadK8)") (class "Default")
      (node (ref "U201") (pin "K8") (pinfunction "PA25_K8") (pintype "bidirectional"))
    )
    (net (code "366") (name "unconnected-(U201A-PA26-PadJ8)") (class "Default")
      (node (ref "U201") (pin "J8") (pinfunction "PA26_J8") (pintype "bidirectional"))
    )
    (net (code "367") (name "unconnected-(U201A-PA27-PadJ10)") (class "Default")
      (node (ref "U201") (pin "J10") (pinfunction "PA27_J10") (pintype "bidirectional"))
    )
    (net (code "368") (name "unconnected-(U201A-PA28-PadC9)") (class "Default")
      (node (ref "U201") (pin "C9") (pinfunction "PA28_C9") (pintype "bidirectional"))
    )
    (net (code "369") (name "unconnected-(U201A-PA29-PadA6)") (class "Default")
      (node (ref "U201") (pin "A6") (pinfunction "PA29_A6") (pintype "bidirectional"))
    )
    (net (code "370") (name "unconnected-(U201A-PA31-PadC8)") (class "Default")
      (node (ref "U201") (pin "C8") (pinfunction "PA31_C8") (pintype "bidirectional"))
    )
    (net (code "371") (name "unconnected-(U201B-PB0-PadH4)") (class "Default")
      (node (ref "U201") (pin "H4") (pinfunction "PB0_H4") (pintype "bidirectional"))
    )
    (net (code "372") (name "unconnected-(U201B-PB1-PadG3)") (class "Default")
      (node (ref "U201") (pin "G3") (pinfunction "PB1_G3") (pintype "bidirectional"))
    )
    (net (code "373") (name "unconnected-(U201B-PB3-PadJ3)") (class "Default")
      (node (ref "U201") (pin "J3") (pinfunction "PB3_J3") (pintype "bidirectional"))
    )
    (net (code "374") (name "unconnected-(U201B-PB8-PadA3)") (class "Default")
      (node (ref "U201") (pin "A3") (pinfunction "PB8_A3") (pintype "bidirectional"))
    )
    (net (code "375") (name "unconnected-(U201B-PB13-PadB2)") (class "Default")
      (node (ref "U201") (pin "B2") (pinfunction "PB13_B2") (pintype "bidirectional"))
    )
    (net (code "376") (name "unconnected-(U201C-PC0-PadE4)") (class "Default")
      (node (ref "U201") (pin "E4") (pinfunction "PC0_E4") (pintype "bidirectional"))
    )
    (net (code "377") (name "unconnected-(U201C-PC1-PadJ4)") (class "Default")
      (node (ref "U201") (pin "J4") (pinfunction "PC1_J4") (pintype "bidirectional"))
    )
    (net (code "378") (name "unconnected-(U201C-PC2-PadK4)") (class "Default")
      (node (ref "U201") (pin "K4") (pinfunction "PC2_K4") (pintype "bidirectional"))
    )
    (net (code "379") (name "unconnected-(U201C-PC3-PadL3)") (class "Default")
      (node (ref "U201") (pin "L3") (pinfunction "PC3_L3") (pintype "bidirectional"))
    )
    (net (code "380") (name "unconnected-(U201C-PC4-PadJ5)") (class "Default")
      (node (ref "U201") (pin "J5") (pinfunction "PC4_J5") (pintype "bidirectional"))
    )
    (net (code "381") (name "unconnected-(U201C-PC5-PadL8)") (class "Default")
      (node (ref "U201") (pin "L8") (pinfunction "PC5_L8") (pintype "bidirectional"))
    )
    (net (code "382") (name "unconnected-(U201C-PC6-PadK7)") (class "Default")
      (node (ref "U201") (pin "K7") (pinfunction "PC6_K7") (pintype "bidirectional"))
    )
    (net (code "383") (name "unconnected-(U201C-PC7-PadM4)") (class "Default")
      (node (ref "U201") (pin "M4") (pinfunction "PC7_M4") (pintype "bidirectional"))
    )
    (net (code "384") (name "unconnected-(U201C-PC8-PadJ12)") (class "Default")
      (node (ref "U201") (pin "J12") (pinfunction "PC8_J12") (pintype "bidirectional"))
    )
    (net (code "385") (name "unconnected-(U201C-PC9-PadG11)") (class "Default")
      (node (ref "U201") (pin "G11") (pinfunction "PC9_G11") (pintype "bidirectional"))
    )
    (net (code "386") (name "unconnected-(U201C-PC10-PadF10)") (class "Default")
      (node (ref "U201") (pin "F10") (pinfunction "PC10_F10") (pintype "bidirectional"))
    )
    (net (code "387") (name "unconnected-(U201C-PC11-PadF11)") (class "Default")
      (node (ref "U201") (pin "F11") (pinfunction "PC11_F11") (pintype "bidirectional"))
    )
    (net (code "388") (name "unconnected-(U201C-PC12-PadF4)") (class "Default")
      (node (ref "U201") (pin "F4") (pinfunction "PC12_F4") (pintype "bidirectional"))
    )
    (net (code "389") (name "unconnected-(U201C-PC13-PadG2)") (class "Default")
      (node (ref "U201") (pin "G2") (pinfunction "PC13_G2") (pintype "bidirectional"))
    )
    (net (code "390") (name "unconnected-(U201C-PC14-PadE10)") (class "Default")
      (node (ref "U201") (pin "E10") (pinfunction "PC14_E10") (pintype "bidirectional"))
    )
    (net (code "391") (name "unconnected-(U201C-PC15-PadG1)") (class "Default")
      (node (ref "U201") (pin "G1") (pinfunction "PC15_G1") (pintype "bidirectional"))
    )
    (net (code "392") (name "unconnected-(U201C-PC16-PadD11)") (class "Default")
      (node (ref "U201") (pin "D11") (pinfunction "PC16_D11") (pintype "bidirectional"))
    )
    (net (code "393") (name "unconnected-(U201C-PC17-PadB12)") (class "Default")
      (node (ref "U201") (pin "B12") (pinfunction "PC17_B12") (pintype "bidirectional"))
    )
    (net (code "394") (name "unconnected-(U201C-PC18-PadB10)") (class "Default")
      (node (ref "U201") (pin "B10") (pinfunction "PC18_B10") (pintype "bidirectional"))
    )
    (net (code "395") (name "unconnected-(U201C-PC19-PadD8)") (class "Default")
      (node (ref "U201") (pin "D8") (pinfunction "PC19_D8") (pintype "bidirectional"))
    )
    (net (code "396") (name "unconnected-(U201C-PC20-PadA9)") (class "Default")
      (node (ref "U201") (pin "A9") (pinfunction "PC20_A9") (pintype "bidirectional"))
    )
    (net (code "397") (name "unconnected-(U201C-PC21-PadA7)") (class "Default")
      (node (ref "U201") (pin "A7") (pinfunction "PC21_A7") (pintype "bidirectional"))
    )
    (net (code "398") (name "unconnected-(U201C-PC22-PadC7)") (class "Default")
      (node (ref "U201") (pin "C7") (pinfunction "PC22_C7") (pintype "bidirectional"))
    )
    (net (code "399") (name "unconnected-(U201C-PC23-PadC6)") (class "Default")
      (node (ref "U201") (pin "C6") (pinfunction "PC23_C6") (pintype "bidirectional"))
    )
    (net (code "400") (name "unconnected-(U201C-PC24-PadB6)") (class "Default")
      (node (ref "U201") (pin "B6") (pinfunction "PC24_B6") (pintype "bidirectional"))
    )
    (net (code "401") (name "unconnected-(U201C-PC25-PadC5)") (class "Default")
      (node (ref "U201") (pin "C5") (pinfunction "PC25_C5") (pintype "bidirectional"))
    )
    (net (code "402") (name "unconnected-(U201C-PC26-PadF2)") (class "Default")
      (node (ref "U201") (pin "F2") (pinfunction "PC26_F2") (pintype "bidirectional"))
    )
    (net (code "403") (name "unconnected-(U201C-PC27-PadE2)") (class "Default")
      (node (ref "U201") (pin "E2") (pinfunction "PC27_E2") (pintype "bidirectional"))
    )
    (net (code "404") (name "unconnected-(U201C-PC28-PadL12)") (class "Default")
      (node (ref "U201") (pin "L12") (pinfunction "PC28_L12") (pintype "bidirectional"))
    )
    (net (code "405") (name "unconnected-(U201C-PC29-PadF3)") (class "Default")
      (node (ref "U201") (pin "F3") (pinfunction "PC29_F3") (pintype "bidirectional"))
    )
    (net (code "406") (name "unconnected-(U201C-PC31-PadE1)") (class "Default")
      (node (ref "U201") (pin "E1") (pinfunction "PC31_E1") (pintype "bidirectional"))
    )
    (net (code "407") (name "unconnected-(U201D-PD0-PadD4)") (class "Default")
      (node (ref "U201") (pin "D4") (pinfunction "PD0_D4") (pintype "bidirectional"))
    )
    (net (code "408") (name "unconnected-(U201D-PD1-PadB5)") (class "Default")
      (node (ref "U201") (pin "B5") (pinfunction "PD1_B5") (pintype "bidirectional"))
    )
    (net (code "409") (name "unconnected-(U201D-PD2-PadA5)") (class "Default")
      (node (ref "U201") (pin "A5") (pinfunction "PD2_A5") (pintype "bidirectional"))
    )
    (net (code "410") (name "unconnected-(U201D-PD3-PadB7)") (class "Default")
      (node (ref "U201") (pin "B7") (pinfunction "PD3_B7") (pintype "bidirectional"))
    )
    (net (code "411") (name "unconnected-(U201D-PD4-PadD6)") (class "Default")
      (node (ref "U201") (pin "D6") (pinfunction "PD4_D6") (pintype "bidirectional"))
    )
    (net (code "412") (name "unconnected-(U201D-PD5-PadD7)") (class "Default")
      (node (ref "U201") (pin "D7") (pinfunction "PD5_D7") (pintype "bidirectional"))
    )
    (net (code "413") (name "unconnected-(U201D-PD6-PadA8)") (class "Default")
      (node (ref "U201") (pin "A8") (pinfunction "PD6_A8") (pintype "bidirectional"))
    )
    (net (code "414") (name "unconnected-(U201D-PD7-PadB8)") (class "Default")
      (node (ref "U201") (pin "B8") (pinfunction "PD7_B8") (pintype "bidirectional"))
    )
    (net (code "415") (name "unconnected-(U201D-PD8-PadE9)") (class "Default")
      (node (ref "U201") (pin "E9") (pinfunction "PD8_E9") (pintype "bidirectional"))
    )
    (net (code "416") (name "unconnected-(U201D-PD9-PadD9)") (class "Default")
      (node (ref "U201") (pin "D9") (pinfunction "PD9_D9") (pintype "bidirectional"))
    )
    (net (code "417") (name "unconnected-(U201D-PD10-PadC12)") (class "Default")
      (node (ref "U201") (pin "C12") (pinfunction "PD10_C12") (pintype "bidirectional"))
    )
    (net (code "418") (name "unconnected-(U201D-PD11-PadE11)") (class "Default")
      (node (ref "U201") (pin "E11") (pinfunction "PD11_E11") (pintype "bidirectional"))
    )
    (net (code "419") (name "unconnected-(U201D-PD12-PadG10)") (class "Default")
      (node (ref "U201") (pin "G10") (pinfunction "PD12_G10") (pintype "bidirectional"))
    )
    (net (code "420") (name "unconnected-(U201D-PD13-PadG9)") (class "Default")
      (node (ref "U201") (pin "G9") (pinfunction "PD13_G9") (pintype "bidirectional"))
    )
    (net (code "421") (name "unconnected-(U201D-PD14-PadH10)") (class "Default")
      (node (ref "U201") (pin "H10") (pinfunction "PD14_H10") (pintype "bidirectional"))
    )
    (net (code "422") (name "unconnected-(U201D-PD15-PadA11)") (class "Default")
      (node (ref "U201") (pin "A11") (pinfunction "PD15_A11") (pintype "bidirectional"))
    )
    (net (code "423") (name "unconnected-(U201D-PD16-PadK11)") (class "Default")
      (node (ref "U201") (pin "K11") (pinfunction "PD16_K11") (pintype "bidirectional"))
    )
    (net (code "424") (name "unconnected-(U201D-PD17-PadL11)") (class "Default")
      (node (ref "U201") (pin "L11") (pinfunction "PD17_L11") (pintype "bidirectional"))
    )
    (net (code "425") (name "unconnected-(U201D-PD18-PadM10)") (class "Default")
      (node (ref "U201") (pin "M10") (pinfunction "PD18_M10") (pintype "bidirectional"))
    )
    (net (code "426") (name "unconnected-(U201D-PD19-PadM9)") (class "Default")
      (node (ref "U201") (pin "M9") (pinfunction "PD19_M9") (pintype "bidirectional"))
    )
    (net (code "427") (name "unconnected-(U201D-PD23-PadM7)") (class "Default")
      (node (ref "U201") (pin "M7") (pinfunction "PD23_M7") (pintype "bidirectional"))
    )
    (net (code "428") (name "unconnected-(U201D-PD24-PadM6)") (class "Default")
      (node (ref "U201") (pin "M6") (pinfunction "PD24_M6") (pintype "bidirectional"))
    )
    (net (code "429") (name "unconnected-(U201D-PD25-PadM5)") (class "Default")
      (node (ref "U201") (pin "M5") (pinfunction "PD25_M5") (pintype "bidirectional"))
    )
    (net (code "430") (name "unconnected-(U201D-PD26-PadL6)") (class "Default")
      (node (ref "U201") (pin "L6") (pinfunction "PD26_L6") (pintype "bidirectional"))
    )
    (net (code "431") (name "unconnected-(U201D-PD27-PadJ6)") (class "Default")
      (node (ref "U201") (pin "J6") (pinfunction "PD27_J6") (pintype "bidirectional"))
    )
    (net (code "432") (name "unconnected-(U201D-PD28-PadK10)") (class "Default")
      (node (ref "U201") (pin "K10") (pinfunction "PD28_K10") (pintype "bidirectional"))
    )
    (net (code "433") (name "unconnected-(U201D-PD29-PadD10)") (class "Default")
      (node (ref "U201") (pin "D10") (pinfunction "PD29_D10") (pintype "bidirectional"))
    )
    (net (code "434") (name "unconnected-(U201D-PD30-PadM1)") (class "Default")
      (node (ref "U201") (pin "M1") (pinfunction "PD30_M1") (pintype "bidirectional"))
    )
    (net (code "435") (name "unconnected-(U201D-PD31-PadD3)") (class "Default")
      (node (ref "U201") (pin "D3") (pinfunction "PD31_D3") (pintype "bidirectional"))
    )
    (net (code "436") (name "unconnected-(U201E-PE3-PadE3)") (class "Default")
      (node (ref "U201") (pin "E3") (pinfunction "PE3_E3") (pintype "bidirectional"))
    )
    (net (code "437") (name "unconnected-(U201E-PE4-PadK1)") (class "Default")
      (node (ref "U201") (pin "K1") (pinfunction "PE4_K1") (pintype "bidirectional"))
    )
    (net (code "438") (name "unconnected-(U201E-PE5-PadL1)") (class "Default")
      (node (ref "U201") (pin "L1") (pinfunction "PE5_L1") (pintype "bidirectional"))
    )
    (net (code "439") (name "unconnected-(U301A-IOT_169-PadB15)") (class "Default")
      (node (ref "U301") (pin "B15") (pinfunction "IOT_169_B15") (pintype "bidirectional"))
    )
    (net (code "440") (name "unconnected-(U301A-IOT_171-PadB14)") (class "Default")
      (node (ref "U301") (pin "B14") (pinfunction "IOT_171_B14") (pintype "bidirectional"))
    )
    (net (code "441") (name "unconnected-(U301A-IOT_172-PadC12)") (class "Default")
      (node (ref "U301") (pin "C12") (pinfunction "IOT_172_C12") (pintype "bidirectional"))
    )
    (net (code "442") (name "unconnected-(U301A-IOT_173-PadE11)") (class "Default")
      (node (ref "U301") (pin "E11") (pinfunction "IOT_173_E11") (pintype "bidirectional"))
    )
    (net (code "443") (name "unconnected-(U301A-IOT_178-PadB13)") (class "Default")
      (node (ref "U301") (pin "B13") (pinfunction "IOT_178_B13") (pintype "bidirectional"))
    )
    (net (code "444") (name "unconnected-(U301A-IOT_179-PadE10)") (class "Default")
      (node (ref "U301") (pin "E10") (pinfunction "IOT_179_E10") (pintype "bidirectional"))
    )
    (net (code "445") (name "unconnected-(U301A-IOT_180-PadC11)") (class "Default")
      (node (ref "U301") (pin "C11") (pinfunction "IOT_180_C11") (pintype "bidirectional"))
    )
    (net (code "446") (name "unconnected-(U301A-IOT_181-PadD11)") (class "Default")
      (node (ref "U301") (pin "D11") (pinfunction "IOT_181_D11") (pintype "bidirectional"))
    )
    (net (code "447") (name "unconnected-(U301A-IOT_182-PadB12)") (class "Default")
      (node (ref "U301") (pin "B12") (pinfunction "IOT_182_B12") (pintype "bidirectional"))
    )
    (net (code "448") (name "unconnected-(U301A-IOT_183-PadB10)") (class "Default")
      (node (ref "U301") (pin "B10") (pinfunction "IOT_183_B10") (pintype "bidirectional"))
    )
    (net (code "449") (name "unconnected-(U301A-IOT_184-PadB11)") (class "Default")
      (node (ref "U301") (pin "B11") (pinfunction "IOT_184_B11") (pintype "bidirectional"))
    )
    (net (code "450") (name "unconnected-(U301A-IOT_185-PadC10)") (class "Default")
      (node (ref "U301") (pin "C10") (pinfunction "IOT_185_C10") (pintype "bidirectional"))
    )
    (net (code "451") (name "unconnected-(U301A-IOT_186-PadA10)") (class "Default")
      (node (ref "U301") (pin "A10") (pinfunction "IOT_186_A10") (pintype "bidirectional"))
    )
    (net (code "452") (name "unconnected-(U301A-IOT_187-PadA11)") (class "Default")
      (node (ref "U301") (pin "A11") (pinfunction "IOT_187_A11") (pintype "bidirectional"))
    )
    (net (code "453") (name "unconnected-(U301A-IOT_190-PadD10)") (class "Default")
      (node (ref "U301") (pin "D10") (pinfunction "IOT_190_D10") (pintype "bidirectional"))
    )
    (net (code "454") (name "unconnected-(U301A-IOT_191-PadC9)") (class "Default")
      (node (ref "U301") (pin "C9") (pinfunction "IOT_191_C9") (pintype "bidirectional"))
    )
    (net (code "455") (name "unconnected-(U301A-IOT_192-PadE9)") (class "Default")
      (node (ref "U301") (pin "E9") (pinfunction "IOT_192_E9") (pintype "bidirectional"))
    )
    (net (code "456") (name "unconnected-(U301A-IOT_193-PadD9)") (class "Default")
      (node (ref "U301") (pin "D9") (pinfunction "IOT_193_D9") (pintype "bidirectional"))
    )
    (net (code "457") (name "unconnected-(U301A-IOT_194-PadA9)") (class "Default")
      (node (ref "U301") (pin "A9") (pinfunction "IOT_194_A9") (pintype "bidirectional"))
    )
    (net (code "458") (name "unconnected-(U301A-IOT_196-PadF9)") (class "Default")
      (node (ref "U301") (pin "F9") (pinfunction "IOT_196_F9") (pintype "bidirectional"))
    )
    (net (code "459") (name "unconnected-(U301A-IOT_199-PadB9)") (class "Default")
      (node (ref "U301") (pin "B9") (pinfunction "IOT_199_B9") (pintype "bidirectional"))
    )
    (net (code "460") (name "unconnected-(U301A-IOT_200-PadD8)") (class "Default")
      (node (ref "U301") (pin "D8") (pinfunction "IOT_200_D8") (pintype "bidirectional"))
    )
    (net (code "461") (name "unconnected-(U301A-IOT_203-PadB8)") (class "Default")
      (node (ref "U301") (pin "B8") (pinfunction "IOT_203_B8") (pintype "bidirectional"))
    )
    (net (code "462") (name "unconnected-(U301A-IOT_206-PadC7)") (class "Default")
      (node (ref "U301") (pin "C7") (pinfunction "IOT_206_C7") (pintype "bidirectional"))
    )
    (net (code "463") (name "unconnected-(U301A-IOT_209-PadC6)") (class "Default")
      (node (ref "U301") (pin "C6") (pinfunction "IOT_209_C6") (pintype "bidirectional"))
    )
    (net (code "464") (name "unconnected-(U301A-IOT_210-PadD7)") (class "Default")
      (node (ref "U301") (pin "D7") (pinfunction "IOT_210_D7") (pintype "bidirectional"))
    )
    (net (code "465") (name "unconnected-(U301A-IOT_212-PadD6)") (class "Default")
      (node (ref "U301") (pin "D6") (pinfunction "IOT_212_D6") (pintype "bidirectional"))
    )
    (net (code "466") (name "unconnected-(U301A-IOT_215-PadE6)") (class "Default")
      (node (ref "U301") (pin "E6") (pinfunction "IOT_215_E6") (pintype "bidirectional"))
    )
    (net (code "467") (name "unconnected-(U301A-IOT_219-PadD5)") (class "Default")
      (node (ref "U301") (pin "D5") (pinfunction "IOT_219_D5") (pintype "bidirectional"))
    )
    (net (code "468") (name "unconnected-(U301A-IOT_221-PadC5)") (class "Default")
      (node (ref "U301") (pin "C5") (pinfunction "IOT_221_C5") (pintype "bidirectional"))
    )
    (net (code "469") (name "unconnected-(U301A-IOT_222-PadC4)") (class "Default")
      (node (ref "U301") (pin "C4") (pinfunction "IOT_222_C4") (pintype "bidirectional"))
    )
    (net (code "470") (name "unconnected-(U301A-IOT_224-PadD4)") (class "Default")
      (node (ref "U301") (pin "D4") (pinfunction "IOT_224_D4") (pintype "bidirectional"))
    )
    (net (code "471") (name "unconnected-(U301A-IOT_226-PadD3)") (class "Default")
      (node (ref "U301") (pin "D3") (pinfunction "IOT_226_D3") (pintype "bidirectional"))
    )
    (net (code "472") (name "unconnected-(U301A-IOT_227-PadC3)") (class "Default")
      (node (ref "U301") (pin "C3") (pinfunction "IOT_227_C3") (pintype "bidirectional"))
    )
    (net (code "473") (name "unconnected-(U301B-IOR_111-PadP14)") (class "Default")
      (node (ref "U301") (pin "P14") (pinfunction "IOR_111_P14") (pintype "bidirectional"))
    )
    (net (code "474") (name "unconnected-(U301B-IOR_114-PadM13)") (class "Default")
      (node (ref "U301") (pin "M13") (pinfunction "IOR_114_M13") (pintype "bidirectional"))
    )
    (net (code "475") (name "unconnected-(U301B-IOR_115-PadM14)") (class "Default")
      (node (ref "U301") (pin "M14") (pinfunction "IOR_115_M14") (pintype "bidirectional"))
    )
    (net (code "476") (name "unconnected-(U301B-IOR_116-PadL12)") (class "Default")
      (node (ref "U301") (pin "L12") (pinfunction "IOR_116_L12") (pintype "bidirectional"))
    )
    (net (code "477") (name "unconnected-(U301B-IOR_118-PadL13)") (class "Default")
      (node (ref "U301") (pin "L13") (pinfunction "IOR_118_L13") (pintype "bidirectional"))
    )
    (net (code "478") (name "unconnected-(U301B-IOR_119-PadL14)") (class "Default")
      (node (ref "U301") (pin "L14") (pinfunction "IOR_119_L14") (pintype "bidirectional"))
    )
    (net (code "479") (name "unconnected-(U301B-IOR_120-PadK12)") (class "Default")
      (node (ref "U301") (pin "K12") (pinfunction "IOR_120_K12") (pintype "bidirectional"))
    )
    (net (code "480") (name "unconnected-(U301B-IOR_122-PadJ10)") (class "Default")
      (node (ref "U301") (pin "J10") (pinfunction "IOR_122_J10") (pintype "bidirectional"))
    )
    (net (code "481") (name "unconnected-(U301B-IOR_126-PadJ11)") (class "Default")
      (node (ref "U301") (pin "J11") (pinfunction "IOR_126_J11") (pintype "bidirectional"))
    )
    (net (code "482") (name "unconnected-(U301B-IOR_128-PadK13)") (class "Default")
      (node (ref "U301") (pin "K13") (pinfunction "IOR_128_K13") (pintype "bidirectional"))
    )
    (net (code "483") (name "unconnected-(U301B-IOR_129-PadK14)") (class "Default")
      (node (ref "U301") (pin "K14") (pinfunction "IOR_129_K14") (pintype "bidirectional"))
    )
    (net (code "484") (name "unconnected-(U301B-IOR_130-PadJ15)") (class "Default")
      (node (ref "U301") (pin "J15") (pinfunction "IOR_130_J15") (pintype "bidirectional"))
    )
    (net (code "485") (name "unconnected-(U301B-IOR_134-PadJ14)") (class "Default")
      (node (ref "U301") (pin "J14") (pinfunction "IOR_134_J14") (pintype "bidirectional"))
    )
    (net (code "486") (name "unconnected-(U301B-IOR_136-PadJ12)") (class "Default")
      (node (ref "U301") (pin "J12") (pinfunction "IOR_136_J12") (pintype "bidirectional"))
    )
    (net (code "487") (name "unconnected-(U301B-IOR_137-PadJ13)") (class "Default")
      (node (ref "U301") (pin "J13") (pinfunction "IOR_137_J13") (pintype "bidirectional"))
    )
    (net (code "488") (name "unconnected-(U301B-IOR_138-PadJ16)") (class "Default")
      (node (ref "U301") (pin "J16") (pinfunction "IOR_138_J16") (pintype "bidirectional"))
    )
    (net (code "489") (name "unconnected-(U301B-IOR_139-PadH13)") (class "Default")
      (node (ref "U301") (pin "H13") (pinfunction "IOR_139_H13") (pintype "bidirectional"))
    )
    (net (code "490") (name "unconnected-(U301B-IOR_140_GBIN3-PadH11)") (class "Default")
      (node (ref "U301") (pin "H11") (pinfunction "IOR_140_GBIN3_H11") (pintype "bidirectional"))
    )
    (net (code "491") (name "unconnected-(U301B-IOR_142-PadH14)") (class "Default")
      (node (ref "U301") (pin "H14") (pinfunction "IOR_142_H14") (pintype "bidirectional"))
    )
    (net (code "492") (name "unconnected-(U301B-IOR_143-PadG16)") (class "Default")
      (node (ref "U301") (pin "G16") (pinfunction "IOR_143_G16") (pintype "bidirectional"))
    )
    (net (code "493") (name "unconnected-(U301B-IOR_144-PadH12)") (class "Default")
      (node (ref "U301") (pin "H12") (pinfunction "IOR_144_H12") (pintype "bidirectional"))
    )
    (net (code "494") (name "unconnected-(U301B-IOR_145-PadG15)") (class "Default")
      (node (ref "U301") (pin "G15") (pinfunction "IOR_145_G15") (pintype "bidirectional"))
    )
    (net (code "495") (name "unconnected-(U301B-IOR_146-PadG10)") (class "Default")
      (node (ref "U301") (pin "G10") (pinfunction "IOR_146_G10") (pintype "bidirectional"))
    )
    (net (code "496") (name "unconnected-(U301B-IOR_148-PadG11)") (class "Default")
      (node (ref "U301") (pin "G11") (pinfunction "IOR_148_G11") (pintype "bidirectional"))
    )
    (net (code "497") (name "unconnected-(U301B-IOR_149-PadF15)") (class "Default")
      (node (ref "U301") (pin "F15") (pinfunction "IOR_149_F15") (pintype "bidirectional"))
    )
    (net (code "498") (name "unconnected-(U301B-IOR_150-PadG14)") (class "Default")
      (node (ref "U301") (pin "G14") (pinfunction "IOR_150_G14") (pintype "bidirectional"))
    )
    (net (code "499") (name "unconnected-(U301B-IOR_152-PadG13)") (class "Default")
      (node (ref "U301") (pin "G13") (pinfunction "IOR_152_G13") (pintype "bidirectional"))
    )
    (net (code "500") (name "unconnected-(U301B-IOR_154-PadG12)") (class "Default")
      (node (ref "U301") (pin "G12") (pinfunction "IOR_154_G12") (pintype "bidirectional"))
    )
    (net (code "501") (name "unconnected-(U301B-IOR_155-PadF14)") (class "Default")
      (node (ref "U301") (pin "F14") (pinfunction "IOR_155_F14") (pintype "bidirectional"))
    )
    (net (code "502") (name "unconnected-(U301B-IOR_156-PadF12)") (class "Default")
      (node (ref "U301") (pin "F12") (pinfunction "IOR_156_F12") (pintype "bidirectional"))
    )
    (net (code "503") (name "unconnected-(U301B-IOR_158-PadF11)") (class "Default")
      (node (ref "U301") (pin "F11") (pinfunction "IOR_158_F11") (pintype "bidirectional"))
    )
    (net (code "504") (name "unconnected-(U301B-IOR_162-PadF13)") (class "Default")
      (node (ref "U301") (pin "F13") (pinfunction "IOR_162_F13") (pintype "bidirectional"))
    )
    (net (code "505") (name "unconnected-(U301C-IOB_56-PadN5)") (class "Default")
      (node (ref "U301") (pin "N5") (pinfunction "IOB_56_N5") (pintype "bidirectional"))
    )
    (net (code "506") (name "unconnected-(U301C-IOB_64-PadM7)") (class "Default")
      (node (ref "U301") (pin "M7") (pinfunction "IOB_64_M7") (pintype "bidirectional"))
    )
    (net (code "507") (name "unconnected-(U301C-IOB_67-PadP6)") (class "Default")
      (node (ref "U301") (pin "P6") (pinfunction "IOB_67_P6") (pintype "bidirectional"))
    )
    (net (code "508") (name "unconnected-(U301C-IOB_68-PadM8)") (class "Default")
      (node (ref "U301") (pin "M8") (pinfunction "IOB_68_M8") (pintype "bidirectional"))
    )
    (net (code "509") (name "unconnected-(U301C-IOB_72-PadP8)") (class "Default")
      (node (ref "U301") (pin "P8") (pinfunction "IOB_72_P8") (pintype "bidirectional"))
    )
    (net (code "510") (name "unconnected-(U301C-IOB_74-PadL9)") (class "Default")
      (node (ref "U301") (pin "L9") (pinfunction "IOB_74_L9") (pintype "bidirectional"))
    )
    (net (code "511") (name "unconnected-(U301C-IOB_77-PadP7)") (class "Default")
      (node (ref "U301") (pin "P7") (pinfunction "IOB_77_P7") (pintype "bidirectional"))
    )
    (net (code "512") (name "unconnected-(U301C-IOB_78-PadN9)") (class "Default")
      (node (ref "U301") (pin "N9") (pinfunction "IOB_78_N9") (pintype "bidirectional"))
    )
    (net (code "513") (name "unconnected-(U301C-IOB_80-PadM9)") (class "Default")
      (node (ref "U301") (pin "M9") (pinfunction "IOB_80_M9") (pintype "bidirectional"))
    )
    (net (code "514") (name "unconnected-(U301C-IOB_83-PadP9)") (class "Default")
      (node (ref "U301") (pin "P9") (pinfunction "IOB_83_P9") (pintype "bidirectional"))
    )
    (net (code "515") (name "unconnected-(U301C-IOB_85-PadL10)") (class "Default")
      (node (ref "U301") (pin "L10") (pinfunction "IOB_85_L10") (pintype "bidirectional"))
    )
    (net (code "516") (name "unconnected-(U301C-IOB_86-PadP10)") (class "Default")
      (node (ref "U301") (pin "P10") (pinfunction "IOB_86_P10") (pintype "bidirectional"))
    )
    (net (code "517") (name "unconnected-(U301C-IOB_87-PadN10)") (class "Default")
      (node (ref "U301") (pin "N10") (pinfunction "IOB_87_N10") (pintype "bidirectional"))
    )
    (net (code "518") (name "unconnected-(U301C-IOB_93-PadM11)") (class "Default")
      (node (ref "U301") (pin "M11") (pinfunction "IOB_93_M11") (pintype "bidirectional"))
    )
    (net (code "519") (name "unconnected-(U301C-IOB_98-PadN12)") (class "Default")
      (node (ref "U301") (pin "N12") (pinfunction "IOB_98_N12") (pintype "bidirectional"))
    )
    (net (code "520") (name "unconnected-(U301C-IOB_99-PadL11)") (class "Default")
      (node (ref "U301") (pin "L11") (pinfunction "IOB_99_L11") (pintype "bidirectional"))
    )
    (net (code "521") (name "unconnected-(U301C-IOB_101-PadM12)") (class "Default")
      (node (ref "U301") (pin "M12") (pinfunction "IOB_101_M12") (pintype "bidirectional"))
    )
    (net (code "522") (name "unconnected-(U301D-IOL_2A-PadF5)") (class "Default")
      (node (ref "U301") (pin "F5") (pinfunction "IOL_2A_F5") (pintype "bidirectional"))
    )
    (net (code "523") (name "unconnected-(U301D-IOL_4A-PadF4)") (class "Default")
      (node (ref "U301") (pin "F4") (pinfunction "IOL_4A_F4") (pintype "bidirectional"))
    )
    (net (code "524") (name "unconnected-(U301D-IOL_5A-PadG5)") (class "Default")
      (node (ref "U301") (pin "G5") (pinfunction "IOL_5A_G5") (pintype "bidirectional"))
    )
    (net (code "525") (name "unconnected-(U301D-IOL_6A-PadG4)") (class "Default")
      (node (ref "U301") (pin "G4") (pinfunction "IOL_6A_G4") (pintype "bidirectional"))
    )
    (net (code "526") (name "unconnected-(U301D-IOL_7A-PadH5)") (class "Default")
      (node (ref "U301") (pin "H5") (pinfunction "IOL_7A_H5") (pintype "bidirectional"))
    )
    (net (code "527") (name "unconnected-(U301D-IOL_8A-PadG3)") (class "Default")
      (node (ref "U301") (pin "G3") (pinfunction "IOL_8A_G3") (pintype "bidirectional"))
    )
    (net (code "528") (name "unconnected-(U301D-IOL_10A-PadH6)") (class "Default")
      (node (ref "U301") (pin "H6") (pinfunction "IOL_10A_H6") (pintype "bidirectional"))
    )
    (net (code "529") (name "unconnected-(U301D-IOL_11A-PadH4)") (class "Default")
      (node (ref "U301") (pin "H4") (pinfunction "IOL_11A_H4") (pintype "bidirectional"))
    )
    (net (code "530") (name "unconnected-(U301D-IOL_12A-PadJ4)") (class "Default")
      (node (ref "U301") (pin "J4") (pinfunction "IOL_12A_J4") (pintype "bidirectional"))
    )
    (net (code "531") (name "unconnected-(U301D-IOL_13A-PadJ5)") (class "Default")
      (node (ref "U301") (pin "J5") (pinfunction "IOL_13A_J5") (pintype "bidirectional"))
    )
    (net (code "532") (name "unconnected-(U301D-IOL_14A_GBIN6-PadJ3)") (class "Default")
      (node (ref "U301") (pin "J3") (pinfunction "IOL_14A_GBIN6_J3") (pintype "bidirectional"))
    )
    (net (code "533") (name "unconnected-(U301D-IOL_20A-PadK5)") (class "Default")
      (node (ref "U301") (pin "K5") (pinfunction "IOL_20A_K5") (pintype "bidirectional"))
    )
    (net (code "534") (name "unconnected-(U301D-IOL_21A-PadL7)") (class "Default")
      (node (ref "U301") (pin "L7") (pinfunction "IOL_21A_L7") (pintype "bidirectional"))
    )
    (net (code "535") (name "unconnected-(U301D-IOL_21B-PadN2)") (class "Default")
      (node (ref "U301") (pin "N2") (pinfunction "IOL_21B_N2") (pintype "bidirectional"))
    )
    (net (code "536") (name "unconnected-(U301D-IOL_23B-PadN3)") (class "Default")
      (node (ref "U301") (pin "N3") (pinfunction "IOL_23B_N3") (pintype "bidirectional"))
    )
    (net (code "537") (name "unconnected-(U301D-IOL_26B-PadN4)") (class "Default")
      (node (ref "U301") (pin "N4") (pinfunction "IOL_26B_N4") (pintype "bidirectional"))
    )
    (net (code "538") (name "unconnected-(U402-CLKOUT+-Pad30)") (class "Default")
      (node (ref "U402") (pin "30") (pinfunction "CLKOUT+_30") (pintype "bidirectional"))
    )
    (net (code "539") (name "unconnected-(U402-CLKOUT--Pad29)") (class "Default")
      (node (ref "U402") (pin "29") (pinfunction "CLKOUT-_29") (pintype "bidirectional"))
    )
    (net (code "540") (name "unconnected-(U403-CLKOUT-Pad10)") (class "Default")
      (node (ref "U403") (pin "10") (pinfunction "CLKOUT_10") (pintype "bidirectional"))
    )
    (net (code "541") (name "unconnected-(U403-LT-Pad3)") (class "Default")
      (node (ref "U403") (pin "3") (pinfunction "LT_3") (pintype "bidirectional"))
    )
    (net (code "542") (name "unconnected-(U502-CMLI-Pad31)") (class "Default")
      (node (ref "U502") (pin "31") (pinfunction "CMLI_31") (pintype "bidirectional"))
    )
    (net (code "543") (name "unconnected-(U502-CMLQ-Pad20)") (class "Default")
      (node (ref "U502") (pin "20") (pinfunction "CMLQ_20") (pintype "bidirectional"))
    )
    (net (code "544") (name "unconnected-(U502-RLIN-Pad30)") (class "Default")
      (node (ref "U502") (pin "30") (pinfunction "RLIN_30") (pintype "bidirectional"))
    )
    (net (code "545") (name "unconnected-(U502-RLIP-Pad27)") (class "Default")
      (node (ref "U502") (pin "27") (pinfunction "RLIP_27") (pintype "bidirectional"))
    )
    (net (code "546") (name "unconnected-(U502-RLQN-Pad21)") (class "Default")
      (node (ref "U502") (pin "21") (pinfunction "RLQN_21") (pintype "bidirectional"))
    )
    (net (code "547") (name "unconnected-(U502-RLQP-Pad24)") (class "Default")
      (node (ref "U502") (pin "24") (pinfunction "RLQP_24") (pintype "bidirectional"))
    )
    (net (code "548") (name "unconnected-(U602-RFOUTB+-Pad14)") (class "Default")
      (node (ref "U602") (pin "14") (pinfunction "RFOUTB+_14") (pintype "bidirectional"))
    )
    (net (code "549") (name "unconnected-(U602-RFOUTB--Pad15)") (class "Default")
      (node (ref "U602") (pin "15") (pinfunction "RFOUTB-_15") (pintype "bidirectional"))
    )
    (net (code "550") (name "unconnected-(U701-GPIO0-Pad21)") (class "Default")
      (node (ref "U701") (pin "21") (pinfunction "GPIO0_21") (pintype "bidirectional"))
    )
    (net (code "551") (name "unconnected-(U701-GPIO1-Pad22)") (class "Default")
      (node (ref "U701") (pin "22") (pinfunction "GPIO1_22") (pintype "bidirectional"))
    )
    (net (code "552") (name "unconnected-(U701-XTAL_IN-Pad9)") (class "Default")
      (node (ref "U701") (pin "9") (pinfunction "XTAL_IN_9") (pintype "bidirectional"))
    )
    (net (code "553") (name "unconnected-(U701-XTAL_OUT-Pad10)") (class "Default")
      (node (ref "U701") (pin "10") (pinfunction "XTAL_OUT_10") (pintype "bidirectional"))
    )
    (net (code "554") (name "unconnected-(U702-GPIO0-Pad18)") (class "Default")
      (node (ref "U702") (pin "18") (pinfunction "GPIO0_18") (pintype "bidirectional"))
    )
    (net (code "555") (name "unconnected-(U702-GPIO1-Pad17)") (class "Default")
      (node (ref "U702") (pin "17") (pinfunction "GPIO1_17") (pintype "bidirectional"))
    )
    (net (code "556") (name "unconnected-(U702-GPIO2-Pad16)") (class "Default")
      (node (ref "U702") (pin "16") (pinfunction "GPIO2_16") (pintype "bidirectional"))
    )
    (net (code "557") (name "unconnected-(U702-GPIO3-Pad15)") (class "Default")
      (node (ref "U702") (pin "15") (pinfunction "GPIO3_15") (pintype "bidirectional"))
    )
    (net (code "558") (name "unconnected-(U702-GPIO4-Pad14)") (class "Default")
      (node (ref "U702") (pin "14") (pinfunction "GPIO4_14") (pintype "bidirectional"))
    )
    (net (code "559") (name "unconnected-(U702-GPIO5-Pad13)") (class "Default")
      (node (ref "U702") (pin "13") (pinfunction "GPIO5_13") (pintype "bidirectional"))
    )
    (net (code "560") (name "unconnected-(U702-GPIO6-Pad12)") (class "Default")
      (node (ref "U702") (pin "12") (pinfunction "GPIO6_12") (pintype "bidirectional"))
    )
    (net (code "561") (name "unconnected-(U702-GPIO7-Pad11)") (class "Default")
      (node (ref "U702") (pin "11") (pinfunction "GPIO7_11") (pintype "bidirectional"))
    )
    (net (code "562") (name "unconnected-(U702-GPIO8{slash}VBUS_SENSE{slash}ADC-Pad20)") (class "Default")
      (node (ref "U702") (pin "20") (pinfunction "GPIO8/VBUS_SENSE/ADC_20") (pintype "bidirectional"))
    )
    (net (code "563") (name "unconnected-(U702-GPIO9{slash}BUTTONS-Pad19)") (class "Default")
      (node (ref "U702") (pin "19") (pinfunction "GPIO9/BUTTONS_19") (pintype "bidirectional"))
    )
    (net (code "564") (name "unconnected-(U702-GPIO10{slash}~{RESETOUT}-Pad22)") (class "Default")
      (node (ref "U702") (pin "22") (pinfunction "GPIO10/~{RESETOUT}_22") (pintype "bidirectional"))
    )
    (net (code "565") (name "unconnected-(U702-GPIO11{slash}~{RTS}-Pad27)") (class "Default")
      (node (ref "U702") (pin "27") (pinfunction "GPIO11/~{RTS}_27") (pintype "bidirectional"))
    )
    (net (code "566") (name "unconnected-(U702-GPIO12{slash}CLKOUT-Pad25)") (class "Default")
      (node (ref "U702") (pin "25") (pinfunction "GPIO12/CLKOUT_25") (pintype "bidirectional"))
    )
    (net (code "567") (name "unconnected-(U702-GPIO13{slash}TX-Pad24)") (class "Default")
      (node (ref "U702") (pin "24") (pinfunction "GPIO13/TX_24") (pintype "bidirectional"))
    )
    (net (code "568") (name "unconnected-(U702-GPIO14{slash}RX-Pad23)") (class "Default")
      (node (ref "U702") (pin "23") (pinfunction "GPIO14/RX_23") (pintype "bidirectional"))
    )
    (net (code "569") (name "unconnected-(U702-GPIO15{slash}~{CTS}-Pad31)") (class "Default")
      (node (ref "U702") (pin "31") (pinfunction "GPIO15/~{CTS}_31") (pintype "bidirectional"))
    )
    (net (code "570") (name "unconnected-(U801-TE-Pad39)") (class "Default")
      (node (ref "U801") (pin "39") (pinfunction "TE_39") (pintype "bidirectional"))
    )
    (net (code "571") (name "unconnected-(U902-CLK4-Pad19)") (class "Default")
      (node (ref "U902") (pin "19") (pinfunction "CLK4_19") (pintype "bidirectional"))
    )
    (net (code "572") (name "unconnected-(U902-CLK7-Pad15)") (class "Default")
      (node (ref "U902") (pin "15") (pinfunction "CLK7_15") (pintype "bidirectional"))
    )
    (net (code "573") (name "unconnected-(USB701-SB1-PadA8)") (class "Default")
      (node (ref "USB701") (pin "A8") (pinfunction "SB1_A8") (pintype "bidirectional"))
    )
    (net (code "574") (name "unconnected-(USB701-SB2-PadB8)") (class "Default")
      (node (ref "USB701") (pin "B8") (pinfunction "SB2_B8") (pintype "bidirectional"))
    )
    (net (code "575") (name "unconnected-(USB701-SHIELD-PadSHIELD@0)") (class "Default")
      (node (ref "USB701") (pin "SHIELD@0") (pinfunction "SHIELD_SHIELD@0") (pintype "bidirectional"))
    )
    (net (code "576") (name "unconnected-(USB701-SHIELD-PadSHIELD@1)") (class "Default")
      (node (ref "USB701") (pin "SHIELD@1") (pinfunction "SHIELD_SHIELD@1") (pintype "bidirectional"))
    )
    (net (code "577") (name "unconnected-(USB701-SHIELD-PadSHIELD@2)") (class "Default")
      (node (ref "USB701") (pin "SHIELD@2") (pinfunction "SHIELD_SHIELD@2") (pintype "bidirectional"))
    )
    (net (code "578") (name "unconnected-(USB701-SHIELD-PadSHIELD@3)") (class "Default")
      (node (ref "USB701") (pin "SHIELD@3") (pinfunction "SHIELD_SHIELD@3") (pintype "bidirectional"))
    )
    (net (code "579") (name "unconnected-(USB1001-SB1-PadA8)") (class "Default")
      (node (ref "USB1001") (pin "A8") (pinfunction "SB1_A8") (pintype "bidirectional"))
    )
    (net (code "580") (name "unconnected-(USB1001-SB2-PadB8)") (class "Default")
      (node (ref "USB1001") (pin "B8") (pinfunction "SB2_B8") (pintype "bidirectional"))
    )
    (net (code "581") (name "unconnected-(USB1001-SHIELD-PadSHIELD@0)") (class "Default")
      (node (ref "USB1001") (pin "SHIELD@0") (pinfunction "SHIELD_SHIELD@0") (pintype "bidirectional"))
    )
    (net (code "582") (name "unconnected-(USB1001-SHIELD-PadSHIELD@1)") (class "Default")
      (node (ref "USB1001") (pin "SHIELD@1") (pinfunction "SHIELD_SHIELD@1") (pintype "bidirectional"))
    )
    (net (code "583") (name "unconnected-(USB1001-SHIELD-PadSHIELD@2)") (class "Default")
      (node (ref "USB1001") (pin "SHIELD@2") (pinfunction "SHIELD_SHIELD@2") (pintype "bidirectional"))
    )
    (net (code "584") (name "unconnected-(USB1001-SHIELD-PadSHIELD@3)") (class "Default")
      (node (ref "USB1001") (pin "SHIELD@3") (pinfunction "SHIELD_SHIELD@3") (pintype "bidirectional"))
    )
    (net (code "585") (name "~{CLK_MNGR_IRQ}") (class "Default")
      (node (ref "R903") (pin "1") (pinfunction "1_1") (pintype "passive"))
      (node (ref "U101") (pin "C9") (pinfunction "PE6_C9") (pintype "bidirectional"))
      (node (ref "U902") (pin "3") (pinfunction "INTR_3") (pintype "bidirectional"))
    )
    (net (code "586") (name "~{CLK_MNGR_OE}") (class "Default")
      (node (ref "R902") (pin "1") (pinfunction "1_1") (pintype "passive"))
      (node (ref "U101") (pin "A8") (pinfunction "PF12_A8") (pintype "bidirectional"))
      (node (ref "U902") (pin "7") (pinfunction "~{OE}_7") (pintype "bidirectional"))
    )
    (net (code "587") (name "~{CLK_MNGR_REFCLK_STDBY}") (class "Default")
      (node (ref "R901") (pin "2") (pinfunction "2_2") (pintype "passive"))
      (node (ref "U101") (pin "B7") (pinfunction "PF6_B7") (pintype "bidirectional"))
      (node (ref "U901") (pin "1") (pinfunction "~{STDBY}_1") (pintype "input"))
    )
    (net (code "588") (name "~{CODEC_RST}") (class "Default")
      (node (ref "R703") (pin "1") (pinfunction "1_1") (pintype "passive"))
      (node (ref "U101") (pin "L11") (pinfunction "PD0_L11") (pintype "bidirectional"))
      (node (ref "U701") (pin "7") (pinfunction "~{RST}_7") (pintype "bidirectional"))
    )
    (net (code "589") (name "~{DSP_IRQ}") (class "Default")
      (node (ref "U101") (pin "B2") (pinfunction "PE13_B2") (pintype "bidirectional"))
      (node (ref "U201") (pin "K12") (pinfunction "PA4_K12") (pintype "bidirectional"))
    )
    (net (code "590") (name "~{DSP_RESET}") (class "Default")
      (node (ref "R204") (pin "1") (pinfunction "1_1") (pintype "passive"))
      (node (ref "TC201") (pin "10") (pinfunction "S_10") (pintype "passive"))
      (node (ref "U101") (pin "J8") (pinfunction "PB10_J8") (pintype "bidirectional"))
      (node (ref "U201") (pin "H12") (pinfunction "~{RST}_H12") (pintype "bidirectional"))
    )
    (net (code "591") (name "~{DSP_SPI_CS}") (class "Default")
      (node (ref "U101") (pin "D1") (pinfunction "PA3_D1") (pintype "bidirectional"))
      (node (ref "U201") (pin "J2") (pinfunction "PB2_J2") (pintype "bidirectional"))
    )
    (net (code "592") (name "~{FPGA_CRESET}") (class "Default")
      (node (ref "R301") (pin "2") (pinfunction "2_2") (pintype "passive"))
      (node (ref "U101") (pin "G2") (pinfunction "PB6_G2") (pintype "bidirectional"))
      (node (ref "U301") (pin "N11") (pinfunction "~{CRESET}_N11") (pintype "passive"))
    )
    (net (code "593") (name "~{FPGA_DSP_IRQ}") (class "Default")
      (node (ref "U201") (pin "F1") (pinfunction "PC30_F1") (pintype "bidirectional"))
      (node (ref "U301") (pin "F16") (pinfunction "IOR_147_F16") (pintype "bidirectional"))
    )
    (net (code "594") (name "~{FPGA_MEM_CS}") (class "Default")
      (node (ref "R305") (pin "1") (pinfunction "1_1") (pintype "passive"))
      (node (ref "U301") (pin "E14") (pinfunction "IOR_160_E14") (pintype "bidirectional"))
      (node (ref "U302") (pin "1") (pinfunction "~{CS}_1") (pintype "input"))
    )
    (net (code "595") (name "~{FPGA_SPI_CS}") (class "Default")
      (node (ref "U101") (pin "H1") (pinfunction "PC0_H1") (pintype "bidirectional"))
      (node (ref "U301") (pin "R12") (pinfunction "~{SS}/IOB_108_R12") (pintype "bidirectional"))
    )
    (net (code "596") (name "~{FPGA_SRESET}") (class "Default")
      (node (ref "U101") (pin "E2") (pinfunction "PA5_E2") (pintype "bidirectional"))
      (node (ref "U301") (pin "H16") (pinfunction "IOR_141_GBIN2_H16") (pintype "bidirectional"))
    )
    (net (code "597") (name "~{I2S_BRG_CFG}") (class "Default")
      (node (ref "R707") (pin "1") (pinfunction "1_1") (pintype "passive"))
      (node (ref "U101") (pin "L6") (pinfunction "PB12_L6") (pintype "bidirectional"))
      (node (ref "U702") (pin "21") (pinfunction "~{CFGMODE}_21") (pintype "bidirectional"))
    )
    (net (code "598") (name "~{I2S_BRG_RST}") (class "Default")
      (node (ref "R712") (pin "1") (pinfunction "1_1") (pintype "passive"))
      (node (ref "U101") (pin "L8") (pinfunction "PB13_L8") (pintype "bidirectional"))
      (node (ref "U702") (pin "9") (pinfunction "~{RST}_9") (pintype "bidirectional"))
    )
    (net (code "599") (name "~{RXADC_OE}") (class "Default")
      (node (ref "U301") (pin "P2") (pinfunction "IOL_25A_P2") (pintype "bidirectional"))
      (node (ref "U402") (pin "44") (pinfunction "~{OE}_44") (pintype "bidirectional"))
    )
    (net (code "600") (name "~{SMC_RESET}") (class "Default")
      (node (ref "R106") (pin "1") (pinfunction "1_1") (pintype "passive"))
      (node (ref "TC101") (pin "10") (pinfunction "S_10") (pintype "passive"))
      (node (ref "U101") (pin "K6") (pinfunction "~{RESET}_K6") (pintype "bidirectional"))
    )
    (net (code "601") (name "~{TFT_RESET}") (class "Default")
      (node (ref "U101") (pin "H11") (pinfunction "PD7_H11") (pintype "bidirectional"))
      (node (ref "U801") (pin "10") (pinfunction "~{RESET}_10") (pintype "bidirectional"))
    )
    (net (code "602") (name "~{TFT_SPI_CS}") (class "Default")
      (node (ref "R805") (pin "1") (pinfunction "1_1") (pintype "passive"))
      (node (ref "U101") (pin "J6") (pinfunction "PA10_J6") (pintype "bidirectional"))
      (node (ref "U801") (pin "38") (pinfunction "~{CS}_38") (pintype "bidirectional"))
    )
    (net (code "603") (name "~{TFT_TOUCH_IRQ}") (class "Default")
      (node (ref "U101") (pin "J9") (pinfunction "PD2_J9") (pintype "bidirectional"))
      (node (ref "U801") (pin "46") (pinfunction "X-/~{IRQ}_46") (pintype "bidirectional"))
    )
    (net (code "604") (name "~{TFT_TOUCH_RESET}") (class "Default")
      (node (ref "U101") (pin "J10") (pinfunction "PD3_J10") (pintype "bidirectional"))
      (node (ref "U801") (pin "47") (pinfunction "Y-/~{RST}_47") (pintype "bidirectional"))
    )
    (net (code "605") (name "~{TXDAC_CS}") (class "Default")
      (node (ref "R503") (pin "1") (pinfunction "1_1") (pintype "passive"))
      (node (ref "U101") (pin "A4") (pinfunction "PE9_A4") (pintype "bidirectional"))
      (node (ref "U502") (pin "38") (pinfunction "~{CS}/PWRDN_38") (pintype "bidirectional"))
    )
    (net (code "606") (name "~{TXPA_OC}") (class "Default")
      (node (ref "R1016") (pin "1") (pinfunction "1_1") (pintype "passive"))
      (node (ref "U1003") (pin "4") (pinfunction "~{FAULT}_4") (pintype "bidirectional"))
      (node (ref "U101") (pin "B3") (pinfunction "PE11_B3") (pintype "bidirectional"))
    )
    (net (code "607") (name "~{TXPLL_MUTE}") (class "Default")
      (node (ref "R602") (pin "2") (pinfunction "2_2") (pintype "passive"))
      (node (ref "U101") (pin "B6") (pinfunction "PF8_B6") (pintype "bidirectional"))
      (node (ref "U602") (pin "26") (pinfunction "~{PDRF}_26") (pintype "bidirectional"))
    )
  )
)
